# Lafferty1ab.net
KiCad netlist of a schematic drawn in EAGLE
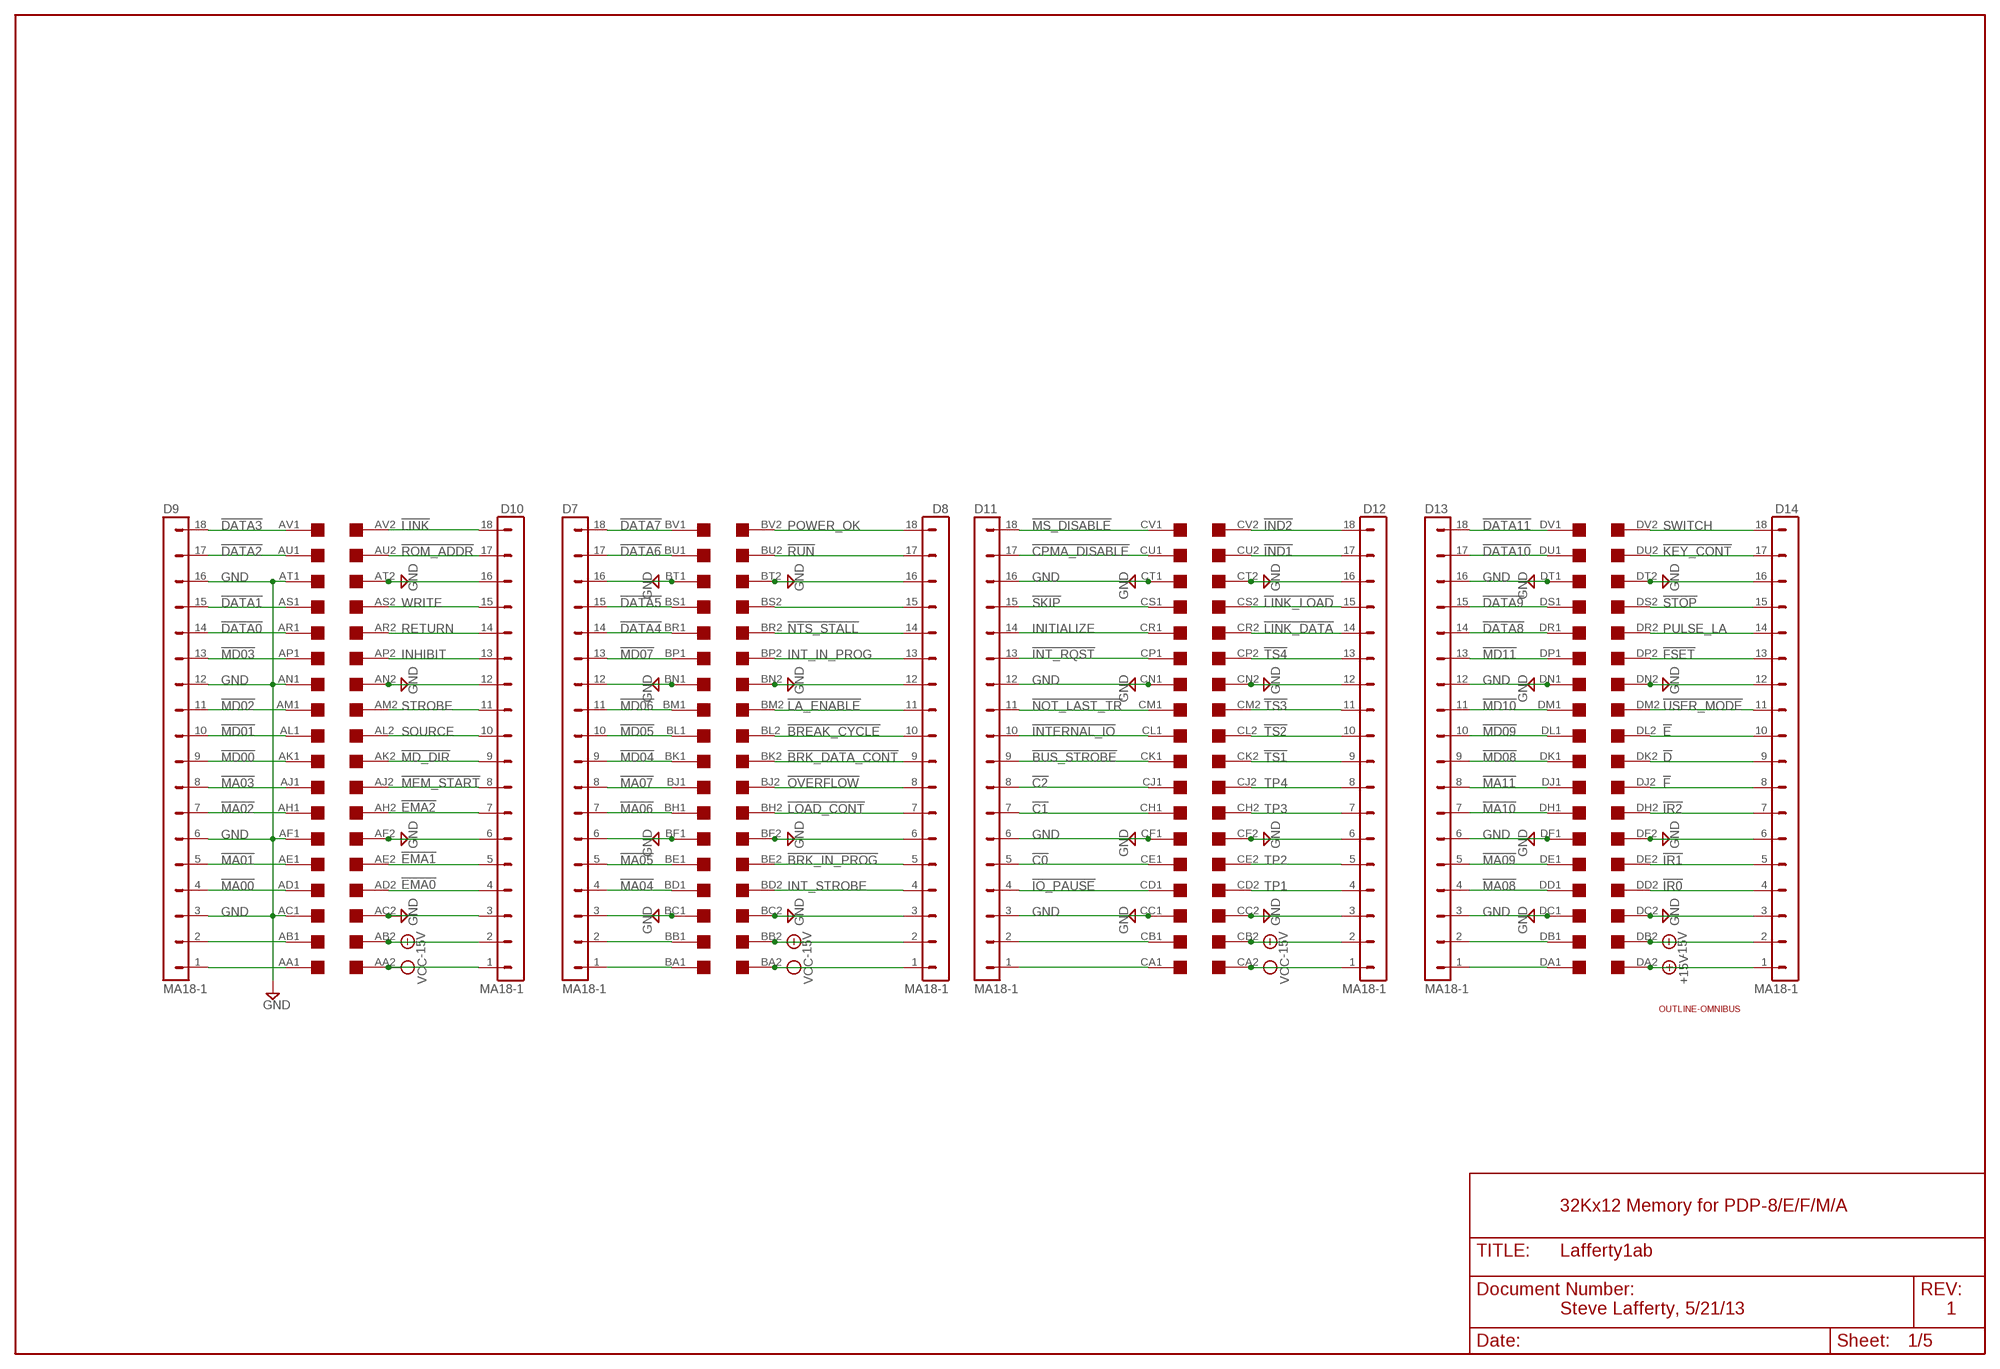
[diagram p0: schematic, sheet 1]
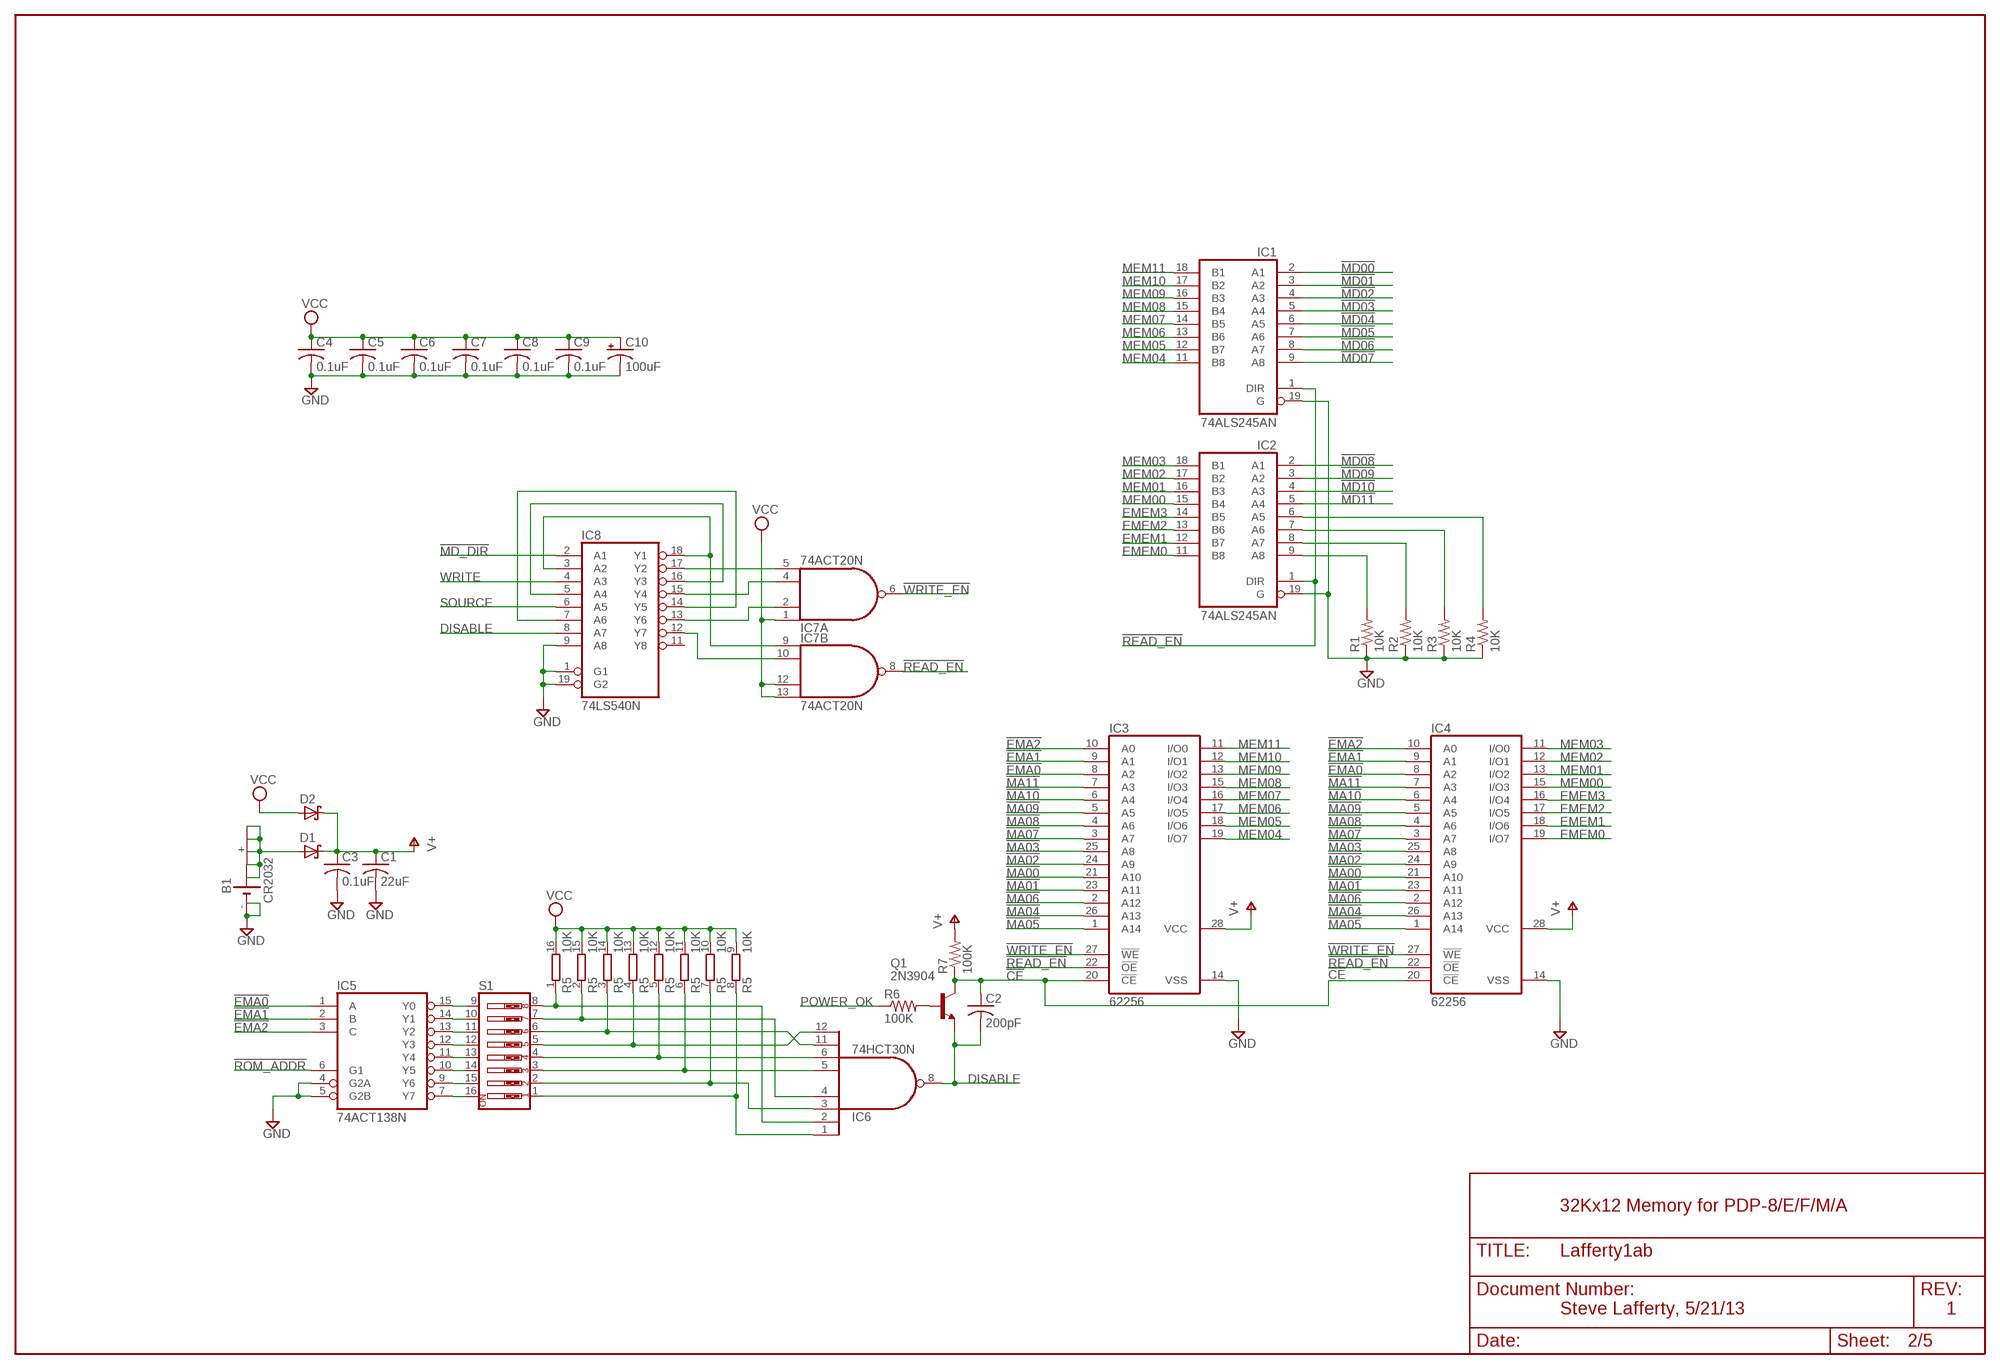
[diagram p1: schematic, sheet 2]
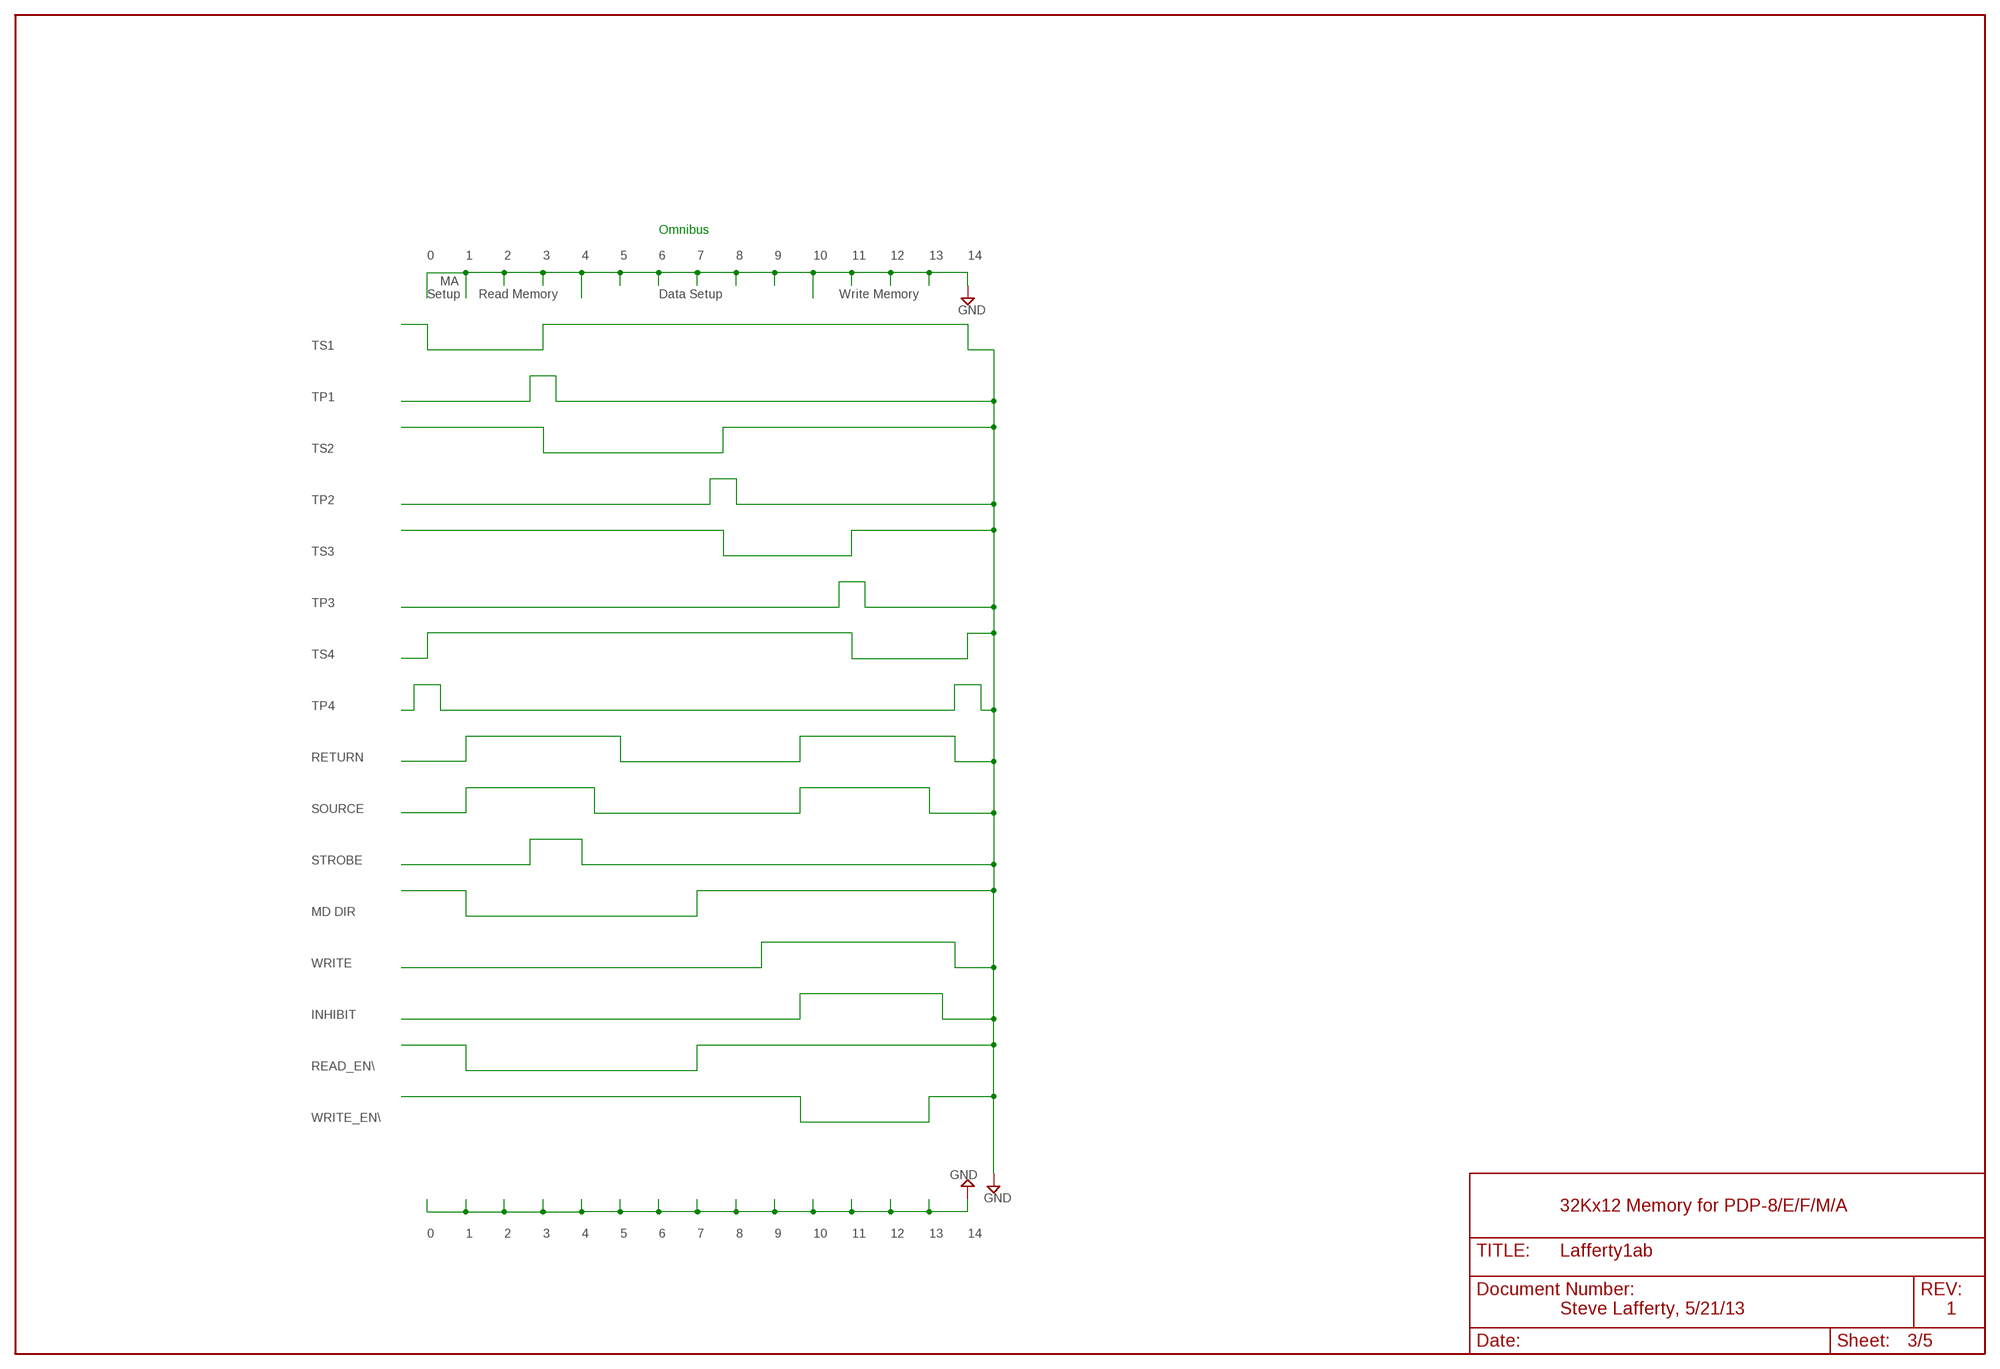
[diagram p2: schematic, sheet 3]
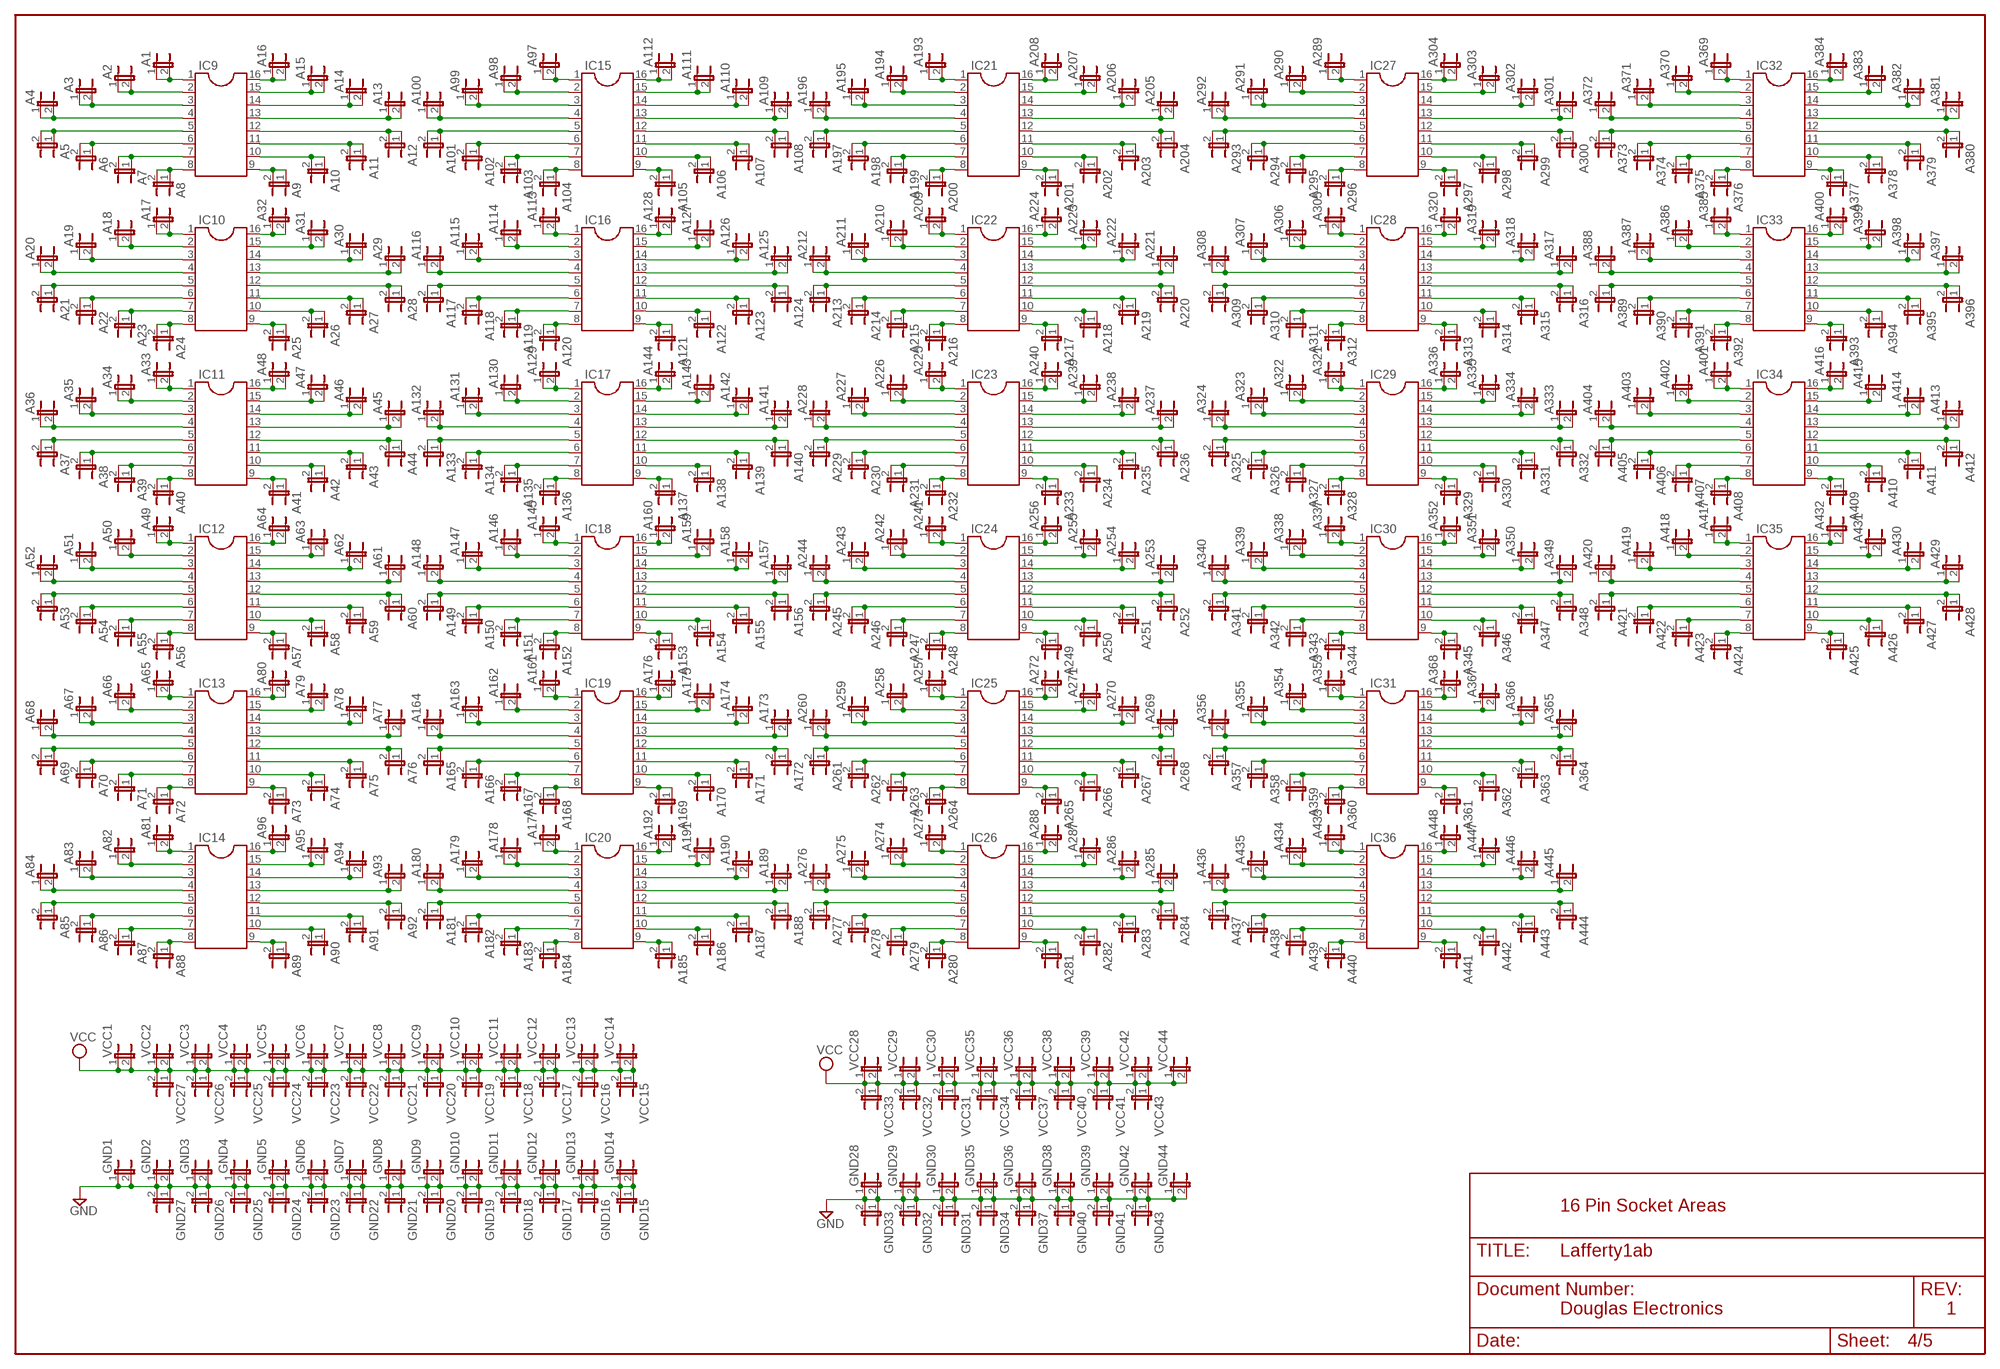
[diagram p3: schematic, sheet 4]
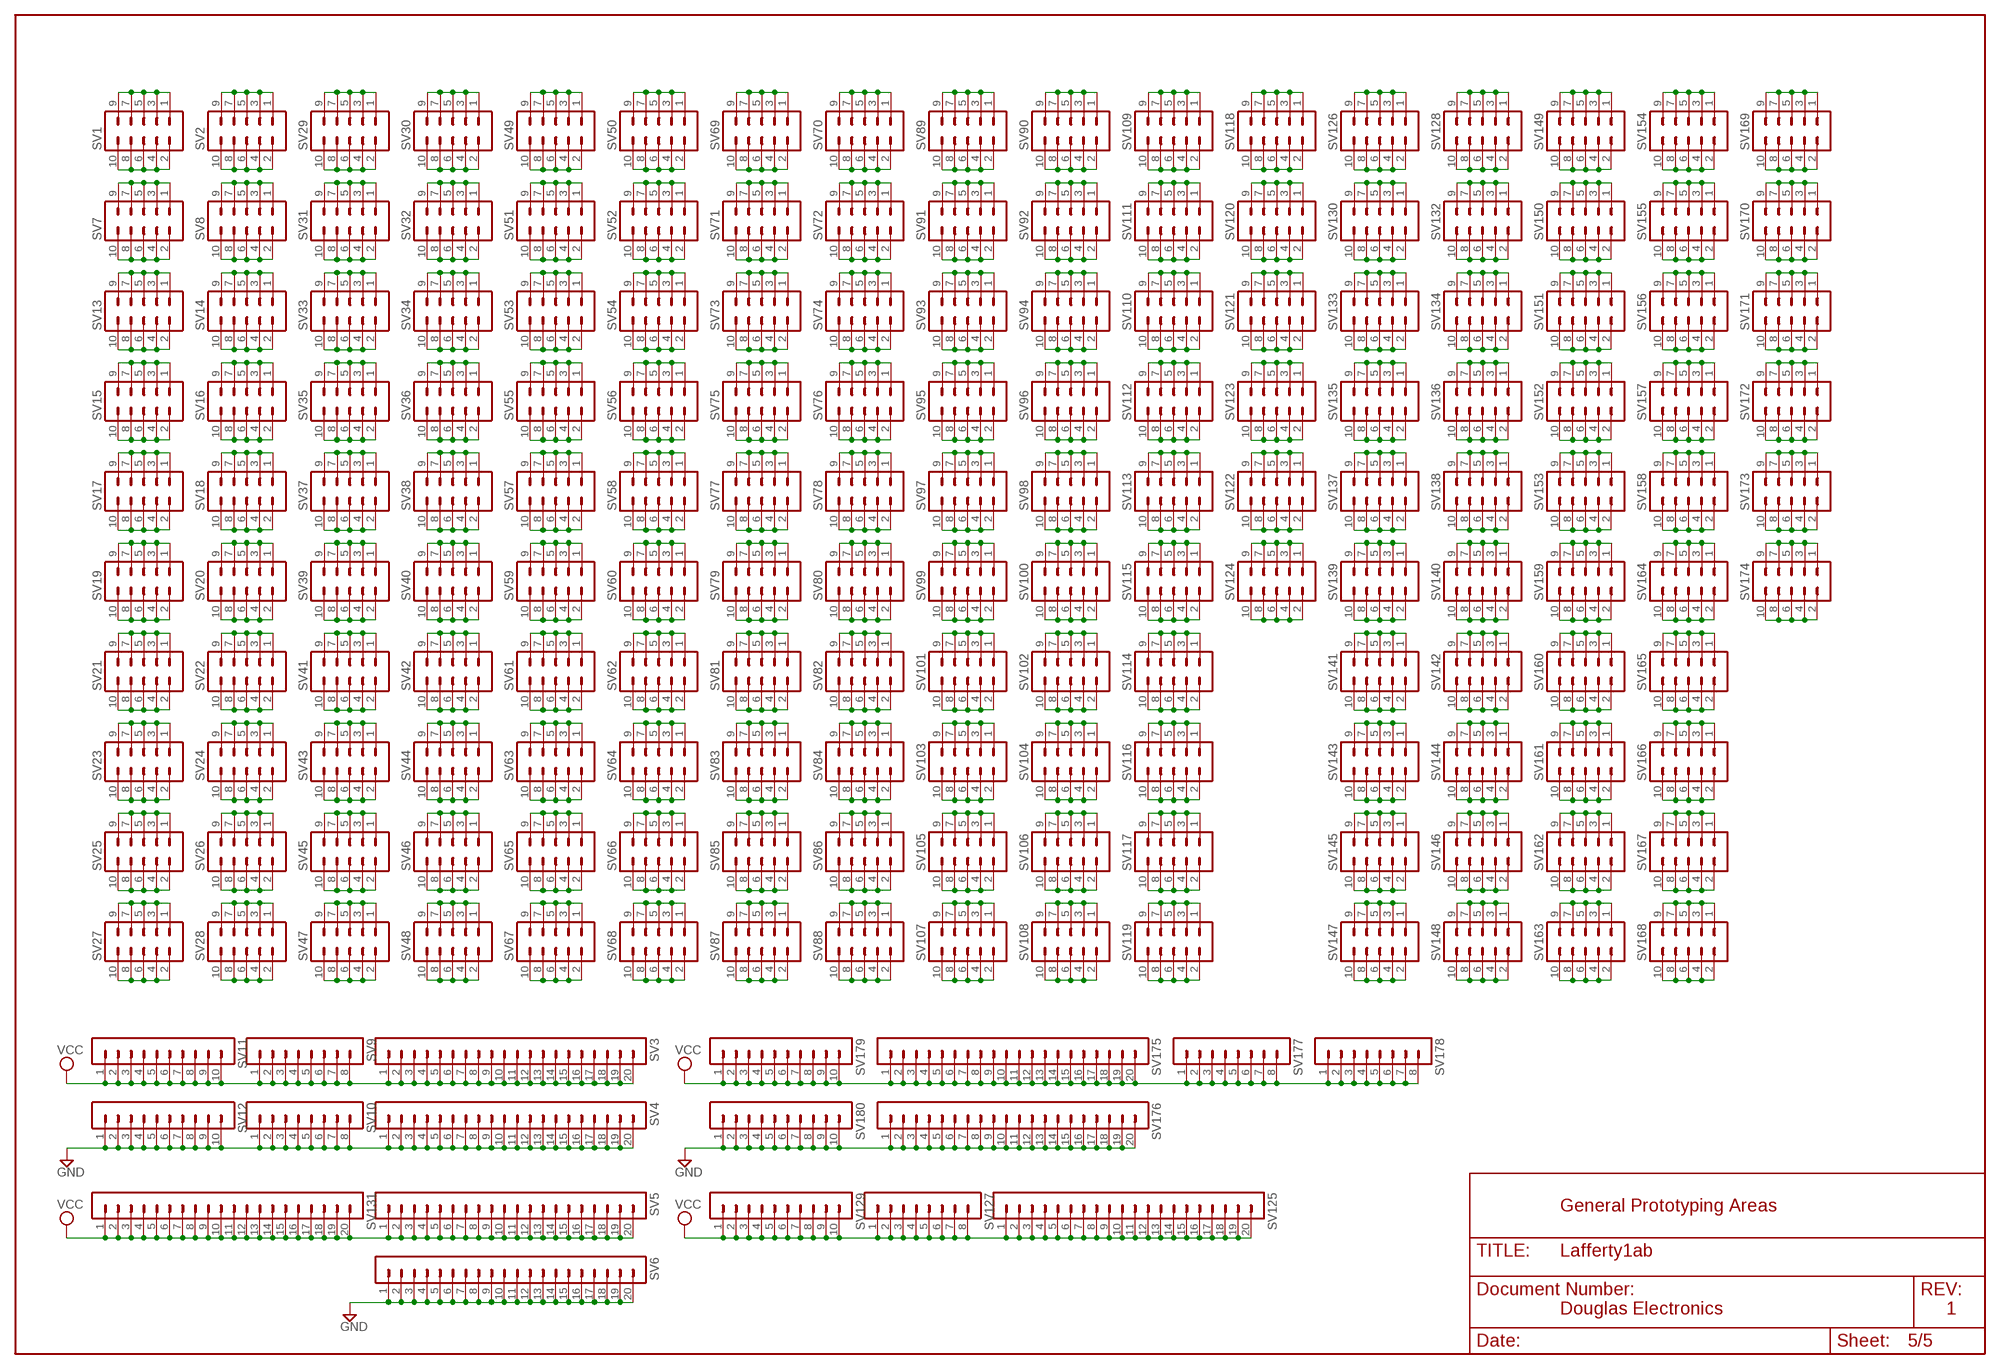
[diagram p4: schematic, sheet 5]

(export (version "E")
  (design (tool "Eeschema 10.0.6"))
  (components
    (comp (ref "D7")
      (value "MA18-1")
      (footprint "eagle-import:MA18-1")
      (libsource (lib "eagle-import") (part "MA18-1"))
    )
    (comp (ref "D8")
      (value "MA18-1")
      (footprint "eagle-import:MA18-1")
      (libsource (lib "eagle-import") (part "MA18-1"))
    )
    (comp (ref "D9")
      (value "MA18-1")
      (footprint "eagle-import:MA18-1")
      (libsource (lib "eagle-import") (part "MA18-1"))
    )
    (comp (ref "D10")
      (value "MA18-1")
      (footprint "eagle-import:MA18-1")
      (libsource (lib "eagle-import") (part "MA18-1"))
    )
    (comp (ref "D11")
      (value "MA18-1")
      (footprint "eagle-import:MA18-1")
      (libsource (lib "eagle-import") (part "MA18-1"))
    )
    (comp (ref "D12")
      (value "MA18-1")
      (footprint "eagle-import:MA18-1")
      (libsource (lib "eagle-import") (part "MA18-1"))
    )
    (comp (ref "D13")
      (value "MA18-1")
      (footprint "eagle-import:MA18-1")
      (libsource (lib "eagle-import") (part "MA18-1"))
    )
    (comp (ref "D14")
      (value "MA18-1")
      (footprint "eagle-import:MA18-1")
      (libsource (lib "eagle-import") (part "MA18-1"))
    )
    (comp (ref "U$1")
      (value "OUTLINE-OMNIBUS")
      (footprint "eagle-import:OMNIBUS")
      (libsource (lib "eagle-import") (part "OUTLINE-OMNIBUS"))
    )
    (comp (ref "U$2")
      (value "QUAD")
      (footprint "eagle-import:EDGE-CON8")
      (libsource (lib "eagle-import") (part "QUAD"))
    )
    (comp (ref "B1")
      (value "CR2032")
      (footprint "eagle-import:B2430UNI")
      (libsource (lib "eagle-import") (part "B2430UNI"))
    )
    (comp (ref "C1")
      (value "22uF")
      (footprint "eagle-import:C050-025X075")
      (libsource (lib "eagle-import") (part "C-US050-025X075"))
    )
    (comp (ref "C2")
      (value "200pF")
      (footprint "eagle-import:C050-025X075")
      (libsource (lib "eagle-import") (part "C-US050-025X075"))
    )
    (comp (ref "C3")
      (value "0.1uF")
      (footprint "eagle-import:C050-025X075")
      (libsource (lib "eagle-import") (part "C-US050-025X075"))
    )
    (comp (ref "C4")
      (value "0.1uF")
      (footprint "eagle-import:C050-025X075")
      (libsource (lib "eagle-import") (part "C-US050-025X075"))
    )
    (comp (ref "C5")
      (value "0.1uF")
      (footprint "eagle-import:C050-025X075")
      (libsource (lib "eagle-import") (part "C-US050-025X075"))
    )
    (comp (ref "C6")
      (value "0.1uF")
      (footprint "eagle-import:C050-025X075")
      (libsource (lib "eagle-import") (part "C-US050-025X075"))
    )
    (comp (ref "C7")
      (value "0.1uF")
      (footprint "eagle-import:C050-025X075")
      (libsource (lib "eagle-import") (part "C-US050-025X075"))
    )
    (comp (ref "C8")
      (value "0.1uF")
      (footprint "eagle-import:C050-025X075")
      (libsource (lib "eagle-import") (part "C-US050-025X075"))
    )
    (comp (ref "C9")
      (value "0.1uF")
      (footprint "eagle-import:C050-025X075")
      (libsource (lib "eagle-import") (part "C-US050-025X075"))
    )
    (comp (ref "C10")
      (value "100uF")
      (footprint "eagle-import:E12-8")
      (libsource (lib "eagle-import") (part "CPOL-USE20-8AXIAL"))
    )
    (comp (ref "D1")
      (value "BAT19")
      (footprint "eagle-import:DO35-10")
      (libsource (lib "eagle-import") (part "BAT19"))
    )
    (comp (ref "D2")
      (value "BAT19")
      (footprint "eagle-import:DO35-10")
      (libsource (lib "eagle-import") (part "BAT19"))
    )
    (comp (ref "IC1")
      (value "74ALS245AN")
      (footprint "eagle-import:DIL20")
      (libsource (lib "eagle-import") (part "74245NLS"))
    )
    (comp (ref "IC2")
      (value "74ALS245AN")
      (footprint "eagle-import:DIL20")
      (libsource (lib "eagle-import") (part "74245NLS"))
    )
    (comp (ref "IC3")
      (value "62256")
      (footprint "eagle-import:DIL28-6")
      (libsource (lib "eagle-import") (part "58C256P"))
    )
    (comp (ref "IC4")
      (value "62256")
      (footprint "eagle-import:DIL28-6")
      (libsource (lib "eagle-import") (part "58C256P"))
    )
    (comp (ref "IC5")
      (value "74ACT138N")
      (footprint "eagle-import:DIL16")
      (libsource (lib "eagle-import") (part "74138NLS"))
    )
    (comp (ref "IC6")
      (value "74HCT30N")
      (footprint "eagle-import:DIL14")
      (libsource (lib "eagle-import") (part "7430NLS"))
    )
    (comp (ref "IC7")
      (value "74ACT20N")
      (footprint "eagle-import:DIL14")
      (libsource (lib "eagle-import") (part "7420NLS"))
    )
    (comp (ref "IC8")
      (value "74LS540N")
      (footprint "eagle-import:DIL20")
      (libsource (lib "eagle-import") (part "74540NLS"))
    )
    (comp (ref "Q1")
      (value "2N3904")
      (footprint "eagle-import:TO92")
      (libsource (lib "eagle-import") (part "2N3904"))
    )
    (comp (ref "R1")
      (value "10K")
      (footprint "eagle-import:0207_10")
      (libsource (lib "eagle-import") (part "R-US_0207/10"))
    )
    (comp (ref "R2")
      (value "10K")
      (footprint "eagle-import:0207_10")
      (libsource (lib "eagle-import") (part "R-US_0207/10"))
    )
    (comp (ref "R3")
      (value "10K")
      (footprint "eagle-import:0207_10")
      (libsource (lib "eagle-import") (part "R-US_0207/10"))
    )
    (comp (ref "R4")
      (value "10K")
      (footprint "eagle-import:0207_10")
      (libsource (lib "eagle-import") (part "R-US_0207/10"))
    )
    (comp (ref "R5")
      (value "10K")
      (footprint "eagle-import:DIL16")
      (libsource (lib "eagle-import") (part "8R-P"))
    )
    (comp (ref "R6")
      (value "100K")
      (footprint "eagle-import:0207_10")
      (libsource (lib "eagle-import") (part "R-US_0207/10"))
    )
    (comp (ref "R7")
      (value "100K")
      (footprint "eagle-import:0207_10")
      (libsource (lib "eagle-import") (part "R-US_0207/10"))
    )
    (comp (ref "S1")
      (value "SW_DIP-8")
      (footprint "eagle-import:EDG-08")
      (libsource (lib "eagle-import") (part "SW_DIP-8"))
    )
    (comp (ref "A1")
      (value "JP1E")
      (footprint "eagle-import:JP1")
      (libsource (lib "eagle-import") (part "JP1E"))
    )
    (comp (ref "A2")
      (value "JP1E")
      (footprint "eagle-import:JP1")
      (libsource (lib "eagle-import") (part "JP1E"))
    )
    (comp (ref "A3")
      (value "JP1E")
      (footprint "eagle-import:JP1")
      (libsource (lib "eagle-import") (part "JP1E"))
    )
    (comp (ref "A4")
      (value "JP1E")
      (footprint "eagle-import:JP1")
      (libsource (lib "eagle-import") (part "JP1E"))
    )
    (comp (ref "A5")
      (value "JP1E")
      (footprint "eagle-import:JP1")
      (libsource (lib "eagle-import") (part "JP1E"))
    )
    (comp (ref "A6")
      (value "JP1E")
      (footprint "eagle-import:JP1")
      (libsource (lib "eagle-import") (part "JP1E"))
    )
    (comp (ref "A7")
      (value "JP1E")
      (footprint "eagle-import:JP1")
      (libsource (lib "eagle-import") (part "JP1E"))
    )
    (comp (ref "A8")
      (value "JP1E")
      (footprint "eagle-import:JP1")
      (libsource (lib "eagle-import") (part "JP1E"))
    )
    (comp (ref "A9")
      (value "JP1E")
      (footprint "eagle-import:JP1")
      (libsource (lib "eagle-import") (part "JP1E"))
    )
    (comp (ref "A10")
      (value "JP1E")
      (footprint "eagle-import:JP1")
      (libsource (lib "eagle-import") (part "JP1E"))
    )
    (comp (ref "A11")
      (value "JP1E")
      (footprint "eagle-import:JP1")
      (libsource (lib "eagle-import") (part "JP1E"))
    )
    (comp (ref "A12")
      (value "JP1E")
      (footprint "eagle-import:JP1")
      (libsource (lib "eagle-import") (part "JP1E"))
    )
    (comp (ref "A13")
      (value "JP1E")
      (footprint "eagle-import:JP1")
      (libsource (lib "eagle-import") (part "JP1E"))
    )
    (comp (ref "A14")
      (value "JP1E")
      (footprint "eagle-import:JP1")
      (libsource (lib "eagle-import") (part "JP1E"))
    )
    (comp (ref "A15")
      (value "JP1E")
      (footprint "eagle-import:JP1")
      (libsource (lib "eagle-import") (part "JP1E"))
    )
    (comp (ref "A16")
      (value "JP1E")
      (footprint "eagle-import:JP1")
      (libsource (lib "eagle-import") (part "JP1E"))
    )
    (comp (ref "A17")
      (value "JP1E")
      (footprint "eagle-import:JP1")
      (libsource (lib "eagle-import") (part "JP1E"))
    )
    (comp (ref "A18")
      (value "JP1E")
      (footprint "eagle-import:JP1")
      (libsource (lib "eagle-import") (part "JP1E"))
    )
    (comp (ref "A19")
      (value "JP1E")
      (footprint "eagle-import:JP1")
      (libsource (lib "eagle-import") (part "JP1E"))
    )
    (comp (ref "A20")
      (value "JP1E")
      (footprint "eagle-import:JP1")
      (libsource (lib "eagle-import") (part "JP1E"))
    )
    (comp (ref "A21")
      (value "JP1E")
      (footprint "eagle-import:JP1")
      (libsource (lib "eagle-import") (part "JP1E"))
    )
    (comp (ref "A22")
      (value "JP1E")
      (footprint "eagle-import:JP1")
      (libsource (lib "eagle-import") (part "JP1E"))
    )
    (comp (ref "A23")
      (value "JP1E")
      (footprint "eagle-import:JP1")
      (libsource (lib "eagle-import") (part "JP1E"))
    )
    (comp (ref "A24")
      (value "JP1E")
      (footprint "eagle-import:JP1")
      (libsource (lib "eagle-import") (part "JP1E"))
    )
    (comp (ref "A25")
      (value "JP1E")
      (footprint "eagle-import:JP1")
      (libsource (lib "eagle-import") (part "JP1E"))
    )
    (comp (ref "A26")
      (value "JP1E")
      (footprint "eagle-import:JP1")
      (libsource (lib "eagle-import") (part "JP1E"))
    )
    (comp (ref "A27")
      (value "JP1E")
      (footprint "eagle-import:JP1")
      (libsource (lib "eagle-import") (part "JP1E"))
    )
    (comp (ref "A28")
      (value "JP1E")
      (footprint "eagle-import:JP1")
      (libsource (lib "eagle-import") (part "JP1E"))
    )
    (comp (ref "A29")
      (value "JP1E")
      (footprint "eagle-import:JP1")
      (libsource (lib "eagle-import") (part "JP1E"))
    )
    (comp (ref "A30")
      (value "JP1E")
      (footprint "eagle-import:JP1")
      (libsource (lib "eagle-import") (part "JP1E"))
    )
    (comp (ref "A31")
      (value "JP1E")
      (footprint "eagle-import:JP1")
      (libsource (lib "eagle-import") (part "JP1E"))
    )
    (comp (ref "A32")
      (value "JP1E")
      (footprint "eagle-import:JP1")
      (libsource (lib "eagle-import") (part "JP1E"))
    )
    (comp (ref "A33")
      (value "JP1E")
      (footprint "eagle-import:JP1")
      (libsource (lib "eagle-import") (part "JP1E"))
    )
    (comp (ref "A34")
      (value "JP1E")
      (footprint "eagle-import:JP1")
      (libsource (lib "eagle-import") (part "JP1E"))
    )
    (comp (ref "A35")
      (value "JP1E")
      (footprint "eagle-import:JP1")
      (libsource (lib "eagle-import") (part "JP1E"))
    )
    (comp (ref "A36")
      (value "JP1E")
      (footprint "eagle-import:JP1")
      (libsource (lib "eagle-import") (part "JP1E"))
    )
    (comp (ref "A37")
      (value "JP1E")
      (footprint "eagle-import:JP1")
      (libsource (lib "eagle-import") (part "JP1E"))
    )
    (comp (ref "A38")
      (value "JP1E")
      (footprint "eagle-import:JP1")
      (libsource (lib "eagle-import") (part "JP1E"))
    )
    (comp (ref "A39")
      (value "JP1E")
      (footprint "eagle-import:JP1")
      (libsource (lib "eagle-import") (part "JP1E"))
    )
    (comp (ref "A40")
      (value "JP1E")
      (footprint "eagle-import:JP1")
      (libsource (lib "eagle-import") (part "JP1E"))
    )
    (comp (ref "A41")
      (value "JP1E")
      (footprint "eagle-import:JP1")
      (libsource (lib "eagle-import") (part "JP1E"))
    )
    (comp (ref "A42")
      (value "JP1E")
      (footprint "eagle-import:JP1")
      (libsource (lib "eagle-import") (part "JP1E"))
    )
    (comp (ref "A43")
      (value "JP1E")
      (footprint "eagle-import:JP1")
      (libsource (lib "eagle-import") (part "JP1E"))
    )
    (comp (ref "A44")
      (value "JP1E")
      (footprint "eagle-import:JP1")
      (libsource (lib "eagle-import") (part "JP1E"))
    )
    (comp (ref "A45")
      (value "JP1E")
      (footprint "eagle-import:JP1")
      (libsource (lib "eagle-import") (part "JP1E"))
    )
    (comp (ref "A46")
      (value "JP1E")
      (footprint "eagle-import:JP1")
      (libsource (lib "eagle-import") (part "JP1E"))
    )
    (comp (ref "A47")
      (value "JP1E")
      (footprint "eagle-import:JP1")
      (libsource (lib "eagle-import") (part "JP1E"))
    )
    (comp (ref "A48")
      (value "JP1E")
      (footprint "eagle-import:JP1")
      (libsource (lib "eagle-import") (part "JP1E"))
    )
    (comp (ref "A49")
      (value "JP1E")
      (footprint "eagle-import:JP1")
      (libsource (lib "eagle-import") (part "JP1E"))
    )
    (comp (ref "A50")
      (value "JP1E")
      (footprint "eagle-import:JP1")
      (libsource (lib "eagle-import") (part "JP1E"))
    )
    (comp (ref "A51")
      (value "JP1E")
      (footprint "eagle-import:JP1")
      (libsource (lib "eagle-import") (part "JP1E"))
    )
    (comp (ref "A52")
      (value "JP1E")
      (footprint "eagle-import:JP1")
      (libsource (lib "eagle-import") (part "JP1E"))
    )
    (comp (ref "A53")
      (value "JP1E")
      (footprint "eagle-import:JP1")
      (libsource (lib "eagle-import") (part "JP1E"))
    )
    (comp (ref "A54")
      (value "JP1E")
      (footprint "eagle-import:JP1")
      (libsource (lib "eagle-import") (part "JP1E"))
    )
    (comp (ref "A55")
      (value "JP1E")
      (footprint "eagle-import:JP1")
      (libsource (lib "eagle-import") (part "JP1E"))
    )
    (comp (ref "A56")
      (value "JP1E")
      (footprint "eagle-import:JP1")
      (libsource (lib "eagle-import") (part "JP1E"))
    )
    (comp (ref "A57")
      (value "JP1E")
      (footprint "eagle-import:JP1")
      (libsource (lib "eagle-import") (part "JP1E"))
    )
    (comp (ref "A58")
      (value "JP1E")
      (footprint "eagle-import:JP1")
      (libsource (lib "eagle-import") (part "JP1E"))
    )
    (comp (ref "A59")
      (value "JP1E")
      (footprint "eagle-import:JP1")
      (libsource (lib "eagle-import") (part "JP1E"))
    )
    (comp (ref "A60")
      (value "JP1E")
      (footprint "eagle-import:JP1")
      (libsource (lib "eagle-import") (part "JP1E"))
    )
    (comp (ref "A61")
      (value "JP1E")
      (footprint "eagle-import:JP1")
      (libsource (lib "eagle-import") (part "JP1E"))
    )
    (comp (ref "A62")
      (value "JP1E")
      (footprint "eagle-import:JP1")
      (libsource (lib "eagle-import") (part "JP1E"))
    )
    (comp (ref "A63")
      (value "JP1E")
      (footprint "eagle-import:JP1")
      (libsource (lib "eagle-import") (part "JP1E"))
    )
    (comp (ref "A64")
      (value "JP1E")
      (footprint "eagle-import:JP1")
      (libsource (lib "eagle-import") (part "JP1E"))
    )
    (comp (ref "A65")
      (value "JP1E")
      (footprint "eagle-import:JP1")
      (libsource (lib "eagle-import") (part "JP1E"))
    )
    (comp (ref "A66")
      (value "JP1E")
      (footprint "eagle-import:JP1")
      (libsource (lib "eagle-import") (part "JP1E"))
    )
    (comp (ref "A67")
      (value "JP1E")
      (footprint "eagle-import:JP1")
      (libsource (lib "eagle-import") (part "JP1E"))
    )
    (comp (ref "A68")
      (value "JP1E")
      (footprint "eagle-import:JP1")
      (libsource (lib "eagle-import") (part "JP1E"))
    )
    (comp (ref "A69")
      (value "JP1E")
      (footprint "eagle-import:JP1")
      (libsource (lib "eagle-import") (part "JP1E"))
    )
    (comp (ref "A70")
      (value "JP1E")
      (footprint "eagle-import:JP1")
      (libsource (lib "eagle-import") (part "JP1E"))
    )
    (comp (ref "A71")
      (value "JP1E")
      (footprint "eagle-import:JP1")
      (libsource (lib "eagle-import") (part "JP1E"))
    )
    (comp (ref "A72")
      (value "JP1E")
      (footprint "eagle-import:JP1")
      (libsource (lib "eagle-import") (part "JP1E"))
    )
    (comp (ref "A73")
      (value "JP1E")
      (footprint "eagle-import:JP1")
      (libsource (lib "eagle-import") (part "JP1E"))
    )
    (comp (ref "A74")
      (value "JP1E")
      (footprint "eagle-import:JP1")
      (libsource (lib "eagle-import") (part "JP1E"))
    )
    (comp (ref "A75")
      (value "JP1E")
      (footprint "eagle-import:JP1")
      (libsource (lib "eagle-import") (part "JP1E"))
    )
    (comp (ref "A76")
      (value "JP1E")
      (footprint "eagle-import:JP1")
      (libsource (lib "eagle-import") (part "JP1E"))
    )
    (comp (ref "A77")
      (value "JP1E")
      (footprint "eagle-import:JP1")
      (libsource (lib "eagle-import") (part "JP1E"))
    )
    (comp (ref "A78")
      (value "JP1E")
      (footprint "eagle-import:JP1")
      (libsource (lib "eagle-import") (part "JP1E"))
    )
    (comp (ref "A79")
      (value "JP1E")
      (footprint "eagle-import:JP1")
      (libsource (lib "eagle-import") (part "JP1E"))
    )
    (comp (ref "A80")
      (value "JP1E")
      (footprint "eagle-import:JP1")
      (libsource (lib "eagle-import") (part "JP1E"))
    )
    (comp (ref "A81")
      (value "JP1E")
      (footprint "eagle-import:JP1")
      (libsource (lib "eagle-import") (part "JP1E"))
    )
    (comp (ref "A82")
      (value "JP1E")
      (footprint "eagle-import:JP1")
      (libsource (lib "eagle-import") (part "JP1E"))
    )
    (comp (ref "A83")
      (value "JP1E")
      (footprint "eagle-import:JP1")
      (libsource (lib "eagle-import") (part "JP1E"))
    )
    (comp (ref "A84")
      (value "JP1E")
      (footprint "eagle-import:JP1")
      (libsource (lib "eagle-import") (part "JP1E"))
    )
    (comp (ref "A85")
      (value "JP1E")
      (footprint "eagle-import:JP1")
      (libsource (lib "eagle-import") (part "JP1E"))
    )
    (comp (ref "A86")
      (value "JP1E")
      (footprint "eagle-import:JP1")
      (libsource (lib "eagle-import") (part "JP1E"))
    )
    (comp (ref "A87")
      (value "JP1E")
      (footprint "eagle-import:JP1")
      (libsource (lib "eagle-import") (part "JP1E"))
    )
    (comp (ref "A88")
      (value "JP1E")
      (footprint "eagle-import:JP1")
      (libsource (lib "eagle-import") (part "JP1E"))
    )
    (comp (ref "A89")
      (value "JP1E")
      (footprint "eagle-import:JP1")
      (libsource (lib "eagle-import") (part "JP1E"))
    )
    (comp (ref "A90")
      (value "JP1E")
      (footprint "eagle-import:JP1")
      (libsource (lib "eagle-import") (part "JP1E"))
    )
    (comp (ref "A91")
      (value "JP1E")
      (footprint "eagle-import:JP1")
      (libsource (lib "eagle-import") (part "JP1E"))
    )
    (comp (ref "A92")
      (value "JP1E")
      (footprint "eagle-import:JP1")
      (libsource (lib "eagle-import") (part "JP1E"))
    )
    (comp (ref "A93")
      (value "JP1E")
      (footprint "eagle-import:JP1")
      (libsource (lib "eagle-import") (part "JP1E"))
    )
    (comp (ref "A94")
      (value "JP1E")
      (footprint "eagle-import:JP1")
      (libsource (lib "eagle-import") (part "JP1E"))
    )
    (comp (ref "A95")
      (value "JP1E")
      (footprint "eagle-import:JP1")
      (libsource (lib "eagle-import") (part "JP1E"))
    )
    (comp (ref "A96")
      (value "JP1E")
      (footprint "eagle-import:JP1")
      (libsource (lib "eagle-import") (part "JP1E"))
    )
    (comp (ref "A97")
      (value "JP1E")
      (footprint "eagle-import:JP1")
      (libsource (lib "eagle-import") (part "JP1E"))
    )
    (comp (ref "A98")
      (value "JP1E")
      (footprint "eagle-import:JP1")
      (libsource (lib "eagle-import") (part "JP1E"))
    )
    (comp (ref "A99")
      (value "JP1E")
      (footprint "eagle-import:JP1")
      (libsource (lib "eagle-import") (part "JP1E"))
    )
    (comp (ref "A100")
      (value "JP1E")
      (footprint "eagle-import:JP1")
      (libsource (lib "eagle-import") (part "JP1E"))
    )
    (comp (ref "A101")
      (value "JP1E")
      (footprint "eagle-import:JP1")
      (libsource (lib "eagle-import") (part "JP1E"))
    )
    (comp (ref "A102")
      (value "JP1E")
      (footprint "eagle-import:JP1")
      (libsource (lib "eagle-import") (part "JP1E"))
    )
    (comp (ref "A103")
      (value "JP1E")
      (footprint "eagle-import:JP1")
      (libsource (lib "eagle-import") (part "JP1E"))
    )
    (comp (ref "A104")
      (value "JP1E")
      (footprint "eagle-import:JP1")
      (libsource (lib "eagle-import") (part "JP1E"))
    )
    (comp (ref "A105")
      (value "JP1E")
      (footprint "eagle-import:JP1")
      (libsource (lib "eagle-import") (part "JP1E"))
    )
    (comp (ref "A106")
      (value "JP1E")
      (footprint "eagle-import:JP1")
      (libsource (lib "eagle-import") (part "JP1E"))
    )
    (comp (ref "A107")
      (value "JP1E")
      (footprint "eagle-import:JP1")
      (libsource (lib "eagle-import") (part "JP1E"))
    )
    (comp (ref "A108")
      (value "JP1E")
      (footprint "eagle-import:JP1")
      (libsource (lib "eagle-import") (part "JP1E"))
    )
    (comp (ref "A109")
      (value "JP1E")
      (footprint "eagle-import:JP1")
      (libsource (lib "eagle-import") (part "JP1E"))
    )
    (comp (ref "A110")
      (value "JP1E")
      (footprint "eagle-import:JP1")
      (libsource (lib "eagle-import") (part "JP1E"))
    )
    (comp (ref "A111")
      (value "JP1E")
      (footprint "eagle-import:JP1")
      (libsource (lib "eagle-import") (part "JP1E"))
    )
    (comp (ref "A112")
      (value "JP1E")
      (footprint "eagle-import:JP1")
      (libsource (lib "eagle-import") (part "JP1E"))
    )
    (comp (ref "A113")
      (value "JP1E")
      (footprint "eagle-import:JP1")
      (libsource (lib "eagle-import") (part "JP1E"))
    )
    (comp (ref "A114")
      (value "JP1E")
      (footprint "eagle-import:JP1")
      (libsource (lib "eagle-import") (part "JP1E"))
    )
    (comp (ref "A115")
      (value "JP1E")
      (footprint "eagle-import:JP1")
      (libsource (lib "eagle-import") (part "JP1E"))
    )
    (comp (ref "A116")
      (value "JP1E")
      (footprint "eagle-import:JP1")
      (libsource (lib "eagle-import") (part "JP1E"))
    )
    (comp (ref "A117")
      (value "JP1E")
      (footprint "eagle-import:JP1")
      (libsource (lib "eagle-import") (part "JP1E"))
    )
    (comp (ref "A118")
      (value "JP1E")
      (footprint "eagle-import:JP1")
      (libsource (lib "eagle-import") (part "JP1E"))
    )
    (comp (ref "A119")
      (value "JP1E")
      (footprint "eagle-import:JP1")
      (libsource (lib "eagle-import") (part "JP1E"))
    )
    (comp (ref "A120")
      (value "JP1E")
      (footprint "eagle-import:JP1")
      (libsource (lib "eagle-import") (part "JP1E"))
    )
    (comp (ref "A121")
      (value "JP1E")
      (footprint "eagle-import:JP1")
      (libsource (lib "eagle-import") (part "JP1E"))
    )
    (comp (ref "A122")
      (value "JP1E")
      (footprint "eagle-import:JP1")
      (libsource (lib "eagle-import") (part "JP1E"))
    )
    (comp (ref "A123")
      (value "JP1E")
      (footprint "eagle-import:JP1")
      (libsource (lib "eagle-import") (part "JP1E"))
    )
    (comp (ref "A124")
      (value "JP1E")
      (footprint "eagle-import:JP1")
      (libsource (lib "eagle-import") (part "JP1E"))
    )
    (comp (ref "A125")
      (value "JP1E")
      (footprint "eagle-import:JP1")
      (libsource (lib "eagle-import") (part "JP1E"))
    )
    (comp (ref "A126")
      (value "JP1E")
      (footprint "eagle-import:JP1")
      (libsource (lib "eagle-import") (part "JP1E"))
    )
    (comp (ref "A127")
      (value "JP1E")
      (footprint "eagle-import:JP1")
      (libsource (lib "eagle-import") (part "JP1E"))
    )
    (comp (ref "A128")
      (value "JP1E")
      (footprint "eagle-import:JP1")
      (libsource (lib "eagle-import") (part "JP1E"))
    )
    (comp (ref "A129")
      (value "JP1E")
      (footprint "eagle-import:JP1")
      (libsource (lib "eagle-import") (part "JP1E"))
    )
    (comp (ref "A130")
      (value "JP1E")
      (footprint "eagle-import:JP1")
      (libsource (lib "eagle-import") (part "JP1E"))
    )
    (comp (ref "A131")
      (value "JP1E")
      (footprint "eagle-import:JP1")
      (libsource (lib "eagle-import") (part "JP1E"))
    )
    (comp (ref "A132")
      (value "JP1E")
      (footprint "eagle-import:JP1")
      (libsource (lib "eagle-import") (part "JP1E"))
    )
    (comp (ref "A133")
      (value "JP1E")
      (footprint "eagle-import:JP1")
      (libsource (lib "eagle-import") (part "JP1E"))
    )
    (comp (ref "A134")
      (value "JP1E")
      (footprint "eagle-import:JP1")
      (libsource (lib "eagle-import") (part "JP1E"))
    )
    (comp (ref "A135")
      (value "JP1E")
      (footprint "eagle-import:JP1")
      (libsource (lib "eagle-import") (part "JP1E"))
    )
    (comp (ref "A136")
      (value "JP1E")
      (footprint "eagle-import:JP1")
      (libsource (lib "eagle-import") (part "JP1E"))
    )
    (comp (ref "A137")
      (value "JP1E")
      (footprint "eagle-import:JP1")
      (libsource (lib "eagle-import") (part "JP1E"))
    )
    (comp (ref "A138")
      (value "JP1E")
      (footprint "eagle-import:JP1")
      (libsource (lib "eagle-import") (part "JP1E"))
    )
    (comp (ref "A139")
      (value "JP1E")
      (footprint "eagle-import:JP1")
      (libsource (lib "eagle-import") (part "JP1E"))
    )
    (comp (ref "A140")
      (value "JP1E")
      (footprint "eagle-import:JP1")
      (libsource (lib "eagle-import") (part "JP1E"))
    )
    (comp (ref "A141")
      (value "JP1E")
      (footprint "eagle-import:JP1")
      (libsource (lib "eagle-import") (part "JP1E"))
    )
    (comp (ref "A142")
      (value "JP1E")
      (footprint "eagle-import:JP1")
      (libsource (lib "eagle-import") (part "JP1E"))
    )
    (comp (ref "A143")
      (value "JP1E")
      (footprint "eagle-import:JP1")
      (libsource (lib "eagle-import") (part "JP1E"))
    )
    (comp (ref "A144")
      (value "JP1E")
      (footprint "eagle-import:JP1")
      (libsource (lib "eagle-import") (part "JP1E"))
    )
    (comp (ref "A145")
      (value "JP1E")
      (footprint "eagle-import:JP1")
      (libsource (lib "eagle-import") (part "JP1E"))
    )
    (comp (ref "A146")
      (value "JP1E")
      (footprint "eagle-import:JP1")
      (libsource (lib "eagle-import") (part "JP1E"))
    )
    (comp (ref "A147")
      (value "JP1E")
      (footprint "eagle-import:JP1")
      (libsource (lib "eagle-import") (part "JP1E"))
    )
    (comp (ref "A148")
      (value "JP1E")
      (footprint "eagle-import:JP1")
      (libsource (lib "eagle-import") (part "JP1E"))
    )
    (comp (ref "A149")
      (value "JP1E")
      (footprint "eagle-import:JP1")
      (libsource (lib "eagle-import") (part "JP1E"))
    )
    (comp (ref "A150")
      (value "JP1E")
      (footprint "eagle-import:JP1")
      (libsource (lib "eagle-import") (part "JP1E"))
    )
    (comp (ref "A151")
      (value "JP1E")
      (footprint "eagle-import:JP1")
      (libsource (lib "eagle-import") (part "JP1E"))
    )
    (comp (ref "A152")
      (value "JP1E")
      (footprint "eagle-import:JP1")
      (libsource (lib "eagle-import") (part "JP1E"))
    )
    (comp (ref "A153")
      (value "JP1E")
      (footprint "eagle-import:JP1")
      (libsource (lib "eagle-import") (part "JP1E"))
    )
    (comp (ref "A154")
      (value "JP1E")
      (footprint "eagle-import:JP1")
      (libsource (lib "eagle-import") (part "JP1E"))
    )
    (comp (ref "A155")
      (value "JP1E")
      (footprint "eagle-import:JP1")
      (libsource (lib "eagle-import") (part "JP1E"))
    )
    (comp (ref "A156")
      (value "JP1E")
      (footprint "eagle-import:JP1")
      (libsource (lib "eagle-import") (part "JP1E"))
    )
    (comp (ref "A157")
      (value "JP1E")
      (footprint "eagle-import:JP1")
      (libsource (lib "eagle-import") (part "JP1E"))
    )
    (comp (ref "A158")
      (value "JP1E")
      (footprint "eagle-import:JP1")
      (libsource (lib "eagle-import") (part "JP1E"))
    )
    (comp (ref "A159")
      (value "JP1E")
      (footprint "eagle-import:JP1")
      (libsource (lib "eagle-import") (part "JP1E"))
    )
    (comp (ref "A160")
      (value "JP1E")
      (footprint "eagle-import:JP1")
      (libsource (lib "eagle-import") (part "JP1E"))
    )
    (comp (ref "A161")
      (value "JP1E")
      (footprint "eagle-import:JP1")
      (libsource (lib "eagle-import") (part "JP1E"))
    )
    (comp (ref "A162")
      (value "JP1E")
      (footprint "eagle-import:JP1")
      (libsource (lib "eagle-import") (part "JP1E"))
    )
    (comp (ref "A163")
      (value "JP1E")
      (footprint "eagle-import:JP1")
      (libsource (lib "eagle-import") (part "JP1E"))
    )
    (comp (ref "A164")
      (value "JP1E")
      (footprint "eagle-import:JP1")
      (libsource (lib "eagle-import") (part "JP1E"))
    )
    (comp (ref "A165")
      (value "JP1E")
      (footprint "eagle-import:JP1")
      (libsource (lib "eagle-import") (part "JP1E"))
    )
    (comp (ref "A166")
      (value "JP1E")
      (footprint "eagle-import:JP1")
      (libsource (lib "eagle-import") (part "JP1E"))
    )
    (comp (ref "A167")
      (value "JP1E")
      (footprint "eagle-import:JP1")
      (libsource (lib "eagle-import") (part "JP1E"))
    )
    (comp (ref "A168")
      (value "JP1E")
      (footprint "eagle-import:JP1")
      (libsource (lib "eagle-import") (part "JP1E"))
    )
    (comp (ref "A169")
      (value "JP1E")
      (footprint "eagle-import:JP1")
      (libsource (lib "eagle-import") (part "JP1E"))
    )
    (comp (ref "A170")
      (value "JP1E")
      (footprint "eagle-import:JP1")
      (libsource (lib "eagle-import") (part "JP1E"))
    )
    (comp (ref "A171")
      (value "JP1E")
      (footprint "eagle-import:JP1")
      (libsource (lib "eagle-import") (part "JP1E"))
    )
    (comp (ref "A172")
      (value "JP1E")
      (footprint "eagle-import:JP1")
      (libsource (lib "eagle-import") (part "JP1E"))
    )
    (comp (ref "A173")
      (value "JP1E")
      (footprint "eagle-import:JP1")
      (libsource (lib "eagle-import") (part "JP1E"))
    )
    (comp (ref "A174")
      (value "JP1E")
      (footprint "eagle-import:JP1")
      (libsource (lib "eagle-import") (part "JP1E"))
    )
    (comp (ref "A175")
      (value "JP1E")
      (footprint "eagle-import:JP1")
      (libsource (lib "eagle-import") (part "JP1E"))
    )
    (comp (ref "A176")
      (value "JP1E")
      (footprint "eagle-import:JP1")
      (libsource (lib "eagle-import") (part "JP1E"))
    )
    (comp (ref "A177")
      (value "JP1E")
      (footprint "eagle-import:JP1")
      (libsource (lib "eagle-import") (part "JP1E"))
    )
    (comp (ref "A178")
      (value "JP1E")
      (footprint "eagle-import:JP1")
      (libsource (lib "eagle-import") (part "JP1E"))
    )
    (comp (ref "A179")
      (value "JP1E")
      (footprint "eagle-import:JP1")
      (libsource (lib "eagle-import") (part "JP1E"))
    )
    (comp (ref "A180")
      (value "JP1E")
      (footprint "eagle-import:JP1")
      (libsource (lib "eagle-import") (part "JP1E"))
    )
    (comp (ref "A181")
      (value "JP1E")
      (footprint "eagle-import:JP1")
      (libsource (lib "eagle-import") (part "JP1E"))
    )
    (comp (ref "A182")
      (value "JP1E")
      (footprint "eagle-import:JP1")
      (libsource (lib "eagle-import") (part "JP1E"))
    )
    (comp (ref "A183")
      (value "JP1E")
      (footprint "eagle-import:JP1")
      (libsource (lib "eagle-import") (part "JP1E"))
    )
    (comp (ref "A184")
      (value "JP1E")
      (footprint "eagle-import:JP1")
      (libsource (lib "eagle-import") (part "JP1E"))
    )
    (comp (ref "A185")
      (value "JP1E")
      (footprint "eagle-import:JP1")
      (libsource (lib "eagle-import") (part "JP1E"))
    )
    (comp (ref "A186")
      (value "JP1E")
      (footprint "eagle-import:JP1")
      (libsource (lib "eagle-import") (part "JP1E"))
    )
    (comp (ref "A187")
      (value "JP1E")
      (footprint "eagle-import:JP1")
      (libsource (lib "eagle-import") (part "JP1E"))
    )
    (comp (ref "A188")
      (value "JP1E")
      (footprint "eagle-import:JP1")
      (libsource (lib "eagle-import") (part "JP1E"))
    )
    (comp (ref "A189")
      (value "JP1E")
      (footprint "eagle-import:JP1")
      (libsource (lib "eagle-import") (part "JP1E"))
    )
    (comp (ref "A190")
      (value "JP1E")
      (footprint "eagle-import:JP1")
      (libsource (lib "eagle-import") (part "JP1E"))
    )
    (comp (ref "A191")
      (value "JP1E")
      (footprint "eagle-import:JP1")
      (libsource (lib "eagle-import") (part "JP1E"))
    )
    (comp (ref "A192")
      (value "JP1E")
      (footprint "eagle-import:JP1")
      (libsource (lib "eagle-import") (part "JP1E"))
    )
    (comp (ref "A193")
      (value "JP1E")
      (footprint "eagle-import:JP1")
      (libsource (lib "eagle-import") (part "JP1E"))
    )
    (comp (ref "A194")
      (value "JP1E")
      (footprint "eagle-import:JP1")
      (libsource (lib "eagle-import") (part "JP1E"))
    )
    (comp (ref "A195")
      (value "JP1E")
      (footprint "eagle-import:JP1")
      (libsource (lib "eagle-import") (part "JP1E"))
    )
    (comp (ref "A196")
      (value "JP1E")
      (footprint "eagle-import:JP1")
      (libsource (lib "eagle-import") (part "JP1E"))
    )
    (comp (ref "A197")
      (value "JP1E")
      (footprint "eagle-import:JP1")
      (libsource (lib "eagle-import") (part "JP1E"))
    )
    (comp (ref "A198")
      (value "JP1E")
      (footprint "eagle-import:JP1")
      (libsource (lib "eagle-import") (part "JP1E"))
    )
    (comp (ref "A199")
      (value "JP1E")
      (footprint "eagle-import:JP1")
      (libsource (lib "eagle-import") (part "JP1E"))
    )
    (comp (ref "A200")
      (value "JP1E")
      (footprint "eagle-import:JP1")
      (libsource (lib "eagle-import") (part "JP1E"))
    )
    (comp (ref "A201")
      (value "JP1E")
      (footprint "eagle-import:JP1")
      (libsource (lib "eagle-import") (part "JP1E"))
    )
    (comp (ref "A202")
      (value "JP1E")
      (footprint "eagle-import:JP1")
      (libsource (lib "eagle-import") (part "JP1E"))
    )
    (comp (ref "A203")
      (value "JP1E")
      (footprint "eagle-import:JP1")
      (libsource (lib "eagle-import") (part "JP1E"))
    )
    (comp (ref "A204")
      (value "JP1E")
      (footprint "eagle-import:JP1")
      (libsource (lib "eagle-import") (part "JP1E"))
    )
    (comp (ref "A205")
      (value "JP1E")
      (footprint "eagle-import:JP1")
      (libsource (lib "eagle-import") (part "JP1E"))
    )
    (comp (ref "A206")
      (value "JP1E")
      (footprint "eagle-import:JP1")
      (libsource (lib "eagle-import") (part "JP1E"))
    )
    (comp (ref "A207")
      (value "JP1E")
      (footprint "eagle-import:JP1")
      (libsource (lib "eagle-import") (part "JP1E"))
    )
    (comp (ref "A208")
      (value "JP1E")
      (footprint "eagle-import:JP1")
      (libsource (lib "eagle-import") (part "JP1E"))
    )
    (comp (ref "A209")
      (value "JP1E")
      (footprint "eagle-import:JP1")
      (libsource (lib "eagle-import") (part "JP1E"))
    )
    (comp (ref "A210")
      (value "JP1E")
      (footprint "eagle-import:JP1")
      (libsource (lib "eagle-import") (part "JP1E"))
    )
    (comp (ref "A211")
      (value "JP1E")
      (footprint "eagle-import:JP1")
      (libsource (lib "eagle-import") (part "JP1E"))
    )
    (comp (ref "A212")
      (value "JP1E")
      (footprint "eagle-import:JP1")
      (libsource (lib "eagle-import") (part "JP1E"))
    )
    (comp (ref "A213")
      (value "JP1E")
      (footprint "eagle-import:JP1")
      (libsource (lib "eagle-import") (part "JP1E"))
    )
    (comp (ref "A214")
      (value "JP1E")
      (footprint "eagle-import:JP1")
      (libsource (lib "eagle-import") (part "JP1E"))
    )
    (comp (ref "A215")
      (value "JP1E")
      (footprint "eagle-import:JP1")
      (libsource (lib "eagle-import") (part "JP1E"))
    )
    (comp (ref "A216")
      (value "JP1E")
      (footprint "eagle-import:JP1")
      (libsource (lib "eagle-import") (part "JP1E"))
    )
    (comp (ref "A217")
      (value "JP1E")
      (footprint "eagle-import:JP1")
      (libsource (lib "eagle-import") (part "JP1E"))
    )
    (comp (ref "A218")
      (value "JP1E")
      (footprint "eagle-import:JP1")
      (libsource (lib "eagle-import") (part "JP1E"))
    )
    (comp (ref "A219")
      (value "JP1E")
      (footprint "eagle-import:JP1")
      (libsource (lib "eagle-import") (part "JP1E"))
    )
    (comp (ref "A220")
      (value "JP1E")
      (footprint "eagle-import:JP1")
      (libsource (lib "eagle-import") (part "JP1E"))
    )
    (comp (ref "A221")
      (value "JP1E")
      (footprint "eagle-import:JP1")
      (libsource (lib "eagle-import") (part "JP1E"))
    )
    (comp (ref "A222")
      (value "JP1E")
      (footprint "eagle-import:JP1")
      (libsource (lib "eagle-import") (part "JP1E"))
    )
    (comp (ref "A223")
      (value "JP1E")
      (footprint "eagle-import:JP1")
      (libsource (lib "eagle-import") (part "JP1E"))
    )
    (comp (ref "A224")
      (value "JP1E")
      (footprint "eagle-import:JP1")
      (libsource (lib "eagle-import") (part "JP1E"))
    )
    (comp (ref "A225")
      (value "JP1E")
      (footprint "eagle-import:JP1")
      (libsource (lib "eagle-import") (part "JP1E"))
    )
    (comp (ref "A226")
      (value "JP1E")
      (footprint "eagle-import:JP1")
      (libsource (lib "eagle-import") (part "JP1E"))
    )
    (comp (ref "A227")
      (value "JP1E")
      (footprint "eagle-import:JP1")
      (libsource (lib "eagle-import") (part "JP1E"))
    )
    (comp (ref "A228")
      (value "JP1E")
      (footprint "eagle-import:JP1")
      (libsource (lib "eagle-import") (part "JP1E"))
    )
    (comp (ref "A229")
      (value "JP1E")
      (footprint "eagle-import:JP1")
      (libsource (lib "eagle-import") (part "JP1E"))
    )
    (comp (ref "A230")
      (value "JP1E")
      (footprint "eagle-import:JP1")
      (libsource (lib "eagle-import") (part "JP1E"))
    )
    (comp (ref "A231")
      (value "JP1E")
      (footprint "eagle-import:JP1")
      (libsource (lib "eagle-import") (part "JP1E"))
    )
    (comp (ref "A232")
      (value "JP1E")
      (footprint "eagle-import:JP1")
      (libsource (lib "eagle-import") (part "JP1E"))
    )
    (comp (ref "A233")
      (value "JP1E")
      (footprint "eagle-import:JP1")
      (libsource (lib "eagle-import") (part "JP1E"))
    )
    (comp (ref "A234")
      (value "JP1E")
      (footprint "eagle-import:JP1")
      (libsource (lib "eagle-import") (part "JP1E"))
    )
    (comp (ref "A235")
      (value "JP1E")
      (footprint "eagle-import:JP1")
      (libsource (lib "eagle-import") (part "JP1E"))
    )
    (comp (ref "A236")
      (value "JP1E")
      (footprint "eagle-import:JP1")
      (libsource (lib "eagle-import") (part "JP1E"))
    )
    (comp (ref "A237")
      (value "JP1E")
      (footprint "eagle-import:JP1")
      (libsource (lib "eagle-import") (part "JP1E"))
    )
    (comp (ref "A238")
      (value "JP1E")
      (footprint "eagle-import:JP1")
      (libsource (lib "eagle-import") (part "JP1E"))
    )
    (comp (ref "A239")
      (value "JP1E")
      (footprint "eagle-import:JP1")
      (libsource (lib "eagle-import") (part "JP1E"))
    )
    (comp (ref "A240")
      (value "JP1E")
      (footprint "eagle-import:JP1")
      (libsource (lib "eagle-import") (part "JP1E"))
    )
    (comp (ref "A241")
      (value "JP1E")
      (footprint "eagle-import:JP1")
      (libsource (lib "eagle-import") (part "JP1E"))
    )
    (comp (ref "A242")
      (value "JP1E")
      (footprint "eagle-import:JP1")
      (libsource (lib "eagle-import") (part "JP1E"))
    )
    (comp (ref "A243")
      (value "JP1E")
      (footprint "eagle-import:JP1")
      (libsource (lib "eagle-import") (part "JP1E"))
    )
    (comp (ref "A244")
      (value "JP1E")
      (footprint "eagle-import:JP1")
      (libsource (lib "eagle-import") (part "JP1E"))
    )
    (comp (ref "A245")
      (value "JP1E")
      (footprint "eagle-import:JP1")
      (libsource (lib "eagle-import") (part "JP1E"))
    )
    (comp (ref "A246")
      (value "JP1E")
      (footprint "eagle-import:JP1")
      (libsource (lib "eagle-import") (part "JP1E"))
    )
    (comp (ref "A247")
      (value "JP1E")
      (footprint "eagle-import:JP1")
      (libsource (lib "eagle-import") (part "JP1E"))
    )
    (comp (ref "A248")
      (value "JP1E")
      (footprint "eagle-import:JP1")
      (libsource (lib "eagle-import") (part "JP1E"))
    )
    (comp (ref "A249")
      (value "JP1E")
      (footprint "eagle-import:JP1")
      (libsource (lib "eagle-import") (part "JP1E"))
    )
    (comp (ref "A250")
      (value "JP1E")
      (footprint "eagle-import:JP1")
      (libsource (lib "eagle-import") (part "JP1E"))
    )
    (comp (ref "A251")
      (value "JP1E")
      (footprint "eagle-import:JP1")
      (libsource (lib "eagle-import") (part "JP1E"))
    )
    (comp (ref "A252")
      (value "JP1E")
      (footprint "eagle-import:JP1")
      (libsource (lib "eagle-import") (part "JP1E"))
    )
    (comp (ref "A253")
      (value "JP1E")
      (footprint "eagle-import:JP1")
      (libsource (lib "eagle-import") (part "JP1E"))
    )
    (comp (ref "A254")
      (value "JP1E")
      (footprint "eagle-import:JP1")
      (libsource (lib "eagle-import") (part "JP1E"))
    )
    (comp (ref "A255")
      (value "JP1E")
      (footprint "eagle-import:JP1")
      (libsource (lib "eagle-import") (part "JP1E"))
    )
    (comp (ref "A256")
      (value "JP1E")
      (footprint "eagle-import:JP1")
      (libsource (lib "eagle-import") (part "JP1E"))
    )
    (comp (ref "A257")
      (value "JP1E")
      (footprint "eagle-import:JP1")
      (libsource (lib "eagle-import") (part "JP1E"))
    )
    (comp (ref "A258")
      (value "JP1E")
      (footprint "eagle-import:JP1")
      (libsource (lib "eagle-import") (part "JP1E"))
    )
    (comp (ref "A259")
      (value "JP1E")
      (footprint "eagle-import:JP1")
      (libsource (lib "eagle-import") (part "JP1E"))
    )
    (comp (ref "A260")
      (value "JP1E")
      (footprint "eagle-import:JP1")
      (libsource (lib "eagle-import") (part "JP1E"))
    )
    (comp (ref "A261")
      (value "JP1E")
      (footprint "eagle-import:JP1")
      (libsource (lib "eagle-import") (part "JP1E"))
    )
    (comp (ref "A262")
      (value "JP1E")
      (footprint "eagle-import:JP1")
      (libsource (lib "eagle-import") (part "JP1E"))
    )
    (comp (ref "A263")
      (value "JP1E")
      (footprint "eagle-import:JP1")
      (libsource (lib "eagle-import") (part "JP1E"))
    )
    (comp (ref "A264")
      (value "JP1E")
      (footprint "eagle-import:JP1")
      (libsource (lib "eagle-import") (part "JP1E"))
    )
    (comp (ref "A265")
      (value "JP1E")
      (footprint "eagle-import:JP1")
      (libsource (lib "eagle-import") (part "JP1E"))
    )
    (comp (ref "A266")
      (value "JP1E")
      (footprint "eagle-import:JP1")
      (libsource (lib "eagle-import") (part "JP1E"))
    )
    (comp (ref "A267")
      (value "JP1E")
      (footprint "eagle-import:JP1")
      (libsource (lib "eagle-import") (part "JP1E"))
    )
    (comp (ref "A268")
      (value "JP1E")
      (footprint "eagle-import:JP1")
      (libsource (lib "eagle-import") (part "JP1E"))
    )
    (comp (ref "A269")
      (value "JP1E")
      (footprint "eagle-import:JP1")
      (libsource (lib "eagle-import") (part "JP1E"))
    )
    (comp (ref "A270")
      (value "JP1E")
      (footprint "eagle-import:JP1")
      (libsource (lib "eagle-import") (part "JP1E"))
    )
    (comp (ref "A271")
      (value "JP1E")
      (footprint "eagle-import:JP1")
      (libsource (lib "eagle-import") (part "JP1E"))
    )
    (comp (ref "A272")
      (value "JP1E")
      (footprint "eagle-import:JP1")
      (libsource (lib "eagle-import") (part "JP1E"))
    )
    (comp (ref "A273")
      (value "JP1E")
      (footprint "eagle-import:JP1")
      (libsource (lib "eagle-import") (part "JP1E"))
    )
    (comp (ref "A274")
      (value "JP1E")
      (footprint "eagle-import:JP1")
      (libsource (lib "eagle-import") (part "JP1E"))
    )
    (comp (ref "A275")
      (value "JP1E")
      (footprint "eagle-import:JP1")
      (libsource (lib "eagle-import") (part "JP1E"))
    )
    (comp (ref "A276")
      (value "JP1E")
      (footprint "eagle-import:JP1")
      (libsource (lib "eagle-import") (part "JP1E"))
    )
    (comp (ref "A277")
      (value "JP1E")
      (footprint "eagle-import:JP1")
      (libsource (lib "eagle-import") (part "JP1E"))
    )
    (comp (ref "A278")
      (value "JP1E")
      (footprint "eagle-import:JP1")
      (libsource (lib "eagle-import") (part "JP1E"))
    )
    (comp (ref "A279")
      (value "JP1E")
      (footprint "eagle-import:JP1")
      (libsource (lib "eagle-import") (part "JP1E"))
    )
    (comp (ref "A280")
      (value "JP1E")
      (footprint "eagle-import:JP1")
      (libsource (lib "eagle-import") (part "JP1E"))
    )
    (comp (ref "A281")
      (value "JP1E")
      (footprint "eagle-import:JP1")
      (libsource (lib "eagle-import") (part "JP1E"))
    )
    (comp (ref "A282")
      (value "JP1E")
      (footprint "eagle-import:JP1")
      (libsource (lib "eagle-import") (part "JP1E"))
    )
    (comp (ref "A283")
      (value "JP1E")
      (footprint "eagle-import:JP1")
      (libsource (lib "eagle-import") (part "JP1E"))
    )
    (comp (ref "A284")
      (value "JP1E")
      (footprint "eagle-import:JP1")
      (libsource (lib "eagle-import") (part "JP1E"))
    )
    (comp (ref "A285")
      (value "JP1E")
      (footprint "eagle-import:JP1")
      (libsource (lib "eagle-import") (part "JP1E"))
    )
    (comp (ref "A286")
      (value "JP1E")
      (footprint "eagle-import:JP1")
      (libsource (lib "eagle-import") (part "JP1E"))
    )
    (comp (ref "A287")
      (value "JP1E")
      (footprint "eagle-import:JP1")
      (libsource (lib "eagle-import") (part "JP1E"))
    )
    (comp (ref "A288")
      (value "JP1E")
      (footprint "eagle-import:JP1")
      (libsource (lib "eagle-import") (part "JP1E"))
    )
    (comp (ref "A289")
      (value "JP1E")
      (footprint "eagle-import:JP1")
      (libsource (lib "eagle-import") (part "JP1E"))
    )
    (comp (ref "A290")
      (value "JP1E")
      (footprint "eagle-import:JP1")
      (libsource (lib "eagle-import") (part "JP1E"))
    )
    (comp (ref "A291")
      (value "JP1E")
      (footprint "eagle-import:JP1")
      (libsource (lib "eagle-import") (part "JP1E"))
    )
    (comp (ref "A292")
      (value "JP1E")
      (footprint "eagle-import:JP1")
      (libsource (lib "eagle-import") (part "JP1E"))
    )
    (comp (ref "A293")
      (value "JP1E")
      (footprint "eagle-import:JP1")
      (libsource (lib "eagle-import") (part "JP1E"))
    )
    (comp (ref "A294")
      (value "JP1E")
      (footprint "eagle-import:JP1")
      (libsource (lib "eagle-import") (part "JP1E"))
    )
    (comp (ref "A295")
      (value "JP1E")
      (footprint "eagle-import:JP1")
      (libsource (lib "eagle-import") (part "JP1E"))
    )
    (comp (ref "A296")
      (value "JP1E")
      (footprint "eagle-import:JP1")
      (libsource (lib "eagle-import") (part "JP1E"))
    )
    (comp (ref "A297")
      (value "JP1E")
      (footprint "eagle-import:JP1")
      (libsource (lib "eagle-import") (part "JP1E"))
    )
    (comp (ref "A298")
      (value "JP1E")
      (footprint "eagle-import:JP1")
      (libsource (lib "eagle-import") (part "JP1E"))
    )
    (comp (ref "A299")
      (value "JP1E")
      (footprint "eagle-import:JP1")
      (libsource (lib "eagle-import") (part "JP1E"))
    )
    (comp (ref "A300")
      (value "JP1E")
      (footprint "eagle-import:JP1")
      (libsource (lib "eagle-import") (part "JP1E"))
    )
    (comp (ref "A301")
      (value "JP1E")
      (footprint "eagle-import:JP1")
      (libsource (lib "eagle-import") (part "JP1E"))
    )
    (comp (ref "A302")
      (value "JP1E")
      (footprint "eagle-import:JP1")
      (libsource (lib "eagle-import") (part "JP1E"))
    )
    (comp (ref "A303")
      (value "JP1E")
      (footprint "eagle-import:JP1")
      (libsource (lib "eagle-import") (part "JP1E"))
    )
    (comp (ref "A304")
      (value "JP1E")
      (footprint "eagle-import:JP1")
      (libsource (lib "eagle-import") (part "JP1E"))
    )
    (comp (ref "A305")
      (value "JP1E")
      (footprint "eagle-import:JP1")
      (libsource (lib "eagle-import") (part "JP1E"))
    )
    (comp (ref "A306")
      (value "JP1E")
      (footprint "eagle-import:JP1")
      (libsource (lib "eagle-import") (part "JP1E"))
    )
    (comp (ref "A307")
      (value "JP1E")
      (footprint "eagle-import:JP1")
      (libsource (lib "eagle-import") (part "JP1E"))
    )
    (comp (ref "A308")
      (value "JP1E")
      (footprint "eagle-import:JP1")
      (libsource (lib "eagle-import") (part "JP1E"))
    )
    (comp (ref "A309")
      (value "JP1E")
      (footprint "eagle-import:JP1")
      (libsource (lib "eagle-import") (part "JP1E"))
    )
    (comp (ref "A310")
      (value "JP1E")
      (footprint "eagle-import:JP1")
      (libsource (lib "eagle-import") (part "JP1E"))
    )
    (comp (ref "A311")
      (value "JP1E")
      (footprint "eagle-import:JP1")
      (libsource (lib "eagle-import") (part "JP1E"))
    )
    (comp (ref "A312")
      (value "JP1E")
      (footprint "eagle-import:JP1")
      (libsource (lib "eagle-import") (part "JP1E"))
    )
    (comp (ref "A313")
      (value "JP1E")
      (footprint "eagle-import:JP1")
      (libsource (lib "eagle-import") (part "JP1E"))
    )
    (comp (ref "A314")
      (value "JP1E")
      (footprint "eagle-import:JP1")
      (libsource (lib "eagle-import") (part "JP1E"))
    )
    (comp (ref "A315")
      (value "JP1E")
      (footprint "eagle-import:JP1")
      (libsource (lib "eagle-import") (part "JP1E"))
    )
    (comp (ref "A316")
      (value "JP1E")
      (footprint "eagle-import:JP1")
      (libsource (lib "eagle-import") (part "JP1E"))
    )
    (comp (ref "A317")
      (value "JP1E")
      (footprint "eagle-import:JP1")
      (libsource (lib "eagle-import") (part "JP1E"))
    )
    (comp (ref "A318")
      (value "JP1E")
      (footprint "eagle-import:JP1")
      (libsource (lib "eagle-import") (part "JP1E"))
    )
    (comp (ref "A319")
      (value "JP1E")
      (footprint "eagle-import:JP1")
      (libsource (lib "eagle-import") (part "JP1E"))
    )
    (comp (ref "A320")
      (value "JP1E")
      (footprint "eagle-import:JP1")
      (libsource (lib "eagle-import") (part "JP1E"))
    )
    (comp (ref "A321")
      (value "JP1E")
      (footprint "eagle-import:JP1")
      (libsource (lib "eagle-import") (part "JP1E"))
    )
    (comp (ref "A322")
      (value "JP1E")
      (footprint "eagle-import:JP1")
      (libsource (lib "eagle-import") (part "JP1E"))
    )
    (comp (ref "A323")
      (value "JP1E")
      (footprint "eagle-import:JP1")
      (libsource (lib "eagle-import") (part "JP1E"))
    )
    (comp (ref "A324")
      (value "JP1E")
      (footprint "eagle-import:JP1")
      (libsource (lib "eagle-import") (part "JP1E"))
    )
    (comp (ref "A325")
      (value "JP1E")
      (footprint "eagle-import:JP1")
      (libsource (lib "eagle-import") (part "JP1E"))
    )
    (comp (ref "A326")
      (value "JP1E")
      (footprint "eagle-import:JP1")
      (libsource (lib "eagle-import") (part "JP1E"))
    )
    (comp (ref "A327")
      (value "JP1E")
      (footprint "eagle-import:JP1")
      (libsource (lib "eagle-import") (part "JP1E"))
    )
    (comp (ref "A328")
      (value "JP1E")
      (footprint "eagle-import:JP1")
      (libsource (lib "eagle-import") (part "JP1E"))
    )
    (comp (ref "A329")
      (value "JP1E")
      (footprint "eagle-import:JP1")
      (libsource (lib "eagle-import") (part "JP1E"))
    )
    (comp (ref "A330")
      (value "JP1E")
      (footprint "eagle-import:JP1")
      (libsource (lib "eagle-import") (part "JP1E"))
    )
    (comp (ref "A331")
      (value "JP1E")
      (footprint "eagle-import:JP1")
      (libsource (lib "eagle-import") (part "JP1E"))
    )
    (comp (ref "A332")
      (value "JP1E")
      (footprint "eagle-import:JP1")
      (libsource (lib "eagle-import") (part "JP1E"))
    )
    (comp (ref "A333")
      (value "JP1E")
      (footprint "eagle-import:JP1")
      (libsource (lib "eagle-import") (part "JP1E"))
    )
    (comp (ref "A334")
      (value "JP1E")
      (footprint "eagle-import:JP1")
      (libsource (lib "eagle-import") (part "JP1E"))
    )
    (comp (ref "A335")
      (value "JP1E")
      (footprint "eagle-import:JP1")
      (libsource (lib "eagle-import") (part "JP1E"))
    )
    (comp (ref "A336")
      (value "JP1E")
      (footprint "eagle-import:JP1")
      (libsource (lib "eagle-import") (part "JP1E"))
    )
    (comp (ref "A337")
      (value "JP1E")
      (footprint "eagle-import:JP1")
      (libsource (lib "eagle-import") (part "JP1E"))
    )
    (comp (ref "A338")
      (value "JP1E")
      (footprint "eagle-import:JP1")
      (libsource (lib "eagle-import") (part "JP1E"))
    )
    (comp (ref "A339")
      (value "JP1E")
      (footprint "eagle-import:JP1")
      (libsource (lib "eagle-import") (part "JP1E"))
    )
    (comp (ref "A340")
      (value "JP1E")
      (footprint "eagle-import:JP1")
      (libsource (lib "eagle-import") (part "JP1E"))
    )
    (comp (ref "A341")
      (value "JP1E")
      (footprint "eagle-import:JP1")
      (libsource (lib "eagle-import") (part "JP1E"))
    )
    (comp (ref "A342")
      (value "JP1E")
      (footprint "eagle-import:JP1")
      (libsource (lib "eagle-import") (part "JP1E"))
    )
    (comp (ref "A343")
      (value "JP1E")
      (footprint "eagle-import:JP1")
      (libsource (lib "eagle-import") (part "JP1E"))
    )
    (comp (ref "A344")
      (value "JP1E")
      (footprint "eagle-import:JP1")
      (libsource (lib "eagle-import") (part "JP1E"))
    )
    (comp (ref "A345")
      (value "JP1E")
      (footprint "eagle-import:JP1")
      (libsource (lib "eagle-import") (part "JP1E"))
    )
    (comp (ref "A346")
      (value "JP1E")
      (footprint "eagle-import:JP1")
      (libsource (lib "eagle-import") (part "JP1E"))
    )
    (comp (ref "A347")
      (value "JP1E")
      (footprint "eagle-import:JP1")
      (libsource (lib "eagle-import") (part "JP1E"))
    )
    (comp (ref "A348")
      (value "JP1E")
      (footprint "eagle-import:JP1")
      (libsource (lib "eagle-import") (part "JP1E"))
    )
    (comp (ref "A349")
      (value "JP1E")
      (footprint "eagle-import:JP1")
      (libsource (lib "eagle-import") (part "JP1E"))
    )
    (comp (ref "A350")
      (value "JP1E")
      (footprint "eagle-import:JP1")
      (libsource (lib "eagle-import") (part "JP1E"))
    )
    (comp (ref "A351")
      (value "JP1E")
      (footprint "eagle-import:JP1")
      (libsource (lib "eagle-import") (part "JP1E"))
    )
    (comp (ref "A352")
      (value "JP1E")
      (footprint "eagle-import:JP1")
      (libsource (lib "eagle-import") (part "JP1E"))
    )
    (comp (ref "A353")
      (value "JP1E")
      (footprint "eagle-import:JP1")
      (libsource (lib "eagle-import") (part "JP1E"))
    )
    (comp (ref "A354")
      (value "JP1E")
      (footprint "eagle-import:JP1")
      (libsource (lib "eagle-import") (part "JP1E"))
    )
    (comp (ref "A355")
      (value "JP1E")
      (footprint "eagle-import:JP1")
      (libsource (lib "eagle-import") (part "JP1E"))
    )
    (comp (ref "A356")
      (value "JP1E")
      (footprint "eagle-import:JP1")
      (libsource (lib "eagle-import") (part "JP1E"))
    )
    (comp (ref "A357")
      (value "JP1E")
      (footprint "eagle-import:JP1")
      (libsource (lib "eagle-import") (part "JP1E"))
    )
    (comp (ref "A358")
      (value "JP1E")
      (footprint "eagle-import:JP1")
      (libsource (lib "eagle-import") (part "JP1E"))
    )
    (comp (ref "A359")
      (value "JP1E")
      (footprint "eagle-import:JP1")
      (libsource (lib "eagle-import") (part "JP1E"))
    )
    (comp (ref "A360")
      (value "JP1E")
      (footprint "eagle-import:JP1")
      (libsource (lib "eagle-import") (part "JP1E"))
    )
    (comp (ref "A361")
      (value "JP1E")
      (footprint "eagle-import:JP1")
      (libsource (lib "eagle-import") (part "JP1E"))
    )
    (comp (ref "A362")
      (value "JP1E")
      (footprint "eagle-import:JP1")
      (libsource (lib "eagle-import") (part "JP1E"))
    )
    (comp (ref "A363")
      (value "JP1E")
      (footprint "eagle-import:JP1")
      (libsource (lib "eagle-import") (part "JP1E"))
    )
    (comp (ref "A364")
      (value "JP1E")
      (footprint "eagle-import:JP1")
      (libsource (lib "eagle-import") (part "JP1E"))
    )
    (comp (ref "A365")
      (value "JP1E")
      (footprint "eagle-import:JP1")
      (libsource (lib "eagle-import") (part "JP1E"))
    )
    (comp (ref "A366")
      (value "JP1E")
      (footprint "eagle-import:JP1")
      (libsource (lib "eagle-import") (part "JP1E"))
    )
    (comp (ref "A367")
      (value "JP1E")
      (footprint "eagle-import:JP1")
      (libsource (lib "eagle-import") (part "JP1E"))
    )
    (comp (ref "A368")
      (value "JP1E")
      (footprint "eagle-import:JP1")
      (libsource (lib "eagle-import") (part "JP1E"))
    )
    (comp (ref "A369")
      (value "JP1E")
      (footprint "eagle-import:JP1")
      (libsource (lib "eagle-import") (part "JP1E"))
    )
    (comp (ref "A370")
      (value "JP1E")
      (footprint "eagle-import:JP1")
      (libsource (lib "eagle-import") (part "JP1E"))
    )
    (comp (ref "A371")
      (value "JP1E")
      (footprint "eagle-import:JP1")
      (libsource (lib "eagle-import") (part "JP1E"))
    )
    (comp (ref "A372")
      (value "JP1E")
      (footprint "eagle-import:JP1")
      (libsource (lib "eagle-import") (part "JP1E"))
    )
    (comp (ref "A373")
      (value "JP1E")
      (footprint "eagle-import:JP1")
      (libsource (lib "eagle-import") (part "JP1E"))
    )
    (comp (ref "A374")
      (value "JP1E")
      (footprint "eagle-import:JP1")
      (libsource (lib "eagle-import") (part "JP1E"))
    )
    (comp (ref "A375")
      (value "JP1E")
      (footprint "eagle-import:JP1")
      (libsource (lib "eagle-import") (part "JP1E"))
    )
    (comp (ref "A376")
      (value "JP1E")
      (footprint "eagle-import:JP1")
      (libsource (lib "eagle-import") (part "JP1E"))
    )
    (comp (ref "A377")
      (value "JP1E")
      (footprint "eagle-import:JP1")
      (libsource (lib "eagle-import") (part "JP1E"))
    )
    (comp (ref "A378")
      (value "JP1E")
      (footprint "eagle-import:JP1")
      (libsource (lib "eagle-import") (part "JP1E"))
    )
    (comp (ref "A379")
      (value "JP1E")
      (footprint "eagle-import:JP1")
      (libsource (lib "eagle-import") (part "JP1E"))
    )
    (comp (ref "A380")
      (value "JP1E")
      (footprint "eagle-import:JP1")
      (libsource (lib "eagle-import") (part "JP1E"))
    )
    (comp (ref "A381")
      (value "JP1E")
      (footprint "eagle-import:JP1")
      (libsource (lib "eagle-import") (part "JP1E"))
    )
    (comp (ref "A382")
      (value "JP1E")
      (footprint "eagle-import:JP1")
      (libsource (lib "eagle-import") (part "JP1E"))
    )
    (comp (ref "A383")
      (value "JP1E")
      (footprint "eagle-import:JP1")
      (libsource (lib "eagle-import") (part "JP1E"))
    )
    (comp (ref "A384")
      (value "JP1E")
      (footprint "eagle-import:JP1")
      (libsource (lib "eagle-import") (part "JP1E"))
    )
    (comp (ref "A385")
      (value "JP1E")
      (footprint "eagle-import:JP1")
      (libsource (lib "eagle-import") (part "JP1E"))
    )
    (comp (ref "A386")
      (value "JP1E")
      (footprint "eagle-import:JP1")
      (libsource (lib "eagle-import") (part "JP1E"))
    )
    (comp (ref "A387")
      (value "JP1E")
      (footprint "eagle-import:JP1")
      (libsource (lib "eagle-import") (part "JP1E"))
    )
    (comp (ref "A388")
      (value "JP1E")
      (footprint "eagle-import:JP1")
      (libsource (lib "eagle-import") (part "JP1E"))
    )
    (comp (ref "A389")
      (value "JP1E")
      (footprint "eagle-import:JP1")
      (libsource (lib "eagle-import") (part "JP1E"))
    )
    (comp (ref "A390")
      (value "JP1E")
      (footprint "eagle-import:JP1")
      (libsource (lib "eagle-import") (part "JP1E"))
    )
    (comp (ref "A391")
      (value "JP1E")
      (footprint "eagle-import:JP1")
      (libsource (lib "eagle-import") (part "JP1E"))
    )
    (comp (ref "A392")
      (value "JP1E")
      (footprint "eagle-import:JP1")
      (libsource (lib "eagle-import") (part "JP1E"))
    )
    (comp (ref "A393")
      (value "JP1E")
      (footprint "eagle-import:JP1")
      (libsource (lib "eagle-import") (part "JP1E"))
    )
    (comp (ref "A394")
      (value "JP1E")
      (footprint "eagle-import:JP1")
      (libsource (lib "eagle-import") (part "JP1E"))
    )
    (comp (ref "A395")
      (value "JP1E")
      (footprint "eagle-import:JP1")
      (libsource (lib "eagle-import") (part "JP1E"))
    )
    (comp (ref "A396")
      (value "JP1E")
      (footprint "eagle-import:JP1")
      (libsource (lib "eagle-import") (part "JP1E"))
    )
    (comp (ref "A397")
      (value "JP1E")
      (footprint "eagle-import:JP1")
      (libsource (lib "eagle-import") (part "JP1E"))
    )
    (comp (ref "A398")
      (value "JP1E")
      (footprint "eagle-import:JP1")
      (libsource (lib "eagle-import") (part "JP1E"))
    )
    (comp (ref "A399")
      (value "JP1E")
      (footprint "eagle-import:JP1")
      (libsource (lib "eagle-import") (part "JP1E"))
    )
    (comp (ref "A400")
      (value "JP1E")
      (footprint "eagle-import:JP1")
      (libsource (lib "eagle-import") (part "JP1E"))
    )
    (comp (ref "A401")
      (value "JP1E")
      (footprint "eagle-import:JP1")
      (libsource (lib "eagle-import") (part "JP1E"))
    )
    (comp (ref "A402")
      (value "JP1E")
      (footprint "eagle-import:JP1")
      (libsource (lib "eagle-import") (part "JP1E"))
    )
    (comp (ref "A403")
      (value "JP1E")
      (footprint "eagle-import:JP1")
      (libsource (lib "eagle-import") (part "JP1E"))
    )
    (comp (ref "A404")
      (value "JP1E")
      (footprint "eagle-import:JP1")
      (libsource (lib "eagle-import") (part "JP1E"))
    )
    (comp (ref "A405")
      (value "JP1E")
      (footprint "eagle-import:JP1")
      (libsource (lib "eagle-import") (part "JP1E"))
    )
    (comp (ref "A406")
      (value "JP1E")
      (footprint "eagle-import:JP1")
      (libsource (lib "eagle-import") (part "JP1E"))
    )
    (comp (ref "A407")
      (value "JP1E")
      (footprint "eagle-import:JP1")
      (libsource (lib "eagle-import") (part "JP1E"))
    )
    (comp (ref "A408")
      (value "JP1E")
      (footprint "eagle-import:JP1")
      (libsource (lib "eagle-import") (part "JP1E"))
    )
    (comp (ref "A409")
      (value "JP1E")
      (footprint "eagle-import:JP1")
      (libsource (lib "eagle-import") (part "JP1E"))
    )
    (comp (ref "A410")
      (value "JP1E")
      (footprint "eagle-import:JP1")
      (libsource (lib "eagle-import") (part "JP1E"))
    )
    (comp (ref "A411")
      (value "JP1E")
      (footprint "eagle-import:JP1")
      (libsource (lib "eagle-import") (part "JP1E"))
    )
    (comp (ref "A412")
      (value "JP1E")
      (footprint "eagle-import:JP1")
      (libsource (lib "eagle-import") (part "JP1E"))
    )
    (comp (ref "A413")
      (value "JP1E")
      (footprint "eagle-import:JP1")
      (libsource (lib "eagle-import") (part "JP1E"))
    )
    (comp (ref "A414")
      (value "JP1E")
      (footprint "eagle-import:JP1")
      (libsource (lib "eagle-import") (part "JP1E"))
    )
    (comp (ref "A415")
      (value "JP1E")
      (footprint "eagle-import:JP1")
      (libsource (lib "eagle-import") (part "JP1E"))
    )
    (comp (ref "A416")
      (value "JP1E")
      (footprint "eagle-import:JP1")
      (libsource (lib "eagle-import") (part "JP1E"))
    )
    (comp (ref "A417")
      (value "JP1E")
      (footprint "eagle-import:JP1")
      (libsource (lib "eagle-import") (part "JP1E"))
    )
    (comp (ref "A418")
      (value "JP1E")
      (footprint "eagle-import:JP1")
      (libsource (lib "eagle-import") (part "JP1E"))
    )
    (comp (ref "A419")
      (value "JP1E")
      (footprint "eagle-import:JP1")
      (libsource (lib "eagle-import") (part "JP1E"))
    )
    (comp (ref "A420")
      (value "JP1E")
      (footprint "eagle-import:JP1")
      (libsource (lib "eagle-import") (part "JP1E"))
    )
    (comp (ref "A421")
      (value "JP1E")
      (footprint "eagle-import:JP1")
      (libsource (lib "eagle-import") (part "JP1E"))
    )
    (comp (ref "A422")
      (value "JP1E")
      (footprint "eagle-import:JP1")
      (libsource (lib "eagle-import") (part "JP1E"))
    )
    (comp (ref "A423")
      (value "JP1E")
      (footprint "eagle-import:JP1")
      (libsource (lib "eagle-import") (part "JP1E"))
    )
    (comp (ref "A424")
      (value "JP1E")
      (footprint "eagle-import:JP1")
      (libsource (lib "eagle-import") (part "JP1E"))
    )
    (comp (ref "A425")
      (value "JP1E")
      (footprint "eagle-import:JP1")
      (libsource (lib "eagle-import") (part "JP1E"))
    )
    (comp (ref "A426")
      (value "JP1E")
      (footprint "eagle-import:JP1")
      (libsource (lib "eagle-import") (part "JP1E"))
    )
    (comp (ref "A427")
      (value "JP1E")
      (footprint "eagle-import:JP1")
      (libsource (lib "eagle-import") (part "JP1E"))
    )
    (comp (ref "A428")
      (value "JP1E")
      (footprint "eagle-import:JP1")
      (libsource (lib "eagle-import") (part "JP1E"))
    )
    (comp (ref "A429")
      (value "JP1E")
      (footprint "eagle-import:JP1")
      (libsource (lib "eagle-import") (part "JP1E"))
    )
    (comp (ref "A430")
      (value "JP1E")
      (footprint "eagle-import:JP1")
      (libsource (lib "eagle-import") (part "JP1E"))
    )
    (comp (ref "A431")
      (value "JP1E")
      (footprint "eagle-import:JP1")
      (libsource (lib "eagle-import") (part "JP1E"))
    )
    (comp (ref "A432")
      (value "JP1E")
      (footprint "eagle-import:JP1")
      (libsource (lib "eagle-import") (part "JP1E"))
    )
    (comp (ref "A433")
      (value "JP1E")
      (footprint "eagle-import:JP1")
      (libsource (lib "eagle-import") (part "JP1E"))
    )
    (comp (ref "A434")
      (value "JP1E")
      (footprint "eagle-import:JP1")
      (libsource (lib "eagle-import") (part "JP1E"))
    )
    (comp (ref "A435")
      (value "JP1E")
      (footprint "eagle-import:JP1")
      (libsource (lib "eagle-import") (part "JP1E"))
    )
    (comp (ref "A436")
      (value "JP1E")
      (footprint "eagle-import:JP1")
      (libsource (lib "eagle-import") (part "JP1E"))
    )
    (comp (ref "A437")
      (value "JP1E")
      (footprint "eagle-import:JP1")
      (libsource (lib "eagle-import") (part "JP1E"))
    )
    (comp (ref "A438")
      (value "JP1E")
      (footprint "eagle-import:JP1")
      (libsource (lib "eagle-import") (part "JP1E"))
    )
    (comp (ref "A439")
      (value "JP1E")
      (footprint "eagle-import:JP1")
      (libsource (lib "eagle-import") (part "JP1E"))
    )
    (comp (ref "A440")
      (value "JP1E")
      (footprint "eagle-import:JP1")
      (libsource (lib "eagle-import") (part "JP1E"))
    )
    (comp (ref "A441")
      (value "JP1E")
      (footprint "eagle-import:JP1")
      (libsource (lib "eagle-import") (part "JP1E"))
    )
    (comp (ref "A442")
      (value "JP1E")
      (footprint "eagle-import:JP1")
      (libsource (lib "eagle-import") (part "JP1E"))
    )
    (comp (ref "A443")
      (value "JP1E")
      (footprint "eagle-import:JP1")
      (libsource (lib "eagle-import") (part "JP1E"))
    )
    (comp (ref "A444")
      (value "JP1E")
      (footprint "eagle-import:JP1")
      (libsource (lib "eagle-import") (part "JP1E"))
    )
    (comp (ref "A445")
      (value "JP1E")
      (footprint "eagle-import:JP1")
      (libsource (lib "eagle-import") (part "JP1E"))
    )
    (comp (ref "A446")
      (value "JP1E")
      (footprint "eagle-import:JP1")
      (libsource (lib "eagle-import") (part "JP1E"))
    )
    (comp (ref "A447")
      (value "JP1E")
      (footprint "eagle-import:JP1")
      (libsource (lib "eagle-import") (part "JP1E"))
    )
    (comp (ref "A448")
      (value "JP1E")
      (footprint "eagle-import:JP1")
      (libsource (lib "eagle-import") (part "JP1E"))
    )
    (comp (ref "GND1")
      (value "JP1E")
      (footprint "eagle-import:JP1")
      (libsource (lib "eagle-import") (part "JP1E"))
    )
    (comp (ref "GND2")
      (value "JP1E")
      (footprint "eagle-import:JP1")
      (libsource (lib "eagle-import") (part "JP1E"))
    )
    (comp (ref "GND3")
      (value "JP1E")
      (footprint "eagle-import:JP1")
      (libsource (lib "eagle-import") (part "JP1E"))
    )
    (comp (ref "GND4")
      (value "JP1E")
      (footprint "eagle-import:JP1")
      (libsource (lib "eagle-import") (part "JP1E"))
    )
    (comp (ref "GND5")
      (value "JP1E")
      (footprint "eagle-import:JP1")
      (libsource (lib "eagle-import") (part "JP1E"))
    )
    (comp (ref "GND6")
      (value "JP1E")
      (footprint "eagle-import:JP1")
      (libsource (lib "eagle-import") (part "JP1E"))
    )
    (comp (ref "GND7")
      (value "JP1E")
      (footprint "eagle-import:JP1")
      (libsource (lib "eagle-import") (part "JP1E"))
    )
    (comp (ref "GND8")
      (value "JP1E")
      (footprint "eagle-import:JP1")
      (libsource (lib "eagle-import") (part "JP1E"))
    )
    (comp (ref "GND9")
      (value "JP1E")
      (footprint "eagle-import:JP1")
      (libsource (lib "eagle-import") (part "JP1E"))
    )
    (comp (ref "GND10")
      (value "JP1E")
      (footprint "eagle-import:JP1")
      (libsource (lib "eagle-import") (part "JP1E"))
    )
    (comp (ref "GND11")
      (value "JP1E")
      (footprint "eagle-import:JP1")
      (libsource (lib "eagle-import") (part "JP1E"))
    )
    (comp (ref "GND12")
      (value "JP1E")
      (footprint "eagle-import:JP1")
      (libsource (lib "eagle-import") (part "JP1E"))
    )
    (comp (ref "GND13")
      (value "JP1E")
      (footprint "eagle-import:JP1")
      (libsource (lib "eagle-import") (part "JP1E"))
    )
    (comp (ref "GND14")
      (value "JP1E")
      (footprint "eagle-import:JP1")
      (libsource (lib "eagle-import") (part "JP1E"))
    )
    (comp (ref "GND15")
      (value "JP1E")
      (footprint "eagle-import:JP1")
      (libsource (lib "eagle-import") (part "JP1E"))
    )
    (comp (ref "GND16")
      (value "JP1E")
      (footprint "eagle-import:JP1")
      (libsource (lib "eagle-import") (part "JP1E"))
    )
    (comp (ref "GND17")
      (value "JP1E")
      (footprint "eagle-import:JP1")
      (libsource (lib "eagle-import") (part "JP1E"))
    )
    (comp (ref "GND18")
      (value "JP1E")
      (footprint "eagle-import:JP1")
      (libsource (lib "eagle-import") (part "JP1E"))
    )
    (comp (ref "GND19")
      (value "JP1E")
      (footprint "eagle-import:JP1")
      (libsource (lib "eagle-import") (part "JP1E"))
    )
    (comp (ref "GND20")
      (value "JP1E")
      (footprint "eagle-import:JP1")
      (libsource (lib "eagle-import") (part "JP1E"))
    )
    (comp (ref "GND21")
      (value "JP1E")
      (footprint "eagle-import:JP1")
      (libsource (lib "eagle-import") (part "JP1E"))
    )
    (comp (ref "GND22")
      (value "JP1E")
      (footprint "eagle-import:JP1")
      (libsource (lib "eagle-import") (part "JP1E"))
    )
    (comp (ref "GND23")
      (value "JP1E")
      (footprint "eagle-import:JP1")
      (libsource (lib "eagle-import") (part "JP1E"))
    )
    (comp (ref "GND24")
      (value "JP1E")
      (footprint "eagle-import:JP1")
      (libsource (lib "eagle-import") (part "JP1E"))
    )
    (comp (ref "GND25")
      (value "JP1E")
      (footprint "eagle-import:JP1")
      (libsource (lib "eagle-import") (part "JP1E"))
    )
    (comp (ref "GND26")
      (value "JP1E")
      (footprint "eagle-import:JP1")
      (libsource (lib "eagle-import") (part "JP1E"))
    )
    (comp (ref "GND27")
      (value "JP1E")
      (footprint "eagle-import:JP1")
      (libsource (lib "eagle-import") (part "JP1E"))
    )
    (comp (ref "GND28")
      (value "JP1E")
      (footprint "eagle-import:JP1")
      (libsource (lib "eagle-import") (part "JP1E"))
    )
    (comp (ref "GND29")
      (value "JP1E")
      (footprint "eagle-import:JP1")
      (libsource (lib "eagle-import") (part "JP1E"))
    )
    (comp (ref "GND30")
      (value "JP1E")
      (footprint "eagle-import:JP1")
      (libsource (lib "eagle-import") (part "JP1E"))
    )
    (comp (ref "GND31")
      (value "JP1E")
      (footprint "eagle-import:JP1")
      (libsource (lib "eagle-import") (part "JP1E"))
    )
    (comp (ref "GND32")
      (value "JP1E")
      (footprint "eagle-import:JP1")
      (libsource (lib "eagle-import") (part "JP1E"))
    )
    (comp (ref "GND33")
      (value "JP1E")
      (footprint "eagle-import:JP1")
      (libsource (lib "eagle-import") (part "JP1E"))
    )
    (comp (ref "GND34")
      (value "JP1E")
      (footprint "eagle-import:JP1")
      (libsource (lib "eagle-import") (part "JP1E"))
    )
    (comp (ref "GND35")
      (value "JP1E")
      (footprint "eagle-import:JP1")
      (libsource (lib "eagle-import") (part "JP1E"))
    )
    (comp (ref "GND36")
      (value "JP1E")
      (footprint "eagle-import:JP1")
      (libsource (lib "eagle-import") (part "JP1E"))
    )
    (comp (ref "GND37")
      (value "JP1E")
      (footprint "eagle-import:JP1")
      (libsource (lib "eagle-import") (part "JP1E"))
    )
    (comp (ref "GND38")
      (value "JP1E")
      (footprint "eagle-import:JP1")
      (libsource (lib "eagle-import") (part "JP1E"))
    )
    (comp (ref "GND39")
      (value "JP1E")
      (footprint "eagle-import:JP1")
      (libsource (lib "eagle-import") (part "JP1E"))
    )
    (comp (ref "GND40")
      (value "JP1E")
      (footprint "eagle-import:JP1")
      (libsource (lib "eagle-import") (part "JP1E"))
    )
    (comp (ref "GND41")
      (value "JP1E")
      (footprint "eagle-import:JP1")
      (libsource (lib "eagle-import") (part "JP1E"))
    )
    (comp (ref "GND42")
      (value "JP1E")
      (footprint "eagle-import:JP1")
      (libsource (lib "eagle-import") (part "JP1E"))
    )
    (comp (ref "GND43")
      (value "JP1E")
      (footprint "eagle-import:JP1")
      (libsource (lib "eagle-import") (part "JP1E"))
    )
    (comp (ref "GND44")
      (value "JP1E")
      (footprint "eagle-import:JP1")
      (libsource (lib "eagle-import") (part "JP1E"))
    )
    (comp (ref "IC9")
      (value "DIL16")
      (footprint "eagle-import:DIL16")
      (libsource (lib "eagle-import") (part "DIL16"))
    )
    (comp (ref "IC10")
      (value "DIL16")
      (footprint "eagle-import:DIL16")
      (libsource (lib "eagle-import") (part "DIL16"))
    )
    (comp (ref "IC11")
      (value "DIL16")
      (footprint "eagle-import:DIL16")
      (libsource (lib "eagle-import") (part "DIL16"))
    )
    (comp (ref "IC12")
      (value "DIL16")
      (footprint "eagle-import:DIL16")
      (libsource (lib "eagle-import") (part "DIL16"))
    )
    (comp (ref "IC13")
      (value "DIL16")
      (footprint "eagle-import:DIL16")
      (libsource (lib "eagle-import") (part "DIL16"))
    )
    (comp (ref "IC14")
      (value "DIL16")
      (footprint "eagle-import:DIL16")
      (libsource (lib "eagle-import") (part "DIL16"))
    )
    (comp (ref "IC15")
      (value "DIL16")
      (footprint "eagle-import:DIL16")
      (libsource (lib "eagle-import") (part "DIL16"))
    )
    (comp (ref "IC16")
      (value "DIL16")
      (footprint "eagle-import:DIL16")
      (libsource (lib "eagle-import") (part "DIL16"))
    )
    (comp (ref "IC17")
      (value "DIL16")
      (footprint "eagle-import:DIL16")
      (libsource (lib "eagle-import") (part "DIL16"))
    )
    (comp (ref "IC18")
      (value "DIL16")
      (footprint "eagle-import:DIL16")
      (libsource (lib "eagle-import") (part "DIL16"))
    )
    (comp (ref "IC19")
      (value "DIL16")
      (footprint "eagle-import:DIL16")
      (libsource (lib "eagle-import") (part "DIL16"))
    )
    (comp (ref "IC20")
      (value "DIL16")
      (footprint "eagle-import:DIL16")
      (libsource (lib "eagle-import") (part "DIL16"))
    )
    (comp (ref "IC21")
      (value "DIL16")
      (footprint "eagle-import:DIL16")
      (libsource (lib "eagle-import") (part "DIL16"))
    )
    (comp (ref "IC22")
      (value "DIL16")
      (footprint "eagle-import:DIL16")
      (libsource (lib "eagle-import") (part "DIL16"))
    )
    (comp (ref "IC23")
      (value "DIL16")
      (footprint "eagle-import:DIL16")
      (libsource (lib "eagle-import") (part "DIL16"))
    )
    (comp (ref "IC24")
      (value "DIL16")
      (footprint "eagle-import:DIL16")
      (libsource (lib "eagle-import") (part "DIL16"))
    )
    (comp (ref "IC25")
      (value "DIL16")
      (footprint "eagle-import:DIL16")
      (libsource (lib "eagle-import") (part "DIL16"))
    )
    (comp (ref "IC26")
      (value "DIL16")
      (footprint "eagle-import:DIL16")
      (libsource (lib "eagle-import") (part "DIL16"))
    )
    (comp (ref "IC27")
      (value "DIL16")
      (footprint "eagle-import:DIL16")
      (libsource (lib "eagle-import") (part "DIL16"))
    )
    (comp (ref "IC28")
      (value "DIL16")
      (footprint "eagle-import:DIL16")
      (libsource (lib "eagle-import") (part "DIL16"))
    )
    (comp (ref "IC29")
      (value "DIL16")
      (footprint "eagle-import:DIL16")
      (libsource (lib "eagle-import") (part "DIL16"))
    )
    (comp (ref "IC30")
      (value "DIL16")
      (footprint "eagle-import:DIL16")
      (libsource (lib "eagle-import") (part "DIL16"))
    )
    (comp (ref "IC31")
      (value "DIL16")
      (footprint "eagle-import:DIL16")
      (libsource (lib "eagle-import") (part "DIL16"))
    )
    (comp (ref "IC32")
      (value "DIL16")
      (footprint "eagle-import:DIL16")
      (libsource (lib "eagle-import") (part "DIL16"))
    )
    (comp (ref "IC33")
      (value "DIL16")
      (footprint "eagle-import:DIL16")
      (libsource (lib "eagle-import") (part "DIL16"))
    )
    (comp (ref "IC34")
      (value "DIL16")
      (footprint "eagle-import:DIL16")
      (libsource (lib "eagle-import") (part "DIL16"))
    )
    (comp (ref "IC35")
      (value "DIL16")
      (footprint "eagle-import:DIL16")
      (libsource (lib "eagle-import") (part "DIL16"))
    )
    (comp (ref "IC36")
      (value "DIL16")
      (footprint "eagle-import:DIL16")
      (libsource (lib "eagle-import") (part "DIL16"))
    )
    (comp (ref "VCC1")
      (value "JP1E")
      (footprint "eagle-import:JP1")
      (libsource (lib "eagle-import") (part "JP1E"))
    )
    (comp (ref "VCC2")
      (value "JP1E")
      (footprint "eagle-import:JP1")
      (libsource (lib "eagle-import") (part "JP1E"))
    )
    (comp (ref "VCC3")
      (value "JP1E")
      (footprint "eagle-import:JP1")
      (libsource (lib "eagle-import") (part "JP1E"))
    )
    (comp (ref "VCC4")
      (value "JP1E")
      (footprint "eagle-import:JP1")
      (libsource (lib "eagle-import") (part "JP1E"))
    )
    (comp (ref "VCC5")
      (value "JP1E")
      (footprint "eagle-import:JP1")
      (libsource (lib "eagle-import") (part "JP1E"))
    )
    (comp (ref "VCC6")
      (value "JP1E")
      (footprint "eagle-import:JP1")
      (libsource (lib "eagle-import") (part "JP1E"))
    )
    (comp (ref "VCC7")
      (value "JP1E")
      (footprint "eagle-import:JP1")
      (libsource (lib "eagle-import") (part "JP1E"))
    )
    (comp (ref "VCC8")
      (value "JP1E")
      (footprint "eagle-import:JP1")
      (libsource (lib "eagle-import") (part "JP1E"))
    )
    (comp (ref "VCC9")
      (value "JP1E")
      (footprint "eagle-import:JP1")
      (libsource (lib "eagle-import") (part "JP1E"))
    )
    (comp (ref "VCC10")
      (value "JP1E")
      (footprint "eagle-import:JP1")
      (libsource (lib "eagle-import") (part "JP1E"))
    )
    (comp (ref "VCC11")
      (value "JP1E")
      (footprint "eagle-import:JP1")
      (libsource (lib "eagle-import") (part "JP1E"))
    )
    (comp (ref "VCC12")
      (value "JP1E")
      (footprint "eagle-import:JP1")
      (libsource (lib "eagle-import") (part "JP1E"))
    )
    (comp (ref "VCC13")
      (value "JP1E")
      (footprint "eagle-import:JP1")
      (libsource (lib "eagle-import") (part "JP1E"))
    )
    (comp (ref "VCC14")
      (value "JP1E")
      (footprint "eagle-import:JP1")
      (libsource (lib "eagle-import") (part "JP1E"))
    )
    (comp (ref "VCC15")
      (value "JP1E")
      (footprint "eagle-import:JP1")
      (libsource (lib "eagle-import") (part "JP1E"))
    )
    (comp (ref "VCC16")
      (value "JP1E")
      (footprint "eagle-import:JP1")
      (libsource (lib "eagle-import") (part "JP1E"))
    )
    (comp (ref "VCC17")
      (value "JP1E")
      (footprint "eagle-import:JP1")
      (libsource (lib "eagle-import") (part "JP1E"))
    )
    (comp (ref "VCC18")
      (value "JP1E")
      (footprint "eagle-import:JP1")
      (libsource (lib "eagle-import") (part "JP1E"))
    )
    (comp (ref "VCC19")
      (value "JP1E")
      (footprint "eagle-import:JP1")
      (libsource (lib "eagle-import") (part "JP1E"))
    )
    (comp (ref "VCC20")
      (value "JP1E")
      (footprint "eagle-import:JP1")
      (libsource (lib "eagle-import") (part "JP1E"))
    )
    (comp (ref "VCC21")
      (value "JP1E")
      (footprint "eagle-import:JP1")
      (libsource (lib "eagle-import") (part "JP1E"))
    )
    (comp (ref "VCC22")
      (value "JP1E")
      (footprint "eagle-import:JP1")
      (libsource (lib "eagle-import") (part "JP1E"))
    )
    (comp (ref "VCC23")
      (value "JP1E")
      (footprint "eagle-import:JP1")
      (libsource (lib "eagle-import") (part "JP1E"))
    )
    (comp (ref "VCC24")
      (value "JP1E")
      (footprint "eagle-import:JP1")
      (libsource (lib "eagle-import") (part "JP1E"))
    )
    (comp (ref "VCC25")
      (value "JP1E")
      (footprint "eagle-import:JP1")
      (libsource (lib "eagle-import") (part "JP1E"))
    )
    (comp (ref "VCC26")
      (value "JP1E")
      (footprint "eagle-import:JP1")
      (libsource (lib "eagle-import") (part "JP1E"))
    )
    (comp (ref "VCC27")
      (value "JP1E")
      (footprint "eagle-import:JP1")
      (libsource (lib "eagle-import") (part "JP1E"))
    )
    (comp (ref "VCC28")
      (value "JP1E")
      (footprint "eagle-import:JP1")
      (libsource (lib "eagle-import") (part "JP1E"))
    )
    (comp (ref "VCC29")
      (value "JP1E")
      (footprint "eagle-import:JP1")
      (libsource (lib "eagle-import") (part "JP1E"))
    )
    (comp (ref "VCC30")
      (value "JP1E")
      (footprint "eagle-import:JP1")
      (libsource (lib "eagle-import") (part "JP1E"))
    )
    (comp (ref "VCC31")
      (value "JP1E")
      (footprint "eagle-import:JP1")
      (libsource (lib "eagle-import") (part "JP1E"))
    )
    (comp (ref "VCC32")
      (value "JP1E")
      (footprint "eagle-import:JP1")
      (libsource (lib "eagle-import") (part "JP1E"))
    )
    (comp (ref "VCC33")
      (value "JP1E")
      (footprint "eagle-import:JP1")
      (libsource (lib "eagle-import") (part "JP1E"))
    )
    (comp (ref "VCC34")
      (value "JP1E")
      (footprint "eagle-import:JP1")
      (libsource (lib "eagle-import") (part "JP1E"))
    )
    (comp (ref "VCC35")
      (value "JP1E")
      (footprint "eagle-import:JP1")
      (libsource (lib "eagle-import") (part "JP1E"))
    )
    (comp (ref "VCC36")
      (value "JP1E")
      (footprint "eagle-import:JP1")
      (libsource (lib "eagle-import") (part "JP1E"))
    )
    (comp (ref "VCC37")
      (value "JP1E")
      (footprint "eagle-import:JP1")
      (libsource (lib "eagle-import") (part "JP1E"))
    )
    (comp (ref "VCC38")
      (value "JP1E")
      (footprint "eagle-import:JP1")
      (libsource (lib "eagle-import") (part "JP1E"))
    )
    (comp (ref "VCC39")
      (value "JP1E")
      (footprint "eagle-import:JP1")
      (libsource (lib "eagle-import") (part "JP1E"))
    )
    (comp (ref "VCC40")
      (value "JP1E")
      (footprint "eagle-import:JP1")
      (libsource (lib "eagle-import") (part "JP1E"))
    )
    (comp (ref "VCC41")
      (value "JP1E")
      (footprint "eagle-import:JP1")
      (libsource (lib "eagle-import") (part "JP1E"))
    )
    (comp (ref "VCC42")
      (value "JP1E")
      (footprint "eagle-import:JP1")
      (libsource (lib "eagle-import") (part "JP1E"))
    )
    (comp (ref "VCC43")
      (value "JP1E")
      (footprint "eagle-import:JP1")
      (libsource (lib "eagle-import") (part "JP1E"))
    )
    (comp (ref "VCC44")
      (value "JP1E")
      (footprint "eagle-import:JP1")
      (libsource (lib "eagle-import") (part "JP1E"))
    )
    (comp (ref "SV1")
      (value "MA05-2")
      (footprint "eagle-import:MA05-2")
      (libsource (lib "eagle-import") (part "MA05-2"))
    )
    (comp (ref "SV2")
      (value "MA05-2")
      (footprint "eagle-import:MA05-2")
      (libsource (lib "eagle-import") (part "MA05-2"))
    )
    (comp (ref "SV3")
      (value "MA20-1")
      (footprint "eagle-import:MA20-1")
      (libsource (lib "eagle-import") (part "MA20-1"))
    )
    (comp (ref "SV4")
      (value "MA20-1")
      (footprint "eagle-import:MA20-1")
      (libsource (lib "eagle-import") (part "MA20-1"))
    )
    (comp (ref "SV5")
      (value "MA20-1")
      (footprint "eagle-import:MA20-1")
      (libsource (lib "eagle-import") (part "MA20-1"))
    )
    (comp (ref "SV6")
      (value "MA20-1")
      (footprint "eagle-import:MA20-1")
      (libsource (lib "eagle-import") (part "MA20-1"))
    )
    (comp (ref "SV7")
      (value "MA05-2")
      (footprint "eagle-import:MA05-2")
      (libsource (lib "eagle-import") (part "MA05-2"))
    )
    (comp (ref "SV8")
      (value "MA05-2")
      (footprint "eagle-import:MA05-2")
      (libsource (lib "eagle-import") (part "MA05-2"))
    )
    (comp (ref "SV9")
      (value "MA08-1")
      (footprint "eagle-import:MA08-1")
      (libsource (lib "eagle-import") (part "MA08-1"))
    )
    (comp (ref "SV10")
      (value "MA08-1")
      (footprint "eagle-import:MA08-1")
      (libsource (lib "eagle-import") (part "MA08-1"))
    )
    (comp (ref "SV11")
      (value "MA10-1")
      (footprint "eagle-import:MA10-1")
      (libsource (lib "eagle-import") (part "MA10-1"))
    )
    (comp (ref "SV12")
      (value "MA10-1")
      (footprint "eagle-import:MA10-1")
      (libsource (lib "eagle-import") (part "MA10-1"))
    )
    (comp (ref "SV13")
      (value "MA05-2")
      (footprint "eagle-import:MA05-2")
      (libsource (lib "eagle-import") (part "MA05-2"))
    )
    (comp (ref "SV14")
      (value "MA05-2")
      (footprint "eagle-import:MA05-2")
      (libsource (lib "eagle-import") (part "MA05-2"))
    )
    (comp (ref "SV15")
      (value "MA05-2")
      (footprint "eagle-import:MA05-2")
      (libsource (lib "eagle-import") (part "MA05-2"))
    )
    (comp (ref "SV16")
      (value "MA05-2")
      (footprint "eagle-import:MA05-2")
      (libsource (lib "eagle-import") (part "MA05-2"))
    )
    (comp (ref "SV17")
      (value "MA05-2")
      (footprint "eagle-import:MA05-2")
      (libsource (lib "eagle-import") (part "MA05-2"))
    )
    (comp (ref "SV18")
      (value "MA05-2")
      (footprint "eagle-import:MA05-2")
      (libsource (lib "eagle-import") (part "MA05-2"))
    )
    (comp (ref "SV19")
      (value "MA05-2")
      (footprint "eagle-import:MA05-2")
      (libsource (lib "eagle-import") (part "MA05-2"))
    )
    (comp (ref "SV20")
      (value "MA05-2")
      (footprint "eagle-import:MA05-2")
      (libsource (lib "eagle-import") (part "MA05-2"))
    )
    (comp (ref "SV21")
      (value "MA05-2")
      (footprint "eagle-import:MA05-2")
      (libsource (lib "eagle-import") (part "MA05-2"))
    )
    (comp (ref "SV22")
      (value "MA05-2")
      (footprint "eagle-import:MA05-2")
      (libsource (lib "eagle-import") (part "MA05-2"))
    )
    (comp (ref "SV23")
      (value "MA05-2")
      (footprint "eagle-import:MA05-2")
      (libsource (lib "eagle-import") (part "MA05-2"))
    )
    (comp (ref "SV24")
      (value "MA05-2")
      (footprint "eagle-import:MA05-2")
      (libsource (lib "eagle-import") (part "MA05-2"))
    )
    (comp (ref "SV25")
      (value "MA05-2")
      (footprint "eagle-import:MA05-2")
      (libsource (lib "eagle-import") (part "MA05-2"))
    )
    (comp (ref "SV26")
      (value "MA05-2")
      (footprint "eagle-import:MA05-2")
      (libsource (lib "eagle-import") (part "MA05-2"))
    )
    (comp (ref "SV27")
      (value "MA05-2")
      (footprint "eagle-import:MA05-2")
      (libsource (lib "eagle-import") (part "MA05-2"))
    )
    (comp (ref "SV28")
      (value "MA05-2")
      (footprint "eagle-import:MA05-2")
      (libsource (lib "eagle-import") (part "MA05-2"))
    )
    (comp (ref "SV29")
      (value "MA05-2")
      (footprint "eagle-import:MA05-2")
      (libsource (lib "eagle-import") (part "MA05-2"))
    )
    (comp (ref "SV30")
      (value "MA05-2")
      (footprint "eagle-import:MA05-2")
      (libsource (lib "eagle-import") (part "MA05-2"))
    )
    (comp (ref "SV31")
      (value "MA05-2")
      (footprint "eagle-import:MA05-2")
      (libsource (lib "eagle-import") (part "MA05-2"))
    )
    (comp (ref "SV32")
      (value "MA05-2")
      (footprint "eagle-import:MA05-2")
      (libsource (lib "eagle-import") (part "MA05-2"))
    )
    (comp (ref "SV33")
      (value "MA05-2")
      (footprint "eagle-import:MA05-2")
      (libsource (lib "eagle-import") (part "MA05-2"))
    )
    (comp (ref "SV34")
      (value "MA05-2")
      (footprint "eagle-import:MA05-2")
      (libsource (lib "eagle-import") (part "MA05-2"))
    )
    (comp (ref "SV35")
      (value "MA05-2")
      (footprint "eagle-import:MA05-2")
      (libsource (lib "eagle-import") (part "MA05-2"))
    )
    (comp (ref "SV36")
      (value "MA05-2")
      (footprint "eagle-import:MA05-2")
      (libsource (lib "eagle-import") (part "MA05-2"))
    )
    (comp (ref "SV37")
      (value "MA05-2")
      (footprint "eagle-import:MA05-2")
      (libsource (lib "eagle-import") (part "MA05-2"))
    )
    (comp (ref "SV38")
      (value "MA05-2")
      (footprint "eagle-import:MA05-2")
      (libsource (lib "eagle-import") (part "MA05-2"))
    )
    (comp (ref "SV39")
      (value "MA05-2")
      (footprint "eagle-import:MA05-2")
      (libsource (lib "eagle-import") (part "MA05-2"))
    )
    (comp (ref "SV40")
      (value "MA05-2")
      (footprint "eagle-import:MA05-2")
      (libsource (lib "eagle-import") (part "MA05-2"))
    )
    (comp (ref "SV41")
      (value "MA05-2")
      (footprint "eagle-import:MA05-2")
      (libsource (lib "eagle-import") (part "MA05-2"))
    )
    (comp (ref "SV42")
      (value "MA05-2")
      (footprint "eagle-import:MA05-2")
      (libsource (lib "eagle-import") (part "MA05-2"))
    )
    (comp (ref "SV43")
      (value "MA05-2")
      (footprint "eagle-import:MA05-2")
      (libsource (lib "eagle-import") (part "MA05-2"))
    )
    (comp (ref "SV44")
      (value "MA05-2")
      (footprint "eagle-import:MA05-2")
      (libsource (lib "eagle-import") (part "MA05-2"))
    )
    (comp (ref "SV45")
      (value "MA05-2")
      (footprint "eagle-import:MA05-2")
      (libsource (lib "eagle-import") (part "MA05-2"))
    )
    (comp (ref "SV46")
      (value "MA05-2")
      (footprint "eagle-import:MA05-2")
      (libsource (lib "eagle-import") (part "MA05-2"))
    )
    (comp (ref "SV47")
      (value "MA05-2")
      (footprint "eagle-import:MA05-2")
      (libsource (lib "eagle-import") (part "MA05-2"))
    )
    (comp (ref "SV48")
      (value "MA05-2")
      (footprint "eagle-import:MA05-2")
      (libsource (lib "eagle-import") (part "MA05-2"))
    )
    (comp (ref "SV49")
      (value "MA05-2")
      (footprint "eagle-import:MA05-2")
      (libsource (lib "eagle-import") (part "MA05-2"))
    )
    (comp (ref "SV50")
      (value "MA05-2")
      (footprint "eagle-import:MA05-2")
      (libsource (lib "eagle-import") (part "MA05-2"))
    )
    (comp (ref "SV51")
      (value "MA05-2")
      (footprint "eagle-import:MA05-2")
      (libsource (lib "eagle-import") (part "MA05-2"))
    )
    (comp (ref "SV52")
      (value "MA05-2")
      (footprint "eagle-import:MA05-2")
      (libsource (lib "eagle-import") (part "MA05-2"))
    )
    (comp (ref "SV53")
      (value "MA05-2")
      (footprint "eagle-import:MA05-2")
      (libsource (lib "eagle-import") (part "MA05-2"))
    )
    (comp (ref "SV54")
      (value "MA05-2")
      (footprint "eagle-import:MA05-2")
      (libsource (lib "eagle-import") (part "MA05-2"))
    )
    (comp (ref "SV55")
      (value "MA05-2")
      (footprint "eagle-import:MA05-2")
      (libsource (lib "eagle-import") (part "MA05-2"))
    )
    (comp (ref "SV56")
      (value "MA05-2")
      (footprint "eagle-import:MA05-2")
      (libsource (lib "eagle-import") (part "MA05-2"))
    )
    (comp (ref "SV57")
      (value "MA05-2")
      (footprint "eagle-import:MA05-2")
      (libsource (lib "eagle-import") (part "MA05-2"))
    )
    (comp (ref "SV58")
      (value "MA05-2")
      (footprint "eagle-import:MA05-2")
      (libsource (lib "eagle-import") (part "MA05-2"))
    )
    (comp (ref "SV59")
      (value "MA05-2")
      (footprint "eagle-import:MA05-2")
      (libsource (lib "eagle-import") (part "MA05-2"))
    )
    (comp (ref "SV60")
      (value "MA05-2")
      (footprint "eagle-import:MA05-2")
      (libsource (lib "eagle-import") (part "MA05-2"))
    )
    (comp (ref "SV61")
      (value "MA05-2")
      (footprint "eagle-import:MA05-2")
      (libsource (lib "eagle-import") (part "MA05-2"))
    )
    (comp (ref "SV62")
      (value "MA05-2")
      (footprint "eagle-import:MA05-2")
      (libsource (lib "eagle-import") (part "MA05-2"))
    )
    (comp (ref "SV63")
      (value "MA05-2")
      (footprint "eagle-import:MA05-2")
      (libsource (lib "eagle-import") (part "MA05-2"))
    )
    (comp (ref "SV64")
      (value "MA05-2")
      (footprint "eagle-import:MA05-2")
      (libsource (lib "eagle-import") (part "MA05-2"))
    )
    (comp (ref "SV65")
      (value "MA05-2")
      (footprint "eagle-import:MA05-2")
      (libsource (lib "eagle-import") (part "MA05-2"))
    )
    (comp (ref "SV66")
      (value "MA05-2")
      (footprint "eagle-import:MA05-2")
      (libsource (lib "eagle-import") (part "MA05-2"))
    )
    (comp (ref "SV67")
      (value "MA05-2")
      (footprint "eagle-import:MA05-2")
      (libsource (lib "eagle-import") (part "MA05-2"))
    )
    (comp (ref "SV68")
      (value "MA05-2")
      (footprint "eagle-import:MA05-2")
      (libsource (lib "eagle-import") (part "MA05-2"))
    )
    (comp (ref "SV69")
      (value "MA05-2")
      (footprint "eagle-import:MA05-2")
      (libsource (lib "eagle-import") (part "MA05-2"))
    )
    (comp (ref "SV70")
      (value "MA05-2")
      (footprint "eagle-import:MA05-2")
      (libsource (lib "eagle-import") (part "MA05-2"))
    )
    (comp (ref "SV71")
      (value "MA05-2")
      (footprint "eagle-import:MA05-2")
      (libsource (lib "eagle-import") (part "MA05-2"))
    )
    (comp (ref "SV72")
      (value "MA05-2")
      (footprint "eagle-import:MA05-2")
      (libsource (lib "eagle-import") (part "MA05-2"))
    )
    (comp (ref "SV73")
      (value "MA05-2")
      (footprint "eagle-import:MA05-2")
      (libsource (lib "eagle-import") (part "MA05-2"))
    )
    (comp (ref "SV74")
      (value "MA05-2")
      (footprint "eagle-import:MA05-2")
      (libsource (lib "eagle-import") (part "MA05-2"))
    )
    (comp (ref "SV75")
      (value "MA05-2")
      (footprint "eagle-import:MA05-2")
      (libsource (lib "eagle-import") (part "MA05-2"))
    )
    (comp (ref "SV76")
      (value "MA05-2")
      (footprint "eagle-import:MA05-2")
      (libsource (lib "eagle-import") (part "MA05-2"))
    )
    (comp (ref "SV77")
      (value "MA05-2")
      (footprint "eagle-import:MA05-2")
      (libsource (lib "eagle-import") (part "MA05-2"))
    )
    (comp (ref "SV78")
      (value "MA05-2")
      (footprint "eagle-import:MA05-2")
      (libsource (lib "eagle-import") (part "MA05-2"))
    )
    (comp (ref "SV79")
      (value "MA05-2")
      (footprint "eagle-import:MA05-2")
      (libsource (lib "eagle-import") (part "MA05-2"))
    )
    (comp (ref "SV80")
      (value "MA05-2")
      (footprint "eagle-import:MA05-2")
      (libsource (lib "eagle-import") (part "MA05-2"))
    )
    (comp (ref "SV81")
      (value "MA05-2")
      (footprint "eagle-import:MA05-2")
      (libsource (lib "eagle-import") (part "MA05-2"))
    )
    (comp (ref "SV82")
      (value "MA05-2")
      (footprint "eagle-import:MA05-2")
      (libsource (lib "eagle-import") (part "MA05-2"))
    )
    (comp (ref "SV83")
      (value "MA05-2")
      (footprint "eagle-import:MA05-2")
      (libsource (lib "eagle-import") (part "MA05-2"))
    )
    (comp (ref "SV84")
      (value "MA05-2")
      (footprint "eagle-import:MA05-2")
      (libsource (lib "eagle-import") (part "MA05-2"))
    )
    (comp (ref "SV85")
      (value "MA05-2")
      (footprint "eagle-import:MA05-2")
      (libsource (lib "eagle-import") (part "MA05-2"))
    )
    (comp (ref "SV86")
      (value "MA05-2")
      (footprint "eagle-import:MA05-2")
      (libsource (lib "eagle-import") (part "MA05-2"))
    )
    (comp (ref "SV87")
      (value "MA05-2")
      (footprint "eagle-import:MA05-2")
      (libsource (lib "eagle-import") (part "MA05-2"))
    )
    (comp (ref "SV88")
      (value "MA05-2")
      (footprint "eagle-import:MA05-2")
      (libsource (lib "eagle-import") (part "MA05-2"))
    )
    (comp (ref "SV89")
      (value "MA05-2")
      (footprint "eagle-import:MA05-2")
      (libsource (lib "eagle-import") (part "MA05-2"))
    )
    (comp (ref "SV90")
      (value "MA05-2")
      (footprint "eagle-import:MA05-2")
      (libsource (lib "eagle-import") (part "MA05-2"))
    )
    (comp (ref "SV91")
      (value "MA05-2")
      (footprint "eagle-import:MA05-2")
      (libsource (lib "eagle-import") (part "MA05-2"))
    )
    (comp (ref "SV92")
      (value "MA05-2")
      (footprint "eagle-import:MA05-2")
      (libsource (lib "eagle-import") (part "MA05-2"))
    )
    (comp (ref "SV93")
      (value "MA05-2")
      (footprint "eagle-import:MA05-2")
      (libsource (lib "eagle-import") (part "MA05-2"))
    )
    (comp (ref "SV94")
      (value "MA05-2")
      (footprint "eagle-import:MA05-2")
      (libsource (lib "eagle-import") (part "MA05-2"))
    )
    (comp (ref "SV95")
      (value "MA05-2")
      (footprint "eagle-import:MA05-2")
      (libsource (lib "eagle-import") (part "MA05-2"))
    )
    (comp (ref "SV96")
      (value "MA05-2")
      (footprint "eagle-import:MA05-2")
      (libsource (lib "eagle-import") (part "MA05-2"))
    )
    (comp (ref "SV97")
      (value "MA05-2")
      (footprint "eagle-import:MA05-2")
      (libsource (lib "eagle-import") (part "MA05-2"))
    )
    (comp (ref "SV98")
      (value "MA05-2")
      (footprint "eagle-import:MA05-2")
      (libsource (lib "eagle-import") (part "MA05-2"))
    )
    (comp (ref "SV99")
      (value "MA05-2")
      (footprint "eagle-import:MA05-2")
      (libsource (lib "eagle-import") (part "MA05-2"))
    )
    (comp (ref "SV100")
      (value "MA05-2")
      (footprint "eagle-import:MA05-2")
      (libsource (lib "eagle-import") (part "MA05-2"))
    )
    (comp (ref "SV101")
      (value "MA05-2")
      (footprint "eagle-import:MA05-2")
      (libsource (lib "eagle-import") (part "MA05-2"))
    )
    (comp (ref "SV102")
      (value "MA05-2")
      (footprint "eagle-import:MA05-2")
      (libsource (lib "eagle-import") (part "MA05-2"))
    )
    (comp (ref "SV103")
      (value "MA05-2")
      (footprint "eagle-import:MA05-2")
      (libsource (lib "eagle-import") (part "MA05-2"))
    )
    (comp (ref "SV104")
      (value "MA05-2")
      (footprint "eagle-import:MA05-2")
      (libsource (lib "eagle-import") (part "MA05-2"))
    )
    (comp (ref "SV105")
      (value "MA05-2")
      (footprint "eagle-import:MA05-2")
      (libsource (lib "eagle-import") (part "MA05-2"))
    )
    (comp (ref "SV106")
      (value "MA05-2")
      (footprint "eagle-import:MA05-2")
      (libsource (lib "eagle-import") (part "MA05-2"))
    )
    (comp (ref "SV107")
      (value "MA05-2")
      (footprint "eagle-import:MA05-2")
      (libsource (lib "eagle-import") (part "MA05-2"))
    )
    (comp (ref "SV108")
      (value "MA05-2")
      (footprint "eagle-import:MA05-2")
      (libsource (lib "eagle-import") (part "MA05-2"))
    )
    (comp (ref "SV109")
      (value "MA05-2")
      (footprint "eagle-import:MA05-2")
      (libsource (lib "eagle-import") (part "MA05-2"))
    )
    (comp (ref "SV110")
      (value "MA05-2")
      (footprint "eagle-import:MA05-2")
      (libsource (lib "eagle-import") (part "MA05-2"))
    )
    (comp (ref "SV111")
      (value "MA05-2")
      (footprint "eagle-import:MA05-2")
      (libsource (lib "eagle-import") (part "MA05-2"))
    )
    (comp (ref "SV112")
      (value "MA05-2")
      (footprint "eagle-import:MA05-2")
      (libsource (lib "eagle-import") (part "MA05-2"))
    )
    (comp (ref "SV113")
      (value "MA05-2")
      (footprint "eagle-import:MA05-2")
      (libsource (lib "eagle-import") (part "MA05-2"))
    )
    (comp (ref "SV114")
      (value "MA05-2")
      (footprint "eagle-import:MA05-2")
      (libsource (lib "eagle-import") (part "MA05-2"))
    )
    (comp (ref "SV115")
      (value "MA05-2")
      (footprint "eagle-import:MA05-2")
      (libsource (lib "eagle-import") (part "MA05-2"))
    )
    (comp (ref "SV116")
      (value "MA05-2")
      (footprint "eagle-import:MA05-2")
      (libsource (lib "eagle-import") (part "MA05-2"))
    )
    (comp (ref "SV117")
      (value "MA05-2")
      (footprint "eagle-import:MA05-2")
      (libsource (lib "eagle-import") (part "MA05-2"))
    )
    (comp (ref "SV118")
      (value "MA05-2")
      (footprint "eagle-import:MA05-2")
      (libsource (lib "eagle-import") (part "MA05-2"))
    )
    (comp (ref "SV119")
      (value "MA05-2")
      (footprint "eagle-import:MA05-2")
      (libsource (lib "eagle-import") (part "MA05-2"))
    )
    (comp (ref "SV120")
      (value "MA05-2")
      (footprint "eagle-import:MA05-2")
      (libsource (lib "eagle-import") (part "MA05-2"))
    )
    (comp (ref "SV121")
      (value "MA05-2")
      (footprint "eagle-import:MA05-2")
      (libsource (lib "eagle-import") (part "MA05-2"))
    )
    (comp (ref "SV122")
      (value "MA05-2")
      (footprint "eagle-import:MA05-2")
      (libsource (lib "eagle-import") (part "MA05-2"))
    )
    (comp (ref "SV123")
      (value "MA05-2")
      (footprint "eagle-import:MA05-2")
      (libsource (lib "eagle-import") (part "MA05-2"))
    )
    (comp (ref "SV124")
      (value "MA05-2")
      (footprint "eagle-import:MA05-2")
      (libsource (lib "eagle-import") (part "MA05-2"))
    )
    (comp (ref "SV125")
      (value "MA20-1")
      (footprint "eagle-import:MA20-1")
      (libsource (lib "eagle-import") (part "MA20-1"))
    )
    (comp (ref "SV126")
      (value "MA05-2")
      (footprint "eagle-import:MA05-2")
      (libsource (lib "eagle-import") (part "MA05-2"))
    )
    (comp (ref "SV127")
      (value "MA08-1")
      (footprint "eagle-import:MA08-1")
      (libsource (lib "eagle-import") (part "MA08-1"))
    )
    (comp (ref "SV128")
      (value "MA05-2")
      (footprint "eagle-import:MA05-2")
      (libsource (lib "eagle-import") (part "MA05-2"))
    )
    (comp (ref "SV129")
      (value "MA10-1")
      (footprint "eagle-import:MA10-1")
      (libsource (lib "eagle-import") (part "MA10-1"))
    )
    (comp (ref "SV130")
      (value "MA05-2")
      (footprint "eagle-import:MA05-2")
      (libsource (lib "eagle-import") (part "MA05-2"))
    )
    (comp (ref "SV131")
      (value "MA20-1")
      (footprint "eagle-import:MA20-1")
      (libsource (lib "eagle-import") (part "MA20-1"))
    )
    (comp (ref "SV132")
      (value "MA05-2")
      (footprint "eagle-import:MA05-2")
      (libsource (lib "eagle-import") (part "MA05-2"))
    )
    (comp (ref "SV133")
      (value "MA05-2")
      (footprint "eagle-import:MA05-2")
      (libsource (lib "eagle-import") (part "MA05-2"))
    )
    (comp (ref "SV134")
      (value "MA05-2")
      (footprint "eagle-import:MA05-2")
      (libsource (lib "eagle-import") (part "MA05-2"))
    )
    (comp (ref "SV135")
      (value "MA05-2")
      (footprint "eagle-import:MA05-2")
      (libsource (lib "eagle-import") (part "MA05-2"))
    )
    (comp (ref "SV136")
      (value "MA05-2")
      (footprint "eagle-import:MA05-2")
      (libsource (lib "eagle-import") (part "MA05-2"))
    )
    (comp (ref "SV137")
      (value "MA05-2")
      (footprint "eagle-import:MA05-2")
      (libsource (lib "eagle-import") (part "MA05-2"))
    )
    (comp (ref "SV138")
      (value "MA05-2")
      (footprint "eagle-import:MA05-2")
      (libsource (lib "eagle-import") (part "MA05-2"))
    )
    (comp (ref "SV139")
      (value "MA05-2")
      (footprint "eagle-import:MA05-2")
      (libsource (lib "eagle-import") (part "MA05-2"))
    )
    (comp (ref "SV140")
      (value "MA05-2")
      (footprint "eagle-import:MA05-2")
      (libsource (lib "eagle-import") (part "MA05-2"))
    )
    (comp (ref "SV141")
      (value "MA05-2")
      (footprint "eagle-import:MA05-2")
      (libsource (lib "eagle-import") (part "MA05-2"))
    )
    (comp (ref "SV142")
      (value "MA05-2")
      (footprint "eagle-import:MA05-2")
      (libsource (lib "eagle-import") (part "MA05-2"))
    )
    (comp (ref "SV143")
      (value "MA05-2")
      (footprint "eagle-import:MA05-2")
      (libsource (lib "eagle-import") (part "MA05-2"))
    )
    (comp (ref "SV144")
      (value "MA05-2")
      (footprint "eagle-import:MA05-2")
      (libsource (lib "eagle-import") (part "MA05-2"))
    )
    (comp (ref "SV145")
      (value "MA05-2")
      (footprint "eagle-import:MA05-2")
      (libsource (lib "eagle-import") (part "MA05-2"))
    )
    (comp (ref "SV146")
      (value "MA05-2")
      (footprint "eagle-import:MA05-2")
      (libsource (lib "eagle-import") (part "MA05-2"))
    )
    (comp (ref "SV147")
      (value "MA05-2")
      (footprint "eagle-import:MA05-2")
      (libsource (lib "eagle-import") (part "MA05-2"))
    )
    (comp (ref "SV148")
      (value "MA05-2")
      (footprint "eagle-import:MA05-2")
      (libsource (lib "eagle-import") (part "MA05-2"))
    )
    (comp (ref "SV149")
      (value "MA05-2")
      (footprint "eagle-import:MA05-2")
      (libsource (lib "eagle-import") (part "MA05-2"))
    )
    (comp (ref "SV150")
      (value "MA05-2")
      (footprint "eagle-import:MA05-2")
      (libsource (lib "eagle-import") (part "MA05-2"))
    )
    (comp (ref "SV151")
      (value "MA05-2")
      (footprint "eagle-import:MA05-2")
      (libsource (lib "eagle-import") (part "MA05-2"))
    )
    (comp (ref "SV152")
      (value "MA05-2")
      (footprint "eagle-import:MA05-2")
      (libsource (lib "eagle-import") (part "MA05-2"))
    )
    (comp (ref "SV153")
      (value "MA05-2")
      (footprint "eagle-import:MA05-2")
      (libsource (lib "eagle-import") (part "MA05-2"))
    )
    (comp (ref "SV154")
      (value "MA05-2")
      (footprint "eagle-import:MA05-2")
      (libsource (lib "eagle-import") (part "MA05-2"))
    )
    (comp (ref "SV155")
      (value "MA05-2")
      (footprint "eagle-import:MA05-2")
      (libsource (lib "eagle-import") (part "MA05-2"))
    )
    (comp (ref "SV156")
      (value "MA05-2")
      (footprint "eagle-import:MA05-2")
      (libsource (lib "eagle-import") (part "MA05-2"))
    )
    (comp (ref "SV157")
      (value "MA05-2")
      (footprint "eagle-import:MA05-2")
      (libsource (lib "eagle-import") (part "MA05-2"))
    )
    (comp (ref "SV158")
      (value "MA05-2")
      (footprint "eagle-import:MA05-2")
      (libsource (lib "eagle-import") (part "MA05-2"))
    )
    (comp (ref "SV159")
      (value "MA05-2")
      (footprint "eagle-import:MA05-2")
      (libsource (lib "eagle-import") (part "MA05-2"))
    )
    (comp (ref "SV160")
      (value "MA05-2")
      (footprint "eagle-import:MA05-2")
      (libsource (lib "eagle-import") (part "MA05-2"))
    )
    (comp (ref "SV161")
      (value "MA05-2")
      (footprint "eagle-import:MA05-2")
      (libsource (lib "eagle-import") (part "MA05-2"))
    )
    (comp (ref "SV162")
      (value "MA05-2")
      (footprint "eagle-import:MA05-2")
      (libsource (lib "eagle-import") (part "MA05-2"))
    )
    (comp (ref "SV163")
      (value "MA05-2")
      (footprint "eagle-import:MA05-2")
      (libsource (lib "eagle-import") (part "MA05-2"))
    )
    (comp (ref "SV164")
      (value "MA05-2")
      (footprint "eagle-import:MA05-2")
      (libsource (lib "eagle-import") (part "MA05-2"))
    )
    (comp (ref "SV165")
      (value "MA05-2")
      (footprint "eagle-import:MA05-2")
      (libsource (lib "eagle-import") (part "MA05-2"))
    )
    (comp (ref "SV166")
      (value "MA05-2")
      (footprint "eagle-import:MA05-2")
      (libsource (lib "eagle-import") (part "MA05-2"))
    )
    (comp (ref "SV167")
      (value "MA05-2")
      (footprint "eagle-import:MA05-2")
      (libsource (lib "eagle-import") (part "MA05-2"))
    )
    (comp (ref "SV168")
      (value "MA05-2")
      (footprint "eagle-import:MA05-2")
      (libsource (lib "eagle-import") (part "MA05-2"))
    )
    (comp (ref "SV169")
      (value "MA05-2")
      (footprint "eagle-import:MA05-2")
      (libsource (lib "eagle-import") (part "MA05-2"))
    )
    (comp (ref "SV170")
      (value "MA05-2")
      (footprint "eagle-import:MA05-2")
      (libsource (lib "eagle-import") (part "MA05-2"))
    )
    (comp (ref "SV171")
      (value "MA05-2")
      (footprint "eagle-import:MA05-2")
      (libsource (lib "eagle-import") (part "MA05-2"))
    )
    (comp (ref "SV172")
      (value "MA05-2")
      (footprint "eagle-import:MA05-2")
      (libsource (lib "eagle-import") (part "MA05-2"))
    )
    (comp (ref "SV173")
      (value "MA05-2")
      (footprint "eagle-import:MA05-2")
      (libsource (lib "eagle-import") (part "MA05-2"))
    )
    (comp (ref "SV174")
      (value "MA05-2")
      (footprint "eagle-import:MA05-2")
      (libsource (lib "eagle-import") (part "MA05-2"))
    )
    (comp (ref "SV175")
      (value "MA20-1")
      (footprint "eagle-import:MA20-1")
      (libsource (lib "eagle-import") (part "MA20-1"))
    )
    (comp (ref "SV176")
      (value "MA20-1")
      (footprint "eagle-import:MA20-1")
      (libsource (lib "eagle-import") (part "MA20-1"))
    )
    (comp (ref "SV177")
      (value "MA08-1")
      (footprint "eagle-import:MA08-1")
      (libsource (lib "eagle-import") (part "MA08-1"))
    )
    (comp (ref "SV178")
      (value "MA08-1")
      (footprint "eagle-import:MA08-1")
      (libsource (lib "eagle-import") (part "MA08-1"))
    )
    (comp (ref "SV179")
      (value "MA10-1")
      (footprint "eagle-import:MA10-1")
      (libsource (lib "eagle-import") (part "MA10-1"))
    )
    (comp (ref "SV180")
      (value "MA10-1")
      (footprint "eagle-import:MA10-1")
      (libsource (lib "eagle-import") (part "MA10-1"))
    )
  )
  (nets
    (net (code "1") (name "+15V") (class "Default")
      (node (ref "D14") (pin "1") (pinfunction "1_1") (pintype "passive"))
      (node (ref "U$2") (pin "DA2") (pinfunction "1_DA2") (pintype "passive"))
    )
    (net (code "2") (name "-15V") (class "Default")
      (node (ref "D10") (pin "2") (pinfunction "2_2") (pintype "passive"))
      (node (ref "D12") (pin "2") (pinfunction "2_2") (pintype "passive"))
      (node (ref "D14") (pin "2") (pinfunction "2_2") (pintype "passive"))
      (node (ref "D8") (pin "2") (pinfunction "2_2") (pintype "passive"))
      (node (ref "U$2") (pin "AB2") (pinfunction "1_AB2") (pintype "passive"))
      (node (ref "U$2") (pin "BB2") (pinfunction "1_BB2") (pintype "passive"))
      (node (ref "U$2") (pin "CB2") (pinfunction "1_CB2") (pintype "passive"))
      (node (ref "U$2") (pin "DB2") (pinfunction "1_DB2") (pintype "passive"))
    )
    (net (code "3") (name "DISABLE") (class "Default")
      (node (ref "C2") (pin "2") (pinfunction "2_2") (pintype "passive"))
      (node (ref "IC6") (pin "8") (pinfunction "O_8") (pintype "output"))
      (node (ref "IC8") (pin "8") (pinfunction "A7_8") (pintype "input"))
      (node (ref "Q1") (pin "3") (pinfunction "E_3") (pintype "passive"))
    )
    (net (code "4") (name "EMEM0") (class "Default")
      (node (ref "IC2") (pin "11") (pinfunction "B8_11") (pintype "bidirectional"))
      (node (ref "IC4") (pin "19") (pinfunction "I/O7_19") (pintype "tri_state"))
    )
    (net (code "5") (name "EMEM1") (class "Default")
      (node (ref "IC2") (pin "12") (pinfunction "B7_12") (pintype "bidirectional"))
      (node (ref "IC4") (pin "18") (pinfunction "I/O6_18") (pintype "tri_state"))
    )
    (net (code "6") (name "EMEM2") (class "Default")
      (node (ref "IC2") (pin "13") (pinfunction "B6_13") (pintype "bidirectional"))
      (node (ref "IC4") (pin "17") (pinfunction "I/O5_17") (pintype "tri_state"))
    )
    (net (code "7") (name "EMEM3") (class "Default")
      (node (ref "IC2") (pin "14") (pinfunction "B5_14") (pintype "bidirectional"))
      (node (ref "IC4") (pin "16") (pinfunction "I/O4_16") (pintype "tri_state"))
    )
    (net (code "8") (name "GND") (class "Default")
      (node (ref "B1") (pin "-") (pinfunction "-_-") (pintype "passive"))
      (node (ref "B1") (pin "-@1") (pinfunction "-_-@1") (pintype "passive"))
      (node (ref "C1") (pin "2") (pinfunction "2_2") (pintype "passive"))
      (node (ref "C10") (pin "-") (pinfunction "-_-") (pintype "passive"))
      (node (ref "C3") (pin "2") (pinfunction "2_2") (pintype "passive"))
      (node (ref "C4") (pin "2") (pinfunction "2_2") (pintype "passive"))
      (node (ref "C5") (pin "2") (pinfunction "2_2") (pintype "passive"))
      (node (ref "C6") (pin "2") (pinfunction "2_2") (pintype "passive"))
      (node (ref "C7") (pin "2") (pinfunction "2_2") (pintype "passive"))
      (node (ref "C8") (pin "2") (pinfunction "2_2") (pintype "passive"))
      (node (ref "C9") (pin "2") (pinfunction "2_2") (pintype "passive"))
      (node (ref "D10") (pin "12") (pinfunction "12_12") (pintype "passive"))
      (node (ref "D10") (pin "16") (pinfunction "16_16") (pintype "passive"))
      (node (ref "D10") (pin "3") (pinfunction "3_3") (pintype "passive"))
      (node (ref "D10") (pin "6") (pinfunction "6_6") (pintype "passive"))
      (node (ref "D11") (pin "12") (pinfunction "12_12") (pintype "passive"))
      (node (ref "D11") (pin "16") (pinfunction "16_16") (pintype "passive"))
      (node (ref "D11") (pin "3") (pinfunction "3_3") (pintype "passive"))
      (node (ref "D11") (pin "6") (pinfunction "6_6") (pintype "passive"))
      (node (ref "D12") (pin "12") (pinfunction "12_12") (pintype "passive"))
      (node (ref "D12") (pin "16") (pinfunction "16_16") (pintype "passive"))
      (node (ref "D12") (pin "3") (pinfunction "3_3") (pintype "passive"))
      (node (ref "D12") (pin "6") (pinfunction "6_6") (pintype "passive"))
      (node (ref "D13") (pin "12") (pinfunction "12_12") (pintype "passive"))
      (node (ref "D13") (pin "16") (pinfunction "16_16") (pintype "passive"))
      (node (ref "D13") (pin "3") (pinfunction "3_3") (pintype "passive"))
      (node (ref "D13") (pin "6") (pinfunction "6_6") (pintype "passive"))
      (node (ref "D14") (pin "12") (pinfunction "12_12") (pintype "passive"))
      (node (ref "D14") (pin "16") (pinfunction "16_16") (pintype "passive"))
      (node (ref "D14") (pin "3") (pinfunction "3_3") (pintype "passive"))
      (node (ref "D14") (pin "6") (pinfunction "6_6") (pintype "passive"))
      (node (ref "D7") (pin "12") (pinfunction "12_12") (pintype "passive"))
      (node (ref "D7") (pin "16") (pinfunction "16_16") (pintype "passive"))
      (node (ref "D7") (pin "3") (pinfunction "3_3") (pintype "passive"))
      (node (ref "D7") (pin "6") (pinfunction "6_6") (pintype "passive"))
      (node (ref "D8") (pin "12") (pinfunction "12_12") (pintype "passive"))
      (node (ref "D8") (pin "16") (pinfunction "16_16") (pintype "passive"))
      (node (ref "D8") (pin "3") (pinfunction "3_3") (pintype "passive"))
      (node (ref "D8") (pin "6") (pinfunction "6_6") (pintype "passive"))
      (node (ref "D9") (pin "12") (pinfunction "12_12") (pintype "passive"))
      (node (ref "D9") (pin "16") (pinfunction "16_16") (pintype "passive"))
      (node (ref "D9") (pin "3") (pinfunction "3_3") (pintype "passive"))
      (node (ref "D9") (pin "6") (pinfunction "6_6") (pintype "passive"))
      (node (ref "GND1") (pin "1") (pinfunction "1_1") (pintype "passive"))
      (node (ref "GND1") (pin "2") (pinfunction "2_2") (pintype "passive"))
      (node (ref "GND10") (pin "1") (pinfunction "1_1") (pintype "passive"))
      (node (ref "GND10") (pin "2") (pinfunction "2_2") (pintype "passive"))
      (node (ref "GND11") (pin "1") (pinfunction "1_1") (pintype "passive"))
      (node (ref "GND11") (pin "2") (pinfunction "2_2") (pintype "passive"))
      (node (ref "GND12") (pin "1") (pinfunction "1_1") (pintype "passive"))
      (node (ref "GND12") (pin "2") (pinfunction "2_2") (pintype "passive"))
      (node (ref "GND13") (pin "1") (pinfunction "1_1") (pintype "passive"))
      (node (ref "GND13") (pin "2") (pinfunction "2_2") (pintype "passive"))
      (node (ref "GND14") (pin "1") (pinfunction "1_1") (pintype "passive"))
      (node (ref "GND14") (pin "2") (pinfunction "2_2") (pintype "passive"))
      (node (ref "GND15") (pin "1") (pinfunction "1_1") (pintype "passive"))
      (node (ref "GND15") (pin "2") (pinfunction "2_2") (pintype "passive"))
      (node (ref "GND16") (pin "1") (pinfunction "1_1") (pintype "passive"))
      (node (ref "GND16") (pin "2") (pinfunction "2_2") (pintype "passive"))
      (node (ref "GND17") (pin "1") (pinfunction "1_1") (pintype "passive"))
      (node (ref "GND17") (pin "2") (pinfunction "2_2") (pintype "passive"))
      (node (ref "GND18") (pin "1") (pinfunction "1_1") (pintype "passive"))
      (node (ref "GND18") (pin "2") (pinfunction "2_2") (pintype "passive"))
      (node (ref "GND19") (pin "1") (pinfunction "1_1") (pintype "passive"))
      (node (ref "GND19") (pin "2") (pinfunction "2_2") (pintype "passive"))
      (node (ref "GND2") (pin "1") (pinfunction "1_1") (pintype "passive"))
      (node (ref "GND2") (pin "2") (pinfunction "2_2") (pintype "passive"))
      (node (ref "GND20") (pin "1") (pinfunction "1_1") (pintype "passive"))
      (node (ref "GND20") (pin "2") (pinfunction "2_2") (pintype "passive"))
      (node (ref "GND21") (pin "1") (pinfunction "1_1") (pintype "passive"))
      (node (ref "GND21") (pin "2") (pinfunction "2_2") (pintype "passive"))
      (node (ref "GND22") (pin "1") (pinfunction "1_1") (pintype "passive"))
      (node (ref "GND22") (pin "2") (pinfunction "2_2") (pintype "passive"))
      (node (ref "GND23") (pin "1") (pinfunction "1_1") (pintype "passive"))
      (node (ref "GND23") (pin "2") (pinfunction "2_2") (pintype "passive"))
      (node (ref "GND24") (pin "1") (pinfunction "1_1") (pintype "passive"))
      (node (ref "GND24") (pin "2") (pinfunction "2_2") (pintype "passive"))
      (node (ref "GND25") (pin "1") (pinfunction "1_1") (pintype "passive"))
      (node (ref "GND25") (pin "2") (pinfunction "2_2") (pintype "passive"))
      (node (ref "GND26") (pin "1") (pinfunction "1_1") (pintype "passive"))
      (node (ref "GND26") (pin "2") (pinfunction "2_2") (pintype "passive"))
      (node (ref "GND27") (pin "1") (pinfunction "1_1") (pintype "passive"))
      (node (ref "GND27") (pin "2") (pinfunction "2_2") (pintype "passive"))
      (node (ref "GND28") (pin "1") (pinfunction "1_1") (pintype "passive"))
      (node (ref "GND28") (pin "2") (pinfunction "2_2") (pintype "passive"))
      (node (ref "GND29") (pin "1") (pinfunction "1_1") (pintype "passive"))
      (node (ref "GND29") (pin "2") (pinfunction "2_2") (pintype "passive"))
      (node (ref "GND3") (pin "1") (pinfunction "1_1") (pintype "passive"))
      (node (ref "GND3") (pin "2") (pinfunction "2_2") (pintype "passive"))
      (node (ref "GND30") (pin "1") (pinfunction "1_1") (pintype "passive"))
      (node (ref "GND30") (pin "2") (pinfunction "2_2") (pintype "passive"))
      (node (ref "GND31") (pin "1") (pinfunction "1_1") (pintype "passive"))
      (node (ref "GND31") (pin "2") (pinfunction "2_2") (pintype "passive"))
      (node (ref "GND32") (pin "1") (pinfunction "1_1") (pintype "passive"))
      (node (ref "GND32") (pin "2") (pinfunction "2_2") (pintype "passive"))
      (node (ref "GND33") (pin "1") (pinfunction "1_1") (pintype "passive"))
      (node (ref "GND33") (pin "2") (pinfunction "2_2") (pintype "passive"))
      (node (ref "GND34") (pin "1") (pinfunction "1_1") (pintype "passive"))
      (node (ref "GND34") (pin "2") (pinfunction "2_2") (pintype "passive"))
      (node (ref "GND35") (pin "1") (pinfunction "1_1") (pintype "passive"))
      (node (ref "GND35") (pin "2") (pinfunction "2_2") (pintype "passive"))
      (node (ref "GND36") (pin "1") (pinfunction "1_1") (pintype "passive"))
      (node (ref "GND36") (pin "2") (pinfunction "2_2") (pintype "passive"))
      (node (ref "GND37") (pin "1") (pinfunction "1_1") (pintype "passive"))
      (node (ref "GND37") (pin "2") (pinfunction "2_2") (pintype "passive"))
      (node (ref "GND38") (pin "1") (pinfunction "1_1") (pintype "passive"))
      (node (ref "GND38") (pin "2") (pinfunction "2_2") (pintype "passive"))
      (node (ref "GND39") (pin "1") (pinfunction "1_1") (pintype "passive"))
      (node (ref "GND39") (pin "2") (pinfunction "2_2") (pintype "passive"))
      (node (ref "GND4") (pin "1") (pinfunction "1_1") (pintype "passive"))
      (node (ref "GND4") (pin "2") (pinfunction "2_2") (pintype "passive"))
      (node (ref "GND40") (pin "1") (pinfunction "1_1") (pintype "passive"))
      (node (ref "GND40") (pin "2") (pinfunction "2_2") (pintype "passive"))
      (node (ref "GND41") (pin "1") (pinfunction "1_1") (pintype "passive"))
      (node (ref "GND41") (pin "2") (pinfunction "2_2") (pintype "passive"))
      (node (ref "GND42") (pin "1") (pinfunction "1_1") (pintype "passive"))
      (node (ref "GND42") (pin "2") (pinfunction "2_2") (pintype "passive"))
      (node (ref "GND43") (pin "1") (pinfunction "1_1") (pintype "passive"))
      (node (ref "GND43") (pin "2") (pinfunction "2_2") (pintype "passive"))
      (node (ref "GND44") (pin "1") (pinfunction "1_1") (pintype "passive"))
      (node (ref "GND44") (pin "2") (pinfunction "2_2") (pintype "passive"))
      (node (ref "GND5") (pin "1") (pinfunction "1_1") (pintype "passive"))
      (node (ref "GND5") (pin "2") (pinfunction "2_2") (pintype "passive"))
      (node (ref "GND6") (pin "1") (pinfunction "1_1") (pintype "passive"))
      (node (ref "GND6") (pin "2") (pinfunction "2_2") (pintype "passive"))
      (node (ref "GND7") (pin "1") (pinfunction "1_1") (pintype "passive"))
      (node (ref "GND7") (pin "2") (pinfunction "2_2") (pintype "passive"))
      (node (ref "GND8") (pin "1") (pinfunction "1_1") (pintype "passive"))
      (node (ref "GND8") (pin "2") (pinfunction "2_2") (pintype "passive"))
      (node (ref "GND9") (pin "1") (pinfunction "1_1") (pintype "passive"))
      (node (ref "GND9") (pin "2") (pinfunction "2_2") (pintype "passive"))
      (node (ref "IC1") (pin "19") (pinfunction "G_19") (pintype "input"))
      (node (ref "IC2") (pin "19") (pinfunction "G_19") (pintype "input"))
      (node (ref "IC3") (pin "14") (pinfunction "VSS_14") (pintype "power_in"))
      (node (ref "IC4") (pin "14") (pinfunction "VSS_14") (pintype "power_in"))
      (node (ref "IC5") (pin "4") (pinfunction "G2A_4") (pintype "input"))
      (node (ref "IC5") (pin "5") (pinfunction "G2B_5") (pintype "input"))
      (node (ref "IC8") (pin "1") (pinfunction "G1_1") (pintype "input"))
      (node (ref "IC8") (pin "19") (pinfunction "G2_19") (pintype "input"))
      (node (ref "IC8") (pin "9") (pinfunction "A8_9") (pintype "input"))
      (node (ref "R1") (pin "1") (pinfunction "1_1") (pintype "passive"))
      (node (ref "R2") (pin "1") (pinfunction "1_1") (pintype "passive"))
      (node (ref "R3") (pin "1") (pinfunction "1_1") (pintype "passive"))
      (node (ref "R4") (pin "1") (pinfunction "1_1") (pintype "passive"))
      (node (ref "SV10") (pin "1") (pinfunction "1_1") (pintype "passive"))
      (node (ref "SV10") (pin "2") (pinfunction "2_2") (pintype "passive"))
      (node (ref "SV10") (pin "3") (pinfunction "3_3") (pintype "passive"))
      (node (ref "SV10") (pin "4") (pinfunction "4_4") (pintype "passive"))
      (node (ref "SV10") (pin "5") (pinfunction "5_5") (pintype "passive"))
      (node (ref "SV10") (pin "6") (pinfunction "6_6") (pintype "passive"))
      (node (ref "SV10") (pin "7") (pinfunction "7_7") (pintype "passive"))
      (node (ref "SV10") (pin "8") (pinfunction "8_8") (pintype "passive"))
      (node (ref "SV12") (pin "1") (pinfunction "1_1") (pintype "passive"))
      (node (ref "SV12") (pin "10") (pinfunction "10_10") (pintype "passive"))
      (node (ref "SV12") (pin "2") (pinfunction "2_2") (pintype "passive"))
      (node (ref "SV12") (pin "3") (pinfunction "3_3") (pintype "passive"))
      (node (ref "SV12") (pin "4") (pinfunction "4_4") (pintype "passive"))
      (node (ref "SV12") (pin "5") (pinfunction "5_5") (pintype "passive"))
      (node (ref "SV12") (pin "6") (pinfunction "6_6") (pintype "passive"))
      (node (ref "SV12") (pin "7") (pinfunction "7_7") (pintype "passive"))
      (node (ref "SV12") (pin "8") (pinfunction "8_8") (pintype "passive"))
      (node (ref "SV12") (pin "9") (pinfunction "9_9") (pintype "passive"))
      (node (ref "SV176") (pin "1") (pinfunction "1_1") (pintype "passive"))
      (node (ref "SV176") (pin "10") (pinfunction "10_10") (pintype "passive"))
      (node (ref "SV176") (pin "11") (pinfunction "11_11") (pintype "passive"))
      (node (ref "SV176") (pin "12") (pinfunction "12_12") (pintype "passive"))
      (node (ref "SV176") (pin "13") (pinfunction "13_13") (pintype "passive"))
      (node (ref "SV176") (pin "14") (pinfunction "14_14") (pintype "passive"))
      (node (ref "SV176") (pin "15") (pinfunction "15_15") (pintype "passive"))
      (node (ref "SV176") (pin "16") (pinfunction "16_16") (pintype "passive"))
      (node (ref "SV176") (pin "17") (pinfunction "17_17") (pintype "passive"))
      (node (ref "SV176") (pin "18") (pinfunction "18_18") (pintype "passive"))
      (node (ref "SV176") (pin "19") (pinfunction "19_19") (pintype "passive"))
      (node (ref "SV176") (pin "2") (pinfunction "2_2") (pintype "passive"))
      (node (ref "SV176") (pin "20") (pinfunction "20_20") (pintype "passive"))
      (node (ref "SV176") (pin "3") (pinfunction "3_3") (pintype "passive"))
      (node (ref "SV176") (pin "4") (pinfunction "4_4") (pintype "passive"))
      (node (ref "SV176") (pin "5") (pinfunction "5_5") (pintype "passive"))
      (node (ref "SV176") (pin "6") (pinfunction "6_6") (pintype "passive"))
      (node (ref "SV176") (pin "7") (pinfunction "7_7") (pintype "passive"))
      (node (ref "SV176") (pin "8") (pinfunction "8_8") (pintype "passive"))
      (node (ref "SV176") (pin "9") (pinfunction "9_9") (pintype "passive"))
      (node (ref "SV180") (pin "1") (pinfunction "1_1") (pintype "passive"))
      (node (ref "SV180") (pin "10") (pinfunction "10_10") (pintype "passive"))
      (node (ref "SV180") (pin "2") (pinfunction "2_2") (pintype "passive"))
      (node (ref "SV180") (pin "3") (pinfunction "3_3") (pintype "passive"))
      (node (ref "SV180") (pin "4") (pinfunction "4_4") (pintype "passive"))
      (node (ref "SV180") (pin "5") (pinfunction "5_5") (pintype "passive"))
      (node (ref "SV180") (pin "6") (pinfunction "6_6") (pintype "passive"))
      (node (ref "SV180") (pin "7") (pinfunction "7_7") (pintype "passive"))
      (node (ref "SV180") (pin "8") (pinfunction "8_8") (pintype "passive"))
      (node (ref "SV180") (pin "9") (pinfunction "9_9") (pintype "passive"))
      (node (ref "SV4") (pin "1") (pinfunction "1_1") (pintype "passive"))
      (node (ref "SV4") (pin "10") (pinfunction "10_10") (pintype "passive"))
      (node (ref "SV4") (pin "11") (pinfunction "11_11") (pintype "passive"))
      (node (ref "SV4") (pin "12") (pinfunction "12_12") (pintype "passive"))
      (node (ref "SV4") (pin "13") (pinfunction "13_13") (pintype "passive"))
      (node (ref "SV4") (pin "14") (pinfunction "14_14") (pintype "passive"))
      (node (ref "SV4") (pin "15") (pinfunction "15_15") (pintype "passive"))
      (node (ref "SV4") (pin "16") (pinfunction "16_16") (pintype "passive"))
      (node (ref "SV4") (pin "17") (pinfunction "17_17") (pintype "passive"))
      (node (ref "SV4") (pin "18") (pinfunction "18_18") (pintype "passive"))
      (node (ref "SV4") (pin "19") (pinfunction "19_19") (pintype "passive"))
      (node (ref "SV4") (pin "2") (pinfunction "2_2") (pintype "passive"))
      (node (ref "SV4") (pin "20") (pinfunction "20_20") (pintype "passive"))
      (node (ref "SV4") (pin "3") (pinfunction "3_3") (pintype "passive"))
      (node (ref "SV4") (pin "4") (pinfunction "4_4") (pintype "passive"))
      (node (ref "SV4") (pin "5") (pinfunction "5_5") (pintype "passive"))
      (node (ref "SV4") (pin "6") (pinfunction "6_6") (pintype "passive"))
      (node (ref "SV4") (pin "7") (pinfunction "7_7") (pintype "passive"))
      (node (ref "SV4") (pin "8") (pinfunction "8_8") (pintype "passive"))
      (node (ref "SV4") (pin "9") (pinfunction "9_9") (pintype "passive"))
      (node (ref "SV6") (pin "1") (pinfunction "1_1") (pintype "passive"))
      (node (ref "SV6") (pin "10") (pinfunction "10_10") (pintype "passive"))
      (node (ref "SV6") (pin "11") (pinfunction "11_11") (pintype "passive"))
      (node (ref "SV6") (pin "12") (pinfunction "12_12") (pintype "passive"))
      (node (ref "SV6") (pin "13") (pinfunction "13_13") (pintype "passive"))
      (node (ref "SV6") (pin "14") (pinfunction "14_14") (pintype "passive"))
      (node (ref "SV6") (pin "15") (pinfunction "15_15") (pintype "passive"))
      (node (ref "SV6") (pin "16") (pinfunction "16_16") (pintype "passive"))
      (node (ref "SV6") (pin "17") (pinfunction "17_17") (pintype "passive"))
      (node (ref "SV6") (pin "18") (pinfunction "18_18") (pintype "passive"))
      (node (ref "SV6") (pin "19") (pinfunction "19_19") (pintype "passive"))
      (node (ref "SV6") (pin "2") (pinfunction "2_2") (pintype "passive"))
      (node (ref "SV6") (pin "20") (pinfunction "20_20") (pintype "passive"))
      (node (ref "SV6") (pin "3") (pinfunction "3_3") (pintype "passive"))
      (node (ref "SV6") (pin "4") (pinfunction "4_4") (pintype "passive"))
      (node (ref "SV6") (pin "5") (pinfunction "5_5") (pintype "passive"))
      (node (ref "SV6") (pin "6") (pinfunction "6_6") (pintype "passive"))
      (node (ref "SV6") (pin "7") (pinfunction "7_7") (pintype "passive"))
      (node (ref "SV6") (pin "8") (pinfunction "8_8") (pintype "passive"))
      (node (ref "SV6") (pin "9") (pinfunction "9_9") (pintype "passive"))
      (node (ref "U$2") (pin "AC1") (pinfunction "1_AC1") (pintype "passive"))
      (node (ref "U$2") (pin "AC2") (pinfunction "1_AC2") (pintype "passive"))
      (node (ref "U$2") (pin "AF1") (pinfunction "1_AF1") (pintype "passive"))
      (node (ref "U$2") (pin "AF2") (pinfunction "1_AF2") (pintype "passive"))
      (node (ref "U$2") (pin "AN1") (pinfunction "1_AN1") (pintype "passive"))
      (node (ref "U$2") (pin "AN2") (pinfunction "1_AN2") (pintype "passive"))
      (node (ref "U$2") (pin "AT1") (pinfunction "1_AT1") (pintype "passive"))
      (node (ref "U$2") (pin "AT2") (pinfunction "1_AT2") (pintype "passive"))
      (node (ref "U$2") (pin "BC1") (pinfunction "1_BC1") (pintype "passive"))
      (node (ref "U$2") (pin "BC2") (pinfunction "1_BC2") (pintype "passive"))
      (node (ref "U$2") (pin "BF1") (pinfunction "1_BF1") (pintype "passive"))
      (node (ref "U$2") (pin "BF2") (pinfunction "1_BF2") (pintype "passive"))
      (node (ref "U$2") (pin "BN1") (pinfunction "1_BN1") (pintype "passive"))
      (node (ref "U$2") (pin "BN2") (pinfunction "1_BN2") (pintype "passive"))
      (node (ref "U$2") (pin "BT1") (pinfunction "1_BT1") (pintype "passive"))
      (node (ref "U$2") (pin "BT2") (pinfunction "1_BT2") (pintype "passive"))
      (node (ref "U$2") (pin "CC1") (pinfunction "1_CC1") (pintype "passive"))
      (node (ref "U$2") (pin "CC2") (pinfunction "1_CC2") (pintype "passive"))
      (node (ref "U$2") (pin "CF1") (pinfunction "1_CF1") (pintype "passive"))
      (node (ref "U$2") (pin "CF2") (pinfunction "1_CF2") (pintype "passive"))
      (node (ref "U$2") (pin "CN1") (pinfunction "1_CN1") (pintype "passive"))
      (node (ref "U$2") (pin "CN2") (pinfunction "1_CN2") (pintype "passive"))
      (node (ref "U$2") (pin "CT1") (pinfunction "1_CT1") (pintype "passive"))
      (node (ref "U$2") (pin "CT2") (pinfunction "1_CT2") (pintype "passive"))
      (node (ref "U$2") (pin "DC1") (pinfunction "1_DC1") (pintype "passive"))
      (node (ref "U$2") (pin "DC2") (pinfunction "1_DC2") (pintype "passive"))
      (node (ref "U$2") (pin "DF1") (pinfunction "1_DF1") (pintype "passive"))
      (node (ref "U$2") (pin "DF2") (pinfunction "1_DF2") (pintype "passive"))
      (node (ref "U$2") (pin "DN1") (pinfunction "1_DN1") (pintype "passive"))
      (node (ref "U$2") (pin "DN2") (pinfunction "1_DN2") (pintype "passive"))
      (node (ref "U$2") (pin "DT1") (pinfunction "1_DT1") (pintype "passive"))
      (node (ref "U$2") (pin "DT2") (pinfunction "1_DT2") (pintype "passive"))
    )
    (net (code "9") (name "INHIBIT") (class "Default")
      (node (ref "D10") (pin "13") (pinfunction "13_13") (pintype "passive"))
      (node (ref "U$2") (pin "AP2") (pinfunction "1_AP2") (pintype "passive"))
    )
    (net (code "10") (name "INITIALIZE") (class "Default")
      (node (ref "D11") (pin "14") (pinfunction "14_14") (pintype "passive"))
      (node (ref "U$2") (pin "CR1") (pinfunction "1_CR1") (pintype "passive"))
    )
    (net (code "11") (name "INT_IN_PROG") (class "Default")
      (node (ref "D8") (pin "13") (pinfunction "13_13") (pintype "passive"))
      (node (ref "U$2") (pin "BP2") (pinfunction "1_BP2") (pintype "passive"))
    )
    (net (code "12") (name "INT_STROBE") (class "Default")
      (node (ref "D8") (pin "4") (pinfunction "4_4") (pintype "passive"))
      (node (ref "U$2") (pin "BD2") (pinfunction "1_BD2") (pintype "passive"))
    )
    (net (code "13") (name "MEM00") (class "Default")
      (node (ref "IC2") (pin "15") (pinfunction "B4_15") (pintype "bidirectional"))
      (node (ref "IC4") (pin "15") (pinfunction "I/O3_15") (pintype "tri_state"))
    )
    (net (code "14") (name "MEM01") (class "Default")
      (node (ref "IC2") (pin "16") (pinfunction "B3_16") (pintype "bidirectional"))
      (node (ref "IC4") (pin "13") (pinfunction "I/O2_13") (pintype "tri_state"))
    )
    (net (code "15") (name "MEM02") (class "Default")
      (node (ref "IC2") (pin "17") (pinfunction "B2_17") (pintype "bidirectional"))
      (node (ref "IC4") (pin "12") (pinfunction "I/O1_12") (pintype "tri_state"))
    )
    (net (code "16") (name "MEM03") (class "Default")
      (node (ref "IC2") (pin "18") (pinfunction "B1_18") (pintype "bidirectional"))
      (node (ref "IC4") (pin "11") (pinfunction "I/O0_11") (pintype "tri_state"))
    )
    (net (code "17") (name "MEM04") (class "Default")
      (node (ref "IC1") (pin "11") (pinfunction "B8_11") (pintype "bidirectional"))
      (node (ref "IC3") (pin "19") (pinfunction "I/O7_19") (pintype "tri_state"))
    )
    (net (code "18") (name "MEM05") (class "Default")
      (node (ref "IC1") (pin "12") (pinfunction "B7_12") (pintype "bidirectional"))
      (node (ref "IC3") (pin "18") (pinfunction "I/O6_18") (pintype "tri_state"))
    )
    (net (code "19") (name "MEM06") (class "Default")
      (node (ref "IC1") (pin "13") (pinfunction "B6_13") (pintype "bidirectional"))
      (node (ref "IC3") (pin "17") (pinfunction "I/O5_17") (pintype "tri_state"))
    )
    (net (code "20") (name "MEM07") (class "Default")
      (node (ref "IC1") (pin "14") (pinfunction "B5_14") (pintype "bidirectional"))
      (node (ref "IC3") (pin "16") (pinfunction "I/O4_16") (pintype "tri_state"))
    )
    (net (code "21") (name "MEM08") (class "Default")
      (node (ref "IC1") (pin "15") (pinfunction "B4_15") (pintype "bidirectional"))
      (node (ref "IC3") (pin "15") (pinfunction "I/O3_15") (pintype "tri_state"))
    )
    (net (code "22") (name "MEM09") (class "Default")
      (node (ref "IC1") (pin "16") (pinfunction "B3_16") (pintype "bidirectional"))
      (node (ref "IC3") (pin "13") (pinfunction "I/O2_13") (pintype "tri_state"))
    )
    (net (code "23") (name "MEM10") (class "Default")
      (node (ref "IC1") (pin "17") (pinfunction "B2_17") (pintype "bidirectional"))
      (node (ref "IC3") (pin "12") (pinfunction "I/O1_12") (pintype "tri_state"))
    )
    (net (code "24") (name "MEM11") (class "Default")
      (node (ref "IC1") (pin "18") (pinfunction "B1_18") (pintype "bidirectional"))
      (node (ref "IC3") (pin "11") (pinfunction "I/O0_11") (pintype "tri_state"))
    )
    (net (code "25") (name "Net-(A1-Pad1)") (class "Default")
      (node (ref "A1") (pin "1") (pinfunction "1_1") (pintype "passive"))
      (node (ref "A1") (pin "2") (pinfunction "2_2") (pintype "passive"))
      (node (ref "IC9") (pin "1") (pinfunction "1_1") (pintype "passive"))
    )
    (net (code "26") (name "Net-(A2-Pad1)") (class "Default")
      (node (ref "A2") (pin "1") (pinfunction "1_1") (pintype "passive"))
      (node (ref "A2") (pin "2") (pinfunction "2_2") (pintype "passive"))
      (node (ref "IC9") (pin "2") (pinfunction "2_2") (pintype "passive"))
    )
    (net (code "27") (name "Net-(A3-Pad1)") (class "Default")
      (node (ref "A3") (pin "1") (pinfunction "1_1") (pintype "passive"))
      (node (ref "A3") (pin "2") (pinfunction "2_2") (pintype "passive"))
      (node (ref "IC9") (pin "3") (pinfunction "3_3") (pintype "passive"))
    )
    (net (code "28") (name "Net-(A4-Pad1)") (class "Default")
      (node (ref "A4") (pin "1") (pinfunction "1_1") (pintype "passive"))
      (node (ref "A4") (pin "2") (pinfunction "2_2") (pintype "passive"))
      (node (ref "IC9") (pin "4") (pinfunction "4_4") (pintype "passive"))
    )
    (net (code "29") (name "Net-(A5-Pad1)") (class "Default")
      (node (ref "A5") (pin "1") (pinfunction "1_1") (pintype "passive"))
      (node (ref "A5") (pin "2") (pinfunction "2_2") (pintype "passive"))
      (node (ref "IC9") (pin "5") (pinfunction "5_5") (pintype "passive"))
    )
    (net (code "30") (name "Net-(A6-Pad1)") (class "Default")
      (node (ref "A6") (pin "1") (pinfunction "1_1") (pintype "passive"))
      (node (ref "A6") (pin "2") (pinfunction "2_2") (pintype "passive"))
      (node (ref "IC9") (pin "6") (pinfunction "6_6") (pintype "passive"))
    )
    (net (code "31") (name "Net-(A7-Pad1)") (class "Default")
      (node (ref "A7") (pin "1") (pinfunction "1_1") (pintype "passive"))
      (node (ref "A7") (pin "2") (pinfunction "2_2") (pintype "passive"))
      (node (ref "IC9") (pin "7") (pinfunction "7_7") (pintype "passive"))
    )
    (net (code "32") (name "Net-(A8-Pad1)") (class "Default")
      (node (ref "A8") (pin "1") (pinfunction "1_1") (pintype "passive"))
      (node (ref "A8") (pin "2") (pinfunction "2_2") (pintype "passive"))
      (node (ref "IC9") (pin "8") (pinfunction "8_8") (pintype "passive"))
    )
    (net (code "33") (name "Net-(A9-Pad1)") (class "Default")
      (node (ref "A9") (pin "1") (pinfunction "1_1") (pintype "passive"))
      (node (ref "A9") (pin "2") (pinfunction "2_2") (pintype "passive"))
      (node (ref "IC9") (pin "9") (pinfunction "9_9") (pintype "passive"))
    )
    (net (code "34") (name "Net-(A10-Pad1)") (class "Default")
      (node (ref "A10") (pin "1") (pinfunction "1_1") (pintype "passive"))
      (node (ref "A10") (pin "2") (pinfunction "2_2") (pintype "passive"))
      (node (ref "IC9") (pin "10") (pinfunction "10_10") (pintype "passive"))
    )
    (net (code "35") (name "Net-(A11-Pad1)") (class "Default")
      (node (ref "A11") (pin "1") (pinfunction "1_1") (pintype "passive"))
      (node (ref "A11") (pin "2") (pinfunction "2_2") (pintype "passive"))
      (node (ref "IC9") (pin "11") (pinfunction "11_11") (pintype "passive"))
    )
    (net (code "36") (name "Net-(A12-Pad1)") (class "Default")
      (node (ref "A12") (pin "1") (pinfunction "1_1") (pintype "passive"))
      (node (ref "A12") (pin "2") (pinfunction "2_2") (pintype "passive"))
      (node (ref "IC9") (pin "12") (pinfunction "12_12") (pintype "passive"))
    )
    (net (code "37") (name "Net-(A13-Pad1)") (class "Default")
      (node (ref "A13") (pin "1") (pinfunction "1_1") (pintype "passive"))
      (node (ref "A13") (pin "2") (pinfunction "2_2") (pintype "passive"))
      (node (ref "IC9") (pin "13") (pinfunction "13_13") (pintype "passive"))
    )
    (net (code "38") (name "Net-(A14-Pad1)") (class "Default")
      (node (ref "A14") (pin "1") (pinfunction "1_1") (pintype "passive"))
      (node (ref "A14") (pin "2") (pinfunction "2_2") (pintype "passive"))
      (node (ref "IC9") (pin "14") (pinfunction "14_14") (pintype "passive"))
    )
    (net (code "39") (name "Net-(A15-Pad1)") (class "Default")
      (node (ref "A15") (pin "1") (pinfunction "1_1") (pintype "passive"))
      (node (ref "A15") (pin "2") (pinfunction "2_2") (pintype "passive"))
      (node (ref "IC9") (pin "15") (pinfunction "15_15") (pintype "passive"))
    )
    (net (code "40") (name "Net-(A16-Pad1)") (class "Default")
      (node (ref "A16") (pin "1") (pinfunction "1_1") (pintype "passive"))
      (node (ref "A16") (pin "2") (pinfunction "2_2") (pintype "passive"))
      (node (ref "IC9") (pin "16") (pinfunction "16_16") (pintype "passive"))
    )
    (net (code "41") (name "Net-(A17-Pad1)") (class "Default")
      (node (ref "A17") (pin "1") (pinfunction "1_1") (pintype "passive"))
      (node (ref "A17") (pin "2") (pinfunction "2_2") (pintype "passive"))
      (node (ref "IC10") (pin "1") (pinfunction "1_1") (pintype "passive"))
    )
    (net (code "42") (name "Net-(A18-Pad1)") (class "Default")
      (node (ref "A18") (pin "1") (pinfunction "1_1") (pintype "passive"))
      (node (ref "A18") (pin "2") (pinfunction "2_2") (pintype "passive"))
      (node (ref "IC10") (pin "2") (pinfunction "2_2") (pintype "passive"))
    )
    (net (code "43") (name "Net-(A19-Pad1)") (class "Default")
      (node (ref "A19") (pin "1") (pinfunction "1_1") (pintype "passive"))
      (node (ref "A19") (pin "2") (pinfunction "2_2") (pintype "passive"))
      (node (ref "IC10") (pin "3") (pinfunction "3_3") (pintype "passive"))
    )
    (net (code "44") (name "Net-(A20-Pad1)") (class "Default")
      (node (ref "A20") (pin "1") (pinfunction "1_1") (pintype "passive"))
      (node (ref "A20") (pin "2") (pinfunction "2_2") (pintype "passive"))
      (node (ref "IC10") (pin "4") (pinfunction "4_4") (pintype "passive"))
    )
    (net (code "45") (name "Net-(A21-Pad1)") (class "Default")
      (node (ref "A21") (pin "1") (pinfunction "1_1") (pintype "passive"))
      (node (ref "A21") (pin "2") (pinfunction "2_2") (pintype "passive"))
      (node (ref "IC10") (pin "5") (pinfunction "5_5") (pintype "passive"))
    )
    (net (code "46") (name "Net-(A22-Pad1)") (class "Default")
      (node (ref "A22") (pin "1") (pinfunction "1_1") (pintype "passive"))
      (node (ref "A22") (pin "2") (pinfunction "2_2") (pintype "passive"))
      (node (ref "IC10") (pin "6") (pinfunction "6_6") (pintype "passive"))
    )
    (net (code "47") (name "Net-(A23-Pad1)") (class "Default")
      (node (ref "A23") (pin "1") (pinfunction "1_1") (pintype "passive"))
      (node (ref "A23") (pin "2") (pinfunction "2_2") (pintype "passive"))
      (node (ref "IC10") (pin "7") (pinfunction "7_7") (pintype "passive"))
    )
    (net (code "48") (name "Net-(A24-Pad1)") (class "Default")
      (node (ref "A24") (pin "1") (pinfunction "1_1") (pintype "passive"))
      (node (ref "A24") (pin "2") (pinfunction "2_2") (pintype "passive"))
      (node (ref "IC10") (pin "8") (pinfunction "8_8") (pintype "passive"))
    )
    (net (code "49") (name "Net-(A25-Pad1)") (class "Default")
      (node (ref "A25") (pin "1") (pinfunction "1_1") (pintype "passive"))
      (node (ref "A25") (pin "2") (pinfunction "2_2") (pintype "passive"))
      (node (ref "IC10") (pin "9") (pinfunction "9_9") (pintype "passive"))
    )
    (net (code "50") (name "Net-(A26-Pad1)") (class "Default")
      (node (ref "A26") (pin "1") (pinfunction "1_1") (pintype "passive"))
      (node (ref "A26") (pin "2") (pinfunction "2_2") (pintype "passive"))
      (node (ref "IC10") (pin "10") (pinfunction "10_10") (pintype "passive"))
    )
    (net (code "51") (name "Net-(A27-Pad1)") (class "Default")
      (node (ref "A27") (pin "1") (pinfunction "1_1") (pintype "passive"))
      (node (ref "A27") (pin "2") (pinfunction "2_2") (pintype "passive"))
      (node (ref "IC10") (pin "11") (pinfunction "11_11") (pintype "passive"))
    )
    (net (code "52") (name "Net-(A28-Pad1)") (class "Default")
      (node (ref "A28") (pin "1") (pinfunction "1_1") (pintype "passive"))
      (node (ref "A28") (pin "2") (pinfunction "2_2") (pintype "passive"))
      (node (ref "IC10") (pin "12") (pinfunction "12_12") (pintype "passive"))
    )
    (net (code "53") (name "Net-(A29-Pad1)") (class "Default")
      (node (ref "A29") (pin "1") (pinfunction "1_1") (pintype "passive"))
      (node (ref "A29") (pin "2") (pinfunction "2_2") (pintype "passive"))
      (node (ref "IC10") (pin "13") (pinfunction "13_13") (pintype "passive"))
    )
    (net (code "54") (name "Net-(A30-Pad1)") (class "Default")
      (node (ref "A30") (pin "1") (pinfunction "1_1") (pintype "passive"))
      (node (ref "A30") (pin "2") (pinfunction "2_2") (pintype "passive"))
      (node (ref "IC10") (pin "14") (pinfunction "14_14") (pintype "passive"))
    )
    (net (code "55") (name "Net-(A31-Pad1)") (class "Default")
      (node (ref "A31") (pin "1") (pinfunction "1_1") (pintype "passive"))
      (node (ref "A31") (pin "2") (pinfunction "2_2") (pintype "passive"))
      (node (ref "IC10") (pin "15") (pinfunction "15_15") (pintype "passive"))
    )
    (net (code "56") (name "Net-(A32-Pad1)") (class "Default")
      (node (ref "A32") (pin "1") (pinfunction "1_1") (pintype "passive"))
      (node (ref "A32") (pin "2") (pinfunction "2_2") (pintype "passive"))
      (node (ref "IC10") (pin "16") (pinfunction "16_16") (pintype "passive"))
    )
    (net (code "57") (name "Net-(A33-Pad1)") (class "Default")
      (node (ref "A33") (pin "1") (pinfunction "1_1") (pintype "passive"))
      (node (ref "A33") (pin "2") (pinfunction "2_2") (pintype "passive"))
      (node (ref "IC11") (pin "1") (pinfunction "1_1") (pintype "passive"))
    )
    (net (code "58") (name "Net-(A34-Pad1)") (class "Default")
      (node (ref "A34") (pin "1") (pinfunction "1_1") (pintype "passive"))
      (node (ref "A34") (pin "2") (pinfunction "2_2") (pintype "passive"))
      (node (ref "IC11") (pin "2") (pinfunction "2_2") (pintype "passive"))
    )
    (net (code "59") (name "Net-(A35-Pad1)") (class "Default")
      (node (ref "A35") (pin "1") (pinfunction "1_1") (pintype "passive"))
      (node (ref "A35") (pin "2") (pinfunction "2_2") (pintype "passive"))
      (node (ref "IC11") (pin "3") (pinfunction "3_3") (pintype "passive"))
    )
    (net (code "60") (name "Net-(A36-Pad1)") (class "Default")
      (node (ref "A36") (pin "1") (pinfunction "1_1") (pintype "passive"))
      (node (ref "A36") (pin "2") (pinfunction "2_2") (pintype "passive"))
      (node (ref "IC11") (pin "4") (pinfunction "4_4") (pintype "passive"))
    )
    (net (code "61") (name "Net-(A37-Pad1)") (class "Default")
      (node (ref "A37") (pin "1") (pinfunction "1_1") (pintype "passive"))
      (node (ref "A37") (pin "2") (pinfunction "2_2") (pintype "passive"))
      (node (ref "IC11") (pin "5") (pinfunction "5_5") (pintype "passive"))
    )
    (net (code "62") (name "Net-(A38-Pad1)") (class "Default")
      (node (ref "A38") (pin "1") (pinfunction "1_1") (pintype "passive"))
      (node (ref "A38") (pin "2") (pinfunction "2_2") (pintype "passive"))
      (node (ref "IC11") (pin "6") (pinfunction "6_6") (pintype "passive"))
    )
    (net (code "63") (name "Net-(A39-Pad1)") (class "Default")
      (node (ref "A39") (pin "1") (pinfunction "1_1") (pintype "passive"))
      (node (ref "A39") (pin "2") (pinfunction "2_2") (pintype "passive"))
      (node (ref "IC11") (pin "7") (pinfunction "7_7") (pintype "passive"))
    )
    (net (code "64") (name "Net-(A40-Pad1)") (class "Default")
      (node (ref "A40") (pin "1") (pinfunction "1_1") (pintype "passive"))
      (node (ref "A40") (pin "2") (pinfunction "2_2") (pintype "passive"))
      (node (ref "IC11") (pin "8") (pinfunction "8_8") (pintype "passive"))
    )
    (net (code "65") (name "Net-(A41-Pad1)") (class "Default")
      (node (ref "A41") (pin "1") (pinfunction "1_1") (pintype "passive"))
      (node (ref "A41") (pin "2") (pinfunction "2_2") (pintype "passive"))
      (node (ref "IC11") (pin "9") (pinfunction "9_9") (pintype "passive"))
    )
    (net (code "66") (name "Net-(A42-Pad1)") (class "Default")
      (node (ref "A42") (pin "1") (pinfunction "1_1") (pintype "passive"))
      (node (ref "A42") (pin "2") (pinfunction "2_2") (pintype "passive"))
      (node (ref "IC11") (pin "10") (pinfunction "10_10") (pintype "passive"))
    )
    (net (code "67") (name "Net-(A43-Pad1)") (class "Default")
      (node (ref "A43") (pin "1") (pinfunction "1_1") (pintype "passive"))
      (node (ref "A43") (pin "2") (pinfunction "2_2") (pintype "passive"))
      (node (ref "IC11") (pin "11") (pinfunction "11_11") (pintype "passive"))
    )
    (net (code "68") (name "Net-(A44-Pad1)") (class "Default")
      (node (ref "A44") (pin "1") (pinfunction "1_1") (pintype "passive"))
      (node (ref "A44") (pin "2") (pinfunction "2_2") (pintype "passive"))
      (node (ref "IC11") (pin "12") (pinfunction "12_12") (pintype "passive"))
    )
    (net (code "69") (name "Net-(A45-Pad1)") (class "Default")
      (node (ref "A45") (pin "1") (pinfunction "1_1") (pintype "passive"))
      (node (ref "A45") (pin "2") (pinfunction "2_2") (pintype "passive"))
      (node (ref "IC11") (pin "13") (pinfunction "13_13") (pintype "passive"))
    )
    (net (code "70") (name "Net-(A46-Pad1)") (class "Default")
      (node (ref "A46") (pin "1") (pinfunction "1_1") (pintype "passive"))
      (node (ref "A46") (pin "2") (pinfunction "2_2") (pintype "passive"))
      (node (ref "IC11") (pin "14") (pinfunction "14_14") (pintype "passive"))
    )
    (net (code "71") (name "Net-(A47-Pad1)") (class "Default")
      (node (ref "A47") (pin "1") (pinfunction "1_1") (pintype "passive"))
      (node (ref "A47") (pin "2") (pinfunction "2_2") (pintype "passive"))
      (node (ref "IC11") (pin "15") (pinfunction "15_15") (pintype "passive"))
    )
    (net (code "72") (name "Net-(A48-Pad1)") (class "Default")
      (node (ref "A48") (pin "1") (pinfunction "1_1") (pintype "passive"))
      (node (ref "A48") (pin "2") (pinfunction "2_2") (pintype "passive"))
      (node (ref "IC11") (pin "16") (pinfunction "16_16") (pintype "passive"))
    )
    (net (code "73") (name "Net-(A49-Pad1)") (class "Default")
      (node (ref "A49") (pin "1") (pinfunction "1_1") (pintype "passive"))
      (node (ref "A49") (pin "2") (pinfunction "2_2") (pintype "passive"))
      (node (ref "IC12") (pin "1") (pinfunction "1_1") (pintype "passive"))
    )
    (net (code "74") (name "Net-(A50-Pad1)") (class "Default")
      (node (ref "A50") (pin "1") (pinfunction "1_1") (pintype "passive"))
      (node (ref "A50") (pin "2") (pinfunction "2_2") (pintype "passive"))
      (node (ref "IC12") (pin "2") (pinfunction "2_2") (pintype "passive"))
    )
    (net (code "75") (name "Net-(A51-Pad1)") (class "Default")
      (node (ref "A51") (pin "1") (pinfunction "1_1") (pintype "passive"))
      (node (ref "A51") (pin "2") (pinfunction "2_2") (pintype "passive"))
      (node (ref "IC12") (pin "3") (pinfunction "3_3") (pintype "passive"))
    )
    (net (code "76") (name "Net-(A52-Pad1)") (class "Default")
      (node (ref "A52") (pin "1") (pinfunction "1_1") (pintype "passive"))
      (node (ref "A52") (pin "2") (pinfunction "2_2") (pintype "passive"))
      (node (ref "IC12") (pin "4") (pinfunction "4_4") (pintype "passive"))
    )
    (net (code "77") (name "Net-(A53-Pad1)") (class "Default")
      (node (ref "A53") (pin "1") (pinfunction "1_1") (pintype "passive"))
      (node (ref "A53") (pin "2") (pinfunction "2_2") (pintype "passive"))
      (node (ref "IC12") (pin "5") (pinfunction "5_5") (pintype "passive"))
    )
    (net (code "78") (name "Net-(A54-Pad1)") (class "Default")
      (node (ref "A54") (pin "1") (pinfunction "1_1") (pintype "passive"))
      (node (ref "A54") (pin "2") (pinfunction "2_2") (pintype "passive"))
      (node (ref "IC12") (pin "6") (pinfunction "6_6") (pintype "passive"))
    )
    (net (code "79") (name "Net-(A55-Pad1)") (class "Default")
      (node (ref "A55") (pin "1") (pinfunction "1_1") (pintype "passive"))
      (node (ref "A55") (pin "2") (pinfunction "2_2") (pintype "passive"))
      (node (ref "IC12") (pin "7") (pinfunction "7_7") (pintype "passive"))
    )
    (net (code "80") (name "Net-(A56-Pad1)") (class "Default")
      (node (ref "A56") (pin "1") (pinfunction "1_1") (pintype "passive"))
      (node (ref "A56") (pin "2") (pinfunction "2_2") (pintype "passive"))
      (node (ref "IC12") (pin "8") (pinfunction "8_8") (pintype "passive"))
    )
    (net (code "81") (name "Net-(A57-Pad1)") (class "Default")
      (node (ref "A57") (pin "1") (pinfunction "1_1") (pintype "passive"))
      (node (ref "A57") (pin "2") (pinfunction "2_2") (pintype "passive"))
      (node (ref "IC12") (pin "9") (pinfunction "9_9") (pintype "passive"))
    )
    (net (code "82") (name "Net-(A58-Pad1)") (class "Default")
      (node (ref "A58") (pin "1") (pinfunction "1_1") (pintype "passive"))
      (node (ref "A58") (pin "2") (pinfunction "2_2") (pintype "passive"))
      (node (ref "IC12") (pin "10") (pinfunction "10_10") (pintype "passive"))
    )
    (net (code "83") (name "Net-(A59-Pad1)") (class "Default")
      (node (ref "A59") (pin "1") (pinfunction "1_1") (pintype "passive"))
      (node (ref "A59") (pin "2") (pinfunction "2_2") (pintype "passive"))
      (node (ref "IC12") (pin "11") (pinfunction "11_11") (pintype "passive"))
    )
    (net (code "84") (name "Net-(A60-Pad1)") (class "Default")
      (node (ref "A60") (pin "1") (pinfunction "1_1") (pintype "passive"))
      (node (ref "A60") (pin "2") (pinfunction "2_2") (pintype "passive"))
      (node (ref "IC12") (pin "12") (pinfunction "12_12") (pintype "passive"))
    )
    (net (code "85") (name "Net-(A61-Pad1)") (class "Default")
      (node (ref "A61") (pin "1") (pinfunction "1_1") (pintype "passive"))
      (node (ref "A61") (pin "2") (pinfunction "2_2") (pintype "passive"))
      (node (ref "IC12") (pin "13") (pinfunction "13_13") (pintype "passive"))
    )
    (net (code "86") (name "Net-(A62-Pad1)") (class "Default")
      (node (ref "A62") (pin "1") (pinfunction "1_1") (pintype "passive"))
      (node (ref "A62") (pin "2") (pinfunction "2_2") (pintype "passive"))
      (node (ref "IC12") (pin "14") (pinfunction "14_14") (pintype "passive"))
    )
    (net (code "87") (name "Net-(A63-Pad1)") (class "Default")
      (node (ref "A63") (pin "1") (pinfunction "1_1") (pintype "passive"))
      (node (ref "A63") (pin "2") (pinfunction "2_2") (pintype "passive"))
      (node (ref "IC12") (pin "15") (pinfunction "15_15") (pintype "passive"))
    )
    (net (code "88") (name "Net-(A64-Pad1)") (class "Default")
      (node (ref "A64") (pin "1") (pinfunction "1_1") (pintype "passive"))
      (node (ref "A64") (pin "2") (pinfunction "2_2") (pintype "passive"))
      (node (ref "IC12") (pin "16") (pinfunction "16_16") (pintype "passive"))
    )
    (net (code "89") (name "Net-(A65-Pad1)") (class "Default")
      (node (ref "A65") (pin "1") (pinfunction "1_1") (pintype "passive"))
      (node (ref "A65") (pin "2") (pinfunction "2_2") (pintype "passive"))
      (node (ref "IC13") (pin "1") (pinfunction "1_1") (pintype "passive"))
    )
    (net (code "90") (name "Net-(A66-Pad1)") (class "Default")
      (node (ref "A66") (pin "1") (pinfunction "1_1") (pintype "passive"))
      (node (ref "A66") (pin "2") (pinfunction "2_2") (pintype "passive"))
      (node (ref "IC13") (pin "2") (pinfunction "2_2") (pintype "passive"))
    )
    (net (code "91") (name "Net-(A67-Pad1)") (class "Default")
      (node (ref "A67") (pin "1") (pinfunction "1_1") (pintype "passive"))
      (node (ref "A67") (pin "2") (pinfunction "2_2") (pintype "passive"))
      (node (ref "IC13") (pin "3") (pinfunction "3_3") (pintype "passive"))
    )
    (net (code "92") (name "Net-(A68-Pad1)") (class "Default")
      (node (ref "A68") (pin "1") (pinfunction "1_1") (pintype "passive"))
      (node (ref "A68") (pin "2") (pinfunction "2_2") (pintype "passive"))
      (node (ref "IC13") (pin "4") (pinfunction "4_4") (pintype "passive"))
    )
    (net (code "93") (name "Net-(A69-Pad1)") (class "Default")
      (node (ref "A69") (pin "1") (pinfunction "1_1") (pintype "passive"))
      (node (ref "A69") (pin "2") (pinfunction "2_2") (pintype "passive"))
      (node (ref "IC13") (pin "5") (pinfunction "5_5") (pintype "passive"))
    )
    (net (code "94") (name "Net-(A70-Pad1)") (class "Default")
      (node (ref "A70") (pin "1") (pinfunction "1_1") (pintype "passive"))
      (node (ref "A70") (pin "2") (pinfunction "2_2") (pintype "passive"))
      (node (ref "IC13") (pin "6") (pinfunction "6_6") (pintype "passive"))
    )
    (net (code "95") (name "Net-(A71-Pad1)") (class "Default")
      (node (ref "A71") (pin "1") (pinfunction "1_1") (pintype "passive"))
      (node (ref "A71") (pin "2") (pinfunction "2_2") (pintype "passive"))
      (node (ref "IC13") (pin "7") (pinfunction "7_7") (pintype "passive"))
    )
    (net (code "96") (name "Net-(A72-Pad1)") (class "Default")
      (node (ref "A72") (pin "1") (pinfunction "1_1") (pintype "passive"))
      (node (ref "A72") (pin "2") (pinfunction "2_2") (pintype "passive"))
      (node (ref "IC13") (pin "8") (pinfunction "8_8") (pintype "passive"))
    )
    (net (code "97") (name "Net-(A73-Pad1)") (class "Default")
      (node (ref "A73") (pin "1") (pinfunction "1_1") (pintype "passive"))
      (node (ref "A73") (pin "2") (pinfunction "2_2") (pintype "passive"))
      (node (ref "IC13") (pin "9") (pinfunction "9_9") (pintype "passive"))
    )
    (net (code "98") (name "Net-(A74-Pad1)") (class "Default")
      (node (ref "A74") (pin "1") (pinfunction "1_1") (pintype "passive"))
      (node (ref "A74") (pin "2") (pinfunction "2_2") (pintype "passive"))
      (node (ref "IC13") (pin "10") (pinfunction "10_10") (pintype "passive"))
    )
    (net (code "99") (name "Net-(A75-Pad1)") (class "Default")
      (node (ref "A75") (pin "1") (pinfunction "1_1") (pintype "passive"))
      (node (ref "A75") (pin "2") (pinfunction "2_2") (pintype "passive"))
      (node (ref "IC13") (pin "11") (pinfunction "11_11") (pintype "passive"))
    )
    (net (code "100") (name "Net-(A76-Pad1)") (class "Default")
      (node (ref "A76") (pin "1") (pinfunction "1_1") (pintype "passive"))
      (node (ref "A76") (pin "2") (pinfunction "2_2") (pintype "passive"))
      (node (ref "IC13") (pin "12") (pinfunction "12_12") (pintype "passive"))
    )
    (net (code "101") (name "Net-(A77-Pad1)") (class "Default")
      (node (ref "A77") (pin "1") (pinfunction "1_1") (pintype "passive"))
      (node (ref "A77") (pin "2") (pinfunction "2_2") (pintype "passive"))
      (node (ref "IC13") (pin "13") (pinfunction "13_13") (pintype "passive"))
    )
    (net (code "102") (name "Net-(A78-Pad1)") (class "Default")
      (node (ref "A78") (pin "1") (pinfunction "1_1") (pintype "passive"))
      (node (ref "A78") (pin "2") (pinfunction "2_2") (pintype "passive"))
      (node (ref "IC13") (pin "14") (pinfunction "14_14") (pintype "passive"))
    )
    (net (code "103") (name "Net-(A79-Pad1)") (class "Default")
      (node (ref "A79") (pin "1") (pinfunction "1_1") (pintype "passive"))
      (node (ref "A79") (pin "2") (pinfunction "2_2") (pintype "passive"))
      (node (ref "IC13") (pin "15") (pinfunction "15_15") (pintype "passive"))
    )
    (net (code "104") (name "Net-(A80-Pad1)") (class "Default")
      (node (ref "A80") (pin "1") (pinfunction "1_1") (pintype "passive"))
      (node (ref "A80") (pin "2") (pinfunction "2_2") (pintype "passive"))
      (node (ref "IC13") (pin "16") (pinfunction "16_16") (pintype "passive"))
    )
    (net (code "105") (name "Net-(A81-Pad1)") (class "Default")
      (node (ref "A81") (pin "1") (pinfunction "1_1") (pintype "passive"))
      (node (ref "A81") (pin "2") (pinfunction "2_2") (pintype "passive"))
      (node (ref "IC14") (pin "1") (pinfunction "1_1") (pintype "passive"))
    )
    (net (code "106") (name "Net-(A82-Pad1)") (class "Default")
      (node (ref "A82") (pin "1") (pinfunction "1_1") (pintype "passive"))
      (node (ref "A82") (pin "2") (pinfunction "2_2") (pintype "passive"))
      (node (ref "IC14") (pin "2") (pinfunction "2_2") (pintype "passive"))
    )
    (net (code "107") (name "Net-(A83-Pad1)") (class "Default")
      (node (ref "A83") (pin "1") (pinfunction "1_1") (pintype "passive"))
      (node (ref "A83") (pin "2") (pinfunction "2_2") (pintype "passive"))
      (node (ref "IC14") (pin "3") (pinfunction "3_3") (pintype "passive"))
    )
    (net (code "108") (name "Net-(A84-Pad1)") (class "Default")
      (node (ref "A84") (pin "1") (pinfunction "1_1") (pintype "passive"))
      (node (ref "A84") (pin "2") (pinfunction "2_2") (pintype "passive"))
      (node (ref "IC14") (pin "4") (pinfunction "4_4") (pintype "passive"))
    )
    (net (code "109") (name "Net-(A85-Pad1)") (class "Default")
      (node (ref "A85") (pin "1") (pinfunction "1_1") (pintype "passive"))
      (node (ref "A85") (pin "2") (pinfunction "2_2") (pintype "passive"))
      (node (ref "IC14") (pin "5") (pinfunction "5_5") (pintype "passive"))
    )
    (net (code "110") (name "Net-(A86-Pad1)") (class "Default")
      (node (ref "A86") (pin "1") (pinfunction "1_1") (pintype "passive"))
      (node (ref "A86") (pin "2") (pinfunction "2_2") (pintype "passive"))
      (node (ref "IC14") (pin "6") (pinfunction "6_6") (pintype "passive"))
    )
    (net (code "111") (name "Net-(A87-Pad1)") (class "Default")
      (node (ref "A87") (pin "1") (pinfunction "1_1") (pintype "passive"))
      (node (ref "A87") (pin "2") (pinfunction "2_2") (pintype "passive"))
      (node (ref "IC14") (pin "7") (pinfunction "7_7") (pintype "passive"))
    )
    (net (code "112") (name "Net-(A88-Pad1)") (class "Default")
      (node (ref "A88") (pin "1") (pinfunction "1_1") (pintype "passive"))
      (node (ref "A88") (pin "2") (pinfunction "2_2") (pintype "passive"))
      (node (ref "IC14") (pin "8") (pinfunction "8_8") (pintype "passive"))
    )
    (net (code "113") (name "Net-(A89-Pad1)") (class "Default")
      (node (ref "A89") (pin "1") (pinfunction "1_1") (pintype "passive"))
      (node (ref "A89") (pin "2") (pinfunction "2_2") (pintype "passive"))
      (node (ref "IC14") (pin "9") (pinfunction "9_9") (pintype "passive"))
    )
    (net (code "114") (name "Net-(A90-Pad1)") (class "Default")
      (node (ref "A90") (pin "1") (pinfunction "1_1") (pintype "passive"))
      (node (ref "A90") (pin "2") (pinfunction "2_2") (pintype "passive"))
      (node (ref "IC14") (pin "10") (pinfunction "10_10") (pintype "passive"))
    )
    (net (code "115") (name "Net-(A91-Pad1)") (class "Default")
      (node (ref "A91") (pin "1") (pinfunction "1_1") (pintype "passive"))
      (node (ref "A91") (pin "2") (pinfunction "2_2") (pintype "passive"))
      (node (ref "IC14") (pin "11") (pinfunction "11_11") (pintype "passive"))
    )
    (net (code "116") (name "Net-(A92-Pad1)") (class "Default")
      (node (ref "A92") (pin "1") (pinfunction "1_1") (pintype "passive"))
      (node (ref "A92") (pin "2") (pinfunction "2_2") (pintype "passive"))
      (node (ref "IC14") (pin "12") (pinfunction "12_12") (pintype "passive"))
    )
    (net (code "117") (name "Net-(A93-Pad1)") (class "Default")
      (node (ref "A93") (pin "1") (pinfunction "1_1") (pintype "passive"))
      (node (ref "A93") (pin "2") (pinfunction "2_2") (pintype "passive"))
      (node (ref "IC14") (pin "13") (pinfunction "13_13") (pintype "passive"))
    )
    (net (code "118") (name "Net-(A94-Pad1)") (class "Default")
      (node (ref "A94") (pin "1") (pinfunction "1_1") (pintype "passive"))
      (node (ref "A94") (pin "2") (pinfunction "2_2") (pintype "passive"))
      (node (ref "IC14") (pin "14") (pinfunction "14_14") (pintype "passive"))
    )
    (net (code "119") (name "Net-(A95-Pad1)") (class "Default")
      (node (ref "A95") (pin "1") (pinfunction "1_1") (pintype "passive"))
      (node (ref "A95") (pin "2") (pinfunction "2_2") (pintype "passive"))
      (node (ref "IC14") (pin "15") (pinfunction "15_15") (pintype "passive"))
    )
    (net (code "120") (name "Net-(A96-Pad1)") (class "Default")
      (node (ref "A96") (pin "1") (pinfunction "1_1") (pintype "passive"))
      (node (ref "A96") (pin "2") (pinfunction "2_2") (pintype "passive"))
      (node (ref "IC14") (pin "16") (pinfunction "16_16") (pintype "passive"))
    )
    (net (code "121") (name "Net-(A97-Pad1)") (class "Default")
      (node (ref "A97") (pin "1") (pinfunction "1_1") (pintype "passive"))
      (node (ref "A97") (pin "2") (pinfunction "2_2") (pintype "passive"))
      (node (ref "IC15") (pin "1") (pinfunction "1_1") (pintype "passive"))
    )
    (net (code "122") (name "Net-(A98-Pad1)") (class "Default")
      (node (ref "A98") (pin "1") (pinfunction "1_1") (pintype "passive"))
      (node (ref "A98") (pin "2") (pinfunction "2_2") (pintype "passive"))
      (node (ref "IC15") (pin "2") (pinfunction "2_2") (pintype "passive"))
    )
    (net (code "123") (name "Net-(A99-Pad1)") (class "Default")
      (node (ref "A99") (pin "1") (pinfunction "1_1") (pintype "passive"))
      (node (ref "A99") (pin "2") (pinfunction "2_2") (pintype "passive"))
      (node (ref "IC15") (pin "3") (pinfunction "3_3") (pintype "passive"))
    )
    (net (code "124") (name "Net-(A100-Pad1)") (class "Default")
      (node (ref "A100") (pin "1") (pinfunction "1_1") (pintype "passive"))
      (node (ref "A100") (pin "2") (pinfunction "2_2") (pintype "passive"))
      (node (ref "IC15") (pin "4") (pinfunction "4_4") (pintype "passive"))
    )
    (net (code "125") (name "Net-(A101-Pad1)") (class "Default")
      (node (ref "A101") (pin "1") (pinfunction "1_1") (pintype "passive"))
      (node (ref "A101") (pin "2") (pinfunction "2_2") (pintype "passive"))
      (node (ref "IC15") (pin "5") (pinfunction "5_5") (pintype "passive"))
    )
    (net (code "126") (name "Net-(A102-Pad1)") (class "Default")
      (node (ref "A102") (pin "1") (pinfunction "1_1") (pintype "passive"))
      (node (ref "A102") (pin "2") (pinfunction "2_2") (pintype "passive"))
      (node (ref "IC15") (pin "6") (pinfunction "6_6") (pintype "passive"))
    )
    (net (code "127") (name "Net-(A103-Pad1)") (class "Default")
      (node (ref "A103") (pin "1") (pinfunction "1_1") (pintype "passive"))
      (node (ref "A103") (pin "2") (pinfunction "2_2") (pintype "passive"))
      (node (ref "IC15") (pin "7") (pinfunction "7_7") (pintype "passive"))
    )
    (net (code "128") (name "Net-(A104-Pad1)") (class "Default")
      (node (ref "A104") (pin "1") (pinfunction "1_1") (pintype "passive"))
      (node (ref "A104") (pin "2") (pinfunction "2_2") (pintype "passive"))
      (node (ref "IC15") (pin "8") (pinfunction "8_8") (pintype "passive"))
    )
    (net (code "129") (name "Net-(A105-Pad1)") (class "Default")
      (node (ref "A105") (pin "1") (pinfunction "1_1") (pintype "passive"))
      (node (ref "A105") (pin "2") (pinfunction "2_2") (pintype "passive"))
      (node (ref "IC15") (pin "9") (pinfunction "9_9") (pintype "passive"))
    )
    (net (code "130") (name "Net-(A106-Pad1)") (class "Default")
      (node (ref "A106") (pin "1") (pinfunction "1_1") (pintype "passive"))
      (node (ref "A106") (pin "2") (pinfunction "2_2") (pintype "passive"))
      (node (ref "IC15") (pin "10") (pinfunction "10_10") (pintype "passive"))
    )
    (net (code "131") (name "Net-(A107-Pad1)") (class "Default")
      (node (ref "A107") (pin "1") (pinfunction "1_1") (pintype "passive"))
      (node (ref "A107") (pin "2") (pinfunction "2_2") (pintype "passive"))
      (node (ref "IC15") (pin "11") (pinfunction "11_11") (pintype "passive"))
    )
    (net (code "132") (name "Net-(A108-Pad1)") (class "Default")
      (node (ref "A108") (pin "1") (pinfunction "1_1") (pintype "passive"))
      (node (ref "A108") (pin "2") (pinfunction "2_2") (pintype "passive"))
      (node (ref "IC15") (pin "12") (pinfunction "12_12") (pintype "passive"))
    )
    (net (code "133") (name "Net-(A109-Pad1)") (class "Default")
      (node (ref "A109") (pin "1") (pinfunction "1_1") (pintype "passive"))
      (node (ref "A109") (pin "2") (pinfunction "2_2") (pintype "passive"))
      (node (ref "IC15") (pin "13") (pinfunction "13_13") (pintype "passive"))
    )
    (net (code "134") (name "Net-(A110-Pad1)") (class "Default")
      (node (ref "A110") (pin "1") (pinfunction "1_1") (pintype "passive"))
      (node (ref "A110") (pin "2") (pinfunction "2_2") (pintype "passive"))
      (node (ref "IC15") (pin "14") (pinfunction "14_14") (pintype "passive"))
    )
    (net (code "135") (name "Net-(A111-Pad1)") (class "Default")
      (node (ref "A111") (pin "1") (pinfunction "1_1") (pintype "passive"))
      (node (ref "A111") (pin "2") (pinfunction "2_2") (pintype "passive"))
      (node (ref "IC15") (pin "15") (pinfunction "15_15") (pintype "passive"))
    )
    (net (code "136") (name "Net-(A112-Pad1)") (class "Default")
      (node (ref "A112") (pin "1") (pinfunction "1_1") (pintype "passive"))
      (node (ref "A112") (pin "2") (pinfunction "2_2") (pintype "passive"))
      (node (ref "IC15") (pin "16") (pinfunction "16_16") (pintype "passive"))
    )
    (net (code "137") (name "Net-(A113-Pad1)") (class "Default")
      (node (ref "A113") (pin "1") (pinfunction "1_1") (pintype "passive"))
      (node (ref "A113") (pin "2") (pinfunction "2_2") (pintype "passive"))
      (node (ref "IC16") (pin "1") (pinfunction "1_1") (pintype "passive"))
    )
    (net (code "138") (name "Net-(A114-Pad1)") (class "Default")
      (node (ref "A114") (pin "1") (pinfunction "1_1") (pintype "passive"))
      (node (ref "A114") (pin "2") (pinfunction "2_2") (pintype "passive"))
      (node (ref "IC16") (pin "2") (pinfunction "2_2") (pintype "passive"))
    )
    (net (code "139") (name "Net-(A115-Pad1)") (class "Default")
      (node (ref "A115") (pin "1") (pinfunction "1_1") (pintype "passive"))
      (node (ref "A115") (pin "2") (pinfunction "2_2") (pintype "passive"))
      (node (ref "IC16") (pin "3") (pinfunction "3_3") (pintype "passive"))
    )
    (net (code "140") (name "Net-(A116-Pad1)") (class "Default")
      (node (ref "A116") (pin "1") (pinfunction "1_1") (pintype "passive"))
      (node (ref "A116") (pin "2") (pinfunction "2_2") (pintype "passive"))
      (node (ref "IC16") (pin "4") (pinfunction "4_4") (pintype "passive"))
    )
    (net (code "141") (name "Net-(A117-Pad1)") (class "Default")
      (node (ref "A117") (pin "1") (pinfunction "1_1") (pintype "passive"))
      (node (ref "A117") (pin "2") (pinfunction "2_2") (pintype "passive"))
      (node (ref "IC16") (pin "5") (pinfunction "5_5") (pintype "passive"))
    )
    (net (code "142") (name "Net-(A118-Pad1)") (class "Default")
      (node (ref "A118") (pin "1") (pinfunction "1_1") (pintype "passive"))
      (node (ref "A118") (pin "2") (pinfunction "2_2") (pintype "passive"))
      (node (ref "IC16") (pin "6") (pinfunction "6_6") (pintype "passive"))
    )
    (net (code "143") (name "Net-(A119-Pad1)") (class "Default")
      (node (ref "A119") (pin "1") (pinfunction "1_1") (pintype "passive"))
      (node (ref "A119") (pin "2") (pinfunction "2_2") (pintype "passive"))
      (node (ref "IC16") (pin "7") (pinfunction "7_7") (pintype "passive"))
    )
    (net (code "144") (name "Net-(A120-Pad1)") (class "Default")
      (node (ref "A120") (pin "1") (pinfunction "1_1") (pintype "passive"))
      (node (ref "A120") (pin "2") (pinfunction "2_2") (pintype "passive"))
      (node (ref "IC16") (pin "8") (pinfunction "8_8") (pintype "passive"))
    )
    (net (code "145") (name "Net-(A121-Pad1)") (class "Default")
      (node (ref "A121") (pin "1") (pinfunction "1_1") (pintype "passive"))
      (node (ref "A121") (pin "2") (pinfunction "2_2") (pintype "passive"))
      (node (ref "IC16") (pin "9") (pinfunction "9_9") (pintype "passive"))
    )
    (net (code "146") (name "Net-(A122-Pad1)") (class "Default")
      (node (ref "A122") (pin "1") (pinfunction "1_1") (pintype "passive"))
      (node (ref "A122") (pin "2") (pinfunction "2_2") (pintype "passive"))
      (node (ref "IC16") (pin "10") (pinfunction "10_10") (pintype "passive"))
    )
    (net (code "147") (name "Net-(A123-Pad1)") (class "Default")
      (node (ref "A123") (pin "1") (pinfunction "1_1") (pintype "passive"))
      (node (ref "A123") (pin "2") (pinfunction "2_2") (pintype "passive"))
      (node (ref "IC16") (pin "11") (pinfunction "11_11") (pintype "passive"))
    )
    (net (code "148") (name "Net-(A124-Pad1)") (class "Default")
      (node (ref "A124") (pin "1") (pinfunction "1_1") (pintype "passive"))
      (node (ref "A124") (pin "2") (pinfunction "2_2") (pintype "passive"))
      (node (ref "IC16") (pin "12") (pinfunction "12_12") (pintype "passive"))
    )
    (net (code "149") (name "Net-(A125-Pad1)") (class "Default")
      (node (ref "A125") (pin "1") (pinfunction "1_1") (pintype "passive"))
      (node (ref "A125") (pin "2") (pinfunction "2_2") (pintype "passive"))
      (node (ref "IC16") (pin "13") (pinfunction "13_13") (pintype "passive"))
    )
    (net (code "150") (name "Net-(A126-Pad1)") (class "Default")
      (node (ref "A126") (pin "1") (pinfunction "1_1") (pintype "passive"))
      (node (ref "A126") (pin "2") (pinfunction "2_2") (pintype "passive"))
      (node (ref "IC16") (pin "14") (pinfunction "14_14") (pintype "passive"))
    )
    (net (code "151") (name "Net-(A127-Pad1)") (class "Default")
      (node (ref "A127") (pin "1") (pinfunction "1_1") (pintype "passive"))
      (node (ref "A127") (pin "2") (pinfunction "2_2") (pintype "passive"))
      (node (ref "IC16") (pin "15") (pinfunction "15_15") (pintype "passive"))
    )
    (net (code "152") (name "Net-(A128-Pad1)") (class "Default")
      (node (ref "A128") (pin "1") (pinfunction "1_1") (pintype "passive"))
      (node (ref "A128") (pin "2") (pinfunction "2_2") (pintype "passive"))
      (node (ref "IC16") (pin "16") (pinfunction "16_16") (pintype "passive"))
    )
    (net (code "153") (name "Net-(A129-Pad1)") (class "Default")
      (node (ref "A129") (pin "1") (pinfunction "1_1") (pintype "passive"))
      (node (ref "A129") (pin "2") (pinfunction "2_2") (pintype "passive"))
      (node (ref "IC17") (pin "1") (pinfunction "1_1") (pintype "passive"))
    )
    (net (code "154") (name "Net-(A130-Pad1)") (class "Default")
      (node (ref "A130") (pin "1") (pinfunction "1_1") (pintype "passive"))
      (node (ref "A130") (pin "2") (pinfunction "2_2") (pintype "passive"))
      (node (ref "IC17") (pin "2") (pinfunction "2_2") (pintype "passive"))
    )
    (net (code "155") (name "Net-(A131-Pad1)") (class "Default")
      (node (ref "A131") (pin "1") (pinfunction "1_1") (pintype "passive"))
      (node (ref "A131") (pin "2") (pinfunction "2_2") (pintype "passive"))
      (node (ref "IC17") (pin "3") (pinfunction "3_3") (pintype "passive"))
    )
    (net (code "156") (name "Net-(A132-Pad1)") (class "Default")
      (node (ref "A132") (pin "1") (pinfunction "1_1") (pintype "passive"))
      (node (ref "A132") (pin "2") (pinfunction "2_2") (pintype "passive"))
      (node (ref "IC17") (pin "4") (pinfunction "4_4") (pintype "passive"))
    )
    (net (code "157") (name "Net-(A133-Pad1)") (class "Default")
      (node (ref "A133") (pin "1") (pinfunction "1_1") (pintype "passive"))
      (node (ref "A133") (pin "2") (pinfunction "2_2") (pintype "passive"))
      (node (ref "IC17") (pin "5") (pinfunction "5_5") (pintype "passive"))
    )
    (net (code "158") (name "Net-(A134-Pad1)") (class "Default")
      (node (ref "A134") (pin "1") (pinfunction "1_1") (pintype "passive"))
      (node (ref "A134") (pin "2") (pinfunction "2_2") (pintype "passive"))
      (node (ref "IC17") (pin "6") (pinfunction "6_6") (pintype "passive"))
    )
    (net (code "159") (name "Net-(A135-Pad1)") (class "Default")
      (node (ref "A135") (pin "1") (pinfunction "1_1") (pintype "passive"))
      (node (ref "A135") (pin "2") (pinfunction "2_2") (pintype "passive"))
      (node (ref "IC17") (pin "7") (pinfunction "7_7") (pintype "passive"))
    )
    (net (code "160") (name "Net-(A136-Pad1)") (class "Default")
      (node (ref "A136") (pin "1") (pinfunction "1_1") (pintype "passive"))
      (node (ref "A136") (pin "2") (pinfunction "2_2") (pintype "passive"))
      (node (ref "IC17") (pin "8") (pinfunction "8_8") (pintype "passive"))
    )
    (net (code "161") (name "Net-(A137-Pad1)") (class "Default")
      (node (ref "A137") (pin "1") (pinfunction "1_1") (pintype "passive"))
      (node (ref "A137") (pin "2") (pinfunction "2_2") (pintype "passive"))
      (node (ref "IC17") (pin "9") (pinfunction "9_9") (pintype "passive"))
    )
    (net (code "162") (name "Net-(A138-Pad1)") (class "Default")
      (node (ref "A138") (pin "1") (pinfunction "1_1") (pintype "passive"))
      (node (ref "A138") (pin "2") (pinfunction "2_2") (pintype "passive"))
      (node (ref "IC17") (pin "10") (pinfunction "10_10") (pintype "passive"))
    )
    (net (code "163") (name "Net-(A139-Pad1)") (class "Default")
      (node (ref "A139") (pin "1") (pinfunction "1_1") (pintype "passive"))
      (node (ref "A139") (pin "2") (pinfunction "2_2") (pintype "passive"))
      (node (ref "IC17") (pin "11") (pinfunction "11_11") (pintype "passive"))
    )
    (net (code "164") (name "Net-(A140-Pad1)") (class "Default")
      (node (ref "A140") (pin "1") (pinfunction "1_1") (pintype "passive"))
      (node (ref "A140") (pin "2") (pinfunction "2_2") (pintype "passive"))
      (node (ref "IC17") (pin "12") (pinfunction "12_12") (pintype "passive"))
    )
    (net (code "165") (name "Net-(A141-Pad1)") (class "Default")
      (node (ref "A141") (pin "1") (pinfunction "1_1") (pintype "passive"))
      (node (ref "A141") (pin "2") (pinfunction "2_2") (pintype "passive"))
      (node (ref "IC17") (pin "13") (pinfunction "13_13") (pintype "passive"))
    )
    (net (code "166") (name "Net-(A142-Pad1)") (class "Default")
      (node (ref "A142") (pin "1") (pinfunction "1_1") (pintype "passive"))
      (node (ref "A142") (pin "2") (pinfunction "2_2") (pintype "passive"))
      (node (ref "IC17") (pin "14") (pinfunction "14_14") (pintype "passive"))
    )
    (net (code "167") (name "Net-(A143-Pad1)") (class "Default")
      (node (ref "A143") (pin "1") (pinfunction "1_1") (pintype "passive"))
      (node (ref "A143") (pin "2") (pinfunction "2_2") (pintype "passive"))
      (node (ref "IC17") (pin "15") (pinfunction "15_15") (pintype "passive"))
    )
    (net (code "168") (name "Net-(A144-Pad1)") (class "Default")
      (node (ref "A144") (pin "1") (pinfunction "1_1") (pintype "passive"))
      (node (ref "A144") (pin "2") (pinfunction "2_2") (pintype "passive"))
      (node (ref "IC17") (pin "16") (pinfunction "16_16") (pintype "passive"))
    )
    (net (code "169") (name "Net-(A145-Pad1)") (class "Default")
      (node (ref "A145") (pin "1") (pinfunction "1_1") (pintype "passive"))
      (node (ref "A145") (pin "2") (pinfunction "2_2") (pintype "passive"))
      (node (ref "IC18") (pin "1") (pinfunction "1_1") (pintype "passive"))
    )
    (net (code "170") (name "Net-(A146-Pad1)") (class "Default")
      (node (ref "A146") (pin "1") (pinfunction "1_1") (pintype "passive"))
      (node (ref "A146") (pin "2") (pinfunction "2_2") (pintype "passive"))
      (node (ref "IC18") (pin "2") (pinfunction "2_2") (pintype "passive"))
    )
    (net (code "171") (name "Net-(A147-Pad1)") (class "Default")
      (node (ref "A147") (pin "1") (pinfunction "1_1") (pintype "passive"))
      (node (ref "A147") (pin "2") (pinfunction "2_2") (pintype "passive"))
      (node (ref "IC18") (pin "3") (pinfunction "3_3") (pintype "passive"))
    )
    (net (code "172") (name "Net-(A148-Pad1)") (class "Default")
      (node (ref "A148") (pin "1") (pinfunction "1_1") (pintype "passive"))
      (node (ref "A148") (pin "2") (pinfunction "2_2") (pintype "passive"))
      (node (ref "IC18") (pin "4") (pinfunction "4_4") (pintype "passive"))
    )
    (net (code "173") (name "Net-(A149-Pad1)") (class "Default")
      (node (ref "A149") (pin "1") (pinfunction "1_1") (pintype "passive"))
      (node (ref "A149") (pin "2") (pinfunction "2_2") (pintype "passive"))
      (node (ref "IC18") (pin "5") (pinfunction "5_5") (pintype "passive"))
    )
    (net (code "174") (name "Net-(A150-Pad1)") (class "Default")
      (node (ref "A150") (pin "1") (pinfunction "1_1") (pintype "passive"))
      (node (ref "A150") (pin "2") (pinfunction "2_2") (pintype "passive"))
      (node (ref "IC18") (pin "6") (pinfunction "6_6") (pintype "passive"))
    )
    (net (code "175") (name "Net-(A151-Pad1)") (class "Default")
      (node (ref "A151") (pin "1") (pinfunction "1_1") (pintype "passive"))
      (node (ref "A151") (pin "2") (pinfunction "2_2") (pintype "passive"))
      (node (ref "IC18") (pin "7") (pinfunction "7_7") (pintype "passive"))
    )
    (net (code "176") (name "Net-(A152-Pad1)") (class "Default")
      (node (ref "A152") (pin "1") (pinfunction "1_1") (pintype "passive"))
      (node (ref "A152") (pin "2") (pinfunction "2_2") (pintype "passive"))
      (node (ref "IC18") (pin "8") (pinfunction "8_8") (pintype "passive"))
    )
    (net (code "177") (name "Net-(A153-Pad1)") (class "Default")
      (node (ref "A153") (pin "1") (pinfunction "1_1") (pintype "passive"))
      (node (ref "A153") (pin "2") (pinfunction "2_2") (pintype "passive"))
      (node (ref "IC18") (pin "9") (pinfunction "9_9") (pintype "passive"))
    )
    (net (code "178") (name "Net-(A154-Pad1)") (class "Default")
      (node (ref "A154") (pin "1") (pinfunction "1_1") (pintype "passive"))
      (node (ref "A154") (pin "2") (pinfunction "2_2") (pintype "passive"))
      (node (ref "IC18") (pin "10") (pinfunction "10_10") (pintype "passive"))
    )
    (net (code "179") (name "Net-(A155-Pad1)") (class "Default")
      (node (ref "A155") (pin "1") (pinfunction "1_1") (pintype "passive"))
      (node (ref "A155") (pin "2") (pinfunction "2_2") (pintype "passive"))
      (node (ref "IC18") (pin "11") (pinfunction "11_11") (pintype "passive"))
    )
    (net (code "180") (name "Net-(A156-Pad1)") (class "Default")
      (node (ref "A156") (pin "1") (pinfunction "1_1") (pintype "passive"))
      (node (ref "A156") (pin "2") (pinfunction "2_2") (pintype "passive"))
      (node (ref "IC18") (pin "12") (pinfunction "12_12") (pintype "passive"))
    )
    (net (code "181") (name "Net-(A157-Pad1)") (class "Default")
      (node (ref "A157") (pin "1") (pinfunction "1_1") (pintype "passive"))
      (node (ref "A157") (pin "2") (pinfunction "2_2") (pintype "passive"))
      (node (ref "IC18") (pin "13") (pinfunction "13_13") (pintype "passive"))
    )
    (net (code "182") (name "Net-(A158-Pad1)") (class "Default")
      (node (ref "A158") (pin "1") (pinfunction "1_1") (pintype "passive"))
      (node (ref "A158") (pin "2") (pinfunction "2_2") (pintype "passive"))
      (node (ref "IC18") (pin "14") (pinfunction "14_14") (pintype "passive"))
    )
    (net (code "183") (name "Net-(A159-Pad1)") (class "Default")
      (node (ref "A159") (pin "1") (pinfunction "1_1") (pintype "passive"))
      (node (ref "A159") (pin "2") (pinfunction "2_2") (pintype "passive"))
      (node (ref "IC18") (pin "15") (pinfunction "15_15") (pintype "passive"))
    )
    (net (code "184") (name "Net-(A160-Pad1)") (class "Default")
      (node (ref "A160") (pin "1") (pinfunction "1_1") (pintype "passive"))
      (node (ref "A160") (pin "2") (pinfunction "2_2") (pintype "passive"))
      (node (ref "IC18") (pin "16") (pinfunction "16_16") (pintype "passive"))
    )
    (net (code "185") (name "Net-(A161-Pad1)") (class "Default")
      (node (ref "A161") (pin "1") (pinfunction "1_1") (pintype "passive"))
      (node (ref "A161") (pin "2") (pinfunction "2_2") (pintype "passive"))
      (node (ref "IC19") (pin "1") (pinfunction "1_1") (pintype "passive"))
    )
    (net (code "186") (name "Net-(A162-Pad1)") (class "Default")
      (node (ref "A162") (pin "1") (pinfunction "1_1") (pintype "passive"))
      (node (ref "A162") (pin "2") (pinfunction "2_2") (pintype "passive"))
      (node (ref "IC19") (pin "2") (pinfunction "2_2") (pintype "passive"))
    )
    (net (code "187") (name "Net-(A163-Pad1)") (class "Default")
      (node (ref "A163") (pin "1") (pinfunction "1_1") (pintype "passive"))
      (node (ref "A163") (pin "2") (pinfunction "2_2") (pintype "passive"))
      (node (ref "IC19") (pin "3") (pinfunction "3_3") (pintype "passive"))
    )
    (net (code "188") (name "Net-(A164-Pad1)") (class "Default")
      (node (ref "A164") (pin "1") (pinfunction "1_1") (pintype "passive"))
      (node (ref "A164") (pin "2") (pinfunction "2_2") (pintype "passive"))
      (node (ref "IC19") (pin "4") (pinfunction "4_4") (pintype "passive"))
    )
    (net (code "189") (name "Net-(A165-Pad1)") (class "Default")
      (node (ref "A165") (pin "1") (pinfunction "1_1") (pintype "passive"))
      (node (ref "A165") (pin "2") (pinfunction "2_2") (pintype "passive"))
      (node (ref "IC19") (pin "5") (pinfunction "5_5") (pintype "passive"))
    )
    (net (code "190") (name "Net-(A166-Pad1)") (class "Default")
      (node (ref "A166") (pin "1") (pinfunction "1_1") (pintype "passive"))
      (node (ref "A166") (pin "2") (pinfunction "2_2") (pintype "passive"))
      (node (ref "IC19") (pin "6") (pinfunction "6_6") (pintype "passive"))
    )
    (net (code "191") (name "Net-(A167-Pad1)") (class "Default")
      (node (ref "A167") (pin "1") (pinfunction "1_1") (pintype "passive"))
      (node (ref "A167") (pin "2") (pinfunction "2_2") (pintype "passive"))
      (node (ref "IC19") (pin "7") (pinfunction "7_7") (pintype "passive"))
    )
    (net (code "192") (name "Net-(A168-Pad1)") (class "Default")
      (node (ref "A168") (pin "1") (pinfunction "1_1") (pintype "passive"))
      (node (ref "A168") (pin "2") (pinfunction "2_2") (pintype "passive"))
      (node (ref "IC19") (pin "8") (pinfunction "8_8") (pintype "passive"))
    )
    (net (code "193") (name "Net-(A169-Pad1)") (class "Default")
      (node (ref "A169") (pin "1") (pinfunction "1_1") (pintype "passive"))
      (node (ref "A169") (pin "2") (pinfunction "2_2") (pintype "passive"))
      (node (ref "IC19") (pin "9") (pinfunction "9_9") (pintype "passive"))
    )
    (net (code "194") (name "Net-(A170-Pad1)") (class "Default")
      (node (ref "A170") (pin "1") (pinfunction "1_1") (pintype "passive"))
      (node (ref "A170") (pin "2") (pinfunction "2_2") (pintype "passive"))
      (node (ref "IC19") (pin "10") (pinfunction "10_10") (pintype "passive"))
    )
    (net (code "195") (name "Net-(A171-Pad1)") (class "Default")
      (node (ref "A171") (pin "1") (pinfunction "1_1") (pintype "passive"))
      (node (ref "A171") (pin "2") (pinfunction "2_2") (pintype "passive"))
      (node (ref "IC19") (pin "11") (pinfunction "11_11") (pintype "passive"))
    )
    (net (code "196") (name "Net-(A172-Pad1)") (class "Default")
      (node (ref "A172") (pin "1") (pinfunction "1_1") (pintype "passive"))
      (node (ref "A172") (pin "2") (pinfunction "2_2") (pintype "passive"))
      (node (ref "IC19") (pin "12") (pinfunction "12_12") (pintype "passive"))
    )
    (net (code "197") (name "Net-(A173-Pad1)") (class "Default")
      (node (ref "A173") (pin "1") (pinfunction "1_1") (pintype "passive"))
      (node (ref "A173") (pin "2") (pinfunction "2_2") (pintype "passive"))
      (node (ref "IC19") (pin "13") (pinfunction "13_13") (pintype "passive"))
    )
    (net (code "198") (name "Net-(A174-Pad1)") (class "Default")
      (node (ref "A174") (pin "1") (pinfunction "1_1") (pintype "passive"))
      (node (ref "A174") (pin "2") (pinfunction "2_2") (pintype "passive"))
      (node (ref "IC19") (pin "14") (pinfunction "14_14") (pintype "passive"))
    )
    (net (code "199") (name "Net-(A175-Pad1)") (class "Default")
      (node (ref "A175") (pin "1") (pinfunction "1_1") (pintype "passive"))
      (node (ref "A175") (pin "2") (pinfunction "2_2") (pintype "passive"))
      (node (ref "IC19") (pin "15") (pinfunction "15_15") (pintype "passive"))
    )
    (net (code "200") (name "Net-(A176-Pad1)") (class "Default")
      (node (ref "A176") (pin "1") (pinfunction "1_1") (pintype "passive"))
      (node (ref "A176") (pin "2") (pinfunction "2_2") (pintype "passive"))
      (node (ref "IC19") (pin "16") (pinfunction "16_16") (pintype "passive"))
    )
    (net (code "201") (name "Net-(A177-Pad1)") (class "Default")
      (node (ref "A177") (pin "1") (pinfunction "1_1") (pintype "passive"))
      (node (ref "A177") (pin "2") (pinfunction "2_2") (pintype "passive"))
      (node (ref "IC20") (pin "1") (pinfunction "1_1") (pintype "passive"))
    )
    (net (code "202") (name "Net-(A178-Pad1)") (class "Default")
      (node (ref "A178") (pin "1") (pinfunction "1_1") (pintype "passive"))
      (node (ref "A178") (pin "2") (pinfunction "2_2") (pintype "passive"))
      (node (ref "IC20") (pin "2") (pinfunction "2_2") (pintype "passive"))
    )
    (net (code "203") (name "Net-(A179-Pad1)") (class "Default")
      (node (ref "A179") (pin "1") (pinfunction "1_1") (pintype "passive"))
      (node (ref "A179") (pin "2") (pinfunction "2_2") (pintype "passive"))
      (node (ref "IC20") (pin "3") (pinfunction "3_3") (pintype "passive"))
    )
    (net (code "204") (name "Net-(A180-Pad1)") (class "Default")
      (node (ref "A180") (pin "1") (pinfunction "1_1") (pintype "passive"))
      (node (ref "A180") (pin "2") (pinfunction "2_2") (pintype "passive"))
      (node (ref "IC20") (pin "4") (pinfunction "4_4") (pintype "passive"))
    )
    (net (code "205") (name "Net-(A181-Pad1)") (class "Default")
      (node (ref "A181") (pin "1") (pinfunction "1_1") (pintype "passive"))
      (node (ref "A181") (pin "2") (pinfunction "2_2") (pintype "passive"))
      (node (ref "IC20") (pin "5") (pinfunction "5_5") (pintype "passive"))
    )
    (net (code "206") (name "Net-(A182-Pad1)") (class "Default")
      (node (ref "A182") (pin "1") (pinfunction "1_1") (pintype "passive"))
      (node (ref "A182") (pin "2") (pinfunction "2_2") (pintype "passive"))
      (node (ref "IC20") (pin "6") (pinfunction "6_6") (pintype "passive"))
    )
    (net (code "207") (name "Net-(A183-Pad1)") (class "Default")
      (node (ref "A183") (pin "1") (pinfunction "1_1") (pintype "passive"))
      (node (ref "A183") (pin "2") (pinfunction "2_2") (pintype "passive"))
      (node (ref "IC20") (pin "7") (pinfunction "7_7") (pintype "passive"))
    )
    (net (code "208") (name "Net-(A184-Pad1)") (class "Default")
      (node (ref "A184") (pin "1") (pinfunction "1_1") (pintype "passive"))
      (node (ref "A184") (pin "2") (pinfunction "2_2") (pintype "passive"))
      (node (ref "IC20") (pin "8") (pinfunction "8_8") (pintype "passive"))
    )
    (net (code "209") (name "Net-(A185-Pad1)") (class "Default")
      (node (ref "A185") (pin "1") (pinfunction "1_1") (pintype "passive"))
      (node (ref "A185") (pin "2") (pinfunction "2_2") (pintype "passive"))
      (node (ref "IC20") (pin "9") (pinfunction "9_9") (pintype "passive"))
    )
    (net (code "210") (name "Net-(A186-Pad1)") (class "Default")
      (node (ref "A186") (pin "1") (pinfunction "1_1") (pintype "passive"))
      (node (ref "A186") (pin "2") (pinfunction "2_2") (pintype "passive"))
      (node (ref "IC20") (pin "10") (pinfunction "10_10") (pintype "passive"))
    )
    (net (code "211") (name "Net-(A187-Pad1)") (class "Default")
      (node (ref "A187") (pin "1") (pinfunction "1_1") (pintype "passive"))
      (node (ref "A187") (pin "2") (pinfunction "2_2") (pintype "passive"))
      (node (ref "IC20") (pin "11") (pinfunction "11_11") (pintype "passive"))
    )
    (net (code "212") (name "Net-(A188-Pad1)") (class "Default")
      (node (ref "A188") (pin "1") (pinfunction "1_1") (pintype "passive"))
      (node (ref "A188") (pin "2") (pinfunction "2_2") (pintype "passive"))
      (node (ref "IC20") (pin "12") (pinfunction "12_12") (pintype "passive"))
    )
    (net (code "213") (name "Net-(A189-Pad1)") (class "Default")
      (node (ref "A189") (pin "1") (pinfunction "1_1") (pintype "passive"))
      (node (ref "A189") (pin "2") (pinfunction "2_2") (pintype "passive"))
      (node (ref "IC20") (pin "13") (pinfunction "13_13") (pintype "passive"))
    )
    (net (code "214") (name "Net-(A190-Pad1)") (class "Default")
      (node (ref "A190") (pin "1") (pinfunction "1_1") (pintype "passive"))
      (node (ref "A190") (pin "2") (pinfunction "2_2") (pintype "passive"))
      (node (ref "IC20") (pin "14") (pinfunction "14_14") (pintype "passive"))
    )
    (net (code "215") (name "Net-(A191-Pad1)") (class "Default")
      (node (ref "A191") (pin "1") (pinfunction "1_1") (pintype "passive"))
      (node (ref "A191") (pin "2") (pinfunction "2_2") (pintype "passive"))
      (node (ref "IC20") (pin "15") (pinfunction "15_15") (pintype "passive"))
    )
    (net (code "216") (name "Net-(A192-Pad1)") (class "Default")
      (node (ref "A192") (pin "1") (pinfunction "1_1") (pintype "passive"))
      (node (ref "A192") (pin "2") (pinfunction "2_2") (pintype "passive"))
      (node (ref "IC20") (pin "16") (pinfunction "16_16") (pintype "passive"))
    )
    (net (code "217") (name "Net-(A193-Pad1)") (class "Default")
      (node (ref "A193") (pin "1") (pinfunction "1_1") (pintype "passive"))
      (node (ref "A193") (pin "2") (pinfunction "2_2") (pintype "passive"))
      (node (ref "IC21") (pin "1") (pinfunction "1_1") (pintype "passive"))
    )
    (net (code "218") (name "Net-(A194-Pad1)") (class "Default")
      (node (ref "A194") (pin "1") (pinfunction "1_1") (pintype "passive"))
      (node (ref "A194") (pin "2") (pinfunction "2_2") (pintype "passive"))
      (node (ref "IC21") (pin "2") (pinfunction "2_2") (pintype "passive"))
    )
    (net (code "219") (name "Net-(A195-Pad1)") (class "Default")
      (node (ref "A195") (pin "1") (pinfunction "1_1") (pintype "passive"))
      (node (ref "A195") (pin "2") (pinfunction "2_2") (pintype "passive"))
      (node (ref "IC21") (pin "3") (pinfunction "3_3") (pintype "passive"))
    )
    (net (code "220") (name "Net-(A196-Pad1)") (class "Default")
      (node (ref "A196") (pin "1") (pinfunction "1_1") (pintype "passive"))
      (node (ref "A196") (pin "2") (pinfunction "2_2") (pintype "passive"))
      (node (ref "IC21") (pin "4") (pinfunction "4_4") (pintype "passive"))
    )
    (net (code "221") (name "Net-(A197-Pad1)") (class "Default")
      (node (ref "A197") (pin "1") (pinfunction "1_1") (pintype "passive"))
      (node (ref "A197") (pin "2") (pinfunction "2_2") (pintype "passive"))
      (node (ref "IC21") (pin "5") (pinfunction "5_5") (pintype "passive"))
    )
    (net (code "222") (name "Net-(A198-Pad1)") (class "Default")
      (node (ref "A198") (pin "1") (pinfunction "1_1") (pintype "passive"))
      (node (ref "A198") (pin "2") (pinfunction "2_2") (pintype "passive"))
      (node (ref "IC21") (pin "6") (pinfunction "6_6") (pintype "passive"))
    )
    (net (code "223") (name "Net-(A199-Pad1)") (class "Default")
      (node (ref "A199") (pin "1") (pinfunction "1_1") (pintype "passive"))
      (node (ref "A199") (pin "2") (pinfunction "2_2") (pintype "passive"))
      (node (ref "IC21") (pin "7") (pinfunction "7_7") (pintype "passive"))
    )
    (net (code "224") (name "Net-(A200-Pad1)") (class "Default")
      (node (ref "A200") (pin "1") (pinfunction "1_1") (pintype "passive"))
      (node (ref "A200") (pin "2") (pinfunction "2_2") (pintype "passive"))
      (node (ref "IC21") (pin "8") (pinfunction "8_8") (pintype "passive"))
    )
    (net (code "225") (name "Net-(A201-Pad1)") (class "Default")
      (node (ref "A201") (pin "1") (pinfunction "1_1") (pintype "passive"))
      (node (ref "A201") (pin "2") (pinfunction "2_2") (pintype "passive"))
      (node (ref "IC21") (pin "9") (pinfunction "9_9") (pintype "passive"))
    )
    (net (code "226") (name "Net-(A202-Pad1)") (class "Default")
      (node (ref "A202") (pin "1") (pinfunction "1_1") (pintype "passive"))
      (node (ref "A202") (pin "2") (pinfunction "2_2") (pintype "passive"))
      (node (ref "IC21") (pin "10") (pinfunction "10_10") (pintype "passive"))
    )
    (net (code "227") (name "Net-(A203-Pad1)") (class "Default")
      (node (ref "A203") (pin "1") (pinfunction "1_1") (pintype "passive"))
      (node (ref "A203") (pin "2") (pinfunction "2_2") (pintype "passive"))
      (node (ref "IC21") (pin "11") (pinfunction "11_11") (pintype "passive"))
    )
    (net (code "228") (name "Net-(A204-Pad1)") (class "Default")
      (node (ref "A204") (pin "1") (pinfunction "1_1") (pintype "passive"))
      (node (ref "A204") (pin "2") (pinfunction "2_2") (pintype "passive"))
      (node (ref "IC21") (pin "12") (pinfunction "12_12") (pintype "passive"))
    )
    (net (code "229") (name "Net-(A205-Pad1)") (class "Default")
      (node (ref "A205") (pin "1") (pinfunction "1_1") (pintype "passive"))
      (node (ref "A205") (pin "2") (pinfunction "2_2") (pintype "passive"))
      (node (ref "IC21") (pin "13") (pinfunction "13_13") (pintype "passive"))
    )
    (net (code "230") (name "Net-(A206-Pad1)") (class "Default")
      (node (ref "A206") (pin "1") (pinfunction "1_1") (pintype "passive"))
      (node (ref "A206") (pin "2") (pinfunction "2_2") (pintype "passive"))
      (node (ref "IC21") (pin "14") (pinfunction "14_14") (pintype "passive"))
    )
    (net (code "231") (name "Net-(A207-Pad1)") (class "Default")
      (node (ref "A207") (pin "1") (pinfunction "1_1") (pintype "passive"))
      (node (ref "A207") (pin "2") (pinfunction "2_2") (pintype "passive"))
      (node (ref "IC21") (pin "15") (pinfunction "15_15") (pintype "passive"))
    )
    (net (code "232") (name "Net-(A208-Pad1)") (class "Default")
      (node (ref "A208") (pin "1") (pinfunction "1_1") (pintype "passive"))
      (node (ref "A208") (pin "2") (pinfunction "2_2") (pintype "passive"))
      (node (ref "IC21") (pin "16") (pinfunction "16_16") (pintype "passive"))
    )
    (net (code "233") (name "Net-(A209-Pad1)") (class "Default")
      (node (ref "A209") (pin "1") (pinfunction "1_1") (pintype "passive"))
      (node (ref "A209") (pin "2") (pinfunction "2_2") (pintype "passive"))
      (node (ref "IC22") (pin "1") (pinfunction "1_1") (pintype "passive"))
    )
    (net (code "234") (name "Net-(A210-Pad1)") (class "Default")
      (node (ref "A210") (pin "1") (pinfunction "1_1") (pintype "passive"))
      (node (ref "A210") (pin "2") (pinfunction "2_2") (pintype "passive"))
      (node (ref "IC22") (pin "2") (pinfunction "2_2") (pintype "passive"))
    )
    (net (code "235") (name "Net-(A211-Pad1)") (class "Default")
      (node (ref "A211") (pin "1") (pinfunction "1_1") (pintype "passive"))
      (node (ref "A211") (pin "2") (pinfunction "2_2") (pintype "passive"))
      (node (ref "IC22") (pin "3") (pinfunction "3_3") (pintype "passive"))
    )
    (net (code "236") (name "Net-(A212-Pad1)") (class "Default")
      (node (ref "A212") (pin "1") (pinfunction "1_1") (pintype "passive"))
      (node (ref "A212") (pin "2") (pinfunction "2_2") (pintype "passive"))
      (node (ref "IC22") (pin "4") (pinfunction "4_4") (pintype "passive"))
    )
    (net (code "237") (name "Net-(A213-Pad1)") (class "Default")
      (node (ref "A213") (pin "1") (pinfunction "1_1") (pintype "passive"))
      (node (ref "A213") (pin "2") (pinfunction "2_2") (pintype "passive"))
      (node (ref "IC22") (pin "5") (pinfunction "5_5") (pintype "passive"))
    )
    (net (code "238") (name "Net-(A214-Pad1)") (class "Default")
      (node (ref "A214") (pin "1") (pinfunction "1_1") (pintype "passive"))
      (node (ref "A214") (pin "2") (pinfunction "2_2") (pintype "passive"))
      (node (ref "IC22") (pin "6") (pinfunction "6_6") (pintype "passive"))
    )
    (net (code "239") (name "Net-(A215-Pad1)") (class "Default")
      (node (ref "A215") (pin "1") (pinfunction "1_1") (pintype "passive"))
      (node (ref "A215") (pin "2") (pinfunction "2_2") (pintype "passive"))
      (node (ref "IC22") (pin "7") (pinfunction "7_7") (pintype "passive"))
    )
    (net (code "240") (name "Net-(A216-Pad1)") (class "Default")
      (node (ref "A216") (pin "1") (pinfunction "1_1") (pintype "passive"))
      (node (ref "A216") (pin "2") (pinfunction "2_2") (pintype "passive"))
      (node (ref "IC22") (pin "8") (pinfunction "8_8") (pintype "passive"))
    )
    (net (code "241") (name "Net-(A217-Pad1)") (class "Default")
      (node (ref "A217") (pin "1") (pinfunction "1_1") (pintype "passive"))
      (node (ref "A217") (pin "2") (pinfunction "2_2") (pintype "passive"))
      (node (ref "IC22") (pin "9") (pinfunction "9_9") (pintype "passive"))
    )
    (net (code "242") (name "Net-(A218-Pad1)") (class "Default")
      (node (ref "A218") (pin "1") (pinfunction "1_1") (pintype "passive"))
      (node (ref "A218") (pin "2") (pinfunction "2_2") (pintype "passive"))
      (node (ref "IC22") (pin "10") (pinfunction "10_10") (pintype "passive"))
    )
    (net (code "243") (name "Net-(A219-Pad1)") (class "Default")
      (node (ref "A219") (pin "1") (pinfunction "1_1") (pintype "passive"))
      (node (ref "A219") (pin "2") (pinfunction "2_2") (pintype "passive"))
      (node (ref "IC22") (pin "11") (pinfunction "11_11") (pintype "passive"))
    )
    (net (code "244") (name "Net-(A220-Pad1)") (class "Default")
      (node (ref "A220") (pin "1") (pinfunction "1_1") (pintype "passive"))
      (node (ref "A220") (pin "2") (pinfunction "2_2") (pintype "passive"))
      (node (ref "IC22") (pin "12") (pinfunction "12_12") (pintype "passive"))
    )
    (net (code "245") (name "Net-(A221-Pad1)") (class "Default")
      (node (ref "A221") (pin "1") (pinfunction "1_1") (pintype "passive"))
      (node (ref "A221") (pin "2") (pinfunction "2_2") (pintype "passive"))
      (node (ref "IC22") (pin "13") (pinfunction "13_13") (pintype "passive"))
    )
    (net (code "246") (name "Net-(A222-Pad1)") (class "Default")
      (node (ref "A222") (pin "1") (pinfunction "1_1") (pintype "passive"))
      (node (ref "A222") (pin "2") (pinfunction "2_2") (pintype "passive"))
      (node (ref "IC22") (pin "14") (pinfunction "14_14") (pintype "passive"))
    )
    (net (code "247") (name "Net-(A223-Pad1)") (class "Default")
      (node (ref "A223") (pin "1") (pinfunction "1_1") (pintype "passive"))
      (node (ref "A223") (pin "2") (pinfunction "2_2") (pintype "passive"))
      (node (ref "IC22") (pin "15") (pinfunction "15_15") (pintype "passive"))
    )
    (net (code "248") (name "Net-(A224-Pad1)") (class "Default")
      (node (ref "A224") (pin "1") (pinfunction "1_1") (pintype "passive"))
      (node (ref "A224") (pin "2") (pinfunction "2_2") (pintype "passive"))
      (node (ref "IC22") (pin "16") (pinfunction "16_16") (pintype "passive"))
    )
    (net (code "249") (name "Net-(A225-Pad1)") (class "Default")
      (node (ref "A225") (pin "1") (pinfunction "1_1") (pintype "passive"))
      (node (ref "A225") (pin "2") (pinfunction "2_2") (pintype "passive"))
      (node (ref "IC23") (pin "1") (pinfunction "1_1") (pintype "passive"))
    )
    (net (code "250") (name "Net-(A226-Pad1)") (class "Default")
      (node (ref "A226") (pin "1") (pinfunction "1_1") (pintype "passive"))
      (node (ref "A226") (pin "2") (pinfunction "2_2") (pintype "passive"))
      (node (ref "IC23") (pin "2") (pinfunction "2_2") (pintype "passive"))
    )
    (net (code "251") (name "Net-(A227-Pad1)") (class "Default")
      (node (ref "A227") (pin "1") (pinfunction "1_1") (pintype "passive"))
      (node (ref "A227") (pin "2") (pinfunction "2_2") (pintype "passive"))
      (node (ref "IC23") (pin "3") (pinfunction "3_3") (pintype "passive"))
    )
    (net (code "252") (name "Net-(A228-Pad1)") (class "Default")
      (node (ref "A228") (pin "1") (pinfunction "1_1") (pintype "passive"))
      (node (ref "A228") (pin "2") (pinfunction "2_2") (pintype "passive"))
      (node (ref "IC23") (pin "4") (pinfunction "4_4") (pintype "passive"))
    )
    (net (code "253") (name "Net-(A229-Pad1)") (class "Default")
      (node (ref "A229") (pin "1") (pinfunction "1_1") (pintype "passive"))
      (node (ref "A229") (pin "2") (pinfunction "2_2") (pintype "passive"))
      (node (ref "IC23") (pin "5") (pinfunction "5_5") (pintype "passive"))
    )
    (net (code "254") (name "Net-(A230-Pad1)") (class "Default")
      (node (ref "A230") (pin "1") (pinfunction "1_1") (pintype "passive"))
      (node (ref "A230") (pin "2") (pinfunction "2_2") (pintype "passive"))
      (node (ref "IC23") (pin "6") (pinfunction "6_6") (pintype "passive"))
    )
    (net (code "255") (name "Net-(A231-Pad1)") (class "Default")
      (node (ref "A231") (pin "1") (pinfunction "1_1") (pintype "passive"))
      (node (ref "A231") (pin "2") (pinfunction "2_2") (pintype "passive"))
      (node (ref "IC23") (pin "7") (pinfunction "7_7") (pintype "passive"))
    )
    (net (code "256") (name "Net-(A232-Pad1)") (class "Default")
      (node (ref "A232") (pin "1") (pinfunction "1_1") (pintype "passive"))
      (node (ref "A232") (pin "2") (pinfunction "2_2") (pintype "passive"))
      (node (ref "IC23") (pin "8") (pinfunction "8_8") (pintype "passive"))
    )
    (net (code "257") (name "Net-(A233-Pad1)") (class "Default")
      (node (ref "A233") (pin "1") (pinfunction "1_1") (pintype "passive"))
      (node (ref "A233") (pin "2") (pinfunction "2_2") (pintype "passive"))
      (node (ref "IC23") (pin "9") (pinfunction "9_9") (pintype "passive"))
    )
    (net (code "258") (name "Net-(A234-Pad1)") (class "Default")
      (node (ref "A234") (pin "1") (pinfunction "1_1") (pintype "passive"))
      (node (ref "A234") (pin "2") (pinfunction "2_2") (pintype "passive"))
      (node (ref "IC23") (pin "10") (pinfunction "10_10") (pintype "passive"))
    )
    (net (code "259") (name "Net-(A235-Pad1)") (class "Default")
      (node (ref "A235") (pin "1") (pinfunction "1_1") (pintype "passive"))
      (node (ref "A235") (pin "2") (pinfunction "2_2") (pintype "passive"))
      (node (ref "IC23") (pin "11") (pinfunction "11_11") (pintype "passive"))
    )
    (net (code "260") (name "Net-(A236-Pad1)") (class "Default")
      (node (ref "A236") (pin "1") (pinfunction "1_1") (pintype "passive"))
      (node (ref "A236") (pin "2") (pinfunction "2_2") (pintype "passive"))
      (node (ref "IC23") (pin "12") (pinfunction "12_12") (pintype "passive"))
    )
    (net (code "261") (name "Net-(A237-Pad1)") (class "Default")
      (node (ref "A237") (pin "1") (pinfunction "1_1") (pintype "passive"))
      (node (ref "A237") (pin "2") (pinfunction "2_2") (pintype "passive"))
      (node (ref "IC23") (pin "13") (pinfunction "13_13") (pintype "passive"))
    )
    (net (code "262") (name "Net-(A238-Pad1)") (class "Default")
      (node (ref "A238") (pin "1") (pinfunction "1_1") (pintype "passive"))
      (node (ref "A238") (pin "2") (pinfunction "2_2") (pintype "passive"))
      (node (ref "IC23") (pin "14") (pinfunction "14_14") (pintype "passive"))
    )
    (net (code "263") (name "Net-(A239-Pad1)") (class "Default")
      (node (ref "A239") (pin "1") (pinfunction "1_1") (pintype "passive"))
      (node (ref "A239") (pin "2") (pinfunction "2_2") (pintype "passive"))
      (node (ref "IC23") (pin "15") (pinfunction "15_15") (pintype "passive"))
    )
    (net (code "264") (name "Net-(A240-Pad1)") (class "Default")
      (node (ref "A240") (pin "1") (pinfunction "1_1") (pintype "passive"))
      (node (ref "A240") (pin "2") (pinfunction "2_2") (pintype "passive"))
      (node (ref "IC23") (pin "16") (pinfunction "16_16") (pintype "passive"))
    )
    (net (code "265") (name "Net-(A241-Pad1)") (class "Default")
      (node (ref "A241") (pin "1") (pinfunction "1_1") (pintype "passive"))
      (node (ref "A241") (pin "2") (pinfunction "2_2") (pintype "passive"))
      (node (ref "IC24") (pin "1") (pinfunction "1_1") (pintype "passive"))
    )
    (net (code "266") (name "Net-(A242-Pad1)") (class "Default")
      (node (ref "A242") (pin "1") (pinfunction "1_1") (pintype "passive"))
      (node (ref "A242") (pin "2") (pinfunction "2_2") (pintype "passive"))
      (node (ref "IC24") (pin "2") (pinfunction "2_2") (pintype "passive"))
    )
    (net (code "267") (name "Net-(A243-Pad1)") (class "Default")
      (node (ref "A243") (pin "1") (pinfunction "1_1") (pintype "passive"))
      (node (ref "A243") (pin "2") (pinfunction "2_2") (pintype "passive"))
      (node (ref "IC24") (pin "3") (pinfunction "3_3") (pintype "passive"))
    )
    (net (code "268") (name "Net-(A244-Pad1)") (class "Default")
      (node (ref "A244") (pin "1") (pinfunction "1_1") (pintype "passive"))
      (node (ref "A244") (pin "2") (pinfunction "2_2") (pintype "passive"))
      (node (ref "IC24") (pin "4") (pinfunction "4_4") (pintype "passive"))
    )
    (net (code "269") (name "Net-(A245-Pad1)") (class "Default")
      (node (ref "A245") (pin "1") (pinfunction "1_1") (pintype "passive"))
      (node (ref "A245") (pin "2") (pinfunction "2_2") (pintype "passive"))
      (node (ref "IC24") (pin "5") (pinfunction "5_5") (pintype "passive"))
    )
    (net (code "270") (name "Net-(A246-Pad1)") (class "Default")
      (node (ref "A246") (pin "1") (pinfunction "1_1") (pintype "passive"))
      (node (ref "A246") (pin "2") (pinfunction "2_2") (pintype "passive"))
      (node (ref "IC24") (pin "6") (pinfunction "6_6") (pintype "passive"))
    )
    (net (code "271") (name "Net-(A247-Pad1)") (class "Default")
      (node (ref "A247") (pin "1") (pinfunction "1_1") (pintype "passive"))
      (node (ref "A247") (pin "2") (pinfunction "2_2") (pintype "passive"))
      (node (ref "IC24") (pin "7") (pinfunction "7_7") (pintype "passive"))
    )
    (net (code "272") (name "Net-(A248-Pad1)") (class "Default")
      (node (ref "A248") (pin "1") (pinfunction "1_1") (pintype "passive"))
      (node (ref "A248") (pin "2") (pinfunction "2_2") (pintype "passive"))
      (node (ref "IC24") (pin "8") (pinfunction "8_8") (pintype "passive"))
    )
    (net (code "273") (name "Net-(A249-Pad1)") (class "Default")
      (node (ref "A249") (pin "1") (pinfunction "1_1") (pintype "passive"))
      (node (ref "A249") (pin "2") (pinfunction "2_2") (pintype "passive"))
      (node (ref "IC24") (pin "9") (pinfunction "9_9") (pintype "passive"))
    )
    (net (code "274") (name "Net-(A250-Pad1)") (class "Default")
      (node (ref "A250") (pin "1") (pinfunction "1_1") (pintype "passive"))
      (node (ref "A250") (pin "2") (pinfunction "2_2") (pintype "passive"))
      (node (ref "IC24") (pin "10") (pinfunction "10_10") (pintype "passive"))
    )
    (net (code "275") (name "Net-(A251-Pad1)") (class "Default")
      (node (ref "A251") (pin "1") (pinfunction "1_1") (pintype "passive"))
      (node (ref "A251") (pin "2") (pinfunction "2_2") (pintype "passive"))
      (node (ref "IC24") (pin "11") (pinfunction "11_11") (pintype "passive"))
    )
    (net (code "276") (name "Net-(A252-Pad1)") (class "Default")
      (node (ref "A252") (pin "1") (pinfunction "1_1") (pintype "passive"))
      (node (ref "A252") (pin "2") (pinfunction "2_2") (pintype "passive"))
      (node (ref "IC24") (pin "12") (pinfunction "12_12") (pintype "passive"))
    )
    (net (code "277") (name "Net-(A253-Pad1)") (class "Default")
      (node (ref "A253") (pin "1") (pinfunction "1_1") (pintype "passive"))
      (node (ref "A253") (pin "2") (pinfunction "2_2") (pintype "passive"))
      (node (ref "IC24") (pin "13") (pinfunction "13_13") (pintype "passive"))
    )
    (net (code "278") (name "Net-(A254-Pad1)") (class "Default")
      (node (ref "A254") (pin "1") (pinfunction "1_1") (pintype "passive"))
      (node (ref "A254") (pin "2") (pinfunction "2_2") (pintype "passive"))
      (node (ref "IC24") (pin "14") (pinfunction "14_14") (pintype "passive"))
    )
    (net (code "279") (name "Net-(A255-Pad1)") (class "Default")
      (node (ref "A255") (pin "1") (pinfunction "1_1") (pintype "passive"))
      (node (ref "A255") (pin "2") (pinfunction "2_2") (pintype "passive"))
      (node (ref "IC24") (pin "15") (pinfunction "15_15") (pintype "passive"))
    )
    (net (code "280") (name "Net-(A256-Pad1)") (class "Default")
      (node (ref "A256") (pin "1") (pinfunction "1_1") (pintype "passive"))
      (node (ref "A256") (pin "2") (pinfunction "2_2") (pintype "passive"))
      (node (ref "IC24") (pin "16") (pinfunction "16_16") (pintype "passive"))
    )
    (net (code "281") (name "Net-(A257-Pad1)") (class "Default")
      (node (ref "A257") (pin "1") (pinfunction "1_1") (pintype "passive"))
      (node (ref "A257") (pin "2") (pinfunction "2_2") (pintype "passive"))
      (node (ref "IC25") (pin "1") (pinfunction "1_1") (pintype "passive"))
    )
    (net (code "282") (name "Net-(A258-Pad1)") (class "Default")
      (node (ref "A258") (pin "1") (pinfunction "1_1") (pintype "passive"))
      (node (ref "A258") (pin "2") (pinfunction "2_2") (pintype "passive"))
      (node (ref "IC25") (pin "2") (pinfunction "2_2") (pintype "passive"))
    )
    (net (code "283") (name "Net-(A259-Pad1)") (class "Default")
      (node (ref "A259") (pin "1") (pinfunction "1_1") (pintype "passive"))
      (node (ref "A259") (pin "2") (pinfunction "2_2") (pintype "passive"))
      (node (ref "IC25") (pin "3") (pinfunction "3_3") (pintype "passive"))
    )
    (net (code "284") (name "Net-(A260-Pad1)") (class "Default")
      (node (ref "A260") (pin "1") (pinfunction "1_1") (pintype "passive"))
      (node (ref "A260") (pin "2") (pinfunction "2_2") (pintype "passive"))
      (node (ref "IC25") (pin "4") (pinfunction "4_4") (pintype "passive"))
    )
    (net (code "285") (name "Net-(A261-Pad1)") (class "Default")
      (node (ref "A261") (pin "1") (pinfunction "1_1") (pintype "passive"))
      (node (ref "A261") (pin "2") (pinfunction "2_2") (pintype "passive"))
      (node (ref "IC25") (pin "5") (pinfunction "5_5") (pintype "passive"))
    )
    (net (code "286") (name "Net-(A262-Pad1)") (class "Default")
      (node (ref "A262") (pin "1") (pinfunction "1_1") (pintype "passive"))
      (node (ref "A262") (pin "2") (pinfunction "2_2") (pintype "passive"))
      (node (ref "IC25") (pin "6") (pinfunction "6_6") (pintype "passive"))
    )
    (net (code "287") (name "Net-(A263-Pad1)") (class "Default")
      (node (ref "A263") (pin "1") (pinfunction "1_1") (pintype "passive"))
      (node (ref "A263") (pin "2") (pinfunction "2_2") (pintype "passive"))
      (node (ref "IC25") (pin "7") (pinfunction "7_7") (pintype "passive"))
    )
    (net (code "288") (name "Net-(A264-Pad1)") (class "Default")
      (node (ref "A264") (pin "1") (pinfunction "1_1") (pintype "passive"))
      (node (ref "A264") (pin "2") (pinfunction "2_2") (pintype "passive"))
      (node (ref "IC25") (pin "8") (pinfunction "8_8") (pintype "passive"))
    )
    (net (code "289") (name "Net-(A265-Pad1)") (class "Default")
      (node (ref "A265") (pin "1") (pinfunction "1_1") (pintype "passive"))
      (node (ref "A265") (pin "2") (pinfunction "2_2") (pintype "passive"))
      (node (ref "IC25") (pin "9") (pinfunction "9_9") (pintype "passive"))
    )
    (net (code "290") (name "Net-(A266-Pad1)") (class "Default")
      (node (ref "A266") (pin "1") (pinfunction "1_1") (pintype "passive"))
      (node (ref "A266") (pin "2") (pinfunction "2_2") (pintype "passive"))
      (node (ref "IC25") (pin "10") (pinfunction "10_10") (pintype "passive"))
    )
    (net (code "291") (name "Net-(A267-Pad1)") (class "Default")
      (node (ref "A267") (pin "1") (pinfunction "1_1") (pintype "passive"))
      (node (ref "A267") (pin "2") (pinfunction "2_2") (pintype "passive"))
      (node (ref "IC25") (pin "11") (pinfunction "11_11") (pintype "passive"))
    )
    (net (code "292") (name "Net-(A268-Pad1)") (class "Default")
      (node (ref "A268") (pin "1") (pinfunction "1_1") (pintype "passive"))
      (node (ref "A268") (pin "2") (pinfunction "2_2") (pintype "passive"))
      (node (ref "IC25") (pin "12") (pinfunction "12_12") (pintype "passive"))
    )
    (net (code "293") (name "Net-(A269-Pad1)") (class "Default")
      (node (ref "A269") (pin "1") (pinfunction "1_1") (pintype "passive"))
      (node (ref "A269") (pin "2") (pinfunction "2_2") (pintype "passive"))
      (node (ref "IC25") (pin "13") (pinfunction "13_13") (pintype "passive"))
    )
    (net (code "294") (name "Net-(A270-Pad1)") (class "Default")
      (node (ref "A270") (pin "1") (pinfunction "1_1") (pintype "passive"))
      (node (ref "A270") (pin "2") (pinfunction "2_2") (pintype "passive"))
      (node (ref "IC25") (pin "14") (pinfunction "14_14") (pintype "passive"))
    )
    (net (code "295") (name "Net-(A271-Pad1)") (class "Default")
      (node (ref "A271") (pin "1") (pinfunction "1_1") (pintype "passive"))
      (node (ref "A271") (pin "2") (pinfunction "2_2") (pintype "passive"))
      (node (ref "IC25") (pin "15") (pinfunction "15_15") (pintype "passive"))
    )
    (net (code "296") (name "Net-(A272-Pad1)") (class "Default")
      (node (ref "A272") (pin "1") (pinfunction "1_1") (pintype "passive"))
      (node (ref "A272") (pin "2") (pinfunction "2_2") (pintype "passive"))
      (node (ref "IC25") (pin "16") (pinfunction "16_16") (pintype "passive"))
    )
    (net (code "297") (name "Net-(A273-Pad1)") (class "Default")
      (node (ref "A273") (pin "1") (pinfunction "1_1") (pintype "passive"))
      (node (ref "A273") (pin "2") (pinfunction "2_2") (pintype "passive"))
      (node (ref "IC26") (pin "1") (pinfunction "1_1") (pintype "passive"))
    )
    (net (code "298") (name "Net-(A274-Pad1)") (class "Default")
      (node (ref "A274") (pin "1") (pinfunction "1_1") (pintype "passive"))
      (node (ref "A274") (pin "2") (pinfunction "2_2") (pintype "passive"))
      (node (ref "IC26") (pin "2") (pinfunction "2_2") (pintype "passive"))
    )
    (net (code "299") (name "Net-(A275-Pad1)") (class "Default")
      (node (ref "A275") (pin "1") (pinfunction "1_1") (pintype "passive"))
      (node (ref "A275") (pin "2") (pinfunction "2_2") (pintype "passive"))
      (node (ref "IC26") (pin "3") (pinfunction "3_3") (pintype "passive"))
    )
    (net (code "300") (name "Net-(A276-Pad1)") (class "Default")
      (node (ref "A276") (pin "1") (pinfunction "1_1") (pintype "passive"))
      (node (ref "A276") (pin "2") (pinfunction "2_2") (pintype "passive"))
      (node (ref "IC26") (pin "4") (pinfunction "4_4") (pintype "passive"))
    )
    (net (code "301") (name "Net-(A277-Pad1)") (class "Default")
      (node (ref "A277") (pin "1") (pinfunction "1_1") (pintype "passive"))
      (node (ref "A277") (pin "2") (pinfunction "2_2") (pintype "passive"))
      (node (ref "IC26") (pin "5") (pinfunction "5_5") (pintype "passive"))
    )
    (net (code "302") (name "Net-(A278-Pad1)") (class "Default")
      (node (ref "A278") (pin "1") (pinfunction "1_1") (pintype "passive"))
      (node (ref "A278") (pin "2") (pinfunction "2_2") (pintype "passive"))
      (node (ref "IC26") (pin "6") (pinfunction "6_6") (pintype "passive"))
    )
    (net (code "303") (name "Net-(A279-Pad1)") (class "Default")
      (node (ref "A279") (pin "1") (pinfunction "1_1") (pintype "passive"))
      (node (ref "A279") (pin "2") (pinfunction "2_2") (pintype "passive"))
      (node (ref "IC26") (pin "7") (pinfunction "7_7") (pintype "passive"))
    )
    (net (code "304") (name "Net-(A280-Pad1)") (class "Default")
      (node (ref "A280") (pin "1") (pinfunction "1_1") (pintype "passive"))
      (node (ref "A280") (pin "2") (pinfunction "2_2") (pintype "passive"))
      (node (ref "IC26") (pin "8") (pinfunction "8_8") (pintype "passive"))
    )
    (net (code "305") (name "Net-(A281-Pad1)") (class "Default")
      (node (ref "A281") (pin "1") (pinfunction "1_1") (pintype "passive"))
      (node (ref "A281") (pin "2") (pinfunction "2_2") (pintype "passive"))
      (node (ref "IC26") (pin "9") (pinfunction "9_9") (pintype "passive"))
    )
    (net (code "306") (name "Net-(A282-Pad1)") (class "Default")
      (node (ref "A282") (pin "1") (pinfunction "1_1") (pintype "passive"))
      (node (ref "A282") (pin "2") (pinfunction "2_2") (pintype "passive"))
      (node (ref "IC26") (pin "10") (pinfunction "10_10") (pintype "passive"))
    )
    (net (code "307") (name "Net-(A283-Pad1)") (class "Default")
      (node (ref "A283") (pin "1") (pinfunction "1_1") (pintype "passive"))
      (node (ref "A283") (pin "2") (pinfunction "2_2") (pintype "passive"))
      (node (ref "IC26") (pin "11") (pinfunction "11_11") (pintype "passive"))
    )
    (net (code "308") (name "Net-(A284-Pad1)") (class "Default")
      (node (ref "A284") (pin "1") (pinfunction "1_1") (pintype "passive"))
      (node (ref "A284") (pin "2") (pinfunction "2_2") (pintype "passive"))
      (node (ref "IC26") (pin "12") (pinfunction "12_12") (pintype "passive"))
    )
    (net (code "309") (name "Net-(A285-Pad1)") (class "Default")
      (node (ref "A285") (pin "1") (pinfunction "1_1") (pintype "passive"))
      (node (ref "A285") (pin "2") (pinfunction "2_2") (pintype "passive"))
      (node (ref "IC26") (pin "13") (pinfunction "13_13") (pintype "passive"))
    )
    (net (code "310") (name "Net-(A286-Pad1)") (class "Default")
      (node (ref "A286") (pin "1") (pinfunction "1_1") (pintype "passive"))
      (node (ref "A286") (pin "2") (pinfunction "2_2") (pintype "passive"))
      (node (ref "IC26") (pin "14") (pinfunction "14_14") (pintype "passive"))
    )
    (net (code "311") (name "Net-(A287-Pad1)") (class "Default")
      (node (ref "A287") (pin "1") (pinfunction "1_1") (pintype "passive"))
      (node (ref "A287") (pin "2") (pinfunction "2_2") (pintype "passive"))
      (node (ref "IC26") (pin "15") (pinfunction "15_15") (pintype "passive"))
    )
    (net (code "312") (name "Net-(A288-Pad1)") (class "Default")
      (node (ref "A288") (pin "1") (pinfunction "1_1") (pintype "passive"))
      (node (ref "A288") (pin "2") (pinfunction "2_2") (pintype "passive"))
      (node (ref "IC26") (pin "16") (pinfunction "16_16") (pintype "passive"))
    )
    (net (code "313") (name "Net-(A289-Pad1)") (class "Default")
      (node (ref "A289") (pin "1") (pinfunction "1_1") (pintype "passive"))
      (node (ref "A289") (pin "2") (pinfunction "2_2") (pintype "passive"))
      (node (ref "IC27") (pin "1") (pinfunction "1_1") (pintype "passive"))
    )
    (net (code "314") (name "Net-(A290-Pad1)") (class "Default")
      (node (ref "A290") (pin "1") (pinfunction "1_1") (pintype "passive"))
      (node (ref "A290") (pin "2") (pinfunction "2_2") (pintype "passive"))
      (node (ref "IC27") (pin "2") (pinfunction "2_2") (pintype "passive"))
    )
    (net (code "315") (name "Net-(A291-Pad1)") (class "Default")
      (node (ref "A291") (pin "1") (pinfunction "1_1") (pintype "passive"))
      (node (ref "A291") (pin "2") (pinfunction "2_2") (pintype "passive"))
      (node (ref "IC27") (pin "3") (pinfunction "3_3") (pintype "passive"))
    )
    (net (code "316") (name "Net-(A292-Pad1)") (class "Default")
      (node (ref "A292") (pin "1") (pinfunction "1_1") (pintype "passive"))
      (node (ref "A292") (pin "2") (pinfunction "2_2") (pintype "passive"))
      (node (ref "IC27") (pin "4") (pinfunction "4_4") (pintype "passive"))
    )
    (net (code "317") (name "Net-(A293-Pad1)") (class "Default")
      (node (ref "A293") (pin "1") (pinfunction "1_1") (pintype "passive"))
      (node (ref "A293") (pin "2") (pinfunction "2_2") (pintype "passive"))
      (node (ref "IC27") (pin "5") (pinfunction "5_5") (pintype "passive"))
    )
    (net (code "318") (name "Net-(A294-Pad1)") (class "Default")
      (node (ref "A294") (pin "1") (pinfunction "1_1") (pintype "passive"))
      (node (ref "A294") (pin "2") (pinfunction "2_2") (pintype "passive"))
      (node (ref "IC27") (pin "6") (pinfunction "6_6") (pintype "passive"))
    )
    (net (code "319") (name "Net-(A295-Pad1)") (class "Default")
      (node (ref "A295") (pin "1") (pinfunction "1_1") (pintype "passive"))
      (node (ref "A295") (pin "2") (pinfunction "2_2") (pintype "passive"))
      (node (ref "IC27") (pin "7") (pinfunction "7_7") (pintype "passive"))
    )
    (net (code "320") (name "Net-(A296-Pad1)") (class "Default")
      (node (ref "A296") (pin "1") (pinfunction "1_1") (pintype "passive"))
      (node (ref "A296") (pin "2") (pinfunction "2_2") (pintype "passive"))
      (node (ref "IC27") (pin "8") (pinfunction "8_8") (pintype "passive"))
    )
    (net (code "321") (name "Net-(A297-Pad1)") (class "Default")
      (node (ref "A297") (pin "1") (pinfunction "1_1") (pintype "passive"))
      (node (ref "A297") (pin "2") (pinfunction "2_2") (pintype "passive"))
      (node (ref "IC27") (pin "9") (pinfunction "9_9") (pintype "passive"))
    )
    (net (code "322") (name "Net-(A298-Pad1)") (class "Default")
      (node (ref "A298") (pin "1") (pinfunction "1_1") (pintype "passive"))
      (node (ref "A298") (pin "2") (pinfunction "2_2") (pintype "passive"))
      (node (ref "IC27") (pin "10") (pinfunction "10_10") (pintype "passive"))
    )
    (net (code "323") (name "Net-(A299-Pad1)") (class "Default")
      (node (ref "A299") (pin "1") (pinfunction "1_1") (pintype "passive"))
      (node (ref "A299") (pin "2") (pinfunction "2_2") (pintype "passive"))
      (node (ref "IC27") (pin "11") (pinfunction "11_11") (pintype "passive"))
    )
    (net (code "324") (name "Net-(A300-Pad1)") (class "Default")
      (node (ref "A300") (pin "1") (pinfunction "1_1") (pintype "passive"))
      (node (ref "A300") (pin "2") (pinfunction "2_2") (pintype "passive"))
      (node (ref "IC27") (pin "12") (pinfunction "12_12") (pintype "passive"))
    )
    (net (code "325") (name "Net-(A301-Pad1)") (class "Default")
      (node (ref "A301") (pin "1") (pinfunction "1_1") (pintype "passive"))
      (node (ref "A301") (pin "2") (pinfunction "2_2") (pintype "passive"))
      (node (ref "IC27") (pin "13") (pinfunction "13_13") (pintype "passive"))
    )
    (net (code "326") (name "Net-(A302-Pad1)") (class "Default")
      (node (ref "A302") (pin "1") (pinfunction "1_1") (pintype "passive"))
      (node (ref "A302") (pin "2") (pinfunction "2_2") (pintype "passive"))
      (node (ref "IC27") (pin "14") (pinfunction "14_14") (pintype "passive"))
    )
    (net (code "327") (name "Net-(A303-Pad1)") (class "Default")
      (node (ref "A303") (pin "1") (pinfunction "1_1") (pintype "passive"))
      (node (ref "A303") (pin "2") (pinfunction "2_2") (pintype "passive"))
      (node (ref "IC27") (pin "15") (pinfunction "15_15") (pintype "passive"))
    )
    (net (code "328") (name "Net-(A304-Pad1)") (class "Default")
      (node (ref "A304") (pin "1") (pinfunction "1_1") (pintype "passive"))
      (node (ref "A304") (pin "2") (pinfunction "2_2") (pintype "passive"))
      (node (ref "IC27") (pin "16") (pinfunction "16_16") (pintype "passive"))
    )
    (net (code "329") (name "Net-(A305-Pad1)") (class "Default")
      (node (ref "A305") (pin "1") (pinfunction "1_1") (pintype "passive"))
      (node (ref "A305") (pin "2") (pinfunction "2_2") (pintype "passive"))
      (node (ref "IC28") (pin "1") (pinfunction "1_1") (pintype "passive"))
    )
    (net (code "330") (name "Net-(A306-Pad1)") (class "Default")
      (node (ref "A306") (pin "1") (pinfunction "1_1") (pintype "passive"))
      (node (ref "A306") (pin "2") (pinfunction "2_2") (pintype "passive"))
      (node (ref "IC28") (pin "2") (pinfunction "2_2") (pintype "passive"))
    )
    (net (code "331") (name "Net-(A307-Pad1)") (class "Default")
      (node (ref "A307") (pin "1") (pinfunction "1_1") (pintype "passive"))
      (node (ref "A307") (pin "2") (pinfunction "2_2") (pintype "passive"))
      (node (ref "IC28") (pin "3") (pinfunction "3_3") (pintype "passive"))
    )
    (net (code "332") (name "Net-(A308-Pad1)") (class "Default")
      (node (ref "A308") (pin "1") (pinfunction "1_1") (pintype "passive"))
      (node (ref "A308") (pin "2") (pinfunction "2_2") (pintype "passive"))
      (node (ref "IC28") (pin "4") (pinfunction "4_4") (pintype "passive"))
    )
    (net (code "333") (name "Net-(A309-Pad1)") (class "Default")
      (node (ref "A309") (pin "1") (pinfunction "1_1") (pintype "passive"))
      (node (ref "A309") (pin "2") (pinfunction "2_2") (pintype "passive"))
      (node (ref "IC28") (pin "5") (pinfunction "5_5") (pintype "passive"))
    )
    (net (code "334") (name "Net-(A310-Pad1)") (class "Default")
      (node (ref "A310") (pin "1") (pinfunction "1_1") (pintype "passive"))
      (node (ref "A310") (pin "2") (pinfunction "2_2") (pintype "passive"))
      (node (ref "IC28") (pin "6") (pinfunction "6_6") (pintype "passive"))
    )
    (net (code "335") (name "Net-(A311-Pad1)") (class "Default")
      (node (ref "A311") (pin "1") (pinfunction "1_1") (pintype "passive"))
      (node (ref "A311") (pin "2") (pinfunction "2_2") (pintype "passive"))
      (node (ref "IC28") (pin "7") (pinfunction "7_7") (pintype "passive"))
    )
    (net (code "336") (name "Net-(A312-Pad1)") (class "Default")
      (node (ref "A312") (pin "1") (pinfunction "1_1") (pintype "passive"))
      (node (ref "A312") (pin "2") (pinfunction "2_2") (pintype "passive"))
      (node (ref "IC28") (pin "8") (pinfunction "8_8") (pintype "passive"))
    )
    (net (code "337") (name "Net-(A313-Pad1)") (class "Default")
      (node (ref "A313") (pin "1") (pinfunction "1_1") (pintype "passive"))
      (node (ref "A313") (pin "2") (pinfunction "2_2") (pintype "passive"))
      (node (ref "IC28") (pin "9") (pinfunction "9_9") (pintype "passive"))
    )
    (net (code "338") (name "Net-(A314-Pad1)") (class "Default")
      (node (ref "A314") (pin "1") (pinfunction "1_1") (pintype "passive"))
      (node (ref "A314") (pin "2") (pinfunction "2_2") (pintype "passive"))
      (node (ref "IC28") (pin "10") (pinfunction "10_10") (pintype "passive"))
    )
    (net (code "339") (name "Net-(A315-Pad1)") (class "Default")
      (node (ref "A315") (pin "1") (pinfunction "1_1") (pintype "passive"))
      (node (ref "A315") (pin "2") (pinfunction "2_2") (pintype "passive"))
      (node (ref "IC28") (pin "11") (pinfunction "11_11") (pintype "passive"))
    )
    (net (code "340") (name "Net-(A316-Pad1)") (class "Default")
      (node (ref "A316") (pin "1") (pinfunction "1_1") (pintype "passive"))
      (node (ref "A316") (pin "2") (pinfunction "2_2") (pintype "passive"))
      (node (ref "IC28") (pin "12") (pinfunction "12_12") (pintype "passive"))
    )
    (net (code "341") (name "Net-(A317-Pad1)") (class "Default")
      (node (ref "A317") (pin "1") (pinfunction "1_1") (pintype "passive"))
      (node (ref "A317") (pin "2") (pinfunction "2_2") (pintype "passive"))
      (node (ref "IC28") (pin "13") (pinfunction "13_13") (pintype "passive"))
    )
    (net (code "342") (name "Net-(A318-Pad1)") (class "Default")
      (node (ref "A318") (pin "1") (pinfunction "1_1") (pintype "passive"))
      (node (ref "A318") (pin "2") (pinfunction "2_2") (pintype "passive"))
      (node (ref "IC28") (pin "14") (pinfunction "14_14") (pintype "passive"))
    )
    (net (code "343") (name "Net-(A319-Pad1)") (class "Default")
      (node (ref "A319") (pin "1") (pinfunction "1_1") (pintype "passive"))
      (node (ref "A319") (pin "2") (pinfunction "2_2") (pintype "passive"))
      (node (ref "IC28") (pin "15") (pinfunction "15_15") (pintype "passive"))
    )
    (net (code "344") (name "Net-(A320-Pad1)") (class "Default")
      (node (ref "A320") (pin "1") (pinfunction "1_1") (pintype "passive"))
      (node (ref "A320") (pin "2") (pinfunction "2_2") (pintype "passive"))
      (node (ref "IC28") (pin "16") (pinfunction "16_16") (pintype "passive"))
    )
    (net (code "345") (name "Net-(A321-Pad1)") (class "Default")
      (node (ref "A321") (pin "1") (pinfunction "1_1") (pintype "passive"))
      (node (ref "A321") (pin "2") (pinfunction "2_2") (pintype "passive"))
      (node (ref "IC29") (pin "1") (pinfunction "1_1") (pintype "passive"))
    )
    (net (code "346") (name "Net-(A322-Pad1)") (class "Default")
      (node (ref "A322") (pin "1") (pinfunction "1_1") (pintype "passive"))
      (node (ref "A322") (pin "2") (pinfunction "2_2") (pintype "passive"))
      (node (ref "IC29") (pin "2") (pinfunction "2_2") (pintype "passive"))
    )
    (net (code "347") (name "Net-(A323-Pad1)") (class "Default")
      (node (ref "A323") (pin "1") (pinfunction "1_1") (pintype "passive"))
      (node (ref "A323") (pin "2") (pinfunction "2_2") (pintype "passive"))
      (node (ref "IC29") (pin "3") (pinfunction "3_3") (pintype "passive"))
    )
    (net (code "348") (name "Net-(A324-Pad1)") (class "Default")
      (node (ref "A324") (pin "1") (pinfunction "1_1") (pintype "passive"))
      (node (ref "A324") (pin "2") (pinfunction "2_2") (pintype "passive"))
      (node (ref "IC29") (pin "4") (pinfunction "4_4") (pintype "passive"))
    )
    (net (code "349") (name "Net-(A325-Pad1)") (class "Default")
      (node (ref "A325") (pin "1") (pinfunction "1_1") (pintype "passive"))
      (node (ref "A325") (pin "2") (pinfunction "2_2") (pintype "passive"))
      (node (ref "IC29") (pin "5") (pinfunction "5_5") (pintype "passive"))
    )
    (net (code "350") (name "Net-(A326-Pad1)") (class "Default")
      (node (ref "A326") (pin "1") (pinfunction "1_1") (pintype "passive"))
      (node (ref "A326") (pin "2") (pinfunction "2_2") (pintype "passive"))
      (node (ref "IC29") (pin "6") (pinfunction "6_6") (pintype "passive"))
    )
    (net (code "351") (name "Net-(A327-Pad1)") (class "Default")
      (node (ref "A327") (pin "1") (pinfunction "1_1") (pintype "passive"))
      (node (ref "A327") (pin "2") (pinfunction "2_2") (pintype "passive"))
      (node (ref "IC29") (pin "7") (pinfunction "7_7") (pintype "passive"))
    )
    (net (code "352") (name "Net-(A328-Pad1)") (class "Default")
      (node (ref "A328") (pin "1") (pinfunction "1_1") (pintype "passive"))
      (node (ref "A328") (pin "2") (pinfunction "2_2") (pintype "passive"))
      (node (ref "IC29") (pin "8") (pinfunction "8_8") (pintype "passive"))
    )
    (net (code "353") (name "Net-(A329-Pad1)") (class "Default")
      (node (ref "A329") (pin "1") (pinfunction "1_1") (pintype "passive"))
      (node (ref "A329") (pin "2") (pinfunction "2_2") (pintype "passive"))
      (node (ref "IC29") (pin "9") (pinfunction "9_9") (pintype "passive"))
    )
    (net (code "354") (name "Net-(A330-Pad1)") (class "Default")
      (node (ref "A330") (pin "1") (pinfunction "1_1") (pintype "passive"))
      (node (ref "A330") (pin "2") (pinfunction "2_2") (pintype "passive"))
      (node (ref "IC29") (pin "10") (pinfunction "10_10") (pintype "passive"))
    )
    (net (code "355") (name "Net-(A331-Pad1)") (class "Default")
      (node (ref "A331") (pin "1") (pinfunction "1_1") (pintype "passive"))
      (node (ref "A331") (pin "2") (pinfunction "2_2") (pintype "passive"))
      (node (ref "IC29") (pin "11") (pinfunction "11_11") (pintype "passive"))
    )
    (net (code "356") (name "Net-(A332-Pad1)") (class "Default")
      (node (ref "A332") (pin "1") (pinfunction "1_1") (pintype "passive"))
      (node (ref "A332") (pin "2") (pinfunction "2_2") (pintype "passive"))
      (node (ref "IC29") (pin "12") (pinfunction "12_12") (pintype "passive"))
    )
    (net (code "357") (name "Net-(A333-Pad1)") (class "Default")
      (node (ref "A333") (pin "1") (pinfunction "1_1") (pintype "passive"))
      (node (ref "A333") (pin "2") (pinfunction "2_2") (pintype "passive"))
      (node (ref "IC29") (pin "13") (pinfunction "13_13") (pintype "passive"))
    )
    (net (code "358") (name "Net-(A334-Pad1)") (class "Default")
      (node (ref "A334") (pin "1") (pinfunction "1_1") (pintype "passive"))
      (node (ref "A334") (pin "2") (pinfunction "2_2") (pintype "passive"))
      (node (ref "IC29") (pin "14") (pinfunction "14_14") (pintype "passive"))
    )
    (net (code "359") (name "Net-(A335-Pad1)") (class "Default")
      (node (ref "A335") (pin "1") (pinfunction "1_1") (pintype "passive"))
      (node (ref "A335") (pin "2") (pinfunction "2_2") (pintype "passive"))
      (node (ref "IC29") (pin "15") (pinfunction "15_15") (pintype "passive"))
    )
    (net (code "360") (name "Net-(A336-Pad1)") (class "Default")
      (node (ref "A336") (pin "1") (pinfunction "1_1") (pintype "passive"))
      (node (ref "A336") (pin "2") (pinfunction "2_2") (pintype "passive"))
      (node (ref "IC29") (pin "16") (pinfunction "16_16") (pintype "passive"))
    )
    (net (code "361") (name "Net-(A337-Pad1)") (class "Default")
      (node (ref "A337") (pin "1") (pinfunction "1_1") (pintype "passive"))
      (node (ref "A337") (pin "2") (pinfunction "2_2") (pintype "passive"))
      (node (ref "IC30") (pin "1") (pinfunction "1_1") (pintype "passive"))
    )
    (net (code "362") (name "Net-(A338-Pad1)") (class "Default")
      (node (ref "A338") (pin "1") (pinfunction "1_1") (pintype "passive"))
      (node (ref "A338") (pin "2") (pinfunction "2_2") (pintype "passive"))
      (node (ref "IC30") (pin "2") (pinfunction "2_2") (pintype "passive"))
    )
    (net (code "363") (name "Net-(A339-Pad1)") (class "Default")
      (node (ref "A339") (pin "1") (pinfunction "1_1") (pintype "passive"))
      (node (ref "A339") (pin "2") (pinfunction "2_2") (pintype "passive"))
      (node (ref "IC30") (pin "3") (pinfunction "3_3") (pintype "passive"))
    )
    (net (code "364") (name "Net-(A340-Pad1)") (class "Default")
      (node (ref "A340") (pin "1") (pinfunction "1_1") (pintype "passive"))
      (node (ref "A340") (pin "2") (pinfunction "2_2") (pintype "passive"))
      (node (ref "IC30") (pin "4") (pinfunction "4_4") (pintype "passive"))
    )
    (net (code "365") (name "Net-(A341-Pad1)") (class "Default")
      (node (ref "A341") (pin "1") (pinfunction "1_1") (pintype "passive"))
      (node (ref "A341") (pin "2") (pinfunction "2_2") (pintype "passive"))
      (node (ref "IC30") (pin "5") (pinfunction "5_5") (pintype "passive"))
    )
    (net (code "366") (name "Net-(A342-Pad1)") (class "Default")
      (node (ref "A342") (pin "1") (pinfunction "1_1") (pintype "passive"))
      (node (ref "A342") (pin "2") (pinfunction "2_2") (pintype "passive"))
      (node (ref "IC30") (pin "6") (pinfunction "6_6") (pintype "passive"))
    )
    (net (code "367") (name "Net-(A343-Pad1)") (class "Default")
      (node (ref "A343") (pin "1") (pinfunction "1_1") (pintype "passive"))
      (node (ref "A343") (pin "2") (pinfunction "2_2") (pintype "passive"))
      (node (ref "IC30") (pin "7") (pinfunction "7_7") (pintype "passive"))
    )
    (net (code "368") (name "Net-(A344-Pad1)") (class "Default")
      (node (ref "A344") (pin "1") (pinfunction "1_1") (pintype "passive"))
      (node (ref "A344") (pin "2") (pinfunction "2_2") (pintype "passive"))
      (node (ref "IC30") (pin "8") (pinfunction "8_8") (pintype "passive"))
    )
    (net (code "369") (name "Net-(A345-Pad1)") (class "Default")
      (node (ref "A345") (pin "1") (pinfunction "1_1") (pintype "passive"))
      (node (ref "A345") (pin "2") (pinfunction "2_2") (pintype "passive"))
      (node (ref "IC30") (pin "9") (pinfunction "9_9") (pintype "passive"))
    )
    (net (code "370") (name "Net-(A346-Pad1)") (class "Default")
      (node (ref "A346") (pin "1") (pinfunction "1_1") (pintype "passive"))
      (node (ref "A346") (pin "2") (pinfunction "2_2") (pintype "passive"))
      (node (ref "IC30") (pin "10") (pinfunction "10_10") (pintype "passive"))
    )
    (net (code "371") (name "Net-(A347-Pad1)") (class "Default")
      (node (ref "A347") (pin "1") (pinfunction "1_1") (pintype "passive"))
      (node (ref "A347") (pin "2") (pinfunction "2_2") (pintype "passive"))
      (node (ref "IC30") (pin "11") (pinfunction "11_11") (pintype "passive"))
    )
    (net (code "372") (name "Net-(A348-Pad1)") (class "Default")
      (node (ref "A348") (pin "1") (pinfunction "1_1") (pintype "passive"))
      (node (ref "A348") (pin "2") (pinfunction "2_2") (pintype "passive"))
      (node (ref "IC30") (pin "12") (pinfunction "12_12") (pintype "passive"))
    )
    (net (code "373") (name "Net-(A349-Pad1)") (class "Default")
      (node (ref "A349") (pin "1") (pinfunction "1_1") (pintype "passive"))
      (node (ref "A349") (pin "2") (pinfunction "2_2") (pintype "passive"))
      (node (ref "IC30") (pin "13") (pinfunction "13_13") (pintype "passive"))
    )
    (net (code "374") (name "Net-(A350-Pad1)") (class "Default")
      (node (ref "A350") (pin "1") (pinfunction "1_1") (pintype "passive"))
      (node (ref "A350") (pin "2") (pinfunction "2_2") (pintype "passive"))
      (node (ref "IC30") (pin "14") (pinfunction "14_14") (pintype "passive"))
    )
    (net (code "375") (name "Net-(A351-Pad1)") (class "Default")
      (node (ref "A351") (pin "1") (pinfunction "1_1") (pintype "passive"))
      (node (ref "A351") (pin "2") (pinfunction "2_2") (pintype "passive"))
      (node (ref "IC30") (pin "15") (pinfunction "15_15") (pintype "passive"))
    )
    (net (code "376") (name "Net-(A352-Pad1)") (class "Default")
      (node (ref "A352") (pin "1") (pinfunction "1_1") (pintype "passive"))
      (node (ref "A352") (pin "2") (pinfunction "2_2") (pintype "passive"))
      (node (ref "IC30") (pin "16") (pinfunction "16_16") (pintype "passive"))
    )
    (net (code "377") (name "Net-(A353-Pad1)") (class "Default")
      (node (ref "A353") (pin "1") (pinfunction "1_1") (pintype "passive"))
      (node (ref "A353") (pin "2") (pinfunction "2_2") (pintype "passive"))
      (node (ref "IC31") (pin "1") (pinfunction "1_1") (pintype "passive"))
    )
    (net (code "378") (name "Net-(A354-Pad1)") (class "Default")
      (node (ref "A354") (pin "1") (pinfunction "1_1") (pintype "passive"))
      (node (ref "A354") (pin "2") (pinfunction "2_2") (pintype "passive"))
      (node (ref "IC31") (pin "2") (pinfunction "2_2") (pintype "passive"))
    )
    (net (code "379") (name "Net-(A355-Pad1)") (class "Default")
      (node (ref "A355") (pin "1") (pinfunction "1_1") (pintype "passive"))
      (node (ref "A355") (pin "2") (pinfunction "2_2") (pintype "passive"))
      (node (ref "IC31") (pin "3") (pinfunction "3_3") (pintype "passive"))
    )
    (net (code "380") (name "Net-(A356-Pad1)") (class "Default")
      (node (ref "A356") (pin "1") (pinfunction "1_1") (pintype "passive"))
      (node (ref "A356") (pin "2") (pinfunction "2_2") (pintype "passive"))
      (node (ref "IC31") (pin "4") (pinfunction "4_4") (pintype "passive"))
    )
    (net (code "381") (name "Net-(A357-Pad1)") (class "Default")
      (node (ref "A357") (pin "1") (pinfunction "1_1") (pintype "passive"))
      (node (ref "A357") (pin "2") (pinfunction "2_2") (pintype "passive"))
      (node (ref "IC31") (pin "5") (pinfunction "5_5") (pintype "passive"))
    )
    (net (code "382") (name "Net-(A358-Pad1)") (class "Default")
      (node (ref "A358") (pin "1") (pinfunction "1_1") (pintype "passive"))
      (node (ref "A358") (pin "2") (pinfunction "2_2") (pintype "passive"))
      (node (ref "IC31") (pin "6") (pinfunction "6_6") (pintype "passive"))
    )
    (net (code "383") (name "Net-(A359-Pad1)") (class "Default")
      (node (ref "A359") (pin "1") (pinfunction "1_1") (pintype "passive"))
      (node (ref "A359") (pin "2") (pinfunction "2_2") (pintype "passive"))
      (node (ref "IC31") (pin "7") (pinfunction "7_7") (pintype "passive"))
    )
    (net (code "384") (name "Net-(A360-Pad1)") (class "Default")
      (node (ref "A360") (pin "1") (pinfunction "1_1") (pintype "passive"))
      (node (ref "A360") (pin "2") (pinfunction "2_2") (pintype "passive"))
      (node (ref "IC31") (pin "8") (pinfunction "8_8") (pintype "passive"))
    )
    (net (code "385") (name "Net-(A361-Pad1)") (class "Default")
      (node (ref "A361") (pin "1") (pinfunction "1_1") (pintype "passive"))
      (node (ref "A361") (pin "2") (pinfunction "2_2") (pintype "passive"))
      (node (ref "IC31") (pin "9") (pinfunction "9_9") (pintype "passive"))
    )
    (net (code "386") (name "Net-(A362-Pad1)") (class "Default")
      (node (ref "A362") (pin "1") (pinfunction "1_1") (pintype "passive"))
      (node (ref "A362") (pin "2") (pinfunction "2_2") (pintype "passive"))
      (node (ref "IC31") (pin "10") (pinfunction "10_10") (pintype "passive"))
    )
    (net (code "387") (name "Net-(A363-Pad1)") (class "Default")
      (node (ref "A363") (pin "1") (pinfunction "1_1") (pintype "passive"))
      (node (ref "A363") (pin "2") (pinfunction "2_2") (pintype "passive"))
      (node (ref "IC31") (pin "11") (pinfunction "11_11") (pintype "passive"))
    )
    (net (code "388") (name "Net-(A364-Pad1)") (class "Default")
      (node (ref "A364") (pin "1") (pinfunction "1_1") (pintype "passive"))
      (node (ref "A364") (pin "2") (pinfunction "2_2") (pintype "passive"))
      (node (ref "IC31") (pin "12") (pinfunction "12_12") (pintype "passive"))
    )
    (net (code "389") (name "Net-(A365-Pad1)") (class "Default")
      (node (ref "A365") (pin "1") (pinfunction "1_1") (pintype "passive"))
      (node (ref "A365") (pin "2") (pinfunction "2_2") (pintype "passive"))
      (node (ref "IC31") (pin "13") (pinfunction "13_13") (pintype "passive"))
    )
    (net (code "390") (name "Net-(A366-Pad1)") (class "Default")
      (node (ref "A366") (pin "1") (pinfunction "1_1") (pintype "passive"))
      (node (ref "A366") (pin "2") (pinfunction "2_2") (pintype "passive"))
      (node (ref "IC31") (pin "14") (pinfunction "14_14") (pintype "passive"))
    )
    (net (code "391") (name "Net-(A367-Pad1)") (class "Default")
      (node (ref "A367") (pin "1") (pinfunction "1_1") (pintype "passive"))
      (node (ref "A367") (pin "2") (pinfunction "2_2") (pintype "passive"))
      (node (ref "IC31") (pin "15") (pinfunction "15_15") (pintype "passive"))
    )
    (net (code "392") (name "Net-(A368-Pad1)") (class "Default")
      (node (ref "A368") (pin "1") (pinfunction "1_1") (pintype "passive"))
      (node (ref "A368") (pin "2") (pinfunction "2_2") (pintype "passive"))
      (node (ref "IC31") (pin "16") (pinfunction "16_16") (pintype "passive"))
    )
    (net (code "393") (name "Net-(A369-Pad1)") (class "Default")
      (node (ref "A369") (pin "1") (pinfunction "1_1") (pintype "passive"))
      (node (ref "A369") (pin "2") (pinfunction "2_2") (pintype "passive"))
      (node (ref "IC32") (pin "1") (pinfunction "1_1") (pintype "passive"))
    )
    (net (code "394") (name "Net-(A370-Pad1)") (class "Default")
      (node (ref "A370") (pin "1") (pinfunction "1_1") (pintype "passive"))
      (node (ref "A370") (pin "2") (pinfunction "2_2") (pintype "passive"))
      (node (ref "IC32") (pin "2") (pinfunction "2_2") (pintype "passive"))
    )
    (net (code "395") (name "Net-(A371-Pad1)") (class "Default")
      (node (ref "A371") (pin "1") (pinfunction "1_1") (pintype "passive"))
      (node (ref "A371") (pin "2") (pinfunction "2_2") (pintype "passive"))
      (node (ref "IC32") (pin "3") (pinfunction "3_3") (pintype "passive"))
    )
    (net (code "396") (name "Net-(A372-Pad1)") (class "Default")
      (node (ref "A372") (pin "1") (pinfunction "1_1") (pintype "passive"))
      (node (ref "A372") (pin "2") (pinfunction "2_2") (pintype "passive"))
      (node (ref "IC32") (pin "4") (pinfunction "4_4") (pintype "passive"))
    )
    (net (code "397") (name "Net-(A373-Pad1)") (class "Default")
      (node (ref "A373") (pin "1") (pinfunction "1_1") (pintype "passive"))
      (node (ref "A373") (pin "2") (pinfunction "2_2") (pintype "passive"))
      (node (ref "IC32") (pin "5") (pinfunction "5_5") (pintype "passive"))
    )
    (net (code "398") (name "Net-(A374-Pad1)") (class "Default")
      (node (ref "A374") (pin "1") (pinfunction "1_1") (pintype "passive"))
      (node (ref "A374") (pin "2") (pinfunction "2_2") (pintype "passive"))
      (node (ref "IC32") (pin "6") (pinfunction "6_6") (pintype "passive"))
    )
    (net (code "399") (name "Net-(A375-Pad1)") (class "Default")
      (node (ref "A375") (pin "1") (pinfunction "1_1") (pintype "passive"))
      (node (ref "A375") (pin "2") (pinfunction "2_2") (pintype "passive"))
      (node (ref "IC32") (pin "7") (pinfunction "7_7") (pintype "passive"))
    )
    (net (code "400") (name "Net-(A376-Pad1)") (class "Default")
      (node (ref "A376") (pin "1") (pinfunction "1_1") (pintype "passive"))
      (node (ref "A376") (pin "2") (pinfunction "2_2") (pintype "passive"))
      (node (ref "IC32") (pin "8") (pinfunction "8_8") (pintype "passive"))
    )
    (net (code "401") (name "Net-(A377-Pad1)") (class "Default")
      (node (ref "A377") (pin "1") (pinfunction "1_1") (pintype "passive"))
      (node (ref "A377") (pin "2") (pinfunction "2_2") (pintype "passive"))
      (node (ref "IC32") (pin "9") (pinfunction "9_9") (pintype "passive"))
    )
    (net (code "402") (name "Net-(A378-Pad1)") (class "Default")
      (node (ref "A378") (pin "1") (pinfunction "1_1") (pintype "passive"))
      (node (ref "A378") (pin "2") (pinfunction "2_2") (pintype "passive"))
      (node (ref "IC32") (pin "10") (pinfunction "10_10") (pintype "passive"))
    )
    (net (code "403") (name "Net-(A379-Pad1)") (class "Default")
      (node (ref "A379") (pin "1") (pinfunction "1_1") (pintype "passive"))
      (node (ref "A379") (pin "2") (pinfunction "2_2") (pintype "passive"))
      (node (ref "IC32") (pin "11") (pinfunction "11_11") (pintype "passive"))
    )
    (net (code "404") (name "Net-(A380-Pad1)") (class "Default")
      (node (ref "A380") (pin "1") (pinfunction "1_1") (pintype "passive"))
      (node (ref "A380") (pin "2") (pinfunction "2_2") (pintype "passive"))
      (node (ref "IC32") (pin "12") (pinfunction "12_12") (pintype "passive"))
    )
    (net (code "405") (name "Net-(A381-Pad1)") (class "Default")
      (node (ref "A381") (pin "1") (pinfunction "1_1") (pintype "passive"))
      (node (ref "A381") (pin "2") (pinfunction "2_2") (pintype "passive"))
      (node (ref "IC32") (pin "13") (pinfunction "13_13") (pintype "passive"))
    )
    (net (code "406") (name "Net-(A382-Pad1)") (class "Default")
      (node (ref "A382") (pin "1") (pinfunction "1_1") (pintype "passive"))
      (node (ref "A382") (pin "2") (pinfunction "2_2") (pintype "passive"))
      (node (ref "IC32") (pin "14") (pinfunction "14_14") (pintype "passive"))
    )
    (net (code "407") (name "Net-(A383-Pad1)") (class "Default")
      (node (ref "A383") (pin "1") (pinfunction "1_1") (pintype "passive"))
      (node (ref "A383") (pin "2") (pinfunction "2_2") (pintype "passive"))
      (node (ref "IC32") (pin "15") (pinfunction "15_15") (pintype "passive"))
    )
    (net (code "408") (name "Net-(A384-Pad1)") (class "Default")
      (node (ref "A384") (pin "1") (pinfunction "1_1") (pintype "passive"))
      (node (ref "A384") (pin "2") (pinfunction "2_2") (pintype "passive"))
      (node (ref "IC32") (pin "16") (pinfunction "16_16") (pintype "passive"))
    )
    (net (code "409") (name "Net-(A385-Pad1)") (class "Default")
      (node (ref "A385") (pin "1") (pinfunction "1_1") (pintype "passive"))
      (node (ref "A385") (pin "2") (pinfunction "2_2") (pintype "passive"))
      (node (ref "IC33") (pin "1") (pinfunction "1_1") (pintype "passive"))
    )
    (net (code "410") (name "Net-(A386-Pad1)") (class "Default")
      (node (ref "A386") (pin "1") (pinfunction "1_1") (pintype "passive"))
      (node (ref "A386") (pin "2") (pinfunction "2_2") (pintype "passive"))
      (node (ref "IC33") (pin "2") (pinfunction "2_2") (pintype "passive"))
    )
    (net (code "411") (name "Net-(A387-Pad1)") (class "Default")
      (node (ref "A387") (pin "1") (pinfunction "1_1") (pintype "passive"))
      (node (ref "A387") (pin "2") (pinfunction "2_2") (pintype "passive"))
      (node (ref "IC33") (pin "3") (pinfunction "3_3") (pintype "passive"))
    )
    (net (code "412") (name "Net-(A388-Pad1)") (class "Default")
      (node (ref "A388") (pin "1") (pinfunction "1_1") (pintype "passive"))
      (node (ref "A388") (pin "2") (pinfunction "2_2") (pintype "passive"))
      (node (ref "IC33") (pin "4") (pinfunction "4_4") (pintype "passive"))
    )
    (net (code "413") (name "Net-(A389-Pad1)") (class "Default")
      (node (ref "A389") (pin "1") (pinfunction "1_1") (pintype "passive"))
      (node (ref "A389") (pin "2") (pinfunction "2_2") (pintype "passive"))
      (node (ref "IC33") (pin "5") (pinfunction "5_5") (pintype "passive"))
    )
    (net (code "414") (name "Net-(A390-Pad1)") (class "Default")
      (node (ref "A390") (pin "1") (pinfunction "1_1") (pintype "passive"))
      (node (ref "A390") (pin "2") (pinfunction "2_2") (pintype "passive"))
      (node (ref "IC33") (pin "6") (pinfunction "6_6") (pintype "passive"))
    )
    (net (code "415") (name "Net-(A391-Pad1)") (class "Default")
      (node (ref "A391") (pin "1") (pinfunction "1_1") (pintype "passive"))
      (node (ref "A391") (pin "2") (pinfunction "2_2") (pintype "passive"))
      (node (ref "IC33") (pin "7") (pinfunction "7_7") (pintype "passive"))
    )
    (net (code "416") (name "Net-(A392-Pad1)") (class "Default")
      (node (ref "A392") (pin "1") (pinfunction "1_1") (pintype "passive"))
      (node (ref "A392") (pin "2") (pinfunction "2_2") (pintype "passive"))
      (node (ref "IC33") (pin "8") (pinfunction "8_8") (pintype "passive"))
    )
    (net (code "417") (name "Net-(A393-Pad1)") (class "Default")
      (node (ref "A393") (pin "1") (pinfunction "1_1") (pintype "passive"))
      (node (ref "A393") (pin "2") (pinfunction "2_2") (pintype "passive"))
      (node (ref "IC33") (pin "9") (pinfunction "9_9") (pintype "passive"))
    )
    (net (code "418") (name "Net-(A394-Pad1)") (class "Default")
      (node (ref "A394") (pin "1") (pinfunction "1_1") (pintype "passive"))
      (node (ref "A394") (pin "2") (pinfunction "2_2") (pintype "passive"))
      (node (ref "IC33") (pin "10") (pinfunction "10_10") (pintype "passive"))
    )
    (net (code "419") (name "Net-(A395-Pad1)") (class "Default")
      (node (ref "A395") (pin "1") (pinfunction "1_1") (pintype "passive"))
      (node (ref "A395") (pin "2") (pinfunction "2_2") (pintype "passive"))
      (node (ref "IC33") (pin "11") (pinfunction "11_11") (pintype "passive"))
    )
    (net (code "420") (name "Net-(A396-Pad1)") (class "Default")
      (node (ref "A396") (pin "1") (pinfunction "1_1") (pintype "passive"))
      (node (ref "A396") (pin "2") (pinfunction "2_2") (pintype "passive"))
      (node (ref "IC33") (pin "12") (pinfunction "12_12") (pintype "passive"))
    )
    (net (code "421") (name "Net-(A397-Pad1)") (class "Default")
      (node (ref "A397") (pin "1") (pinfunction "1_1") (pintype "passive"))
      (node (ref "A397") (pin "2") (pinfunction "2_2") (pintype "passive"))
      (node (ref "IC33") (pin "13") (pinfunction "13_13") (pintype "passive"))
    )
    (net (code "422") (name "Net-(A398-Pad1)") (class "Default")
      (node (ref "A398") (pin "1") (pinfunction "1_1") (pintype "passive"))
      (node (ref "A398") (pin "2") (pinfunction "2_2") (pintype "passive"))
      (node (ref "IC33") (pin "14") (pinfunction "14_14") (pintype "passive"))
    )
    (net (code "423") (name "Net-(A399-Pad1)") (class "Default")
      (node (ref "A399") (pin "1") (pinfunction "1_1") (pintype "passive"))
      (node (ref "A399") (pin "2") (pinfunction "2_2") (pintype "passive"))
      (node (ref "IC33") (pin "15") (pinfunction "15_15") (pintype "passive"))
    )
    (net (code "424") (name "Net-(A400-Pad1)") (class "Default")
      (node (ref "A400") (pin "1") (pinfunction "1_1") (pintype "passive"))
      (node (ref "A400") (pin "2") (pinfunction "2_2") (pintype "passive"))
      (node (ref "IC33") (pin "16") (pinfunction "16_16") (pintype "passive"))
    )
    (net (code "425") (name "Net-(A401-Pad1)") (class "Default")
      (node (ref "A401") (pin "1") (pinfunction "1_1") (pintype "passive"))
      (node (ref "A401") (pin "2") (pinfunction "2_2") (pintype "passive"))
      (node (ref "IC34") (pin "1") (pinfunction "1_1") (pintype "passive"))
    )
    (net (code "426") (name "Net-(A402-Pad1)") (class "Default")
      (node (ref "A402") (pin "1") (pinfunction "1_1") (pintype "passive"))
      (node (ref "A402") (pin "2") (pinfunction "2_2") (pintype "passive"))
      (node (ref "IC34") (pin "2") (pinfunction "2_2") (pintype "passive"))
    )
    (net (code "427") (name "Net-(A403-Pad1)") (class "Default")
      (node (ref "A403") (pin "1") (pinfunction "1_1") (pintype "passive"))
      (node (ref "A403") (pin "2") (pinfunction "2_2") (pintype "passive"))
      (node (ref "IC34") (pin "3") (pinfunction "3_3") (pintype "passive"))
    )
    (net (code "428") (name "Net-(A404-Pad1)") (class "Default")
      (node (ref "A404") (pin "1") (pinfunction "1_1") (pintype "passive"))
      (node (ref "A404") (pin "2") (pinfunction "2_2") (pintype "passive"))
      (node (ref "IC34") (pin "4") (pinfunction "4_4") (pintype "passive"))
    )
    (net (code "429") (name "Net-(A405-Pad1)") (class "Default")
      (node (ref "A405") (pin "1") (pinfunction "1_1") (pintype "passive"))
      (node (ref "A405") (pin "2") (pinfunction "2_2") (pintype "passive"))
      (node (ref "IC34") (pin "5") (pinfunction "5_5") (pintype "passive"))
    )
    (net (code "430") (name "Net-(A406-Pad1)") (class "Default")
      (node (ref "A406") (pin "1") (pinfunction "1_1") (pintype "passive"))
      (node (ref "A406") (pin "2") (pinfunction "2_2") (pintype "passive"))
      (node (ref "IC34") (pin "6") (pinfunction "6_6") (pintype "passive"))
    )
    (net (code "431") (name "Net-(A407-Pad1)") (class "Default")
      (node (ref "A407") (pin "1") (pinfunction "1_1") (pintype "passive"))
      (node (ref "A407") (pin "2") (pinfunction "2_2") (pintype "passive"))
      (node (ref "IC34") (pin "7") (pinfunction "7_7") (pintype "passive"))
    )
    (net (code "432") (name "Net-(A408-Pad1)") (class "Default")
      (node (ref "A408") (pin "1") (pinfunction "1_1") (pintype "passive"))
      (node (ref "A408") (pin "2") (pinfunction "2_2") (pintype "passive"))
      (node (ref "IC34") (pin "8") (pinfunction "8_8") (pintype "passive"))
    )
    (net (code "433") (name "Net-(A409-Pad1)") (class "Default")
      (node (ref "A409") (pin "1") (pinfunction "1_1") (pintype "passive"))
      (node (ref "A409") (pin "2") (pinfunction "2_2") (pintype "passive"))
      (node (ref "IC34") (pin "9") (pinfunction "9_9") (pintype "passive"))
    )
    (net (code "434") (name "Net-(A410-Pad1)") (class "Default")
      (node (ref "A410") (pin "1") (pinfunction "1_1") (pintype "passive"))
      (node (ref "A410") (pin "2") (pinfunction "2_2") (pintype "passive"))
      (node (ref "IC34") (pin "10") (pinfunction "10_10") (pintype "passive"))
    )
    (net (code "435") (name "Net-(A411-Pad1)") (class "Default")
      (node (ref "A411") (pin "1") (pinfunction "1_1") (pintype "passive"))
      (node (ref "A411") (pin "2") (pinfunction "2_2") (pintype "passive"))
      (node (ref "IC34") (pin "11") (pinfunction "11_11") (pintype "passive"))
    )
    (net (code "436") (name "Net-(A412-Pad1)") (class "Default")
      (node (ref "A412") (pin "1") (pinfunction "1_1") (pintype "passive"))
      (node (ref "A412") (pin "2") (pinfunction "2_2") (pintype "passive"))
      (node (ref "IC34") (pin "12") (pinfunction "12_12") (pintype "passive"))
    )
    (net (code "437") (name "Net-(A413-Pad1)") (class "Default")
      (node (ref "A413") (pin "1") (pinfunction "1_1") (pintype "passive"))
      (node (ref "A413") (pin "2") (pinfunction "2_2") (pintype "passive"))
      (node (ref "IC34") (pin "13") (pinfunction "13_13") (pintype "passive"))
    )
    (net (code "438") (name "Net-(A414-Pad1)") (class "Default")
      (node (ref "A414") (pin "1") (pinfunction "1_1") (pintype "passive"))
      (node (ref "A414") (pin "2") (pinfunction "2_2") (pintype "passive"))
      (node (ref "IC34") (pin "14") (pinfunction "14_14") (pintype "passive"))
    )
    (net (code "439") (name "Net-(A415-Pad1)") (class "Default")
      (node (ref "A415") (pin "1") (pinfunction "1_1") (pintype "passive"))
      (node (ref "A415") (pin "2") (pinfunction "2_2") (pintype "passive"))
      (node (ref "IC34") (pin "15") (pinfunction "15_15") (pintype "passive"))
    )
    (net (code "440") (name "Net-(A416-Pad1)") (class "Default")
      (node (ref "A416") (pin "1") (pinfunction "1_1") (pintype "passive"))
      (node (ref "A416") (pin "2") (pinfunction "2_2") (pintype "passive"))
      (node (ref "IC34") (pin "16") (pinfunction "16_16") (pintype "passive"))
    )
    (net (code "441") (name "Net-(A417-Pad1)") (class "Default")
      (node (ref "A417") (pin "1") (pinfunction "1_1") (pintype "passive"))
      (node (ref "A417") (pin "2") (pinfunction "2_2") (pintype "passive"))
      (node (ref "IC35") (pin "1") (pinfunction "1_1") (pintype "passive"))
    )
    (net (code "442") (name "Net-(A418-Pad1)") (class "Default")
      (node (ref "A418") (pin "1") (pinfunction "1_1") (pintype "passive"))
      (node (ref "A418") (pin "2") (pinfunction "2_2") (pintype "passive"))
      (node (ref "IC35") (pin "2") (pinfunction "2_2") (pintype "passive"))
    )
    (net (code "443") (name "Net-(A419-Pad1)") (class "Default")
      (node (ref "A419") (pin "1") (pinfunction "1_1") (pintype "passive"))
      (node (ref "A419") (pin "2") (pinfunction "2_2") (pintype "passive"))
      (node (ref "IC35") (pin "3") (pinfunction "3_3") (pintype "passive"))
    )
    (net (code "444") (name "Net-(A420-Pad1)") (class "Default")
      (node (ref "A420") (pin "1") (pinfunction "1_1") (pintype "passive"))
      (node (ref "A420") (pin "2") (pinfunction "2_2") (pintype "passive"))
      (node (ref "IC35") (pin "4") (pinfunction "4_4") (pintype "passive"))
    )
    (net (code "445") (name "Net-(A421-Pad1)") (class "Default")
      (node (ref "A421") (pin "1") (pinfunction "1_1") (pintype "passive"))
      (node (ref "A421") (pin "2") (pinfunction "2_2") (pintype "passive"))
      (node (ref "IC35") (pin "5") (pinfunction "5_5") (pintype "passive"))
    )
    (net (code "446") (name "Net-(A422-Pad1)") (class "Default")
      (node (ref "A422") (pin "1") (pinfunction "1_1") (pintype "passive"))
      (node (ref "A422") (pin "2") (pinfunction "2_2") (pintype "passive"))
      (node (ref "IC35") (pin "6") (pinfunction "6_6") (pintype "passive"))
    )
    (net (code "447") (name "Net-(A423-Pad1)") (class "Default")
      (node (ref "A423") (pin "1") (pinfunction "1_1") (pintype "passive"))
      (node (ref "A423") (pin "2") (pinfunction "2_2") (pintype "passive"))
      (node (ref "IC35") (pin "7") (pinfunction "7_7") (pintype "passive"))
    )
    (net (code "448") (name "Net-(A424-Pad1)") (class "Default")
      (node (ref "A424") (pin "1") (pinfunction "1_1") (pintype "passive"))
      (node (ref "A424") (pin "2") (pinfunction "2_2") (pintype "passive"))
      (node (ref "IC35") (pin "8") (pinfunction "8_8") (pintype "passive"))
    )
    (net (code "449") (name "Net-(A425-Pad1)") (class "Default")
      (node (ref "A425") (pin "1") (pinfunction "1_1") (pintype "passive"))
      (node (ref "A425") (pin "2") (pinfunction "2_2") (pintype "passive"))
      (node (ref "IC35") (pin "9") (pinfunction "9_9") (pintype "passive"))
    )
    (net (code "450") (name "Net-(A426-Pad1)") (class "Default")
      (node (ref "A426") (pin "1") (pinfunction "1_1") (pintype "passive"))
      (node (ref "A426") (pin "2") (pinfunction "2_2") (pintype "passive"))
      (node (ref "IC35") (pin "10") (pinfunction "10_10") (pintype "passive"))
    )
    (net (code "451") (name "Net-(A427-Pad1)") (class "Default")
      (node (ref "A427") (pin "1") (pinfunction "1_1") (pintype "passive"))
      (node (ref "A427") (pin "2") (pinfunction "2_2") (pintype "passive"))
      (node (ref "IC35") (pin "11") (pinfunction "11_11") (pintype "passive"))
    )
    (net (code "452") (name "Net-(A428-Pad1)") (class "Default")
      (node (ref "A428") (pin "1") (pinfunction "1_1") (pintype "passive"))
      (node (ref "A428") (pin "2") (pinfunction "2_2") (pintype "passive"))
      (node (ref "IC35") (pin "12") (pinfunction "12_12") (pintype "passive"))
    )
    (net (code "453") (name "Net-(A429-Pad1)") (class "Default")
      (node (ref "A429") (pin "1") (pinfunction "1_1") (pintype "passive"))
      (node (ref "A429") (pin "2") (pinfunction "2_2") (pintype "passive"))
      (node (ref "IC35") (pin "13") (pinfunction "13_13") (pintype "passive"))
    )
    (net (code "454") (name "Net-(A430-Pad1)") (class "Default")
      (node (ref "A430") (pin "1") (pinfunction "1_1") (pintype "passive"))
      (node (ref "A430") (pin "2") (pinfunction "2_2") (pintype "passive"))
      (node (ref "IC35") (pin "14") (pinfunction "14_14") (pintype "passive"))
    )
    (net (code "455") (name "Net-(A431-Pad1)") (class "Default")
      (node (ref "A431") (pin "1") (pinfunction "1_1") (pintype "passive"))
      (node (ref "A431") (pin "2") (pinfunction "2_2") (pintype "passive"))
      (node (ref "IC35") (pin "15") (pinfunction "15_15") (pintype "passive"))
    )
    (net (code "456") (name "Net-(A432-Pad1)") (class "Default")
      (node (ref "A432") (pin "1") (pinfunction "1_1") (pintype "passive"))
      (node (ref "A432") (pin "2") (pinfunction "2_2") (pintype "passive"))
      (node (ref "IC35") (pin "16") (pinfunction "16_16") (pintype "passive"))
    )
    (net (code "457") (name "Net-(A433-Pad1)") (class "Default")
      (node (ref "A433") (pin "1") (pinfunction "1_1") (pintype "passive"))
      (node (ref "A433") (pin "2") (pinfunction "2_2") (pintype "passive"))
      (node (ref "IC36") (pin "1") (pinfunction "1_1") (pintype "passive"))
    )
    (net (code "458") (name "Net-(A434-Pad1)") (class "Default")
      (node (ref "A434") (pin "1") (pinfunction "1_1") (pintype "passive"))
      (node (ref "A434") (pin "2") (pinfunction "2_2") (pintype "passive"))
      (node (ref "IC36") (pin "2") (pinfunction "2_2") (pintype "passive"))
    )
    (net (code "459") (name "Net-(A435-Pad1)") (class "Default")
      (node (ref "A435") (pin "1") (pinfunction "1_1") (pintype "passive"))
      (node (ref "A435") (pin "2") (pinfunction "2_2") (pintype "passive"))
      (node (ref "IC36") (pin "3") (pinfunction "3_3") (pintype "passive"))
    )
    (net (code "460") (name "Net-(A436-Pad1)") (class "Default")
      (node (ref "A436") (pin "1") (pinfunction "1_1") (pintype "passive"))
      (node (ref "A436") (pin "2") (pinfunction "2_2") (pintype "passive"))
      (node (ref "IC36") (pin "4") (pinfunction "4_4") (pintype "passive"))
    )
    (net (code "461") (name "Net-(A437-Pad1)") (class "Default")
      (node (ref "A437") (pin "1") (pinfunction "1_1") (pintype "passive"))
      (node (ref "A437") (pin "2") (pinfunction "2_2") (pintype "passive"))
      (node (ref "IC36") (pin "5") (pinfunction "5_5") (pintype "passive"))
    )
    (net (code "462") (name "Net-(A438-Pad1)") (class "Default")
      (node (ref "A438") (pin "1") (pinfunction "1_1") (pintype "passive"))
      (node (ref "A438") (pin "2") (pinfunction "2_2") (pintype "passive"))
      (node (ref "IC36") (pin "6") (pinfunction "6_6") (pintype "passive"))
    )
    (net (code "463") (name "Net-(A439-Pad1)") (class "Default")
      (node (ref "A439") (pin "1") (pinfunction "1_1") (pintype "passive"))
      (node (ref "A439") (pin "2") (pinfunction "2_2") (pintype "passive"))
      (node (ref "IC36") (pin "7") (pinfunction "7_7") (pintype "passive"))
    )
    (net (code "464") (name "Net-(A440-Pad1)") (class "Default")
      (node (ref "A440") (pin "1") (pinfunction "1_1") (pintype "passive"))
      (node (ref "A440") (pin "2") (pinfunction "2_2") (pintype "passive"))
      (node (ref "IC36") (pin "8") (pinfunction "8_8") (pintype "passive"))
    )
    (net (code "465") (name "Net-(A441-Pad1)") (class "Default")
      (node (ref "A441") (pin "1") (pinfunction "1_1") (pintype "passive"))
      (node (ref "A441") (pin "2") (pinfunction "2_2") (pintype "passive"))
      (node (ref "IC36") (pin "9") (pinfunction "9_9") (pintype "passive"))
    )
    (net (code "466") (name "Net-(A442-Pad1)") (class "Default")
      (node (ref "A442") (pin "1") (pinfunction "1_1") (pintype "passive"))
      (node (ref "A442") (pin "2") (pinfunction "2_2") (pintype "passive"))
      (node (ref "IC36") (pin "10") (pinfunction "10_10") (pintype "passive"))
    )
    (net (code "467") (name "Net-(A443-Pad1)") (class "Default")
      (node (ref "A443") (pin "1") (pinfunction "1_1") (pintype "passive"))
      (node (ref "A443") (pin "2") (pinfunction "2_2") (pintype "passive"))
      (node (ref "IC36") (pin "11") (pinfunction "11_11") (pintype "passive"))
    )
    (net (code "468") (name "Net-(A444-Pad1)") (class "Default")
      (node (ref "A444") (pin "1") (pinfunction "1_1") (pintype "passive"))
      (node (ref "A444") (pin "2") (pinfunction "2_2") (pintype "passive"))
      (node (ref "IC36") (pin "12") (pinfunction "12_12") (pintype "passive"))
    )
    (net (code "469") (name "Net-(A445-Pad1)") (class "Default")
      (node (ref "A445") (pin "1") (pinfunction "1_1") (pintype "passive"))
      (node (ref "A445") (pin "2") (pinfunction "2_2") (pintype "passive"))
      (node (ref "IC36") (pin "13") (pinfunction "13_13") (pintype "passive"))
    )
    (net (code "470") (name "Net-(A446-Pad1)") (class "Default")
      (node (ref "A446") (pin "1") (pinfunction "1_1") (pintype "passive"))
      (node (ref "A446") (pin "2") (pinfunction "2_2") (pintype "passive"))
      (node (ref "IC36") (pin "14") (pinfunction "14_14") (pintype "passive"))
    )
    (net (code "471") (name "Net-(A447-Pad1)") (class "Default")
      (node (ref "A447") (pin "1") (pinfunction "1_1") (pintype "passive"))
      (node (ref "A447") (pin "2") (pinfunction "2_2") (pintype "passive"))
      (node (ref "IC36") (pin "15") (pinfunction "15_15") (pintype "passive"))
    )
    (net (code "472") (name "Net-(A448-Pad1)") (class "Default")
      (node (ref "A448") (pin "1") (pinfunction "1_1") (pintype "passive"))
      (node (ref "A448") (pin "2") (pinfunction "2_2") (pintype "passive"))
      (node (ref "IC36") (pin "16") (pinfunction "16_16") (pintype "passive"))
    )
    (net (code "473") (name "Net-(B1-+-Pad+@1)") (class "Default")
      (node (ref "B1") (pin "+") (pinfunction "+_+") (pintype "passive"))
      (node (ref "B1") (pin "+@1") (pinfunction "+_+@1") (pintype "passive"))
      (node (ref "B1") (pin "+@2") (pinfunction "+_+@2") (pintype "passive"))
      (node (ref "B1") (pin "+@3") (pinfunction "+_+@3") (pintype "passive"))
      (node (ref "B1") (pin "+@4") (pinfunction "+_+@4") (pintype "passive"))
      (node (ref "D1") (pin "A") (pinfunction "A_A") (pintype "passive"))
    )
    (net (code "474") (name "Net-(IC2A-A5)") (class "Default")
      (node (ref "IC2") (pin "6") (pinfunction "A5_6") (pintype "bidirectional"))
      (node (ref "R4") (pin "2") (pinfunction "2_2") (pintype "passive"))
    )
    (net (code "475") (name "Net-(IC2A-A6)") (class "Default")
      (node (ref "IC2") (pin "7") (pinfunction "A6_7") (pintype "bidirectional"))
      (node (ref "R3") (pin "2") (pinfunction "2_2") (pintype "passive"))
    )
    (net (code "476") (name "Net-(IC2A-A7)") (class "Default")
      (node (ref "IC2") (pin "8") (pinfunction "A7_8") (pintype "bidirectional"))
      (node (ref "R2") (pin "2") (pinfunction "2_2") (pintype "passive"))
    )
    (net (code "477") (name "Net-(IC2A-A8)") (class "Default")
      (node (ref "IC2") (pin "9") (pinfunction "A8_9") (pintype "bidirectional"))
      (node (ref "R1") (pin "2") (pinfunction "2_2") (pintype "passive"))
    )
    (net (code "478") (name "Net-(IC5A-Y0)") (class "Default")
      (node (ref "IC5") (pin "15") (pinfunction "Y0_15") (pintype "output"))
      (node (ref "S1") (pin "9") (pinfunction "9_9") (pintype "passive"))
    )
    (net (code "479") (name "Net-(IC5A-Y1)") (class "Default")
      (node (ref "IC5") (pin "14") (pinfunction "Y1_14") (pintype "output"))
      (node (ref "S1") (pin "10") (pinfunction "10_10") (pintype "passive"))
    )
    (net (code "480") (name "Net-(IC5A-Y2)") (class "Default")
      (node (ref "IC5") (pin "13") (pinfunction "Y2_13") (pintype "output"))
      (node (ref "S1") (pin "11") (pinfunction "11_11") (pintype "passive"))
    )
    (net (code "481") (name "Net-(IC5A-Y3)") (class "Default")
      (node (ref "IC5") (pin "12") (pinfunction "Y3_12") (pintype "output"))
      (node (ref "S1") (pin "12") (pinfunction "12_12") (pintype "passive"))
    )
    (net (code "482") (name "Net-(IC5A-Y4)") (class "Default")
      (node (ref "IC5") (pin "11") (pinfunction "Y4_11") (pintype "output"))
      (node (ref "S1") (pin "13") (pinfunction "13_13") (pintype "passive"))
    )
    (net (code "483") (name "Net-(IC5A-Y5)") (class "Default")
      (node (ref "IC5") (pin "10") (pinfunction "Y5_10") (pintype "output"))
      (node (ref "S1") (pin "14") (pinfunction "14_14") (pintype "passive"))
    )
    (net (code "484") (name "Net-(IC5A-Y6)") (class "Default")
      (node (ref "IC5") (pin "9") (pinfunction "Y6_9") (pintype "output"))
      (node (ref "S1") (pin "15") (pinfunction "15_15") (pintype "passive"))
    )
    (net (code "485") (name "Net-(IC5A-Y7)") (class "Default")
      (node (ref "IC5") (pin "7") (pinfunction "Y7_7") (pintype "output"))
      (node (ref "S1") (pin "16") (pinfunction "16_16") (pintype "passive"))
    )
    (net (code "486") (name "Net-(IC6A-I0)") (class "Default")
      (node (ref "IC6") (pin "1") (pinfunction "I0_1") (pintype "input"))
      (node (ref "R5") (pin "8") (pinfunction "1_8") (pintype "passive"))
      (node (ref "S1") (pin "1") (pinfunction "1_1") (pintype "passive"))
    )
    (net (code "487") (name "Net-(IC6A-I1)") (class "Default")
      (node (ref "IC6") (pin "2") (pinfunction "I1_2") (pintype "input"))
      (node (ref "R5") (pin "1") (pinfunction "1_1") (pintype "passive"))
      (node (ref "S1") (pin "8") (pinfunction "8_8") (pintype "passive"))
    )
    (net (code "488") (name "Net-(IC6A-I2)") (class "Default")
      (node (ref "IC6") (pin "3") (pinfunction "I2_3") (pintype "input"))
      (node (ref "R5") (pin "7") (pinfunction "1_7") (pintype "passive"))
      (node (ref "S1") (pin "2") (pinfunction "2_2") (pintype "passive"))
    )
    (net (code "489") (name "Net-(IC6A-I3)") (class "Default")
      (node (ref "IC6") (pin "4") (pinfunction "I3_4") (pintype "input"))
      (node (ref "R5") (pin "2") (pinfunction "1_2") (pintype "passive"))
      (node (ref "S1") (pin "7") (pinfunction "7_7") (pintype "passive"))
    )
    (net (code "490") (name "Net-(IC6A-I4)") (class "Default")
      (node (ref "IC6") (pin "5") (pinfunction "I4_5") (pintype "input"))
      (node (ref "R5") (pin "6") (pinfunction "1_6") (pintype "passive"))
      (node (ref "S1") (pin "3") (pinfunction "3_3") (pintype "passive"))
    )
    (net (code "491") (name "Net-(IC6A-I5)") (class "Default")
      (node (ref "IC6") (pin "6") (pinfunction "I5_6") (pintype "input"))
      (node (ref "R5") (pin "5") (pinfunction "1_5") (pintype "passive"))
      (node (ref "S1") (pin "4") (pinfunction "4_4") (pintype "passive"))
    )
    (net (code "492") (name "Net-(IC6A-I6)") (class "Default")
      (node (ref "IC6") (pin "11") (pinfunction "I6_11") (pintype "input"))
      (node (ref "R5") (pin "3") (pinfunction "1_3") (pintype "passive"))
      (node (ref "S1") (pin "6") (pinfunction "6_6") (pintype "passive"))
    )
    (net (code "493") (name "Net-(IC6A-I7)") (class "Default")
      (node (ref "IC6") (pin "12") (pinfunction "I7_12") (pintype "input"))
      (node (ref "R5") (pin "4") (pinfunction "1_4") (pintype "passive"))
      (node (ref "S1") (pin "5") (pinfunction "5_5") (pintype "passive"))
    )
    (net (code "494") (name "Net-(IC7A-I1)") (class "Default")
      (node (ref "IC7") (pin "2") (pinfunction "I1_2") (pintype "input"))
      (node (ref "IC8") (pin "13") (pinfunction "Y6_13") (pintype "tri_state"))
    )
    (net (code "495") (name "Net-(IC7A-I2)") (class "Default")
      (node (ref "IC7") (pin "4") (pinfunction "I2_4") (pintype "input"))
      (node (ref "IC8") (pin "15") (pinfunction "Y4_15") (pintype "tri_state"))
    )
    (net (code "496") (name "Net-(IC7A-I3)") (class "Default")
      (node (ref "IC7") (pin "5") (pinfunction "I3_5") (pintype "input"))
      (node (ref "IC8") (pin "17") (pinfunction "Y2_17") (pintype "tri_state"))
    )
    (net (code "497") (name "Net-(IC7B-I0)") (class "Default")
      (node (ref "IC7") (pin "9") (pinfunction "I0_9") (pintype "input"))
      (node (ref "IC8") (pin "18") (pinfunction "Y1_18") (pintype "tri_state"))
      (node (ref "IC8") (pin "3") (pinfunction "A2_3") (pintype "input"))
    )
    (net (code "498") (name "Net-(IC7B-I1)") (class "Default")
      (node (ref "IC7") (pin "10") (pinfunction "I1_10") (pintype "input"))
      (node (ref "IC8") (pin "12") (pinfunction "Y7_12") (pintype "tri_state"))
    )
    (net (code "499") (name "Net-(IC8A-A4)") (class "Default")
      (node (ref "IC8") (pin "16") (pinfunction "Y3_16") (pintype "tri_state"))
      (node (ref "IC8") (pin "5") (pinfunction "A4_5") (pintype "input"))
    )
    (net (code "500") (name "Net-(IC8A-A6)") (class "Default")
      (node (ref "IC8") (pin "14") (pinfunction "Y5_14") (pintype "tri_state"))
      (node (ref "IC8") (pin "7") (pinfunction "A6_7") (pintype "input"))
    )
    (net (code "501") (name "Net-(Q1-B)") (class "Default")
      (node (ref "Q1") (pin "2") (pinfunction "B_2") (pintype "passive"))
      (node (ref "R6") (pin "2") (pinfunction "2_2") (pintype "passive"))
    )
    (net (code "502") (name "Net-(SV1-Pad1)") (class "Default")
      (node (ref "SV1") (pin "1") (pinfunction "1_1") (pintype "passive"))
      (node (ref "SV1") (pin "3") (pinfunction "3_3") (pintype "passive"))
      (node (ref "SV1") (pin "5") (pinfunction "5_5") (pintype "passive"))
      (node (ref "SV1") (pin "7") (pinfunction "7_7") (pintype "passive"))
      (node (ref "SV1") (pin "9") (pinfunction "9_9") (pintype "passive"))
    )
    (net (code "503") (name "Net-(SV1-Pad10)") (class "Default")
      (node (ref "SV1") (pin "10") (pinfunction "10_10") (pintype "passive"))
      (node (ref "SV1") (pin "2") (pinfunction "2_2") (pintype "passive"))
      (node (ref "SV1") (pin "4") (pinfunction "4_4") (pintype "passive"))
      (node (ref "SV1") (pin "6") (pinfunction "6_6") (pintype "passive"))
      (node (ref "SV1") (pin "8") (pinfunction "8_8") (pintype "passive"))
    )
    (net (code "504") (name "Net-(SV2-Pad1)") (class "Default")
      (node (ref "SV2") (pin "1") (pinfunction "1_1") (pintype "passive"))
      (node (ref "SV2") (pin "3") (pinfunction "3_3") (pintype "passive"))
      (node (ref "SV2") (pin "5") (pinfunction "5_5") (pintype "passive"))
      (node (ref "SV2") (pin "7") (pinfunction "7_7") (pintype "passive"))
      (node (ref "SV2") (pin "9") (pinfunction "9_9") (pintype "passive"))
    )
    (net (code "505") (name "Net-(SV2-Pad10)") (class "Default")
      (node (ref "SV2") (pin "10") (pinfunction "10_10") (pintype "passive"))
      (node (ref "SV2") (pin "2") (pinfunction "2_2") (pintype "passive"))
      (node (ref "SV2") (pin "4") (pinfunction "4_4") (pintype "passive"))
      (node (ref "SV2") (pin "6") (pinfunction "6_6") (pintype "passive"))
      (node (ref "SV2") (pin "8") (pinfunction "8_8") (pintype "passive"))
    )
    (net (code "506") (name "Net-(SV7-Pad1)") (class "Default")
      (node (ref "SV7") (pin "1") (pinfunction "1_1") (pintype "passive"))
      (node (ref "SV7") (pin "3") (pinfunction "3_3") (pintype "passive"))
      (node (ref "SV7") (pin "5") (pinfunction "5_5") (pintype "passive"))
      (node (ref "SV7") (pin "7") (pinfunction "7_7") (pintype "passive"))
      (node (ref "SV7") (pin "9") (pinfunction "9_9") (pintype "passive"))
    )
    (net (code "507") (name "Net-(SV7-Pad10)") (class "Default")
      (node (ref "SV7") (pin "10") (pinfunction "10_10") (pintype "passive"))
      (node (ref "SV7") (pin "2") (pinfunction "2_2") (pintype "passive"))
      (node (ref "SV7") (pin "4") (pinfunction "4_4") (pintype "passive"))
      (node (ref "SV7") (pin "6") (pinfunction "6_6") (pintype "passive"))
      (node (ref "SV7") (pin "8") (pinfunction "8_8") (pintype "passive"))
    )
    (net (code "508") (name "Net-(SV8-Pad1)") (class "Default")
      (node (ref "SV8") (pin "1") (pinfunction "1_1") (pintype "passive"))
      (node (ref "SV8") (pin "3") (pinfunction "3_3") (pintype "passive"))
      (node (ref "SV8") (pin "5") (pinfunction "5_5") (pintype "passive"))
      (node (ref "SV8") (pin "7") (pinfunction "7_7") (pintype "passive"))
      (node (ref "SV8") (pin "9") (pinfunction "9_9") (pintype "passive"))
    )
    (net (code "509") (name "Net-(SV8-Pad10)") (class "Default")
      (node (ref "SV8") (pin "10") (pinfunction "10_10") (pintype "passive"))
      (node (ref "SV8") (pin "2") (pinfunction "2_2") (pintype "passive"))
      (node (ref "SV8") (pin "4") (pinfunction "4_4") (pintype "passive"))
      (node (ref "SV8") (pin "6") (pinfunction "6_6") (pintype "passive"))
      (node (ref "SV8") (pin "8") (pinfunction "8_8") (pintype "passive"))
    )
    (net (code "510") (name "Net-(SV13-Pad1)") (class "Default")
      (node (ref "SV13") (pin "1") (pinfunction "1_1") (pintype "passive"))
      (node (ref "SV13") (pin "3") (pinfunction "3_3") (pintype "passive"))
      (node (ref "SV13") (pin "5") (pinfunction "5_5") (pintype "passive"))
      (node (ref "SV13") (pin "7") (pinfunction "7_7") (pintype "passive"))
      (node (ref "SV13") (pin "9") (pinfunction "9_9") (pintype "passive"))
    )
    (net (code "511") (name "Net-(SV13-Pad10)") (class "Default")
      (node (ref "SV13") (pin "10") (pinfunction "10_10") (pintype "passive"))
      (node (ref "SV13") (pin "2") (pinfunction "2_2") (pintype "passive"))
      (node (ref "SV13") (pin "4") (pinfunction "4_4") (pintype "passive"))
      (node (ref "SV13") (pin "6") (pinfunction "6_6") (pintype "passive"))
      (node (ref "SV13") (pin "8") (pinfunction "8_8") (pintype "passive"))
    )
    (net (code "512") (name "Net-(SV14-Pad1)") (class "Default")
      (node (ref "SV14") (pin "1") (pinfunction "1_1") (pintype "passive"))
      (node (ref "SV14") (pin "3") (pinfunction "3_3") (pintype "passive"))
      (node (ref "SV14") (pin "5") (pinfunction "5_5") (pintype "passive"))
      (node (ref "SV14") (pin "7") (pinfunction "7_7") (pintype "passive"))
      (node (ref "SV14") (pin "9") (pinfunction "9_9") (pintype "passive"))
    )
    (net (code "513") (name "Net-(SV14-Pad10)") (class "Default")
      (node (ref "SV14") (pin "10") (pinfunction "10_10") (pintype "passive"))
      (node (ref "SV14") (pin "2") (pinfunction "2_2") (pintype "passive"))
      (node (ref "SV14") (pin "4") (pinfunction "4_4") (pintype "passive"))
      (node (ref "SV14") (pin "6") (pinfunction "6_6") (pintype "passive"))
      (node (ref "SV14") (pin "8") (pinfunction "8_8") (pintype "passive"))
    )
    (net (code "514") (name "Net-(SV15-Pad1)") (class "Default")
      (node (ref "SV15") (pin "1") (pinfunction "1_1") (pintype "passive"))
      (node (ref "SV15") (pin "3") (pinfunction "3_3") (pintype "passive"))
      (node (ref "SV15") (pin "5") (pinfunction "5_5") (pintype "passive"))
      (node (ref "SV15") (pin "7") (pinfunction "7_7") (pintype "passive"))
      (node (ref "SV15") (pin "9") (pinfunction "9_9") (pintype "passive"))
    )
    (net (code "515") (name "Net-(SV15-Pad10)") (class "Default")
      (node (ref "SV15") (pin "10") (pinfunction "10_10") (pintype "passive"))
      (node (ref "SV15") (pin "2") (pinfunction "2_2") (pintype "passive"))
      (node (ref "SV15") (pin "4") (pinfunction "4_4") (pintype "passive"))
      (node (ref "SV15") (pin "6") (pinfunction "6_6") (pintype "passive"))
      (node (ref "SV15") (pin "8") (pinfunction "8_8") (pintype "passive"))
    )
    (net (code "516") (name "Net-(SV16-Pad1)") (class "Default")
      (node (ref "SV16") (pin "1") (pinfunction "1_1") (pintype "passive"))
      (node (ref "SV16") (pin "3") (pinfunction "3_3") (pintype "passive"))
      (node (ref "SV16") (pin "5") (pinfunction "5_5") (pintype "passive"))
      (node (ref "SV16") (pin "7") (pinfunction "7_7") (pintype "passive"))
      (node (ref "SV16") (pin "9") (pinfunction "9_9") (pintype "passive"))
    )
    (net (code "517") (name "Net-(SV16-Pad10)") (class "Default")
      (node (ref "SV16") (pin "10") (pinfunction "10_10") (pintype "passive"))
      (node (ref "SV16") (pin "2") (pinfunction "2_2") (pintype "passive"))
      (node (ref "SV16") (pin "4") (pinfunction "4_4") (pintype "passive"))
      (node (ref "SV16") (pin "6") (pinfunction "6_6") (pintype "passive"))
      (node (ref "SV16") (pin "8") (pinfunction "8_8") (pintype "passive"))
    )
    (net (code "518") (name "Net-(SV17-Pad1)") (class "Default")
      (node (ref "SV17") (pin "1") (pinfunction "1_1") (pintype "passive"))
      (node (ref "SV17") (pin "3") (pinfunction "3_3") (pintype "passive"))
      (node (ref "SV17") (pin "5") (pinfunction "5_5") (pintype "passive"))
      (node (ref "SV17") (pin "7") (pinfunction "7_7") (pintype "passive"))
      (node (ref "SV17") (pin "9") (pinfunction "9_9") (pintype "passive"))
    )
    (net (code "519") (name "Net-(SV17-Pad10)") (class "Default")
      (node (ref "SV17") (pin "10") (pinfunction "10_10") (pintype "passive"))
      (node (ref "SV17") (pin "2") (pinfunction "2_2") (pintype "passive"))
      (node (ref "SV17") (pin "4") (pinfunction "4_4") (pintype "passive"))
      (node (ref "SV17") (pin "6") (pinfunction "6_6") (pintype "passive"))
      (node (ref "SV17") (pin "8") (pinfunction "8_8") (pintype "passive"))
    )
    (net (code "520") (name "Net-(SV18-Pad1)") (class "Default")
      (node (ref "SV18") (pin "1") (pinfunction "1_1") (pintype "passive"))
      (node (ref "SV18") (pin "3") (pinfunction "3_3") (pintype "passive"))
      (node (ref "SV18") (pin "5") (pinfunction "5_5") (pintype "passive"))
      (node (ref "SV18") (pin "7") (pinfunction "7_7") (pintype "passive"))
      (node (ref "SV18") (pin "9") (pinfunction "9_9") (pintype "passive"))
    )
    (net (code "521") (name "Net-(SV18-Pad10)") (class "Default")
      (node (ref "SV18") (pin "10") (pinfunction "10_10") (pintype "passive"))
      (node (ref "SV18") (pin "2") (pinfunction "2_2") (pintype "passive"))
      (node (ref "SV18") (pin "4") (pinfunction "4_4") (pintype "passive"))
      (node (ref "SV18") (pin "6") (pinfunction "6_6") (pintype "passive"))
      (node (ref "SV18") (pin "8") (pinfunction "8_8") (pintype "passive"))
    )
    (net (code "522") (name "Net-(SV19-Pad1)") (class "Default")
      (node (ref "SV19") (pin "1") (pinfunction "1_1") (pintype "passive"))
      (node (ref "SV19") (pin "3") (pinfunction "3_3") (pintype "passive"))
      (node (ref "SV19") (pin "5") (pinfunction "5_5") (pintype "passive"))
      (node (ref "SV19") (pin "7") (pinfunction "7_7") (pintype "passive"))
      (node (ref "SV19") (pin "9") (pinfunction "9_9") (pintype "passive"))
    )
    (net (code "523") (name "Net-(SV19-Pad10)") (class "Default")
      (node (ref "SV19") (pin "10") (pinfunction "10_10") (pintype "passive"))
      (node (ref "SV19") (pin "2") (pinfunction "2_2") (pintype "passive"))
      (node (ref "SV19") (pin "4") (pinfunction "4_4") (pintype "passive"))
      (node (ref "SV19") (pin "6") (pinfunction "6_6") (pintype "passive"))
      (node (ref "SV19") (pin "8") (pinfunction "8_8") (pintype "passive"))
    )
    (net (code "524") (name "Net-(SV20-Pad1)") (class "Default")
      (node (ref "SV20") (pin "1") (pinfunction "1_1") (pintype "passive"))
      (node (ref "SV20") (pin "3") (pinfunction "3_3") (pintype "passive"))
      (node (ref "SV20") (pin "5") (pinfunction "5_5") (pintype "passive"))
      (node (ref "SV20") (pin "7") (pinfunction "7_7") (pintype "passive"))
      (node (ref "SV20") (pin "9") (pinfunction "9_9") (pintype "passive"))
    )
    (net (code "525") (name "Net-(SV20-Pad10)") (class "Default")
      (node (ref "SV20") (pin "10") (pinfunction "10_10") (pintype "passive"))
      (node (ref "SV20") (pin "2") (pinfunction "2_2") (pintype "passive"))
      (node (ref "SV20") (pin "4") (pinfunction "4_4") (pintype "passive"))
      (node (ref "SV20") (pin "6") (pinfunction "6_6") (pintype "passive"))
      (node (ref "SV20") (pin "8") (pinfunction "8_8") (pintype "passive"))
    )
    (net (code "526") (name "Net-(SV21-Pad1)") (class "Default")
      (node (ref "SV21") (pin "1") (pinfunction "1_1") (pintype "passive"))
      (node (ref "SV21") (pin "3") (pinfunction "3_3") (pintype "passive"))
      (node (ref "SV21") (pin "5") (pinfunction "5_5") (pintype "passive"))
      (node (ref "SV21") (pin "7") (pinfunction "7_7") (pintype "passive"))
      (node (ref "SV21") (pin "9") (pinfunction "9_9") (pintype "passive"))
    )
    (net (code "527") (name "Net-(SV21-Pad10)") (class "Default")
      (node (ref "SV21") (pin "10") (pinfunction "10_10") (pintype "passive"))
      (node (ref "SV21") (pin "2") (pinfunction "2_2") (pintype "passive"))
      (node (ref "SV21") (pin "4") (pinfunction "4_4") (pintype "passive"))
      (node (ref "SV21") (pin "6") (pinfunction "6_6") (pintype "passive"))
      (node (ref "SV21") (pin "8") (pinfunction "8_8") (pintype "passive"))
    )
    (net (code "528") (name "Net-(SV22-Pad1)") (class "Default")
      (node (ref "SV22") (pin "1") (pinfunction "1_1") (pintype "passive"))
      (node (ref "SV22") (pin "3") (pinfunction "3_3") (pintype "passive"))
      (node (ref "SV22") (pin "5") (pinfunction "5_5") (pintype "passive"))
      (node (ref "SV22") (pin "7") (pinfunction "7_7") (pintype "passive"))
      (node (ref "SV22") (pin "9") (pinfunction "9_9") (pintype "passive"))
    )
    (net (code "529") (name "Net-(SV22-Pad10)") (class "Default")
      (node (ref "SV22") (pin "10") (pinfunction "10_10") (pintype "passive"))
      (node (ref "SV22") (pin "2") (pinfunction "2_2") (pintype "passive"))
      (node (ref "SV22") (pin "4") (pinfunction "4_4") (pintype "passive"))
      (node (ref "SV22") (pin "6") (pinfunction "6_6") (pintype "passive"))
      (node (ref "SV22") (pin "8") (pinfunction "8_8") (pintype "passive"))
    )
    (net (code "530") (name "Net-(SV23-Pad1)") (class "Default")
      (node (ref "SV23") (pin "1") (pinfunction "1_1") (pintype "passive"))
      (node (ref "SV23") (pin "3") (pinfunction "3_3") (pintype "passive"))
      (node (ref "SV23") (pin "5") (pinfunction "5_5") (pintype "passive"))
      (node (ref "SV23") (pin "7") (pinfunction "7_7") (pintype "passive"))
      (node (ref "SV23") (pin "9") (pinfunction "9_9") (pintype "passive"))
    )
    (net (code "531") (name "Net-(SV23-Pad10)") (class "Default")
      (node (ref "SV23") (pin "10") (pinfunction "10_10") (pintype "passive"))
      (node (ref "SV23") (pin "2") (pinfunction "2_2") (pintype "passive"))
      (node (ref "SV23") (pin "4") (pinfunction "4_4") (pintype "passive"))
      (node (ref "SV23") (pin "6") (pinfunction "6_6") (pintype "passive"))
      (node (ref "SV23") (pin "8") (pinfunction "8_8") (pintype "passive"))
    )
    (net (code "532") (name "Net-(SV24-Pad1)") (class "Default")
      (node (ref "SV24") (pin "1") (pinfunction "1_1") (pintype "passive"))
      (node (ref "SV24") (pin "3") (pinfunction "3_3") (pintype "passive"))
      (node (ref "SV24") (pin "5") (pinfunction "5_5") (pintype "passive"))
      (node (ref "SV24") (pin "7") (pinfunction "7_7") (pintype "passive"))
      (node (ref "SV24") (pin "9") (pinfunction "9_9") (pintype "passive"))
    )
    (net (code "533") (name "Net-(SV24-Pad10)") (class "Default")
      (node (ref "SV24") (pin "10") (pinfunction "10_10") (pintype "passive"))
      (node (ref "SV24") (pin "2") (pinfunction "2_2") (pintype "passive"))
      (node (ref "SV24") (pin "4") (pinfunction "4_4") (pintype "passive"))
      (node (ref "SV24") (pin "6") (pinfunction "6_6") (pintype "passive"))
      (node (ref "SV24") (pin "8") (pinfunction "8_8") (pintype "passive"))
    )
    (net (code "534") (name "Net-(SV25-Pad1)") (class "Default")
      (node (ref "SV25") (pin "1") (pinfunction "1_1") (pintype "passive"))
      (node (ref "SV25") (pin "3") (pinfunction "3_3") (pintype "passive"))
      (node (ref "SV25") (pin "5") (pinfunction "5_5") (pintype "passive"))
      (node (ref "SV25") (pin "7") (pinfunction "7_7") (pintype "passive"))
      (node (ref "SV25") (pin "9") (pinfunction "9_9") (pintype "passive"))
    )
    (net (code "535") (name "Net-(SV25-Pad10)") (class "Default")
      (node (ref "SV25") (pin "10") (pinfunction "10_10") (pintype "passive"))
      (node (ref "SV25") (pin "2") (pinfunction "2_2") (pintype "passive"))
      (node (ref "SV25") (pin "4") (pinfunction "4_4") (pintype "passive"))
      (node (ref "SV25") (pin "6") (pinfunction "6_6") (pintype "passive"))
      (node (ref "SV25") (pin "8") (pinfunction "8_8") (pintype "passive"))
    )
    (net (code "536") (name "Net-(SV26-Pad1)") (class "Default")
      (node (ref "SV26") (pin "1") (pinfunction "1_1") (pintype "passive"))
      (node (ref "SV26") (pin "3") (pinfunction "3_3") (pintype "passive"))
      (node (ref "SV26") (pin "5") (pinfunction "5_5") (pintype "passive"))
      (node (ref "SV26") (pin "7") (pinfunction "7_7") (pintype "passive"))
      (node (ref "SV26") (pin "9") (pinfunction "9_9") (pintype "passive"))
    )
    (net (code "537") (name "Net-(SV26-Pad10)") (class "Default")
      (node (ref "SV26") (pin "10") (pinfunction "10_10") (pintype "passive"))
      (node (ref "SV26") (pin "2") (pinfunction "2_2") (pintype "passive"))
      (node (ref "SV26") (pin "4") (pinfunction "4_4") (pintype "passive"))
      (node (ref "SV26") (pin "6") (pinfunction "6_6") (pintype "passive"))
      (node (ref "SV26") (pin "8") (pinfunction "8_8") (pintype "passive"))
    )
    (net (code "538") (name "Net-(SV27-Pad1)") (class "Default")
      (node (ref "SV27") (pin "1") (pinfunction "1_1") (pintype "passive"))
      (node (ref "SV27") (pin "3") (pinfunction "3_3") (pintype "passive"))
      (node (ref "SV27") (pin "5") (pinfunction "5_5") (pintype "passive"))
      (node (ref "SV27") (pin "7") (pinfunction "7_7") (pintype "passive"))
      (node (ref "SV27") (pin "9") (pinfunction "9_9") (pintype "passive"))
    )
    (net (code "539") (name "Net-(SV27-Pad10)") (class "Default")
      (node (ref "SV27") (pin "10") (pinfunction "10_10") (pintype "passive"))
      (node (ref "SV27") (pin "2") (pinfunction "2_2") (pintype "passive"))
      (node (ref "SV27") (pin "4") (pinfunction "4_4") (pintype "passive"))
      (node (ref "SV27") (pin "6") (pinfunction "6_6") (pintype "passive"))
      (node (ref "SV27") (pin "8") (pinfunction "8_8") (pintype "passive"))
    )
    (net (code "540") (name "Net-(SV28-Pad1)") (class "Default")
      (node (ref "SV28") (pin "1") (pinfunction "1_1") (pintype "passive"))
      (node (ref "SV28") (pin "3") (pinfunction "3_3") (pintype "passive"))
      (node (ref "SV28") (pin "5") (pinfunction "5_5") (pintype "passive"))
      (node (ref "SV28") (pin "7") (pinfunction "7_7") (pintype "passive"))
      (node (ref "SV28") (pin "9") (pinfunction "9_9") (pintype "passive"))
    )
    (net (code "541") (name "Net-(SV28-Pad10)") (class "Default")
      (node (ref "SV28") (pin "10") (pinfunction "10_10") (pintype "passive"))
      (node (ref "SV28") (pin "2") (pinfunction "2_2") (pintype "passive"))
      (node (ref "SV28") (pin "4") (pinfunction "4_4") (pintype "passive"))
      (node (ref "SV28") (pin "6") (pinfunction "6_6") (pintype "passive"))
      (node (ref "SV28") (pin "8") (pinfunction "8_8") (pintype "passive"))
    )
    (net (code "542") (name "Net-(SV29-Pad1)") (class "Default")
      (node (ref "SV29") (pin "1") (pinfunction "1_1") (pintype "passive"))
      (node (ref "SV29") (pin "3") (pinfunction "3_3") (pintype "passive"))
      (node (ref "SV29") (pin "5") (pinfunction "5_5") (pintype "passive"))
      (node (ref "SV29") (pin "7") (pinfunction "7_7") (pintype "passive"))
      (node (ref "SV29") (pin "9") (pinfunction "9_9") (pintype "passive"))
    )
    (net (code "543") (name "Net-(SV29-Pad10)") (class "Default")
      (node (ref "SV29") (pin "10") (pinfunction "10_10") (pintype "passive"))
      (node (ref "SV29") (pin "2") (pinfunction "2_2") (pintype "passive"))
      (node (ref "SV29") (pin "4") (pinfunction "4_4") (pintype "passive"))
      (node (ref "SV29") (pin "6") (pinfunction "6_6") (pintype "passive"))
      (node (ref "SV29") (pin "8") (pinfunction "8_8") (pintype "passive"))
    )
    (net (code "544") (name "Net-(SV30-Pad1)") (class "Default")
      (node (ref "SV30") (pin "1") (pinfunction "1_1") (pintype "passive"))
      (node (ref "SV30") (pin "3") (pinfunction "3_3") (pintype "passive"))
      (node (ref "SV30") (pin "5") (pinfunction "5_5") (pintype "passive"))
      (node (ref "SV30") (pin "7") (pinfunction "7_7") (pintype "passive"))
      (node (ref "SV30") (pin "9") (pinfunction "9_9") (pintype "passive"))
    )
    (net (code "545") (name "Net-(SV30-Pad10)") (class "Default")
      (node (ref "SV30") (pin "10") (pinfunction "10_10") (pintype "passive"))
      (node (ref "SV30") (pin "2") (pinfunction "2_2") (pintype "passive"))
      (node (ref "SV30") (pin "4") (pinfunction "4_4") (pintype "passive"))
      (node (ref "SV30") (pin "6") (pinfunction "6_6") (pintype "passive"))
      (node (ref "SV30") (pin "8") (pinfunction "8_8") (pintype "passive"))
    )
    (net (code "546") (name "Net-(SV31-Pad1)") (class "Default")
      (node (ref "SV31") (pin "1") (pinfunction "1_1") (pintype "passive"))
      (node (ref "SV31") (pin "3") (pinfunction "3_3") (pintype "passive"))
      (node (ref "SV31") (pin "5") (pinfunction "5_5") (pintype "passive"))
      (node (ref "SV31") (pin "7") (pinfunction "7_7") (pintype "passive"))
      (node (ref "SV31") (pin "9") (pinfunction "9_9") (pintype "passive"))
    )
    (net (code "547") (name "Net-(SV31-Pad10)") (class "Default")
      (node (ref "SV31") (pin "10") (pinfunction "10_10") (pintype "passive"))
      (node (ref "SV31") (pin "2") (pinfunction "2_2") (pintype "passive"))
      (node (ref "SV31") (pin "4") (pinfunction "4_4") (pintype "passive"))
      (node (ref "SV31") (pin "6") (pinfunction "6_6") (pintype "passive"))
      (node (ref "SV31") (pin "8") (pinfunction "8_8") (pintype "passive"))
    )
    (net (code "548") (name "Net-(SV32-Pad1)") (class "Default")
      (node (ref "SV32") (pin "1") (pinfunction "1_1") (pintype "passive"))
      (node (ref "SV32") (pin "3") (pinfunction "3_3") (pintype "passive"))
      (node (ref "SV32") (pin "5") (pinfunction "5_5") (pintype "passive"))
      (node (ref "SV32") (pin "7") (pinfunction "7_7") (pintype "passive"))
      (node (ref "SV32") (pin "9") (pinfunction "9_9") (pintype "passive"))
    )
    (net (code "549") (name "Net-(SV32-Pad10)") (class "Default")
      (node (ref "SV32") (pin "10") (pinfunction "10_10") (pintype "passive"))
      (node (ref "SV32") (pin "2") (pinfunction "2_2") (pintype "passive"))
      (node (ref "SV32") (pin "4") (pinfunction "4_4") (pintype "passive"))
      (node (ref "SV32") (pin "6") (pinfunction "6_6") (pintype "passive"))
      (node (ref "SV32") (pin "8") (pinfunction "8_8") (pintype "passive"))
    )
    (net (code "550") (name "Net-(SV33-Pad1)") (class "Default")
      (node (ref "SV33") (pin "1") (pinfunction "1_1") (pintype "passive"))
      (node (ref "SV33") (pin "3") (pinfunction "3_3") (pintype "passive"))
      (node (ref "SV33") (pin "5") (pinfunction "5_5") (pintype "passive"))
      (node (ref "SV33") (pin "7") (pinfunction "7_7") (pintype "passive"))
      (node (ref "SV33") (pin "9") (pinfunction "9_9") (pintype "passive"))
    )
    (net (code "551") (name "Net-(SV33-Pad10)") (class "Default")
      (node (ref "SV33") (pin "10") (pinfunction "10_10") (pintype "passive"))
      (node (ref "SV33") (pin "2") (pinfunction "2_2") (pintype "passive"))
      (node (ref "SV33") (pin "4") (pinfunction "4_4") (pintype "passive"))
      (node (ref "SV33") (pin "6") (pinfunction "6_6") (pintype "passive"))
      (node (ref "SV33") (pin "8") (pinfunction "8_8") (pintype "passive"))
    )
    (net (code "552") (name "Net-(SV34-Pad1)") (class "Default")
      (node (ref "SV34") (pin "1") (pinfunction "1_1") (pintype "passive"))
      (node (ref "SV34") (pin "3") (pinfunction "3_3") (pintype "passive"))
      (node (ref "SV34") (pin "5") (pinfunction "5_5") (pintype "passive"))
      (node (ref "SV34") (pin "7") (pinfunction "7_7") (pintype "passive"))
      (node (ref "SV34") (pin "9") (pinfunction "9_9") (pintype "passive"))
    )
    (net (code "553") (name "Net-(SV34-Pad10)") (class "Default")
      (node (ref "SV34") (pin "10") (pinfunction "10_10") (pintype "passive"))
      (node (ref "SV34") (pin "2") (pinfunction "2_2") (pintype "passive"))
      (node (ref "SV34") (pin "4") (pinfunction "4_4") (pintype "passive"))
      (node (ref "SV34") (pin "6") (pinfunction "6_6") (pintype "passive"))
      (node (ref "SV34") (pin "8") (pinfunction "8_8") (pintype "passive"))
    )
    (net (code "554") (name "Net-(SV35-Pad1)") (class "Default")
      (node (ref "SV35") (pin "1") (pinfunction "1_1") (pintype "passive"))
      (node (ref "SV35") (pin "3") (pinfunction "3_3") (pintype "passive"))
      (node (ref "SV35") (pin "5") (pinfunction "5_5") (pintype "passive"))
      (node (ref "SV35") (pin "7") (pinfunction "7_7") (pintype "passive"))
      (node (ref "SV35") (pin "9") (pinfunction "9_9") (pintype "passive"))
    )
    (net (code "555") (name "Net-(SV35-Pad10)") (class "Default")
      (node (ref "SV35") (pin "10") (pinfunction "10_10") (pintype "passive"))
      (node (ref "SV35") (pin "2") (pinfunction "2_2") (pintype "passive"))
      (node (ref "SV35") (pin "4") (pinfunction "4_4") (pintype "passive"))
      (node (ref "SV35") (pin "6") (pinfunction "6_6") (pintype "passive"))
      (node (ref "SV35") (pin "8") (pinfunction "8_8") (pintype "passive"))
    )
    (net (code "556") (name "Net-(SV36-Pad1)") (class "Default")
      (node (ref "SV36") (pin "1") (pinfunction "1_1") (pintype "passive"))
      (node (ref "SV36") (pin "3") (pinfunction "3_3") (pintype "passive"))
      (node (ref "SV36") (pin "5") (pinfunction "5_5") (pintype "passive"))
      (node (ref "SV36") (pin "7") (pinfunction "7_7") (pintype "passive"))
      (node (ref "SV36") (pin "9") (pinfunction "9_9") (pintype "passive"))
    )
    (net (code "557") (name "Net-(SV36-Pad10)") (class "Default")
      (node (ref "SV36") (pin "10") (pinfunction "10_10") (pintype "passive"))
      (node (ref "SV36") (pin "2") (pinfunction "2_2") (pintype "passive"))
      (node (ref "SV36") (pin "4") (pinfunction "4_4") (pintype "passive"))
      (node (ref "SV36") (pin "6") (pinfunction "6_6") (pintype "passive"))
      (node (ref "SV36") (pin "8") (pinfunction "8_8") (pintype "passive"))
    )
    (net (code "558") (name "Net-(SV37-Pad1)") (class "Default")
      (node (ref "SV37") (pin "1") (pinfunction "1_1") (pintype "passive"))
      (node (ref "SV37") (pin "3") (pinfunction "3_3") (pintype "passive"))
      (node (ref "SV37") (pin "5") (pinfunction "5_5") (pintype "passive"))
      (node (ref "SV37") (pin "7") (pinfunction "7_7") (pintype "passive"))
      (node (ref "SV37") (pin "9") (pinfunction "9_9") (pintype "passive"))
    )
    (net (code "559") (name "Net-(SV37-Pad10)") (class "Default")
      (node (ref "SV37") (pin "10") (pinfunction "10_10") (pintype "passive"))
      (node (ref "SV37") (pin "2") (pinfunction "2_2") (pintype "passive"))
      (node (ref "SV37") (pin "4") (pinfunction "4_4") (pintype "passive"))
      (node (ref "SV37") (pin "6") (pinfunction "6_6") (pintype "passive"))
      (node (ref "SV37") (pin "8") (pinfunction "8_8") (pintype "passive"))
    )
    (net (code "560") (name "Net-(SV38-Pad1)") (class "Default")
      (node (ref "SV38") (pin "1") (pinfunction "1_1") (pintype "passive"))
      (node (ref "SV38") (pin "3") (pinfunction "3_3") (pintype "passive"))
      (node (ref "SV38") (pin "5") (pinfunction "5_5") (pintype "passive"))
      (node (ref "SV38") (pin "7") (pinfunction "7_7") (pintype "passive"))
      (node (ref "SV38") (pin "9") (pinfunction "9_9") (pintype "passive"))
    )
    (net (code "561") (name "Net-(SV38-Pad10)") (class "Default")
      (node (ref "SV38") (pin "10") (pinfunction "10_10") (pintype "passive"))
      (node (ref "SV38") (pin "2") (pinfunction "2_2") (pintype "passive"))
      (node (ref "SV38") (pin "4") (pinfunction "4_4") (pintype "passive"))
      (node (ref "SV38") (pin "6") (pinfunction "6_6") (pintype "passive"))
      (node (ref "SV38") (pin "8") (pinfunction "8_8") (pintype "passive"))
    )
    (net (code "562") (name "Net-(SV39-Pad1)") (class "Default")
      (node (ref "SV39") (pin "1") (pinfunction "1_1") (pintype "passive"))
      (node (ref "SV39") (pin "3") (pinfunction "3_3") (pintype "passive"))
      (node (ref "SV39") (pin "5") (pinfunction "5_5") (pintype "passive"))
      (node (ref "SV39") (pin "7") (pinfunction "7_7") (pintype "passive"))
      (node (ref "SV39") (pin "9") (pinfunction "9_9") (pintype "passive"))
    )
    (net (code "563") (name "Net-(SV39-Pad10)") (class "Default")
      (node (ref "SV39") (pin "10") (pinfunction "10_10") (pintype "passive"))
      (node (ref "SV39") (pin "2") (pinfunction "2_2") (pintype "passive"))
      (node (ref "SV39") (pin "4") (pinfunction "4_4") (pintype "passive"))
      (node (ref "SV39") (pin "6") (pinfunction "6_6") (pintype "passive"))
      (node (ref "SV39") (pin "8") (pinfunction "8_8") (pintype "passive"))
    )
    (net (code "564") (name "Net-(SV40-Pad1)") (class "Default")
      (node (ref "SV40") (pin "1") (pinfunction "1_1") (pintype "passive"))
      (node (ref "SV40") (pin "3") (pinfunction "3_3") (pintype "passive"))
      (node (ref "SV40") (pin "5") (pinfunction "5_5") (pintype "passive"))
      (node (ref "SV40") (pin "7") (pinfunction "7_7") (pintype "passive"))
      (node (ref "SV40") (pin "9") (pinfunction "9_9") (pintype "passive"))
    )
    (net (code "565") (name "Net-(SV40-Pad10)") (class "Default")
      (node (ref "SV40") (pin "10") (pinfunction "10_10") (pintype "passive"))
      (node (ref "SV40") (pin "2") (pinfunction "2_2") (pintype "passive"))
      (node (ref "SV40") (pin "4") (pinfunction "4_4") (pintype "passive"))
      (node (ref "SV40") (pin "6") (pinfunction "6_6") (pintype "passive"))
      (node (ref "SV40") (pin "8") (pinfunction "8_8") (pintype "passive"))
    )
    (net (code "566") (name "Net-(SV41-Pad1)") (class "Default")
      (node (ref "SV41") (pin "1") (pinfunction "1_1") (pintype "passive"))
      (node (ref "SV41") (pin "3") (pinfunction "3_3") (pintype "passive"))
      (node (ref "SV41") (pin "5") (pinfunction "5_5") (pintype "passive"))
      (node (ref "SV41") (pin "7") (pinfunction "7_7") (pintype "passive"))
      (node (ref "SV41") (pin "9") (pinfunction "9_9") (pintype "passive"))
    )
    (net (code "567") (name "Net-(SV41-Pad10)") (class "Default")
      (node (ref "SV41") (pin "10") (pinfunction "10_10") (pintype "passive"))
      (node (ref "SV41") (pin "2") (pinfunction "2_2") (pintype "passive"))
      (node (ref "SV41") (pin "4") (pinfunction "4_4") (pintype "passive"))
      (node (ref "SV41") (pin "6") (pinfunction "6_6") (pintype "passive"))
      (node (ref "SV41") (pin "8") (pinfunction "8_8") (pintype "passive"))
    )
    (net (code "568") (name "Net-(SV42-Pad1)") (class "Default")
      (node (ref "SV42") (pin "1") (pinfunction "1_1") (pintype "passive"))
      (node (ref "SV42") (pin "3") (pinfunction "3_3") (pintype "passive"))
      (node (ref "SV42") (pin "5") (pinfunction "5_5") (pintype "passive"))
      (node (ref "SV42") (pin "7") (pinfunction "7_7") (pintype "passive"))
      (node (ref "SV42") (pin "9") (pinfunction "9_9") (pintype "passive"))
    )
    (net (code "569") (name "Net-(SV42-Pad10)") (class "Default")
      (node (ref "SV42") (pin "10") (pinfunction "10_10") (pintype "passive"))
      (node (ref "SV42") (pin "2") (pinfunction "2_2") (pintype "passive"))
      (node (ref "SV42") (pin "4") (pinfunction "4_4") (pintype "passive"))
      (node (ref "SV42") (pin "6") (pinfunction "6_6") (pintype "passive"))
      (node (ref "SV42") (pin "8") (pinfunction "8_8") (pintype "passive"))
    )
    (net (code "570") (name "Net-(SV43-Pad1)") (class "Default")
      (node (ref "SV43") (pin "1") (pinfunction "1_1") (pintype "passive"))
      (node (ref "SV43") (pin "3") (pinfunction "3_3") (pintype "passive"))
      (node (ref "SV43") (pin "5") (pinfunction "5_5") (pintype "passive"))
      (node (ref "SV43") (pin "7") (pinfunction "7_7") (pintype "passive"))
      (node (ref "SV43") (pin "9") (pinfunction "9_9") (pintype "passive"))
    )
    (net (code "571") (name "Net-(SV43-Pad10)") (class "Default")
      (node (ref "SV43") (pin "10") (pinfunction "10_10") (pintype "passive"))
      (node (ref "SV43") (pin "2") (pinfunction "2_2") (pintype "passive"))
      (node (ref "SV43") (pin "4") (pinfunction "4_4") (pintype "passive"))
      (node (ref "SV43") (pin "6") (pinfunction "6_6") (pintype "passive"))
      (node (ref "SV43") (pin "8") (pinfunction "8_8") (pintype "passive"))
    )
    (net (code "572") (name "Net-(SV44-Pad1)") (class "Default")
      (node (ref "SV44") (pin "1") (pinfunction "1_1") (pintype "passive"))
      (node (ref "SV44") (pin "3") (pinfunction "3_3") (pintype "passive"))
      (node (ref "SV44") (pin "5") (pinfunction "5_5") (pintype "passive"))
      (node (ref "SV44") (pin "7") (pinfunction "7_7") (pintype "passive"))
      (node (ref "SV44") (pin "9") (pinfunction "9_9") (pintype "passive"))
    )
    (net (code "573") (name "Net-(SV44-Pad10)") (class "Default")
      (node (ref "SV44") (pin "10") (pinfunction "10_10") (pintype "passive"))
      (node (ref "SV44") (pin "2") (pinfunction "2_2") (pintype "passive"))
      (node (ref "SV44") (pin "4") (pinfunction "4_4") (pintype "passive"))
      (node (ref "SV44") (pin "6") (pinfunction "6_6") (pintype "passive"))
      (node (ref "SV44") (pin "8") (pinfunction "8_8") (pintype "passive"))
    )
    (net (code "574") (name "Net-(SV45-Pad1)") (class "Default")
      (node (ref "SV45") (pin "1") (pinfunction "1_1") (pintype "passive"))
      (node (ref "SV45") (pin "3") (pinfunction "3_3") (pintype "passive"))
      (node (ref "SV45") (pin "5") (pinfunction "5_5") (pintype "passive"))
      (node (ref "SV45") (pin "7") (pinfunction "7_7") (pintype "passive"))
      (node (ref "SV45") (pin "9") (pinfunction "9_9") (pintype "passive"))
    )
    (net (code "575") (name "Net-(SV45-Pad10)") (class "Default")
      (node (ref "SV45") (pin "10") (pinfunction "10_10") (pintype "passive"))
      (node (ref "SV45") (pin "2") (pinfunction "2_2") (pintype "passive"))
      (node (ref "SV45") (pin "4") (pinfunction "4_4") (pintype "passive"))
      (node (ref "SV45") (pin "6") (pinfunction "6_6") (pintype "passive"))
      (node (ref "SV45") (pin "8") (pinfunction "8_8") (pintype "passive"))
    )
    (net (code "576") (name "Net-(SV46-Pad1)") (class "Default")
      (node (ref "SV46") (pin "1") (pinfunction "1_1") (pintype "passive"))
      (node (ref "SV46") (pin "3") (pinfunction "3_3") (pintype "passive"))
      (node (ref "SV46") (pin "5") (pinfunction "5_5") (pintype "passive"))
      (node (ref "SV46") (pin "7") (pinfunction "7_7") (pintype "passive"))
      (node (ref "SV46") (pin "9") (pinfunction "9_9") (pintype "passive"))
    )
    (net (code "577") (name "Net-(SV46-Pad10)") (class "Default")
      (node (ref "SV46") (pin "10") (pinfunction "10_10") (pintype "passive"))
      (node (ref "SV46") (pin "2") (pinfunction "2_2") (pintype "passive"))
      (node (ref "SV46") (pin "4") (pinfunction "4_4") (pintype "passive"))
      (node (ref "SV46") (pin "6") (pinfunction "6_6") (pintype "passive"))
      (node (ref "SV46") (pin "8") (pinfunction "8_8") (pintype "passive"))
    )
    (net (code "578") (name "Net-(SV47-Pad1)") (class "Default")
      (node (ref "SV47") (pin "1") (pinfunction "1_1") (pintype "passive"))
      (node (ref "SV47") (pin "3") (pinfunction "3_3") (pintype "passive"))
      (node (ref "SV47") (pin "5") (pinfunction "5_5") (pintype "passive"))
      (node (ref "SV47") (pin "7") (pinfunction "7_7") (pintype "passive"))
      (node (ref "SV47") (pin "9") (pinfunction "9_9") (pintype "passive"))
    )
    (net (code "579") (name "Net-(SV47-Pad10)") (class "Default")
      (node (ref "SV47") (pin "10") (pinfunction "10_10") (pintype "passive"))
      (node (ref "SV47") (pin "2") (pinfunction "2_2") (pintype "passive"))
      (node (ref "SV47") (pin "4") (pinfunction "4_4") (pintype "passive"))
      (node (ref "SV47") (pin "6") (pinfunction "6_6") (pintype "passive"))
      (node (ref "SV47") (pin "8") (pinfunction "8_8") (pintype "passive"))
    )
    (net (code "580") (name "Net-(SV48-Pad1)") (class "Default")
      (node (ref "SV48") (pin "1") (pinfunction "1_1") (pintype "passive"))
      (node (ref "SV48") (pin "3") (pinfunction "3_3") (pintype "passive"))
      (node (ref "SV48") (pin "5") (pinfunction "5_5") (pintype "passive"))
      (node (ref "SV48") (pin "7") (pinfunction "7_7") (pintype "passive"))
      (node (ref "SV48") (pin "9") (pinfunction "9_9") (pintype "passive"))
    )
    (net (code "581") (name "Net-(SV48-Pad10)") (class "Default")
      (node (ref "SV48") (pin "10") (pinfunction "10_10") (pintype "passive"))
      (node (ref "SV48") (pin "2") (pinfunction "2_2") (pintype "passive"))
      (node (ref "SV48") (pin "4") (pinfunction "4_4") (pintype "passive"))
      (node (ref "SV48") (pin "6") (pinfunction "6_6") (pintype "passive"))
      (node (ref "SV48") (pin "8") (pinfunction "8_8") (pintype "passive"))
    )
    (net (code "582") (name "Net-(SV49-Pad1)") (class "Default")
      (node (ref "SV49") (pin "1") (pinfunction "1_1") (pintype "passive"))
      (node (ref "SV49") (pin "3") (pinfunction "3_3") (pintype "passive"))
      (node (ref "SV49") (pin "5") (pinfunction "5_5") (pintype "passive"))
      (node (ref "SV49") (pin "7") (pinfunction "7_7") (pintype "passive"))
      (node (ref "SV49") (pin "9") (pinfunction "9_9") (pintype "passive"))
    )
    (net (code "583") (name "Net-(SV49-Pad10)") (class "Default")
      (node (ref "SV49") (pin "10") (pinfunction "10_10") (pintype "passive"))
      (node (ref "SV49") (pin "2") (pinfunction "2_2") (pintype "passive"))
      (node (ref "SV49") (pin "4") (pinfunction "4_4") (pintype "passive"))
      (node (ref "SV49") (pin "6") (pinfunction "6_6") (pintype "passive"))
      (node (ref "SV49") (pin "8") (pinfunction "8_8") (pintype "passive"))
    )
    (net (code "584") (name "Net-(SV50-Pad1)") (class "Default")
      (node (ref "SV50") (pin "1") (pinfunction "1_1") (pintype "passive"))
      (node (ref "SV50") (pin "3") (pinfunction "3_3") (pintype "passive"))
      (node (ref "SV50") (pin "5") (pinfunction "5_5") (pintype "passive"))
      (node (ref "SV50") (pin "7") (pinfunction "7_7") (pintype "passive"))
      (node (ref "SV50") (pin "9") (pinfunction "9_9") (pintype "passive"))
    )
    (net (code "585") (name "Net-(SV50-Pad10)") (class "Default")
      (node (ref "SV50") (pin "10") (pinfunction "10_10") (pintype "passive"))
      (node (ref "SV50") (pin "2") (pinfunction "2_2") (pintype "passive"))
      (node (ref "SV50") (pin "4") (pinfunction "4_4") (pintype "passive"))
      (node (ref "SV50") (pin "6") (pinfunction "6_6") (pintype "passive"))
      (node (ref "SV50") (pin "8") (pinfunction "8_8") (pintype "passive"))
    )
    (net (code "586") (name "Net-(SV51-Pad1)") (class "Default")
      (node (ref "SV51") (pin "1") (pinfunction "1_1") (pintype "passive"))
      (node (ref "SV51") (pin "3") (pinfunction "3_3") (pintype "passive"))
      (node (ref "SV51") (pin "5") (pinfunction "5_5") (pintype "passive"))
      (node (ref "SV51") (pin "7") (pinfunction "7_7") (pintype "passive"))
      (node (ref "SV51") (pin "9") (pinfunction "9_9") (pintype "passive"))
    )
    (net (code "587") (name "Net-(SV51-Pad10)") (class "Default")
      (node (ref "SV51") (pin "10") (pinfunction "10_10") (pintype "passive"))
      (node (ref "SV51") (pin "2") (pinfunction "2_2") (pintype "passive"))
      (node (ref "SV51") (pin "4") (pinfunction "4_4") (pintype "passive"))
      (node (ref "SV51") (pin "6") (pinfunction "6_6") (pintype "passive"))
      (node (ref "SV51") (pin "8") (pinfunction "8_8") (pintype "passive"))
    )
    (net (code "588") (name "Net-(SV52-Pad1)") (class "Default")
      (node (ref "SV52") (pin "1") (pinfunction "1_1") (pintype "passive"))
      (node (ref "SV52") (pin "3") (pinfunction "3_3") (pintype "passive"))
      (node (ref "SV52") (pin "5") (pinfunction "5_5") (pintype "passive"))
      (node (ref "SV52") (pin "7") (pinfunction "7_7") (pintype "passive"))
      (node (ref "SV52") (pin "9") (pinfunction "9_9") (pintype "passive"))
    )
    (net (code "589") (name "Net-(SV52-Pad10)") (class "Default")
      (node (ref "SV52") (pin "10") (pinfunction "10_10") (pintype "passive"))
      (node (ref "SV52") (pin "2") (pinfunction "2_2") (pintype "passive"))
      (node (ref "SV52") (pin "4") (pinfunction "4_4") (pintype "passive"))
      (node (ref "SV52") (pin "6") (pinfunction "6_6") (pintype "passive"))
      (node (ref "SV52") (pin "8") (pinfunction "8_8") (pintype "passive"))
    )
    (net (code "590") (name "Net-(SV53-Pad1)") (class "Default")
      (node (ref "SV53") (pin "1") (pinfunction "1_1") (pintype "passive"))
      (node (ref "SV53") (pin "3") (pinfunction "3_3") (pintype "passive"))
      (node (ref "SV53") (pin "5") (pinfunction "5_5") (pintype "passive"))
      (node (ref "SV53") (pin "7") (pinfunction "7_7") (pintype "passive"))
      (node (ref "SV53") (pin "9") (pinfunction "9_9") (pintype "passive"))
    )
    (net (code "591") (name "Net-(SV53-Pad10)") (class "Default")
      (node (ref "SV53") (pin "10") (pinfunction "10_10") (pintype "passive"))
      (node (ref "SV53") (pin "2") (pinfunction "2_2") (pintype "passive"))
      (node (ref "SV53") (pin "4") (pinfunction "4_4") (pintype "passive"))
      (node (ref "SV53") (pin "6") (pinfunction "6_6") (pintype "passive"))
      (node (ref "SV53") (pin "8") (pinfunction "8_8") (pintype "passive"))
    )
    (net (code "592") (name "Net-(SV54-Pad1)") (class "Default")
      (node (ref "SV54") (pin "1") (pinfunction "1_1") (pintype "passive"))
      (node (ref "SV54") (pin "3") (pinfunction "3_3") (pintype "passive"))
      (node (ref "SV54") (pin "5") (pinfunction "5_5") (pintype "passive"))
      (node (ref "SV54") (pin "7") (pinfunction "7_7") (pintype "passive"))
      (node (ref "SV54") (pin "9") (pinfunction "9_9") (pintype "passive"))
    )
    (net (code "593") (name "Net-(SV54-Pad10)") (class "Default")
      (node (ref "SV54") (pin "10") (pinfunction "10_10") (pintype "passive"))
      (node (ref "SV54") (pin "2") (pinfunction "2_2") (pintype "passive"))
      (node (ref "SV54") (pin "4") (pinfunction "4_4") (pintype "passive"))
      (node (ref "SV54") (pin "6") (pinfunction "6_6") (pintype "passive"))
      (node (ref "SV54") (pin "8") (pinfunction "8_8") (pintype "passive"))
    )
    (net (code "594") (name "Net-(SV55-Pad1)") (class "Default")
      (node (ref "SV55") (pin "1") (pinfunction "1_1") (pintype "passive"))
      (node (ref "SV55") (pin "3") (pinfunction "3_3") (pintype "passive"))
      (node (ref "SV55") (pin "5") (pinfunction "5_5") (pintype "passive"))
      (node (ref "SV55") (pin "7") (pinfunction "7_7") (pintype "passive"))
      (node (ref "SV55") (pin "9") (pinfunction "9_9") (pintype "passive"))
    )
    (net (code "595") (name "Net-(SV55-Pad10)") (class "Default")
      (node (ref "SV55") (pin "10") (pinfunction "10_10") (pintype "passive"))
      (node (ref "SV55") (pin "2") (pinfunction "2_2") (pintype "passive"))
      (node (ref "SV55") (pin "4") (pinfunction "4_4") (pintype "passive"))
      (node (ref "SV55") (pin "6") (pinfunction "6_6") (pintype "passive"))
      (node (ref "SV55") (pin "8") (pinfunction "8_8") (pintype "passive"))
    )
    (net (code "596") (name "Net-(SV56-Pad1)") (class "Default")
      (node (ref "SV56") (pin "1") (pinfunction "1_1") (pintype "passive"))
      (node (ref "SV56") (pin "3") (pinfunction "3_3") (pintype "passive"))
      (node (ref "SV56") (pin "5") (pinfunction "5_5") (pintype "passive"))
      (node (ref "SV56") (pin "7") (pinfunction "7_7") (pintype "passive"))
      (node (ref "SV56") (pin "9") (pinfunction "9_9") (pintype "passive"))
    )
    (net (code "597") (name "Net-(SV56-Pad10)") (class "Default")
      (node (ref "SV56") (pin "10") (pinfunction "10_10") (pintype "passive"))
      (node (ref "SV56") (pin "2") (pinfunction "2_2") (pintype "passive"))
      (node (ref "SV56") (pin "4") (pinfunction "4_4") (pintype "passive"))
      (node (ref "SV56") (pin "6") (pinfunction "6_6") (pintype "passive"))
      (node (ref "SV56") (pin "8") (pinfunction "8_8") (pintype "passive"))
    )
    (net (code "598") (name "Net-(SV57-Pad1)") (class "Default")
      (node (ref "SV57") (pin "1") (pinfunction "1_1") (pintype "passive"))
      (node (ref "SV57") (pin "3") (pinfunction "3_3") (pintype "passive"))
      (node (ref "SV57") (pin "5") (pinfunction "5_5") (pintype "passive"))
      (node (ref "SV57") (pin "7") (pinfunction "7_7") (pintype "passive"))
      (node (ref "SV57") (pin "9") (pinfunction "9_9") (pintype "passive"))
    )
    (net (code "599") (name "Net-(SV57-Pad10)") (class "Default")
      (node (ref "SV57") (pin "10") (pinfunction "10_10") (pintype "passive"))
      (node (ref "SV57") (pin "2") (pinfunction "2_2") (pintype "passive"))
      (node (ref "SV57") (pin "4") (pinfunction "4_4") (pintype "passive"))
      (node (ref "SV57") (pin "6") (pinfunction "6_6") (pintype "passive"))
      (node (ref "SV57") (pin "8") (pinfunction "8_8") (pintype "passive"))
    )
    (net (code "600") (name "Net-(SV58-Pad1)") (class "Default")
      (node (ref "SV58") (pin "1") (pinfunction "1_1") (pintype "passive"))
      (node (ref "SV58") (pin "3") (pinfunction "3_3") (pintype "passive"))
      (node (ref "SV58") (pin "5") (pinfunction "5_5") (pintype "passive"))
      (node (ref "SV58") (pin "7") (pinfunction "7_7") (pintype "passive"))
      (node (ref "SV58") (pin "9") (pinfunction "9_9") (pintype "passive"))
    )
    (net (code "601") (name "Net-(SV58-Pad10)") (class "Default")
      (node (ref "SV58") (pin "10") (pinfunction "10_10") (pintype "passive"))
      (node (ref "SV58") (pin "2") (pinfunction "2_2") (pintype "passive"))
      (node (ref "SV58") (pin "4") (pinfunction "4_4") (pintype "passive"))
      (node (ref "SV58") (pin "6") (pinfunction "6_6") (pintype "passive"))
      (node (ref "SV58") (pin "8") (pinfunction "8_8") (pintype "passive"))
    )
    (net (code "602") (name "Net-(SV59-Pad1)") (class "Default")
      (node (ref "SV59") (pin "1") (pinfunction "1_1") (pintype "passive"))
      (node (ref "SV59") (pin "3") (pinfunction "3_3") (pintype "passive"))
      (node (ref "SV59") (pin "5") (pinfunction "5_5") (pintype "passive"))
      (node (ref "SV59") (pin "7") (pinfunction "7_7") (pintype "passive"))
      (node (ref "SV59") (pin "9") (pinfunction "9_9") (pintype "passive"))
    )
    (net (code "603") (name "Net-(SV59-Pad10)") (class "Default")
      (node (ref "SV59") (pin "10") (pinfunction "10_10") (pintype "passive"))
      (node (ref "SV59") (pin "2") (pinfunction "2_2") (pintype "passive"))
      (node (ref "SV59") (pin "4") (pinfunction "4_4") (pintype "passive"))
      (node (ref "SV59") (pin "6") (pinfunction "6_6") (pintype "passive"))
      (node (ref "SV59") (pin "8") (pinfunction "8_8") (pintype "passive"))
    )
    (net (code "604") (name "Net-(SV60-Pad1)") (class "Default")
      (node (ref "SV60") (pin "1") (pinfunction "1_1") (pintype "passive"))
      (node (ref "SV60") (pin "3") (pinfunction "3_3") (pintype "passive"))
      (node (ref "SV60") (pin "5") (pinfunction "5_5") (pintype "passive"))
      (node (ref "SV60") (pin "7") (pinfunction "7_7") (pintype "passive"))
      (node (ref "SV60") (pin "9") (pinfunction "9_9") (pintype "passive"))
    )
    (net (code "605") (name "Net-(SV60-Pad10)") (class "Default")
      (node (ref "SV60") (pin "10") (pinfunction "10_10") (pintype "passive"))
      (node (ref "SV60") (pin "2") (pinfunction "2_2") (pintype "passive"))
      (node (ref "SV60") (pin "4") (pinfunction "4_4") (pintype "passive"))
      (node (ref "SV60") (pin "6") (pinfunction "6_6") (pintype "passive"))
      (node (ref "SV60") (pin "8") (pinfunction "8_8") (pintype "passive"))
    )
    (net (code "606") (name "Net-(SV61-Pad1)") (class "Default")
      (node (ref "SV61") (pin "1") (pinfunction "1_1") (pintype "passive"))
      (node (ref "SV61") (pin "3") (pinfunction "3_3") (pintype "passive"))
      (node (ref "SV61") (pin "5") (pinfunction "5_5") (pintype "passive"))
      (node (ref "SV61") (pin "7") (pinfunction "7_7") (pintype "passive"))
      (node (ref "SV61") (pin "9") (pinfunction "9_9") (pintype "passive"))
    )
    (net (code "607") (name "Net-(SV61-Pad10)") (class "Default")
      (node (ref "SV61") (pin "10") (pinfunction "10_10") (pintype "passive"))
      (node (ref "SV61") (pin "2") (pinfunction "2_2") (pintype "passive"))
      (node (ref "SV61") (pin "4") (pinfunction "4_4") (pintype "passive"))
      (node (ref "SV61") (pin "6") (pinfunction "6_6") (pintype "passive"))
      (node (ref "SV61") (pin "8") (pinfunction "8_8") (pintype "passive"))
    )
    (net (code "608") (name "Net-(SV62-Pad1)") (class "Default")
      (node (ref "SV62") (pin "1") (pinfunction "1_1") (pintype "passive"))
      (node (ref "SV62") (pin "3") (pinfunction "3_3") (pintype "passive"))
      (node (ref "SV62") (pin "5") (pinfunction "5_5") (pintype "passive"))
      (node (ref "SV62") (pin "7") (pinfunction "7_7") (pintype "passive"))
      (node (ref "SV62") (pin "9") (pinfunction "9_9") (pintype "passive"))
    )
    (net (code "609") (name "Net-(SV62-Pad10)") (class "Default")
      (node (ref "SV62") (pin "10") (pinfunction "10_10") (pintype "passive"))
      (node (ref "SV62") (pin "2") (pinfunction "2_2") (pintype "passive"))
      (node (ref "SV62") (pin "4") (pinfunction "4_4") (pintype "passive"))
      (node (ref "SV62") (pin "6") (pinfunction "6_6") (pintype "passive"))
      (node (ref "SV62") (pin "8") (pinfunction "8_8") (pintype "passive"))
    )
    (net (code "610") (name "Net-(SV63-Pad1)") (class "Default")
      (node (ref "SV63") (pin "1") (pinfunction "1_1") (pintype "passive"))
      (node (ref "SV63") (pin "3") (pinfunction "3_3") (pintype "passive"))
      (node (ref "SV63") (pin "5") (pinfunction "5_5") (pintype "passive"))
      (node (ref "SV63") (pin "7") (pinfunction "7_7") (pintype "passive"))
      (node (ref "SV63") (pin "9") (pinfunction "9_9") (pintype "passive"))
    )
    (net (code "611") (name "Net-(SV63-Pad10)") (class "Default")
      (node (ref "SV63") (pin "10") (pinfunction "10_10") (pintype "passive"))
      (node (ref "SV63") (pin "2") (pinfunction "2_2") (pintype "passive"))
      (node (ref "SV63") (pin "4") (pinfunction "4_4") (pintype "passive"))
      (node (ref "SV63") (pin "6") (pinfunction "6_6") (pintype "passive"))
      (node (ref "SV63") (pin "8") (pinfunction "8_8") (pintype "passive"))
    )
    (net (code "612") (name "Net-(SV64-Pad1)") (class "Default")
      (node (ref "SV64") (pin "1") (pinfunction "1_1") (pintype "passive"))
      (node (ref "SV64") (pin "3") (pinfunction "3_3") (pintype "passive"))
      (node (ref "SV64") (pin "5") (pinfunction "5_5") (pintype "passive"))
      (node (ref "SV64") (pin "7") (pinfunction "7_7") (pintype "passive"))
      (node (ref "SV64") (pin "9") (pinfunction "9_9") (pintype "passive"))
    )
    (net (code "613") (name "Net-(SV64-Pad10)") (class "Default")
      (node (ref "SV64") (pin "10") (pinfunction "10_10") (pintype "passive"))
      (node (ref "SV64") (pin "2") (pinfunction "2_2") (pintype "passive"))
      (node (ref "SV64") (pin "4") (pinfunction "4_4") (pintype "passive"))
      (node (ref "SV64") (pin "6") (pinfunction "6_6") (pintype "passive"))
      (node (ref "SV64") (pin "8") (pinfunction "8_8") (pintype "passive"))
    )
    (net (code "614") (name "Net-(SV65-Pad1)") (class "Default")
      (node (ref "SV65") (pin "1") (pinfunction "1_1") (pintype "passive"))
      (node (ref "SV65") (pin "3") (pinfunction "3_3") (pintype "passive"))
      (node (ref "SV65") (pin "5") (pinfunction "5_5") (pintype "passive"))
      (node (ref "SV65") (pin "7") (pinfunction "7_7") (pintype "passive"))
      (node (ref "SV65") (pin "9") (pinfunction "9_9") (pintype "passive"))
    )
    (net (code "615") (name "Net-(SV65-Pad10)") (class "Default")
      (node (ref "SV65") (pin "10") (pinfunction "10_10") (pintype "passive"))
      (node (ref "SV65") (pin "2") (pinfunction "2_2") (pintype "passive"))
      (node (ref "SV65") (pin "4") (pinfunction "4_4") (pintype "passive"))
      (node (ref "SV65") (pin "6") (pinfunction "6_6") (pintype "passive"))
      (node (ref "SV65") (pin "8") (pinfunction "8_8") (pintype "passive"))
    )
    (net (code "616") (name "Net-(SV66-Pad1)") (class "Default")
      (node (ref "SV66") (pin "1") (pinfunction "1_1") (pintype "passive"))
      (node (ref "SV66") (pin "3") (pinfunction "3_3") (pintype "passive"))
      (node (ref "SV66") (pin "5") (pinfunction "5_5") (pintype "passive"))
      (node (ref "SV66") (pin "7") (pinfunction "7_7") (pintype "passive"))
      (node (ref "SV66") (pin "9") (pinfunction "9_9") (pintype "passive"))
    )
    (net (code "617") (name "Net-(SV66-Pad10)") (class "Default")
      (node (ref "SV66") (pin "10") (pinfunction "10_10") (pintype "passive"))
      (node (ref "SV66") (pin "2") (pinfunction "2_2") (pintype "passive"))
      (node (ref "SV66") (pin "4") (pinfunction "4_4") (pintype "passive"))
      (node (ref "SV66") (pin "6") (pinfunction "6_6") (pintype "passive"))
      (node (ref "SV66") (pin "8") (pinfunction "8_8") (pintype "passive"))
    )
    (net (code "618") (name "Net-(SV67-Pad1)") (class "Default")
      (node (ref "SV67") (pin "1") (pinfunction "1_1") (pintype "passive"))
      (node (ref "SV67") (pin "3") (pinfunction "3_3") (pintype "passive"))
      (node (ref "SV67") (pin "5") (pinfunction "5_5") (pintype "passive"))
      (node (ref "SV67") (pin "7") (pinfunction "7_7") (pintype "passive"))
      (node (ref "SV67") (pin "9") (pinfunction "9_9") (pintype "passive"))
    )
    (net (code "619") (name "Net-(SV67-Pad10)") (class "Default")
      (node (ref "SV67") (pin "10") (pinfunction "10_10") (pintype "passive"))
      (node (ref "SV67") (pin "2") (pinfunction "2_2") (pintype "passive"))
      (node (ref "SV67") (pin "4") (pinfunction "4_4") (pintype "passive"))
      (node (ref "SV67") (pin "6") (pinfunction "6_6") (pintype "passive"))
      (node (ref "SV67") (pin "8") (pinfunction "8_8") (pintype "passive"))
    )
    (net (code "620") (name "Net-(SV68-Pad1)") (class "Default")
      (node (ref "SV68") (pin "1") (pinfunction "1_1") (pintype "passive"))
      (node (ref "SV68") (pin "3") (pinfunction "3_3") (pintype "passive"))
      (node (ref "SV68") (pin "5") (pinfunction "5_5") (pintype "passive"))
      (node (ref "SV68") (pin "7") (pinfunction "7_7") (pintype "passive"))
      (node (ref "SV68") (pin "9") (pinfunction "9_9") (pintype "passive"))
    )
    (net (code "621") (name "Net-(SV68-Pad10)") (class "Default")
      (node (ref "SV68") (pin "10") (pinfunction "10_10") (pintype "passive"))
      (node (ref "SV68") (pin "2") (pinfunction "2_2") (pintype "passive"))
      (node (ref "SV68") (pin "4") (pinfunction "4_4") (pintype "passive"))
      (node (ref "SV68") (pin "6") (pinfunction "6_6") (pintype "passive"))
      (node (ref "SV68") (pin "8") (pinfunction "8_8") (pintype "passive"))
    )
    (net (code "622") (name "Net-(SV69-Pad1)") (class "Default")
      (node (ref "SV69") (pin "1") (pinfunction "1_1") (pintype "passive"))
      (node (ref "SV69") (pin "3") (pinfunction "3_3") (pintype "passive"))
      (node (ref "SV69") (pin "5") (pinfunction "5_5") (pintype "passive"))
      (node (ref "SV69") (pin "7") (pinfunction "7_7") (pintype "passive"))
      (node (ref "SV69") (pin "9") (pinfunction "9_9") (pintype "passive"))
    )
    (net (code "623") (name "Net-(SV69-Pad10)") (class "Default")
      (node (ref "SV69") (pin "10") (pinfunction "10_10") (pintype "passive"))
      (node (ref "SV69") (pin "2") (pinfunction "2_2") (pintype "passive"))
      (node (ref "SV69") (pin "4") (pinfunction "4_4") (pintype "passive"))
      (node (ref "SV69") (pin "6") (pinfunction "6_6") (pintype "passive"))
      (node (ref "SV69") (pin "8") (pinfunction "8_8") (pintype "passive"))
    )
    (net (code "624") (name "Net-(SV70-Pad1)") (class "Default")
      (node (ref "SV70") (pin "1") (pinfunction "1_1") (pintype "passive"))
      (node (ref "SV70") (pin "3") (pinfunction "3_3") (pintype "passive"))
      (node (ref "SV70") (pin "5") (pinfunction "5_5") (pintype "passive"))
      (node (ref "SV70") (pin "7") (pinfunction "7_7") (pintype "passive"))
      (node (ref "SV70") (pin "9") (pinfunction "9_9") (pintype "passive"))
    )
    (net (code "625") (name "Net-(SV70-Pad10)") (class "Default")
      (node (ref "SV70") (pin "10") (pinfunction "10_10") (pintype "passive"))
      (node (ref "SV70") (pin "2") (pinfunction "2_2") (pintype "passive"))
      (node (ref "SV70") (pin "4") (pinfunction "4_4") (pintype "passive"))
      (node (ref "SV70") (pin "6") (pinfunction "6_6") (pintype "passive"))
      (node (ref "SV70") (pin "8") (pinfunction "8_8") (pintype "passive"))
    )
    (net (code "626") (name "Net-(SV71-Pad1)") (class "Default")
      (node (ref "SV71") (pin "1") (pinfunction "1_1") (pintype "passive"))
      (node (ref "SV71") (pin "3") (pinfunction "3_3") (pintype "passive"))
      (node (ref "SV71") (pin "5") (pinfunction "5_5") (pintype "passive"))
      (node (ref "SV71") (pin "7") (pinfunction "7_7") (pintype "passive"))
      (node (ref "SV71") (pin "9") (pinfunction "9_9") (pintype "passive"))
    )
    (net (code "627") (name "Net-(SV71-Pad10)") (class "Default")
      (node (ref "SV71") (pin "10") (pinfunction "10_10") (pintype "passive"))
      (node (ref "SV71") (pin "2") (pinfunction "2_2") (pintype "passive"))
      (node (ref "SV71") (pin "4") (pinfunction "4_4") (pintype "passive"))
      (node (ref "SV71") (pin "6") (pinfunction "6_6") (pintype "passive"))
      (node (ref "SV71") (pin "8") (pinfunction "8_8") (pintype "passive"))
    )
    (net (code "628") (name "Net-(SV72-Pad1)") (class "Default")
      (node (ref "SV72") (pin "1") (pinfunction "1_1") (pintype "passive"))
      (node (ref "SV72") (pin "3") (pinfunction "3_3") (pintype "passive"))
      (node (ref "SV72") (pin "5") (pinfunction "5_5") (pintype "passive"))
      (node (ref "SV72") (pin "7") (pinfunction "7_7") (pintype "passive"))
      (node (ref "SV72") (pin "9") (pinfunction "9_9") (pintype "passive"))
    )
    (net (code "629") (name "Net-(SV72-Pad10)") (class "Default")
      (node (ref "SV72") (pin "10") (pinfunction "10_10") (pintype "passive"))
      (node (ref "SV72") (pin "2") (pinfunction "2_2") (pintype "passive"))
      (node (ref "SV72") (pin "4") (pinfunction "4_4") (pintype "passive"))
      (node (ref "SV72") (pin "6") (pinfunction "6_6") (pintype "passive"))
      (node (ref "SV72") (pin "8") (pinfunction "8_8") (pintype "passive"))
    )
    (net (code "630") (name "Net-(SV73-Pad1)") (class "Default")
      (node (ref "SV73") (pin "1") (pinfunction "1_1") (pintype "passive"))
      (node (ref "SV73") (pin "3") (pinfunction "3_3") (pintype "passive"))
      (node (ref "SV73") (pin "5") (pinfunction "5_5") (pintype "passive"))
      (node (ref "SV73") (pin "7") (pinfunction "7_7") (pintype "passive"))
      (node (ref "SV73") (pin "9") (pinfunction "9_9") (pintype "passive"))
    )
    (net (code "631") (name "Net-(SV73-Pad10)") (class "Default")
      (node (ref "SV73") (pin "10") (pinfunction "10_10") (pintype "passive"))
      (node (ref "SV73") (pin "2") (pinfunction "2_2") (pintype "passive"))
      (node (ref "SV73") (pin "4") (pinfunction "4_4") (pintype "passive"))
      (node (ref "SV73") (pin "6") (pinfunction "6_6") (pintype "passive"))
      (node (ref "SV73") (pin "8") (pinfunction "8_8") (pintype "passive"))
    )
    (net (code "632") (name "Net-(SV74-Pad1)") (class "Default")
      (node (ref "SV74") (pin "1") (pinfunction "1_1") (pintype "passive"))
      (node (ref "SV74") (pin "3") (pinfunction "3_3") (pintype "passive"))
      (node (ref "SV74") (pin "5") (pinfunction "5_5") (pintype "passive"))
      (node (ref "SV74") (pin "7") (pinfunction "7_7") (pintype "passive"))
      (node (ref "SV74") (pin "9") (pinfunction "9_9") (pintype "passive"))
    )
    (net (code "633") (name "Net-(SV74-Pad10)") (class "Default")
      (node (ref "SV74") (pin "10") (pinfunction "10_10") (pintype "passive"))
      (node (ref "SV74") (pin "2") (pinfunction "2_2") (pintype "passive"))
      (node (ref "SV74") (pin "4") (pinfunction "4_4") (pintype "passive"))
      (node (ref "SV74") (pin "6") (pinfunction "6_6") (pintype "passive"))
      (node (ref "SV74") (pin "8") (pinfunction "8_8") (pintype "passive"))
    )
    (net (code "634") (name "Net-(SV75-Pad1)") (class "Default")
      (node (ref "SV75") (pin "1") (pinfunction "1_1") (pintype "passive"))
      (node (ref "SV75") (pin "3") (pinfunction "3_3") (pintype "passive"))
      (node (ref "SV75") (pin "5") (pinfunction "5_5") (pintype "passive"))
      (node (ref "SV75") (pin "7") (pinfunction "7_7") (pintype "passive"))
      (node (ref "SV75") (pin "9") (pinfunction "9_9") (pintype "passive"))
    )
    (net (code "635") (name "Net-(SV75-Pad10)") (class "Default")
      (node (ref "SV75") (pin "10") (pinfunction "10_10") (pintype "passive"))
      (node (ref "SV75") (pin "2") (pinfunction "2_2") (pintype "passive"))
      (node (ref "SV75") (pin "4") (pinfunction "4_4") (pintype "passive"))
      (node (ref "SV75") (pin "6") (pinfunction "6_6") (pintype "passive"))
      (node (ref "SV75") (pin "8") (pinfunction "8_8") (pintype "passive"))
    )
    (net (code "636") (name "Net-(SV76-Pad1)") (class "Default")
      (node (ref "SV76") (pin "1") (pinfunction "1_1") (pintype "passive"))
      (node (ref "SV76") (pin "3") (pinfunction "3_3") (pintype "passive"))
      (node (ref "SV76") (pin "5") (pinfunction "5_5") (pintype "passive"))
      (node (ref "SV76") (pin "7") (pinfunction "7_7") (pintype "passive"))
      (node (ref "SV76") (pin "9") (pinfunction "9_9") (pintype "passive"))
    )
    (net (code "637") (name "Net-(SV76-Pad10)") (class "Default")
      (node (ref "SV76") (pin "10") (pinfunction "10_10") (pintype "passive"))
      (node (ref "SV76") (pin "2") (pinfunction "2_2") (pintype "passive"))
      (node (ref "SV76") (pin "4") (pinfunction "4_4") (pintype "passive"))
      (node (ref "SV76") (pin "6") (pinfunction "6_6") (pintype "passive"))
      (node (ref "SV76") (pin "8") (pinfunction "8_8") (pintype "passive"))
    )
    (net (code "638") (name "Net-(SV77-Pad1)") (class "Default")
      (node (ref "SV77") (pin "1") (pinfunction "1_1") (pintype "passive"))
      (node (ref "SV77") (pin "3") (pinfunction "3_3") (pintype "passive"))
      (node (ref "SV77") (pin "5") (pinfunction "5_5") (pintype "passive"))
      (node (ref "SV77") (pin "7") (pinfunction "7_7") (pintype "passive"))
      (node (ref "SV77") (pin "9") (pinfunction "9_9") (pintype "passive"))
    )
    (net (code "639") (name "Net-(SV77-Pad10)") (class "Default")
      (node (ref "SV77") (pin "10") (pinfunction "10_10") (pintype "passive"))
      (node (ref "SV77") (pin "2") (pinfunction "2_2") (pintype "passive"))
      (node (ref "SV77") (pin "4") (pinfunction "4_4") (pintype "passive"))
      (node (ref "SV77") (pin "6") (pinfunction "6_6") (pintype "passive"))
      (node (ref "SV77") (pin "8") (pinfunction "8_8") (pintype "passive"))
    )
    (net (code "640") (name "Net-(SV78-Pad1)") (class "Default")
      (node (ref "SV78") (pin "1") (pinfunction "1_1") (pintype "passive"))
      (node (ref "SV78") (pin "3") (pinfunction "3_3") (pintype "passive"))
      (node (ref "SV78") (pin "5") (pinfunction "5_5") (pintype "passive"))
      (node (ref "SV78") (pin "7") (pinfunction "7_7") (pintype "passive"))
      (node (ref "SV78") (pin "9") (pinfunction "9_9") (pintype "passive"))
    )
    (net (code "641") (name "Net-(SV78-Pad10)") (class "Default")
      (node (ref "SV78") (pin "10") (pinfunction "10_10") (pintype "passive"))
      (node (ref "SV78") (pin "2") (pinfunction "2_2") (pintype "passive"))
      (node (ref "SV78") (pin "4") (pinfunction "4_4") (pintype "passive"))
      (node (ref "SV78") (pin "6") (pinfunction "6_6") (pintype "passive"))
      (node (ref "SV78") (pin "8") (pinfunction "8_8") (pintype "passive"))
    )
    (net (code "642") (name "Net-(SV79-Pad1)") (class "Default")
      (node (ref "SV79") (pin "1") (pinfunction "1_1") (pintype "passive"))
      (node (ref "SV79") (pin "3") (pinfunction "3_3") (pintype "passive"))
      (node (ref "SV79") (pin "5") (pinfunction "5_5") (pintype "passive"))
      (node (ref "SV79") (pin "7") (pinfunction "7_7") (pintype "passive"))
      (node (ref "SV79") (pin "9") (pinfunction "9_9") (pintype "passive"))
    )
    (net (code "643") (name "Net-(SV79-Pad10)") (class "Default")
      (node (ref "SV79") (pin "10") (pinfunction "10_10") (pintype "passive"))
      (node (ref "SV79") (pin "2") (pinfunction "2_2") (pintype "passive"))
      (node (ref "SV79") (pin "4") (pinfunction "4_4") (pintype "passive"))
      (node (ref "SV79") (pin "6") (pinfunction "6_6") (pintype "passive"))
      (node (ref "SV79") (pin "8") (pinfunction "8_8") (pintype "passive"))
    )
    (net (code "644") (name "Net-(SV80-Pad1)") (class "Default")
      (node (ref "SV80") (pin "1") (pinfunction "1_1") (pintype "passive"))
      (node (ref "SV80") (pin "3") (pinfunction "3_3") (pintype "passive"))
      (node (ref "SV80") (pin "5") (pinfunction "5_5") (pintype "passive"))
      (node (ref "SV80") (pin "7") (pinfunction "7_7") (pintype "passive"))
      (node (ref "SV80") (pin "9") (pinfunction "9_9") (pintype "passive"))
    )
    (net (code "645") (name "Net-(SV80-Pad10)") (class "Default")
      (node (ref "SV80") (pin "10") (pinfunction "10_10") (pintype "passive"))
      (node (ref "SV80") (pin "2") (pinfunction "2_2") (pintype "passive"))
      (node (ref "SV80") (pin "4") (pinfunction "4_4") (pintype "passive"))
      (node (ref "SV80") (pin "6") (pinfunction "6_6") (pintype "passive"))
      (node (ref "SV80") (pin "8") (pinfunction "8_8") (pintype "passive"))
    )
    (net (code "646") (name "Net-(SV81-Pad1)") (class "Default")
      (node (ref "SV81") (pin "1") (pinfunction "1_1") (pintype "passive"))
      (node (ref "SV81") (pin "3") (pinfunction "3_3") (pintype "passive"))
      (node (ref "SV81") (pin "5") (pinfunction "5_5") (pintype "passive"))
      (node (ref "SV81") (pin "7") (pinfunction "7_7") (pintype "passive"))
      (node (ref "SV81") (pin "9") (pinfunction "9_9") (pintype "passive"))
    )
    (net (code "647") (name "Net-(SV81-Pad10)") (class "Default")
      (node (ref "SV81") (pin "10") (pinfunction "10_10") (pintype "passive"))
      (node (ref "SV81") (pin "2") (pinfunction "2_2") (pintype "passive"))
      (node (ref "SV81") (pin "4") (pinfunction "4_4") (pintype "passive"))
      (node (ref "SV81") (pin "6") (pinfunction "6_6") (pintype "passive"))
      (node (ref "SV81") (pin "8") (pinfunction "8_8") (pintype "passive"))
    )
    (net (code "648") (name "Net-(SV82-Pad1)") (class "Default")
      (node (ref "SV82") (pin "1") (pinfunction "1_1") (pintype "passive"))
      (node (ref "SV82") (pin "3") (pinfunction "3_3") (pintype "passive"))
      (node (ref "SV82") (pin "5") (pinfunction "5_5") (pintype "passive"))
      (node (ref "SV82") (pin "7") (pinfunction "7_7") (pintype "passive"))
      (node (ref "SV82") (pin "9") (pinfunction "9_9") (pintype "passive"))
    )
    (net (code "649") (name "Net-(SV82-Pad10)") (class "Default")
      (node (ref "SV82") (pin "10") (pinfunction "10_10") (pintype "passive"))
      (node (ref "SV82") (pin "2") (pinfunction "2_2") (pintype "passive"))
      (node (ref "SV82") (pin "4") (pinfunction "4_4") (pintype "passive"))
      (node (ref "SV82") (pin "6") (pinfunction "6_6") (pintype "passive"))
      (node (ref "SV82") (pin "8") (pinfunction "8_8") (pintype "passive"))
    )
    (net (code "650") (name "Net-(SV83-Pad1)") (class "Default")
      (node (ref "SV83") (pin "1") (pinfunction "1_1") (pintype "passive"))
      (node (ref "SV83") (pin "3") (pinfunction "3_3") (pintype "passive"))
      (node (ref "SV83") (pin "5") (pinfunction "5_5") (pintype "passive"))
      (node (ref "SV83") (pin "7") (pinfunction "7_7") (pintype "passive"))
      (node (ref "SV83") (pin "9") (pinfunction "9_9") (pintype "passive"))
    )
    (net (code "651") (name "Net-(SV83-Pad10)") (class "Default")
      (node (ref "SV83") (pin "10") (pinfunction "10_10") (pintype "passive"))
      (node (ref "SV83") (pin "2") (pinfunction "2_2") (pintype "passive"))
      (node (ref "SV83") (pin "4") (pinfunction "4_4") (pintype "passive"))
      (node (ref "SV83") (pin "6") (pinfunction "6_6") (pintype "passive"))
      (node (ref "SV83") (pin "8") (pinfunction "8_8") (pintype "passive"))
    )
    (net (code "652") (name "Net-(SV84-Pad1)") (class "Default")
      (node (ref "SV84") (pin "1") (pinfunction "1_1") (pintype "passive"))
      (node (ref "SV84") (pin "3") (pinfunction "3_3") (pintype "passive"))
      (node (ref "SV84") (pin "5") (pinfunction "5_5") (pintype "passive"))
      (node (ref "SV84") (pin "7") (pinfunction "7_7") (pintype "passive"))
      (node (ref "SV84") (pin "9") (pinfunction "9_9") (pintype "passive"))
    )
    (net (code "653") (name "Net-(SV84-Pad10)") (class "Default")
      (node (ref "SV84") (pin "10") (pinfunction "10_10") (pintype "passive"))
      (node (ref "SV84") (pin "2") (pinfunction "2_2") (pintype "passive"))
      (node (ref "SV84") (pin "4") (pinfunction "4_4") (pintype "passive"))
      (node (ref "SV84") (pin "6") (pinfunction "6_6") (pintype "passive"))
      (node (ref "SV84") (pin "8") (pinfunction "8_8") (pintype "passive"))
    )
    (net (code "654") (name "Net-(SV85-Pad1)") (class "Default")
      (node (ref "SV85") (pin "1") (pinfunction "1_1") (pintype "passive"))
      (node (ref "SV85") (pin "3") (pinfunction "3_3") (pintype "passive"))
      (node (ref "SV85") (pin "5") (pinfunction "5_5") (pintype "passive"))
      (node (ref "SV85") (pin "7") (pinfunction "7_7") (pintype "passive"))
      (node (ref "SV85") (pin "9") (pinfunction "9_9") (pintype "passive"))
    )
    (net (code "655") (name "Net-(SV85-Pad10)") (class "Default")
      (node (ref "SV85") (pin "10") (pinfunction "10_10") (pintype "passive"))
      (node (ref "SV85") (pin "2") (pinfunction "2_2") (pintype "passive"))
      (node (ref "SV85") (pin "4") (pinfunction "4_4") (pintype "passive"))
      (node (ref "SV85") (pin "6") (pinfunction "6_6") (pintype "passive"))
      (node (ref "SV85") (pin "8") (pinfunction "8_8") (pintype "passive"))
    )
    (net (code "656") (name "Net-(SV86-Pad1)") (class "Default")
      (node (ref "SV86") (pin "1") (pinfunction "1_1") (pintype "passive"))
      (node (ref "SV86") (pin "3") (pinfunction "3_3") (pintype "passive"))
      (node (ref "SV86") (pin "5") (pinfunction "5_5") (pintype "passive"))
      (node (ref "SV86") (pin "7") (pinfunction "7_7") (pintype "passive"))
      (node (ref "SV86") (pin "9") (pinfunction "9_9") (pintype "passive"))
    )
    (net (code "657") (name "Net-(SV86-Pad10)") (class "Default")
      (node (ref "SV86") (pin "10") (pinfunction "10_10") (pintype "passive"))
      (node (ref "SV86") (pin "2") (pinfunction "2_2") (pintype "passive"))
      (node (ref "SV86") (pin "4") (pinfunction "4_4") (pintype "passive"))
      (node (ref "SV86") (pin "6") (pinfunction "6_6") (pintype "passive"))
      (node (ref "SV86") (pin "8") (pinfunction "8_8") (pintype "passive"))
    )
    (net (code "658") (name "Net-(SV87-Pad1)") (class "Default")
      (node (ref "SV87") (pin "1") (pinfunction "1_1") (pintype "passive"))
      (node (ref "SV87") (pin "3") (pinfunction "3_3") (pintype "passive"))
      (node (ref "SV87") (pin "5") (pinfunction "5_5") (pintype "passive"))
      (node (ref "SV87") (pin "7") (pinfunction "7_7") (pintype "passive"))
      (node (ref "SV87") (pin "9") (pinfunction "9_9") (pintype "passive"))
    )
    (net (code "659") (name "Net-(SV87-Pad10)") (class "Default")
      (node (ref "SV87") (pin "10") (pinfunction "10_10") (pintype "passive"))
      (node (ref "SV87") (pin "2") (pinfunction "2_2") (pintype "passive"))
      (node (ref "SV87") (pin "4") (pinfunction "4_4") (pintype "passive"))
      (node (ref "SV87") (pin "6") (pinfunction "6_6") (pintype "passive"))
      (node (ref "SV87") (pin "8") (pinfunction "8_8") (pintype "passive"))
    )
    (net (code "660") (name "Net-(SV88-Pad1)") (class "Default")
      (node (ref "SV88") (pin "1") (pinfunction "1_1") (pintype "passive"))
      (node (ref "SV88") (pin "3") (pinfunction "3_3") (pintype "passive"))
      (node (ref "SV88") (pin "5") (pinfunction "5_5") (pintype "passive"))
      (node (ref "SV88") (pin "7") (pinfunction "7_7") (pintype "passive"))
      (node (ref "SV88") (pin "9") (pinfunction "9_9") (pintype "passive"))
    )
    (net (code "661") (name "Net-(SV88-Pad10)") (class "Default")
      (node (ref "SV88") (pin "10") (pinfunction "10_10") (pintype "passive"))
      (node (ref "SV88") (pin "2") (pinfunction "2_2") (pintype "passive"))
      (node (ref "SV88") (pin "4") (pinfunction "4_4") (pintype "passive"))
      (node (ref "SV88") (pin "6") (pinfunction "6_6") (pintype "passive"))
      (node (ref "SV88") (pin "8") (pinfunction "8_8") (pintype "passive"))
    )
    (net (code "662") (name "Net-(SV89-Pad1)") (class "Default")
      (node (ref "SV89") (pin "1") (pinfunction "1_1") (pintype "passive"))
      (node (ref "SV89") (pin "3") (pinfunction "3_3") (pintype "passive"))
      (node (ref "SV89") (pin "5") (pinfunction "5_5") (pintype "passive"))
      (node (ref "SV89") (pin "7") (pinfunction "7_7") (pintype "passive"))
      (node (ref "SV89") (pin "9") (pinfunction "9_9") (pintype "passive"))
    )
    (net (code "663") (name "Net-(SV89-Pad10)") (class "Default")
      (node (ref "SV89") (pin "10") (pinfunction "10_10") (pintype "passive"))
      (node (ref "SV89") (pin "2") (pinfunction "2_2") (pintype "passive"))
      (node (ref "SV89") (pin "4") (pinfunction "4_4") (pintype "passive"))
      (node (ref "SV89") (pin "6") (pinfunction "6_6") (pintype "passive"))
      (node (ref "SV89") (pin "8") (pinfunction "8_8") (pintype "passive"))
    )
    (net (code "664") (name "Net-(SV90-Pad1)") (class "Default")
      (node (ref "SV90") (pin "1") (pinfunction "1_1") (pintype "passive"))
      (node (ref "SV90") (pin "3") (pinfunction "3_3") (pintype "passive"))
      (node (ref "SV90") (pin "5") (pinfunction "5_5") (pintype "passive"))
      (node (ref "SV90") (pin "7") (pinfunction "7_7") (pintype "passive"))
      (node (ref "SV90") (pin "9") (pinfunction "9_9") (pintype "passive"))
    )
    (net (code "665") (name "Net-(SV90-Pad10)") (class "Default")
      (node (ref "SV90") (pin "10") (pinfunction "10_10") (pintype "passive"))
      (node (ref "SV90") (pin "2") (pinfunction "2_2") (pintype "passive"))
      (node (ref "SV90") (pin "4") (pinfunction "4_4") (pintype "passive"))
      (node (ref "SV90") (pin "6") (pinfunction "6_6") (pintype "passive"))
      (node (ref "SV90") (pin "8") (pinfunction "8_8") (pintype "passive"))
    )
    (net (code "666") (name "Net-(SV91-Pad1)") (class "Default")
      (node (ref "SV91") (pin "1") (pinfunction "1_1") (pintype "passive"))
      (node (ref "SV91") (pin "3") (pinfunction "3_3") (pintype "passive"))
      (node (ref "SV91") (pin "5") (pinfunction "5_5") (pintype "passive"))
      (node (ref "SV91") (pin "7") (pinfunction "7_7") (pintype "passive"))
      (node (ref "SV91") (pin "9") (pinfunction "9_9") (pintype "passive"))
    )
    (net (code "667") (name "Net-(SV91-Pad10)") (class "Default")
      (node (ref "SV91") (pin "10") (pinfunction "10_10") (pintype "passive"))
      (node (ref "SV91") (pin "2") (pinfunction "2_2") (pintype "passive"))
      (node (ref "SV91") (pin "4") (pinfunction "4_4") (pintype "passive"))
      (node (ref "SV91") (pin "6") (pinfunction "6_6") (pintype "passive"))
      (node (ref "SV91") (pin "8") (pinfunction "8_8") (pintype "passive"))
    )
    (net (code "668") (name "Net-(SV92-Pad1)") (class "Default")
      (node (ref "SV92") (pin "1") (pinfunction "1_1") (pintype "passive"))
      (node (ref "SV92") (pin "3") (pinfunction "3_3") (pintype "passive"))
      (node (ref "SV92") (pin "5") (pinfunction "5_5") (pintype "passive"))
      (node (ref "SV92") (pin "7") (pinfunction "7_7") (pintype "passive"))
      (node (ref "SV92") (pin "9") (pinfunction "9_9") (pintype "passive"))
    )
    (net (code "669") (name "Net-(SV92-Pad10)") (class "Default")
      (node (ref "SV92") (pin "10") (pinfunction "10_10") (pintype "passive"))
      (node (ref "SV92") (pin "2") (pinfunction "2_2") (pintype "passive"))
      (node (ref "SV92") (pin "4") (pinfunction "4_4") (pintype "passive"))
      (node (ref "SV92") (pin "6") (pinfunction "6_6") (pintype "passive"))
      (node (ref "SV92") (pin "8") (pinfunction "8_8") (pintype "passive"))
    )
    (net (code "670") (name "Net-(SV93-Pad1)") (class "Default")
      (node (ref "SV93") (pin "1") (pinfunction "1_1") (pintype "passive"))
      (node (ref "SV93") (pin "3") (pinfunction "3_3") (pintype "passive"))
      (node (ref "SV93") (pin "5") (pinfunction "5_5") (pintype "passive"))
      (node (ref "SV93") (pin "7") (pinfunction "7_7") (pintype "passive"))
      (node (ref "SV93") (pin "9") (pinfunction "9_9") (pintype "passive"))
    )
    (net (code "671") (name "Net-(SV93-Pad10)") (class "Default")
      (node (ref "SV93") (pin "10") (pinfunction "10_10") (pintype "passive"))
      (node (ref "SV93") (pin "2") (pinfunction "2_2") (pintype "passive"))
      (node (ref "SV93") (pin "4") (pinfunction "4_4") (pintype "passive"))
      (node (ref "SV93") (pin "6") (pinfunction "6_6") (pintype "passive"))
      (node (ref "SV93") (pin "8") (pinfunction "8_8") (pintype "passive"))
    )
    (net (code "672") (name "Net-(SV94-Pad1)") (class "Default")
      (node (ref "SV94") (pin "1") (pinfunction "1_1") (pintype "passive"))
      (node (ref "SV94") (pin "3") (pinfunction "3_3") (pintype "passive"))
      (node (ref "SV94") (pin "5") (pinfunction "5_5") (pintype "passive"))
      (node (ref "SV94") (pin "7") (pinfunction "7_7") (pintype "passive"))
      (node (ref "SV94") (pin "9") (pinfunction "9_9") (pintype "passive"))
    )
    (net (code "673") (name "Net-(SV94-Pad10)") (class "Default")
      (node (ref "SV94") (pin "10") (pinfunction "10_10") (pintype "passive"))
      (node (ref "SV94") (pin "2") (pinfunction "2_2") (pintype "passive"))
      (node (ref "SV94") (pin "4") (pinfunction "4_4") (pintype "passive"))
      (node (ref "SV94") (pin "6") (pinfunction "6_6") (pintype "passive"))
      (node (ref "SV94") (pin "8") (pinfunction "8_8") (pintype "passive"))
    )
    (net (code "674") (name "Net-(SV95-Pad1)") (class "Default")
      (node (ref "SV95") (pin "1") (pinfunction "1_1") (pintype "passive"))
      (node (ref "SV95") (pin "3") (pinfunction "3_3") (pintype "passive"))
      (node (ref "SV95") (pin "5") (pinfunction "5_5") (pintype "passive"))
      (node (ref "SV95") (pin "7") (pinfunction "7_7") (pintype "passive"))
      (node (ref "SV95") (pin "9") (pinfunction "9_9") (pintype "passive"))
    )
    (net (code "675") (name "Net-(SV95-Pad10)") (class "Default")
      (node (ref "SV95") (pin "10") (pinfunction "10_10") (pintype "passive"))
      (node (ref "SV95") (pin "2") (pinfunction "2_2") (pintype "passive"))
      (node (ref "SV95") (pin "4") (pinfunction "4_4") (pintype "passive"))
      (node (ref "SV95") (pin "6") (pinfunction "6_6") (pintype "passive"))
      (node (ref "SV95") (pin "8") (pinfunction "8_8") (pintype "passive"))
    )
    (net (code "676") (name "Net-(SV96-Pad1)") (class "Default")
      (node (ref "SV96") (pin "1") (pinfunction "1_1") (pintype "passive"))
      (node (ref "SV96") (pin "3") (pinfunction "3_3") (pintype "passive"))
      (node (ref "SV96") (pin "5") (pinfunction "5_5") (pintype "passive"))
      (node (ref "SV96") (pin "7") (pinfunction "7_7") (pintype "passive"))
      (node (ref "SV96") (pin "9") (pinfunction "9_9") (pintype "passive"))
    )
    (net (code "677") (name "Net-(SV96-Pad10)") (class "Default")
      (node (ref "SV96") (pin "10") (pinfunction "10_10") (pintype "passive"))
      (node (ref "SV96") (pin "2") (pinfunction "2_2") (pintype "passive"))
      (node (ref "SV96") (pin "4") (pinfunction "4_4") (pintype "passive"))
      (node (ref "SV96") (pin "6") (pinfunction "6_6") (pintype "passive"))
      (node (ref "SV96") (pin "8") (pinfunction "8_8") (pintype "passive"))
    )
    (net (code "678") (name "Net-(SV97-Pad1)") (class "Default")
      (node (ref "SV97") (pin "1") (pinfunction "1_1") (pintype "passive"))
      (node (ref "SV97") (pin "3") (pinfunction "3_3") (pintype "passive"))
      (node (ref "SV97") (pin "5") (pinfunction "5_5") (pintype "passive"))
      (node (ref "SV97") (pin "7") (pinfunction "7_7") (pintype "passive"))
      (node (ref "SV97") (pin "9") (pinfunction "9_9") (pintype "passive"))
    )
    (net (code "679") (name "Net-(SV97-Pad10)") (class "Default")
      (node (ref "SV97") (pin "10") (pinfunction "10_10") (pintype "passive"))
      (node (ref "SV97") (pin "2") (pinfunction "2_2") (pintype "passive"))
      (node (ref "SV97") (pin "4") (pinfunction "4_4") (pintype "passive"))
      (node (ref "SV97") (pin "6") (pinfunction "6_6") (pintype "passive"))
      (node (ref "SV97") (pin "8") (pinfunction "8_8") (pintype "passive"))
    )
    (net (code "680") (name "Net-(SV98-Pad1)") (class "Default")
      (node (ref "SV98") (pin "1") (pinfunction "1_1") (pintype "passive"))
      (node (ref "SV98") (pin "3") (pinfunction "3_3") (pintype "passive"))
      (node (ref "SV98") (pin "5") (pinfunction "5_5") (pintype "passive"))
      (node (ref "SV98") (pin "7") (pinfunction "7_7") (pintype "passive"))
      (node (ref "SV98") (pin "9") (pinfunction "9_9") (pintype "passive"))
    )
    (net (code "681") (name "Net-(SV98-Pad10)") (class "Default")
      (node (ref "SV98") (pin "10") (pinfunction "10_10") (pintype "passive"))
      (node (ref "SV98") (pin "2") (pinfunction "2_2") (pintype "passive"))
      (node (ref "SV98") (pin "4") (pinfunction "4_4") (pintype "passive"))
      (node (ref "SV98") (pin "6") (pinfunction "6_6") (pintype "passive"))
      (node (ref "SV98") (pin "8") (pinfunction "8_8") (pintype "passive"))
    )
    (net (code "682") (name "Net-(SV99-Pad1)") (class "Default")
      (node (ref "SV99") (pin "1") (pinfunction "1_1") (pintype "passive"))
      (node (ref "SV99") (pin "3") (pinfunction "3_3") (pintype "passive"))
      (node (ref "SV99") (pin "5") (pinfunction "5_5") (pintype "passive"))
      (node (ref "SV99") (pin "7") (pinfunction "7_7") (pintype "passive"))
      (node (ref "SV99") (pin "9") (pinfunction "9_9") (pintype "passive"))
    )
    (net (code "683") (name "Net-(SV99-Pad10)") (class "Default")
      (node (ref "SV99") (pin "10") (pinfunction "10_10") (pintype "passive"))
      (node (ref "SV99") (pin "2") (pinfunction "2_2") (pintype "passive"))
      (node (ref "SV99") (pin "4") (pinfunction "4_4") (pintype "passive"))
      (node (ref "SV99") (pin "6") (pinfunction "6_6") (pintype "passive"))
      (node (ref "SV99") (pin "8") (pinfunction "8_8") (pintype "passive"))
    )
    (net (code "684") (name "Net-(SV100-Pad1)") (class "Default")
      (node (ref "SV100") (pin "1") (pinfunction "1_1") (pintype "passive"))
      (node (ref "SV100") (pin "3") (pinfunction "3_3") (pintype "passive"))
      (node (ref "SV100") (pin "5") (pinfunction "5_5") (pintype "passive"))
      (node (ref "SV100") (pin "7") (pinfunction "7_7") (pintype "passive"))
      (node (ref "SV100") (pin "9") (pinfunction "9_9") (pintype "passive"))
    )
    (net (code "685") (name "Net-(SV100-Pad10)") (class "Default")
      (node (ref "SV100") (pin "10") (pinfunction "10_10") (pintype "passive"))
      (node (ref "SV100") (pin "2") (pinfunction "2_2") (pintype "passive"))
      (node (ref "SV100") (pin "4") (pinfunction "4_4") (pintype "passive"))
      (node (ref "SV100") (pin "6") (pinfunction "6_6") (pintype "passive"))
      (node (ref "SV100") (pin "8") (pinfunction "8_8") (pintype "passive"))
    )
    (net (code "686") (name "Net-(SV101-Pad1)") (class "Default")
      (node (ref "SV101") (pin "1") (pinfunction "1_1") (pintype "passive"))
      (node (ref "SV101") (pin "3") (pinfunction "3_3") (pintype "passive"))
      (node (ref "SV101") (pin "5") (pinfunction "5_5") (pintype "passive"))
      (node (ref "SV101") (pin "7") (pinfunction "7_7") (pintype "passive"))
      (node (ref "SV101") (pin "9") (pinfunction "9_9") (pintype "passive"))
    )
    (net (code "687") (name "Net-(SV101-Pad10)") (class "Default")
      (node (ref "SV101") (pin "10") (pinfunction "10_10") (pintype "passive"))
      (node (ref "SV101") (pin "2") (pinfunction "2_2") (pintype "passive"))
      (node (ref "SV101") (pin "4") (pinfunction "4_4") (pintype "passive"))
      (node (ref "SV101") (pin "6") (pinfunction "6_6") (pintype "passive"))
      (node (ref "SV101") (pin "8") (pinfunction "8_8") (pintype "passive"))
    )
    (net (code "688") (name "Net-(SV102-Pad1)") (class "Default")
      (node (ref "SV102") (pin "1") (pinfunction "1_1") (pintype "passive"))
      (node (ref "SV102") (pin "3") (pinfunction "3_3") (pintype "passive"))
      (node (ref "SV102") (pin "5") (pinfunction "5_5") (pintype "passive"))
      (node (ref "SV102") (pin "7") (pinfunction "7_7") (pintype "passive"))
      (node (ref "SV102") (pin "9") (pinfunction "9_9") (pintype "passive"))
    )
    (net (code "689") (name "Net-(SV102-Pad10)") (class "Default")
      (node (ref "SV102") (pin "10") (pinfunction "10_10") (pintype "passive"))
      (node (ref "SV102") (pin "2") (pinfunction "2_2") (pintype "passive"))
      (node (ref "SV102") (pin "4") (pinfunction "4_4") (pintype "passive"))
      (node (ref "SV102") (pin "6") (pinfunction "6_6") (pintype "passive"))
      (node (ref "SV102") (pin "8") (pinfunction "8_8") (pintype "passive"))
    )
    (net (code "690") (name "Net-(SV103-Pad1)") (class "Default")
      (node (ref "SV103") (pin "1") (pinfunction "1_1") (pintype "passive"))
      (node (ref "SV103") (pin "3") (pinfunction "3_3") (pintype "passive"))
      (node (ref "SV103") (pin "5") (pinfunction "5_5") (pintype "passive"))
      (node (ref "SV103") (pin "7") (pinfunction "7_7") (pintype "passive"))
      (node (ref "SV103") (pin "9") (pinfunction "9_9") (pintype "passive"))
    )
    (net (code "691") (name "Net-(SV103-Pad10)") (class "Default")
      (node (ref "SV103") (pin "10") (pinfunction "10_10") (pintype "passive"))
      (node (ref "SV103") (pin "2") (pinfunction "2_2") (pintype "passive"))
      (node (ref "SV103") (pin "4") (pinfunction "4_4") (pintype "passive"))
      (node (ref "SV103") (pin "6") (pinfunction "6_6") (pintype "passive"))
      (node (ref "SV103") (pin "8") (pinfunction "8_8") (pintype "passive"))
    )
    (net (code "692") (name "Net-(SV104-Pad1)") (class "Default")
      (node (ref "SV104") (pin "1") (pinfunction "1_1") (pintype "passive"))
      (node (ref "SV104") (pin "3") (pinfunction "3_3") (pintype "passive"))
      (node (ref "SV104") (pin "5") (pinfunction "5_5") (pintype "passive"))
      (node (ref "SV104") (pin "7") (pinfunction "7_7") (pintype "passive"))
      (node (ref "SV104") (pin "9") (pinfunction "9_9") (pintype "passive"))
    )
    (net (code "693") (name "Net-(SV104-Pad10)") (class "Default")
      (node (ref "SV104") (pin "10") (pinfunction "10_10") (pintype "passive"))
      (node (ref "SV104") (pin "2") (pinfunction "2_2") (pintype "passive"))
      (node (ref "SV104") (pin "4") (pinfunction "4_4") (pintype "passive"))
      (node (ref "SV104") (pin "6") (pinfunction "6_6") (pintype "passive"))
      (node (ref "SV104") (pin "8") (pinfunction "8_8") (pintype "passive"))
    )
    (net (code "694") (name "Net-(SV105-Pad1)") (class "Default")
      (node (ref "SV105") (pin "1") (pinfunction "1_1") (pintype "passive"))
      (node (ref "SV105") (pin "3") (pinfunction "3_3") (pintype "passive"))
      (node (ref "SV105") (pin "5") (pinfunction "5_5") (pintype "passive"))
      (node (ref "SV105") (pin "7") (pinfunction "7_7") (pintype "passive"))
      (node (ref "SV105") (pin "9") (pinfunction "9_9") (pintype "passive"))
    )
    (net (code "695") (name "Net-(SV105-Pad10)") (class "Default")
      (node (ref "SV105") (pin "10") (pinfunction "10_10") (pintype "passive"))
      (node (ref "SV105") (pin "2") (pinfunction "2_2") (pintype "passive"))
      (node (ref "SV105") (pin "4") (pinfunction "4_4") (pintype "passive"))
      (node (ref "SV105") (pin "6") (pinfunction "6_6") (pintype "passive"))
      (node (ref "SV105") (pin "8") (pinfunction "8_8") (pintype "passive"))
    )
    (net (code "696") (name "Net-(SV106-Pad1)") (class "Default")
      (node (ref "SV106") (pin "1") (pinfunction "1_1") (pintype "passive"))
      (node (ref "SV106") (pin "3") (pinfunction "3_3") (pintype "passive"))
      (node (ref "SV106") (pin "5") (pinfunction "5_5") (pintype "passive"))
      (node (ref "SV106") (pin "7") (pinfunction "7_7") (pintype "passive"))
      (node (ref "SV106") (pin "9") (pinfunction "9_9") (pintype "passive"))
    )
    (net (code "697") (name "Net-(SV106-Pad10)") (class "Default")
      (node (ref "SV106") (pin "10") (pinfunction "10_10") (pintype "passive"))
      (node (ref "SV106") (pin "2") (pinfunction "2_2") (pintype "passive"))
      (node (ref "SV106") (pin "4") (pinfunction "4_4") (pintype "passive"))
      (node (ref "SV106") (pin "6") (pinfunction "6_6") (pintype "passive"))
      (node (ref "SV106") (pin "8") (pinfunction "8_8") (pintype "passive"))
    )
    (net (code "698") (name "Net-(SV107-Pad1)") (class "Default")
      (node (ref "SV107") (pin "1") (pinfunction "1_1") (pintype "passive"))
      (node (ref "SV107") (pin "3") (pinfunction "3_3") (pintype "passive"))
      (node (ref "SV107") (pin "5") (pinfunction "5_5") (pintype "passive"))
      (node (ref "SV107") (pin "7") (pinfunction "7_7") (pintype "passive"))
      (node (ref "SV107") (pin "9") (pinfunction "9_9") (pintype "passive"))
    )
    (net (code "699") (name "Net-(SV107-Pad10)") (class "Default")
      (node (ref "SV107") (pin "10") (pinfunction "10_10") (pintype "passive"))
      (node (ref "SV107") (pin "2") (pinfunction "2_2") (pintype "passive"))
      (node (ref "SV107") (pin "4") (pinfunction "4_4") (pintype "passive"))
      (node (ref "SV107") (pin "6") (pinfunction "6_6") (pintype "passive"))
      (node (ref "SV107") (pin "8") (pinfunction "8_8") (pintype "passive"))
    )
    (net (code "700") (name "Net-(SV108-Pad1)") (class "Default")
      (node (ref "SV108") (pin "1") (pinfunction "1_1") (pintype "passive"))
      (node (ref "SV108") (pin "3") (pinfunction "3_3") (pintype "passive"))
      (node (ref "SV108") (pin "5") (pinfunction "5_5") (pintype "passive"))
      (node (ref "SV108") (pin "7") (pinfunction "7_7") (pintype "passive"))
      (node (ref "SV108") (pin "9") (pinfunction "9_9") (pintype "passive"))
    )
    (net (code "701") (name "Net-(SV108-Pad10)") (class "Default")
      (node (ref "SV108") (pin "10") (pinfunction "10_10") (pintype "passive"))
      (node (ref "SV108") (pin "2") (pinfunction "2_2") (pintype "passive"))
      (node (ref "SV108") (pin "4") (pinfunction "4_4") (pintype "passive"))
      (node (ref "SV108") (pin "6") (pinfunction "6_6") (pintype "passive"))
      (node (ref "SV108") (pin "8") (pinfunction "8_8") (pintype "passive"))
    )
    (net (code "702") (name "Net-(SV109-Pad1)") (class "Default")
      (node (ref "SV109") (pin "1") (pinfunction "1_1") (pintype "passive"))
      (node (ref "SV109") (pin "3") (pinfunction "3_3") (pintype "passive"))
      (node (ref "SV109") (pin "5") (pinfunction "5_5") (pintype "passive"))
      (node (ref "SV109") (pin "7") (pinfunction "7_7") (pintype "passive"))
      (node (ref "SV109") (pin "9") (pinfunction "9_9") (pintype "passive"))
    )
    (net (code "703") (name "Net-(SV109-Pad10)") (class "Default")
      (node (ref "SV109") (pin "10") (pinfunction "10_10") (pintype "passive"))
      (node (ref "SV109") (pin "2") (pinfunction "2_2") (pintype "passive"))
      (node (ref "SV109") (pin "4") (pinfunction "4_4") (pintype "passive"))
      (node (ref "SV109") (pin "6") (pinfunction "6_6") (pintype "passive"))
      (node (ref "SV109") (pin "8") (pinfunction "8_8") (pintype "passive"))
    )
    (net (code "704") (name "Net-(SV110-Pad1)") (class "Default")
      (node (ref "SV110") (pin "1") (pinfunction "1_1") (pintype "passive"))
      (node (ref "SV110") (pin "3") (pinfunction "3_3") (pintype "passive"))
      (node (ref "SV110") (pin "5") (pinfunction "5_5") (pintype "passive"))
      (node (ref "SV110") (pin "7") (pinfunction "7_7") (pintype "passive"))
      (node (ref "SV110") (pin "9") (pinfunction "9_9") (pintype "passive"))
    )
    (net (code "705") (name "Net-(SV110-Pad10)") (class "Default")
      (node (ref "SV110") (pin "10") (pinfunction "10_10") (pintype "passive"))
      (node (ref "SV110") (pin "2") (pinfunction "2_2") (pintype "passive"))
      (node (ref "SV110") (pin "4") (pinfunction "4_4") (pintype "passive"))
      (node (ref "SV110") (pin "6") (pinfunction "6_6") (pintype "passive"))
      (node (ref "SV110") (pin "8") (pinfunction "8_8") (pintype "passive"))
    )
    (net (code "706") (name "Net-(SV111-Pad1)") (class "Default")
      (node (ref "SV111") (pin "1") (pinfunction "1_1") (pintype "passive"))
      (node (ref "SV111") (pin "3") (pinfunction "3_3") (pintype "passive"))
      (node (ref "SV111") (pin "5") (pinfunction "5_5") (pintype "passive"))
      (node (ref "SV111") (pin "7") (pinfunction "7_7") (pintype "passive"))
      (node (ref "SV111") (pin "9") (pinfunction "9_9") (pintype "passive"))
    )
    (net (code "707") (name "Net-(SV111-Pad10)") (class "Default")
      (node (ref "SV111") (pin "10") (pinfunction "10_10") (pintype "passive"))
      (node (ref "SV111") (pin "2") (pinfunction "2_2") (pintype "passive"))
      (node (ref "SV111") (pin "4") (pinfunction "4_4") (pintype "passive"))
      (node (ref "SV111") (pin "6") (pinfunction "6_6") (pintype "passive"))
      (node (ref "SV111") (pin "8") (pinfunction "8_8") (pintype "passive"))
    )
    (net (code "708") (name "Net-(SV112-Pad1)") (class "Default")
      (node (ref "SV112") (pin "1") (pinfunction "1_1") (pintype "passive"))
      (node (ref "SV112") (pin "3") (pinfunction "3_3") (pintype "passive"))
      (node (ref "SV112") (pin "5") (pinfunction "5_5") (pintype "passive"))
      (node (ref "SV112") (pin "7") (pinfunction "7_7") (pintype "passive"))
      (node (ref "SV112") (pin "9") (pinfunction "9_9") (pintype "passive"))
    )
    (net (code "709") (name "Net-(SV112-Pad10)") (class "Default")
      (node (ref "SV112") (pin "10") (pinfunction "10_10") (pintype "passive"))
      (node (ref "SV112") (pin "2") (pinfunction "2_2") (pintype "passive"))
      (node (ref "SV112") (pin "4") (pinfunction "4_4") (pintype "passive"))
      (node (ref "SV112") (pin "6") (pinfunction "6_6") (pintype "passive"))
      (node (ref "SV112") (pin "8") (pinfunction "8_8") (pintype "passive"))
    )
    (net (code "710") (name "Net-(SV113-Pad1)") (class "Default")
      (node (ref "SV113") (pin "1") (pinfunction "1_1") (pintype "passive"))
      (node (ref "SV113") (pin "3") (pinfunction "3_3") (pintype "passive"))
      (node (ref "SV113") (pin "5") (pinfunction "5_5") (pintype "passive"))
      (node (ref "SV113") (pin "7") (pinfunction "7_7") (pintype "passive"))
      (node (ref "SV113") (pin "9") (pinfunction "9_9") (pintype "passive"))
    )
    (net (code "711") (name "Net-(SV113-Pad10)") (class "Default")
      (node (ref "SV113") (pin "10") (pinfunction "10_10") (pintype "passive"))
      (node (ref "SV113") (pin "2") (pinfunction "2_2") (pintype "passive"))
      (node (ref "SV113") (pin "4") (pinfunction "4_4") (pintype "passive"))
      (node (ref "SV113") (pin "6") (pinfunction "6_6") (pintype "passive"))
      (node (ref "SV113") (pin "8") (pinfunction "8_8") (pintype "passive"))
    )
    (net (code "712") (name "Net-(SV114-Pad1)") (class "Default")
      (node (ref "SV114") (pin "1") (pinfunction "1_1") (pintype "passive"))
      (node (ref "SV114") (pin "3") (pinfunction "3_3") (pintype "passive"))
      (node (ref "SV114") (pin "5") (pinfunction "5_5") (pintype "passive"))
      (node (ref "SV114") (pin "7") (pinfunction "7_7") (pintype "passive"))
      (node (ref "SV114") (pin "9") (pinfunction "9_9") (pintype "passive"))
    )
    (net (code "713") (name "Net-(SV114-Pad10)") (class "Default")
      (node (ref "SV114") (pin "10") (pinfunction "10_10") (pintype "passive"))
      (node (ref "SV114") (pin "2") (pinfunction "2_2") (pintype "passive"))
      (node (ref "SV114") (pin "4") (pinfunction "4_4") (pintype "passive"))
      (node (ref "SV114") (pin "6") (pinfunction "6_6") (pintype "passive"))
      (node (ref "SV114") (pin "8") (pinfunction "8_8") (pintype "passive"))
    )
    (net (code "714") (name "Net-(SV115-Pad1)") (class "Default")
      (node (ref "SV115") (pin "1") (pinfunction "1_1") (pintype "passive"))
      (node (ref "SV115") (pin "3") (pinfunction "3_3") (pintype "passive"))
      (node (ref "SV115") (pin "5") (pinfunction "5_5") (pintype "passive"))
      (node (ref "SV115") (pin "7") (pinfunction "7_7") (pintype "passive"))
      (node (ref "SV115") (pin "9") (pinfunction "9_9") (pintype "passive"))
    )
    (net (code "715") (name "Net-(SV115-Pad10)") (class "Default")
      (node (ref "SV115") (pin "10") (pinfunction "10_10") (pintype "passive"))
      (node (ref "SV115") (pin "2") (pinfunction "2_2") (pintype "passive"))
      (node (ref "SV115") (pin "4") (pinfunction "4_4") (pintype "passive"))
      (node (ref "SV115") (pin "6") (pinfunction "6_6") (pintype "passive"))
      (node (ref "SV115") (pin "8") (pinfunction "8_8") (pintype "passive"))
    )
    (net (code "716") (name "Net-(SV116-Pad1)") (class "Default")
      (node (ref "SV116") (pin "1") (pinfunction "1_1") (pintype "passive"))
      (node (ref "SV116") (pin "3") (pinfunction "3_3") (pintype "passive"))
      (node (ref "SV116") (pin "5") (pinfunction "5_5") (pintype "passive"))
      (node (ref "SV116") (pin "7") (pinfunction "7_7") (pintype "passive"))
      (node (ref "SV116") (pin "9") (pinfunction "9_9") (pintype "passive"))
    )
    (net (code "717") (name "Net-(SV116-Pad10)") (class "Default")
      (node (ref "SV116") (pin "10") (pinfunction "10_10") (pintype "passive"))
      (node (ref "SV116") (pin "2") (pinfunction "2_2") (pintype "passive"))
      (node (ref "SV116") (pin "4") (pinfunction "4_4") (pintype "passive"))
      (node (ref "SV116") (pin "6") (pinfunction "6_6") (pintype "passive"))
      (node (ref "SV116") (pin "8") (pinfunction "8_8") (pintype "passive"))
    )
    (net (code "718") (name "Net-(SV117-Pad1)") (class "Default")
      (node (ref "SV117") (pin "1") (pinfunction "1_1") (pintype "passive"))
      (node (ref "SV117") (pin "3") (pinfunction "3_3") (pintype "passive"))
      (node (ref "SV117") (pin "5") (pinfunction "5_5") (pintype "passive"))
      (node (ref "SV117") (pin "7") (pinfunction "7_7") (pintype "passive"))
      (node (ref "SV117") (pin "9") (pinfunction "9_9") (pintype "passive"))
    )
    (net (code "719") (name "Net-(SV117-Pad10)") (class "Default")
      (node (ref "SV117") (pin "10") (pinfunction "10_10") (pintype "passive"))
      (node (ref "SV117") (pin "2") (pinfunction "2_2") (pintype "passive"))
      (node (ref "SV117") (pin "4") (pinfunction "4_4") (pintype "passive"))
      (node (ref "SV117") (pin "6") (pinfunction "6_6") (pintype "passive"))
      (node (ref "SV117") (pin "8") (pinfunction "8_8") (pintype "passive"))
    )
    (net (code "720") (name "Net-(SV118-Pad1)") (class "Default")
      (node (ref "SV118") (pin "1") (pinfunction "1_1") (pintype "passive"))
      (node (ref "SV118") (pin "3") (pinfunction "3_3") (pintype "passive"))
      (node (ref "SV118") (pin "5") (pinfunction "5_5") (pintype "passive"))
      (node (ref "SV118") (pin "7") (pinfunction "7_7") (pintype "passive"))
      (node (ref "SV118") (pin "9") (pinfunction "9_9") (pintype "passive"))
    )
    (net (code "721") (name "Net-(SV118-Pad10)") (class "Default")
      (node (ref "SV118") (pin "10") (pinfunction "10_10") (pintype "passive"))
      (node (ref "SV118") (pin "2") (pinfunction "2_2") (pintype "passive"))
      (node (ref "SV118") (pin "4") (pinfunction "4_4") (pintype "passive"))
      (node (ref "SV118") (pin "6") (pinfunction "6_6") (pintype "passive"))
      (node (ref "SV118") (pin "8") (pinfunction "8_8") (pintype "passive"))
    )
    (net (code "722") (name "Net-(SV119-Pad1)") (class "Default")
      (node (ref "SV119") (pin "1") (pinfunction "1_1") (pintype "passive"))
      (node (ref "SV119") (pin "3") (pinfunction "3_3") (pintype "passive"))
      (node (ref "SV119") (pin "5") (pinfunction "5_5") (pintype "passive"))
      (node (ref "SV119") (pin "7") (pinfunction "7_7") (pintype "passive"))
      (node (ref "SV119") (pin "9") (pinfunction "9_9") (pintype "passive"))
    )
    (net (code "723") (name "Net-(SV119-Pad10)") (class "Default")
      (node (ref "SV119") (pin "10") (pinfunction "10_10") (pintype "passive"))
      (node (ref "SV119") (pin "2") (pinfunction "2_2") (pintype "passive"))
      (node (ref "SV119") (pin "4") (pinfunction "4_4") (pintype "passive"))
      (node (ref "SV119") (pin "6") (pinfunction "6_6") (pintype "passive"))
      (node (ref "SV119") (pin "8") (pinfunction "8_8") (pintype "passive"))
    )
    (net (code "724") (name "Net-(SV120-Pad1)") (class "Default")
      (node (ref "SV120") (pin "1") (pinfunction "1_1") (pintype "passive"))
      (node (ref "SV120") (pin "3") (pinfunction "3_3") (pintype "passive"))
      (node (ref "SV120") (pin "5") (pinfunction "5_5") (pintype "passive"))
      (node (ref "SV120") (pin "7") (pinfunction "7_7") (pintype "passive"))
      (node (ref "SV120") (pin "9") (pinfunction "9_9") (pintype "passive"))
    )
    (net (code "725") (name "Net-(SV120-Pad10)") (class "Default")
      (node (ref "SV120") (pin "10") (pinfunction "10_10") (pintype "passive"))
      (node (ref "SV120") (pin "2") (pinfunction "2_2") (pintype "passive"))
      (node (ref "SV120") (pin "4") (pinfunction "4_4") (pintype "passive"))
      (node (ref "SV120") (pin "6") (pinfunction "6_6") (pintype "passive"))
      (node (ref "SV120") (pin "8") (pinfunction "8_8") (pintype "passive"))
    )
    (net (code "726") (name "Net-(SV121-Pad1)") (class "Default")
      (node (ref "SV121") (pin "1") (pinfunction "1_1") (pintype "passive"))
      (node (ref "SV121") (pin "3") (pinfunction "3_3") (pintype "passive"))
      (node (ref "SV121") (pin "5") (pinfunction "5_5") (pintype "passive"))
      (node (ref "SV121") (pin "7") (pinfunction "7_7") (pintype "passive"))
      (node (ref "SV121") (pin "9") (pinfunction "9_9") (pintype "passive"))
    )
    (net (code "727") (name "Net-(SV121-Pad10)") (class "Default")
      (node (ref "SV121") (pin "10") (pinfunction "10_10") (pintype "passive"))
      (node (ref "SV121") (pin "2") (pinfunction "2_2") (pintype "passive"))
      (node (ref "SV121") (pin "4") (pinfunction "4_4") (pintype "passive"))
      (node (ref "SV121") (pin "6") (pinfunction "6_6") (pintype "passive"))
      (node (ref "SV121") (pin "8") (pinfunction "8_8") (pintype "passive"))
    )
    (net (code "728") (name "Net-(SV122-Pad1)") (class "Default")
      (node (ref "SV122") (pin "1") (pinfunction "1_1") (pintype "passive"))
      (node (ref "SV122") (pin "3") (pinfunction "3_3") (pintype "passive"))
      (node (ref "SV122") (pin "5") (pinfunction "5_5") (pintype "passive"))
      (node (ref "SV122") (pin "7") (pinfunction "7_7") (pintype "passive"))
      (node (ref "SV122") (pin "9") (pinfunction "9_9") (pintype "passive"))
    )
    (net (code "729") (name "Net-(SV122-Pad10)") (class "Default")
      (node (ref "SV122") (pin "10") (pinfunction "10_10") (pintype "passive"))
      (node (ref "SV122") (pin "2") (pinfunction "2_2") (pintype "passive"))
      (node (ref "SV122") (pin "4") (pinfunction "4_4") (pintype "passive"))
      (node (ref "SV122") (pin "6") (pinfunction "6_6") (pintype "passive"))
      (node (ref "SV122") (pin "8") (pinfunction "8_8") (pintype "passive"))
    )
    (net (code "730") (name "Net-(SV123-Pad1)") (class "Default")
      (node (ref "SV123") (pin "1") (pinfunction "1_1") (pintype "passive"))
      (node (ref "SV123") (pin "3") (pinfunction "3_3") (pintype "passive"))
      (node (ref "SV123") (pin "5") (pinfunction "5_5") (pintype "passive"))
      (node (ref "SV123") (pin "7") (pinfunction "7_7") (pintype "passive"))
      (node (ref "SV123") (pin "9") (pinfunction "9_9") (pintype "passive"))
    )
    (net (code "731") (name "Net-(SV123-Pad10)") (class "Default")
      (node (ref "SV123") (pin "10") (pinfunction "10_10") (pintype "passive"))
      (node (ref "SV123") (pin "2") (pinfunction "2_2") (pintype "passive"))
      (node (ref "SV123") (pin "4") (pinfunction "4_4") (pintype "passive"))
      (node (ref "SV123") (pin "6") (pinfunction "6_6") (pintype "passive"))
      (node (ref "SV123") (pin "8") (pinfunction "8_8") (pintype "passive"))
    )
    (net (code "732") (name "Net-(SV124-Pad1)") (class "Default")
      (node (ref "SV124") (pin "1") (pinfunction "1_1") (pintype "passive"))
      (node (ref "SV124") (pin "3") (pinfunction "3_3") (pintype "passive"))
      (node (ref "SV124") (pin "5") (pinfunction "5_5") (pintype "passive"))
      (node (ref "SV124") (pin "7") (pinfunction "7_7") (pintype "passive"))
      (node (ref "SV124") (pin "9") (pinfunction "9_9") (pintype "passive"))
    )
    (net (code "733") (name "Net-(SV124-Pad10)") (class "Default")
      (node (ref "SV124") (pin "10") (pinfunction "10_10") (pintype "passive"))
      (node (ref "SV124") (pin "2") (pinfunction "2_2") (pintype "passive"))
      (node (ref "SV124") (pin "4") (pinfunction "4_4") (pintype "passive"))
      (node (ref "SV124") (pin "6") (pinfunction "6_6") (pintype "passive"))
      (node (ref "SV124") (pin "8") (pinfunction "8_8") (pintype "passive"))
    )
    (net (code "734") (name "Net-(SV126-Pad1)") (class "Default")
      (node (ref "SV126") (pin "1") (pinfunction "1_1") (pintype "passive"))
      (node (ref "SV126") (pin "3") (pinfunction "3_3") (pintype "passive"))
      (node (ref "SV126") (pin "5") (pinfunction "5_5") (pintype "passive"))
      (node (ref "SV126") (pin "7") (pinfunction "7_7") (pintype "passive"))
      (node (ref "SV126") (pin "9") (pinfunction "9_9") (pintype "passive"))
    )
    (net (code "735") (name "Net-(SV126-Pad10)") (class "Default")
      (node (ref "SV126") (pin "10") (pinfunction "10_10") (pintype "passive"))
      (node (ref "SV126") (pin "2") (pinfunction "2_2") (pintype "passive"))
      (node (ref "SV126") (pin "4") (pinfunction "4_4") (pintype "passive"))
      (node (ref "SV126") (pin "6") (pinfunction "6_6") (pintype "passive"))
      (node (ref "SV126") (pin "8") (pinfunction "8_8") (pintype "passive"))
    )
    (net (code "736") (name "Net-(SV128-Pad1)") (class "Default")
      (node (ref "SV128") (pin "1") (pinfunction "1_1") (pintype "passive"))
      (node (ref "SV128") (pin "3") (pinfunction "3_3") (pintype "passive"))
      (node (ref "SV128") (pin "5") (pinfunction "5_5") (pintype "passive"))
      (node (ref "SV128") (pin "7") (pinfunction "7_7") (pintype "passive"))
      (node (ref "SV128") (pin "9") (pinfunction "9_9") (pintype "passive"))
    )
    (net (code "737") (name "Net-(SV128-Pad10)") (class "Default")
      (node (ref "SV128") (pin "10") (pinfunction "10_10") (pintype "passive"))
      (node (ref "SV128") (pin "2") (pinfunction "2_2") (pintype "passive"))
      (node (ref "SV128") (pin "4") (pinfunction "4_4") (pintype "passive"))
      (node (ref "SV128") (pin "6") (pinfunction "6_6") (pintype "passive"))
      (node (ref "SV128") (pin "8") (pinfunction "8_8") (pintype "passive"))
    )
    (net (code "738") (name "Net-(SV130-Pad1)") (class "Default")
      (node (ref "SV130") (pin "1") (pinfunction "1_1") (pintype "passive"))
      (node (ref "SV130") (pin "3") (pinfunction "3_3") (pintype "passive"))
      (node (ref "SV130") (pin "5") (pinfunction "5_5") (pintype "passive"))
      (node (ref "SV130") (pin "7") (pinfunction "7_7") (pintype "passive"))
      (node (ref "SV130") (pin "9") (pinfunction "9_9") (pintype "passive"))
    )
    (net (code "739") (name "Net-(SV130-Pad10)") (class "Default")
      (node (ref "SV130") (pin "10") (pinfunction "10_10") (pintype "passive"))
      (node (ref "SV130") (pin "2") (pinfunction "2_2") (pintype "passive"))
      (node (ref "SV130") (pin "4") (pinfunction "4_4") (pintype "passive"))
      (node (ref "SV130") (pin "6") (pinfunction "6_6") (pintype "passive"))
      (node (ref "SV130") (pin "8") (pinfunction "8_8") (pintype "passive"))
    )
    (net (code "740") (name "Net-(SV132-Pad1)") (class "Default")
      (node (ref "SV132") (pin "1") (pinfunction "1_1") (pintype "passive"))
      (node (ref "SV132") (pin "3") (pinfunction "3_3") (pintype "passive"))
      (node (ref "SV132") (pin "5") (pinfunction "5_5") (pintype "passive"))
      (node (ref "SV132") (pin "7") (pinfunction "7_7") (pintype "passive"))
      (node (ref "SV132") (pin "9") (pinfunction "9_9") (pintype "passive"))
    )
    (net (code "741") (name "Net-(SV132-Pad10)") (class "Default")
      (node (ref "SV132") (pin "10") (pinfunction "10_10") (pintype "passive"))
      (node (ref "SV132") (pin "2") (pinfunction "2_2") (pintype "passive"))
      (node (ref "SV132") (pin "4") (pinfunction "4_4") (pintype "passive"))
      (node (ref "SV132") (pin "6") (pinfunction "6_6") (pintype "passive"))
      (node (ref "SV132") (pin "8") (pinfunction "8_8") (pintype "passive"))
    )
    (net (code "742") (name "Net-(SV133-Pad1)") (class "Default")
      (node (ref "SV133") (pin "1") (pinfunction "1_1") (pintype "passive"))
      (node (ref "SV133") (pin "3") (pinfunction "3_3") (pintype "passive"))
      (node (ref "SV133") (pin "5") (pinfunction "5_5") (pintype "passive"))
      (node (ref "SV133") (pin "7") (pinfunction "7_7") (pintype "passive"))
      (node (ref "SV133") (pin "9") (pinfunction "9_9") (pintype "passive"))
    )
    (net (code "743") (name "Net-(SV133-Pad10)") (class "Default")
      (node (ref "SV133") (pin "10") (pinfunction "10_10") (pintype "passive"))
      (node (ref "SV133") (pin "2") (pinfunction "2_2") (pintype "passive"))
      (node (ref "SV133") (pin "4") (pinfunction "4_4") (pintype "passive"))
      (node (ref "SV133") (pin "6") (pinfunction "6_6") (pintype "passive"))
      (node (ref "SV133") (pin "8") (pinfunction "8_8") (pintype "passive"))
    )
    (net (code "744") (name "Net-(SV134-Pad1)") (class "Default")
      (node (ref "SV134") (pin "1") (pinfunction "1_1") (pintype "passive"))
      (node (ref "SV134") (pin "3") (pinfunction "3_3") (pintype "passive"))
      (node (ref "SV134") (pin "5") (pinfunction "5_5") (pintype "passive"))
      (node (ref "SV134") (pin "7") (pinfunction "7_7") (pintype "passive"))
      (node (ref "SV134") (pin "9") (pinfunction "9_9") (pintype "passive"))
    )
    (net (code "745") (name "Net-(SV134-Pad10)") (class "Default")
      (node (ref "SV134") (pin "10") (pinfunction "10_10") (pintype "passive"))
      (node (ref "SV134") (pin "2") (pinfunction "2_2") (pintype "passive"))
      (node (ref "SV134") (pin "4") (pinfunction "4_4") (pintype "passive"))
      (node (ref "SV134") (pin "6") (pinfunction "6_6") (pintype "passive"))
      (node (ref "SV134") (pin "8") (pinfunction "8_8") (pintype "passive"))
    )
    (net (code "746") (name "Net-(SV135-Pad1)") (class "Default")
      (node (ref "SV135") (pin "1") (pinfunction "1_1") (pintype "passive"))
      (node (ref "SV135") (pin "3") (pinfunction "3_3") (pintype "passive"))
      (node (ref "SV135") (pin "5") (pinfunction "5_5") (pintype "passive"))
      (node (ref "SV135") (pin "7") (pinfunction "7_7") (pintype "passive"))
      (node (ref "SV135") (pin "9") (pinfunction "9_9") (pintype "passive"))
    )
    (net (code "747") (name "Net-(SV135-Pad10)") (class "Default")
      (node (ref "SV135") (pin "10") (pinfunction "10_10") (pintype "passive"))
      (node (ref "SV135") (pin "2") (pinfunction "2_2") (pintype "passive"))
      (node (ref "SV135") (pin "4") (pinfunction "4_4") (pintype "passive"))
      (node (ref "SV135") (pin "6") (pinfunction "6_6") (pintype "passive"))
      (node (ref "SV135") (pin "8") (pinfunction "8_8") (pintype "passive"))
    )
    (net (code "748") (name "Net-(SV136-Pad1)") (class "Default")
      (node (ref "SV136") (pin "1") (pinfunction "1_1") (pintype "passive"))
      (node (ref "SV136") (pin "3") (pinfunction "3_3") (pintype "passive"))
      (node (ref "SV136") (pin "5") (pinfunction "5_5") (pintype "passive"))
      (node (ref "SV136") (pin "7") (pinfunction "7_7") (pintype "passive"))
      (node (ref "SV136") (pin "9") (pinfunction "9_9") (pintype "passive"))
    )
    (net (code "749") (name "Net-(SV136-Pad10)") (class "Default")
      (node (ref "SV136") (pin "10") (pinfunction "10_10") (pintype "passive"))
      (node (ref "SV136") (pin "2") (pinfunction "2_2") (pintype "passive"))
      (node (ref "SV136") (pin "4") (pinfunction "4_4") (pintype "passive"))
      (node (ref "SV136") (pin "6") (pinfunction "6_6") (pintype "passive"))
      (node (ref "SV136") (pin "8") (pinfunction "8_8") (pintype "passive"))
    )
    (net (code "750") (name "Net-(SV137-Pad1)") (class "Default")
      (node (ref "SV137") (pin "1") (pinfunction "1_1") (pintype "passive"))
      (node (ref "SV137") (pin "3") (pinfunction "3_3") (pintype "passive"))
      (node (ref "SV137") (pin "5") (pinfunction "5_5") (pintype "passive"))
      (node (ref "SV137") (pin "7") (pinfunction "7_7") (pintype "passive"))
      (node (ref "SV137") (pin "9") (pinfunction "9_9") (pintype "passive"))
    )
    (net (code "751") (name "Net-(SV137-Pad10)") (class "Default")
      (node (ref "SV137") (pin "10") (pinfunction "10_10") (pintype "passive"))
      (node (ref "SV137") (pin "2") (pinfunction "2_2") (pintype "passive"))
      (node (ref "SV137") (pin "4") (pinfunction "4_4") (pintype "passive"))
      (node (ref "SV137") (pin "6") (pinfunction "6_6") (pintype "passive"))
      (node (ref "SV137") (pin "8") (pinfunction "8_8") (pintype "passive"))
    )
    (net (code "752") (name "Net-(SV138-Pad1)") (class "Default")
      (node (ref "SV138") (pin "1") (pinfunction "1_1") (pintype "passive"))
      (node (ref "SV138") (pin "3") (pinfunction "3_3") (pintype "passive"))
      (node (ref "SV138") (pin "5") (pinfunction "5_5") (pintype "passive"))
      (node (ref "SV138") (pin "7") (pinfunction "7_7") (pintype "passive"))
      (node (ref "SV138") (pin "9") (pinfunction "9_9") (pintype "passive"))
    )
    (net (code "753") (name "Net-(SV138-Pad10)") (class "Default")
      (node (ref "SV138") (pin "10") (pinfunction "10_10") (pintype "passive"))
      (node (ref "SV138") (pin "2") (pinfunction "2_2") (pintype "passive"))
      (node (ref "SV138") (pin "4") (pinfunction "4_4") (pintype "passive"))
      (node (ref "SV138") (pin "6") (pinfunction "6_6") (pintype "passive"))
      (node (ref "SV138") (pin "8") (pinfunction "8_8") (pintype "passive"))
    )
    (net (code "754") (name "Net-(SV139-Pad1)") (class "Default")
      (node (ref "SV139") (pin "1") (pinfunction "1_1") (pintype "passive"))
      (node (ref "SV139") (pin "3") (pinfunction "3_3") (pintype "passive"))
      (node (ref "SV139") (pin "5") (pinfunction "5_5") (pintype "passive"))
      (node (ref "SV139") (pin "7") (pinfunction "7_7") (pintype "passive"))
      (node (ref "SV139") (pin "9") (pinfunction "9_9") (pintype "passive"))
    )
    (net (code "755") (name "Net-(SV139-Pad10)") (class "Default")
      (node (ref "SV139") (pin "10") (pinfunction "10_10") (pintype "passive"))
      (node (ref "SV139") (pin "2") (pinfunction "2_2") (pintype "passive"))
      (node (ref "SV139") (pin "4") (pinfunction "4_4") (pintype "passive"))
      (node (ref "SV139") (pin "6") (pinfunction "6_6") (pintype "passive"))
      (node (ref "SV139") (pin "8") (pinfunction "8_8") (pintype "passive"))
    )
    (net (code "756") (name "Net-(SV140-Pad1)") (class "Default")
      (node (ref "SV140") (pin "1") (pinfunction "1_1") (pintype "passive"))
      (node (ref "SV140") (pin "3") (pinfunction "3_3") (pintype "passive"))
      (node (ref "SV140") (pin "5") (pinfunction "5_5") (pintype "passive"))
      (node (ref "SV140") (pin "7") (pinfunction "7_7") (pintype "passive"))
      (node (ref "SV140") (pin "9") (pinfunction "9_9") (pintype "passive"))
    )
    (net (code "757") (name "Net-(SV140-Pad10)") (class "Default")
      (node (ref "SV140") (pin "10") (pinfunction "10_10") (pintype "passive"))
      (node (ref "SV140") (pin "2") (pinfunction "2_2") (pintype "passive"))
      (node (ref "SV140") (pin "4") (pinfunction "4_4") (pintype "passive"))
      (node (ref "SV140") (pin "6") (pinfunction "6_6") (pintype "passive"))
      (node (ref "SV140") (pin "8") (pinfunction "8_8") (pintype "passive"))
    )
    (net (code "758") (name "Net-(SV141-Pad1)") (class "Default")
      (node (ref "SV141") (pin "1") (pinfunction "1_1") (pintype "passive"))
      (node (ref "SV141") (pin "3") (pinfunction "3_3") (pintype "passive"))
      (node (ref "SV141") (pin "5") (pinfunction "5_5") (pintype "passive"))
      (node (ref "SV141") (pin "7") (pinfunction "7_7") (pintype "passive"))
      (node (ref "SV141") (pin "9") (pinfunction "9_9") (pintype "passive"))
    )
    (net (code "759") (name "Net-(SV141-Pad10)") (class "Default")
      (node (ref "SV141") (pin "10") (pinfunction "10_10") (pintype "passive"))
      (node (ref "SV141") (pin "2") (pinfunction "2_2") (pintype "passive"))
      (node (ref "SV141") (pin "4") (pinfunction "4_4") (pintype "passive"))
      (node (ref "SV141") (pin "6") (pinfunction "6_6") (pintype "passive"))
      (node (ref "SV141") (pin "8") (pinfunction "8_8") (pintype "passive"))
    )
    (net (code "760") (name "Net-(SV142-Pad1)") (class "Default")
      (node (ref "SV142") (pin "1") (pinfunction "1_1") (pintype "passive"))
      (node (ref "SV142") (pin "3") (pinfunction "3_3") (pintype "passive"))
      (node (ref "SV142") (pin "5") (pinfunction "5_5") (pintype "passive"))
      (node (ref "SV142") (pin "7") (pinfunction "7_7") (pintype "passive"))
      (node (ref "SV142") (pin "9") (pinfunction "9_9") (pintype "passive"))
    )
    (net (code "761") (name "Net-(SV142-Pad10)") (class "Default")
      (node (ref "SV142") (pin "10") (pinfunction "10_10") (pintype "passive"))
      (node (ref "SV142") (pin "2") (pinfunction "2_2") (pintype "passive"))
      (node (ref "SV142") (pin "4") (pinfunction "4_4") (pintype "passive"))
      (node (ref "SV142") (pin "6") (pinfunction "6_6") (pintype "passive"))
      (node (ref "SV142") (pin "8") (pinfunction "8_8") (pintype "passive"))
    )
    (net (code "762") (name "Net-(SV143-Pad1)") (class "Default")
      (node (ref "SV143") (pin "1") (pinfunction "1_1") (pintype "passive"))
      (node (ref "SV143") (pin "3") (pinfunction "3_3") (pintype "passive"))
      (node (ref "SV143") (pin "5") (pinfunction "5_5") (pintype "passive"))
      (node (ref "SV143") (pin "7") (pinfunction "7_7") (pintype "passive"))
      (node (ref "SV143") (pin "9") (pinfunction "9_9") (pintype "passive"))
    )
    (net (code "763") (name "Net-(SV143-Pad10)") (class "Default")
      (node (ref "SV143") (pin "10") (pinfunction "10_10") (pintype "passive"))
      (node (ref "SV143") (pin "2") (pinfunction "2_2") (pintype "passive"))
      (node (ref "SV143") (pin "4") (pinfunction "4_4") (pintype "passive"))
      (node (ref "SV143") (pin "6") (pinfunction "6_6") (pintype "passive"))
      (node (ref "SV143") (pin "8") (pinfunction "8_8") (pintype "passive"))
    )
    (net (code "764") (name "Net-(SV144-Pad1)") (class "Default")
      (node (ref "SV144") (pin "1") (pinfunction "1_1") (pintype "passive"))
      (node (ref "SV144") (pin "3") (pinfunction "3_3") (pintype "passive"))
      (node (ref "SV144") (pin "5") (pinfunction "5_5") (pintype "passive"))
      (node (ref "SV144") (pin "7") (pinfunction "7_7") (pintype "passive"))
      (node (ref "SV144") (pin "9") (pinfunction "9_9") (pintype "passive"))
    )
    (net (code "765") (name "Net-(SV144-Pad10)") (class "Default")
      (node (ref "SV144") (pin "10") (pinfunction "10_10") (pintype "passive"))
      (node (ref "SV144") (pin "2") (pinfunction "2_2") (pintype "passive"))
      (node (ref "SV144") (pin "4") (pinfunction "4_4") (pintype "passive"))
      (node (ref "SV144") (pin "6") (pinfunction "6_6") (pintype "passive"))
      (node (ref "SV144") (pin "8") (pinfunction "8_8") (pintype "passive"))
    )
    (net (code "766") (name "Net-(SV145-Pad1)") (class "Default")
      (node (ref "SV145") (pin "1") (pinfunction "1_1") (pintype "passive"))
      (node (ref "SV145") (pin "3") (pinfunction "3_3") (pintype "passive"))
      (node (ref "SV145") (pin "5") (pinfunction "5_5") (pintype "passive"))
      (node (ref "SV145") (pin "7") (pinfunction "7_7") (pintype "passive"))
      (node (ref "SV145") (pin "9") (pinfunction "9_9") (pintype "passive"))
    )
    (net (code "767") (name "Net-(SV145-Pad10)") (class "Default")
      (node (ref "SV145") (pin "10") (pinfunction "10_10") (pintype "passive"))
      (node (ref "SV145") (pin "2") (pinfunction "2_2") (pintype "passive"))
      (node (ref "SV145") (pin "4") (pinfunction "4_4") (pintype "passive"))
      (node (ref "SV145") (pin "6") (pinfunction "6_6") (pintype "passive"))
      (node (ref "SV145") (pin "8") (pinfunction "8_8") (pintype "passive"))
    )
    (net (code "768") (name "Net-(SV146-Pad1)") (class "Default")
      (node (ref "SV146") (pin "1") (pinfunction "1_1") (pintype "passive"))
      (node (ref "SV146") (pin "3") (pinfunction "3_3") (pintype "passive"))
      (node (ref "SV146") (pin "5") (pinfunction "5_5") (pintype "passive"))
      (node (ref "SV146") (pin "7") (pinfunction "7_7") (pintype "passive"))
      (node (ref "SV146") (pin "9") (pinfunction "9_9") (pintype "passive"))
    )
    (net (code "769") (name "Net-(SV146-Pad10)") (class "Default")
      (node (ref "SV146") (pin "10") (pinfunction "10_10") (pintype "passive"))
      (node (ref "SV146") (pin "2") (pinfunction "2_2") (pintype "passive"))
      (node (ref "SV146") (pin "4") (pinfunction "4_4") (pintype "passive"))
      (node (ref "SV146") (pin "6") (pinfunction "6_6") (pintype "passive"))
      (node (ref "SV146") (pin "8") (pinfunction "8_8") (pintype "passive"))
    )
    (net (code "770") (name "Net-(SV147-Pad1)") (class "Default")
      (node (ref "SV147") (pin "1") (pinfunction "1_1") (pintype "passive"))
      (node (ref "SV147") (pin "3") (pinfunction "3_3") (pintype "passive"))
      (node (ref "SV147") (pin "5") (pinfunction "5_5") (pintype "passive"))
      (node (ref "SV147") (pin "7") (pinfunction "7_7") (pintype "passive"))
      (node (ref "SV147") (pin "9") (pinfunction "9_9") (pintype "passive"))
    )
    (net (code "771") (name "Net-(SV147-Pad10)") (class "Default")
      (node (ref "SV147") (pin "10") (pinfunction "10_10") (pintype "passive"))
      (node (ref "SV147") (pin "2") (pinfunction "2_2") (pintype "passive"))
      (node (ref "SV147") (pin "4") (pinfunction "4_4") (pintype "passive"))
      (node (ref "SV147") (pin "6") (pinfunction "6_6") (pintype "passive"))
      (node (ref "SV147") (pin "8") (pinfunction "8_8") (pintype "passive"))
    )
    (net (code "772") (name "Net-(SV148-Pad1)") (class "Default")
      (node (ref "SV148") (pin "1") (pinfunction "1_1") (pintype "passive"))
      (node (ref "SV148") (pin "3") (pinfunction "3_3") (pintype "passive"))
      (node (ref "SV148") (pin "5") (pinfunction "5_5") (pintype "passive"))
      (node (ref "SV148") (pin "7") (pinfunction "7_7") (pintype "passive"))
      (node (ref "SV148") (pin "9") (pinfunction "9_9") (pintype "passive"))
    )
    (net (code "773") (name "Net-(SV148-Pad10)") (class "Default")
      (node (ref "SV148") (pin "10") (pinfunction "10_10") (pintype "passive"))
      (node (ref "SV148") (pin "2") (pinfunction "2_2") (pintype "passive"))
      (node (ref "SV148") (pin "4") (pinfunction "4_4") (pintype "passive"))
      (node (ref "SV148") (pin "6") (pinfunction "6_6") (pintype "passive"))
      (node (ref "SV148") (pin "8") (pinfunction "8_8") (pintype "passive"))
    )
    (net (code "774") (name "Net-(SV149-Pad1)") (class "Default")
      (node (ref "SV149") (pin "1") (pinfunction "1_1") (pintype "passive"))
      (node (ref "SV149") (pin "3") (pinfunction "3_3") (pintype "passive"))
      (node (ref "SV149") (pin "5") (pinfunction "5_5") (pintype "passive"))
      (node (ref "SV149") (pin "7") (pinfunction "7_7") (pintype "passive"))
      (node (ref "SV149") (pin "9") (pinfunction "9_9") (pintype "passive"))
    )
    (net (code "775") (name "Net-(SV149-Pad10)") (class "Default")
      (node (ref "SV149") (pin "10") (pinfunction "10_10") (pintype "passive"))
      (node (ref "SV149") (pin "2") (pinfunction "2_2") (pintype "passive"))
      (node (ref "SV149") (pin "4") (pinfunction "4_4") (pintype "passive"))
      (node (ref "SV149") (pin "6") (pinfunction "6_6") (pintype "passive"))
      (node (ref "SV149") (pin "8") (pinfunction "8_8") (pintype "passive"))
    )
    (net (code "776") (name "Net-(SV150-Pad1)") (class "Default")
      (node (ref "SV150") (pin "1") (pinfunction "1_1") (pintype "passive"))
      (node (ref "SV150") (pin "3") (pinfunction "3_3") (pintype "passive"))
      (node (ref "SV150") (pin "5") (pinfunction "5_5") (pintype "passive"))
      (node (ref "SV150") (pin "7") (pinfunction "7_7") (pintype "passive"))
      (node (ref "SV150") (pin "9") (pinfunction "9_9") (pintype "passive"))
    )
    (net (code "777") (name "Net-(SV150-Pad10)") (class "Default")
      (node (ref "SV150") (pin "10") (pinfunction "10_10") (pintype "passive"))
      (node (ref "SV150") (pin "2") (pinfunction "2_2") (pintype "passive"))
      (node (ref "SV150") (pin "4") (pinfunction "4_4") (pintype "passive"))
      (node (ref "SV150") (pin "6") (pinfunction "6_6") (pintype "passive"))
      (node (ref "SV150") (pin "8") (pinfunction "8_8") (pintype "passive"))
    )
    (net (code "778") (name "Net-(SV151-Pad1)") (class "Default")
      (node (ref "SV151") (pin "1") (pinfunction "1_1") (pintype "passive"))
      (node (ref "SV151") (pin "3") (pinfunction "3_3") (pintype "passive"))
      (node (ref "SV151") (pin "5") (pinfunction "5_5") (pintype "passive"))
      (node (ref "SV151") (pin "7") (pinfunction "7_7") (pintype "passive"))
      (node (ref "SV151") (pin "9") (pinfunction "9_9") (pintype "passive"))
    )
    (net (code "779") (name "Net-(SV151-Pad10)") (class "Default")
      (node (ref "SV151") (pin "10") (pinfunction "10_10") (pintype "passive"))
      (node (ref "SV151") (pin "2") (pinfunction "2_2") (pintype "passive"))
      (node (ref "SV151") (pin "4") (pinfunction "4_4") (pintype "passive"))
      (node (ref "SV151") (pin "6") (pinfunction "6_6") (pintype "passive"))
      (node (ref "SV151") (pin "8") (pinfunction "8_8") (pintype "passive"))
    )
    (net (code "780") (name "Net-(SV152-Pad1)") (class "Default")
      (node (ref "SV152") (pin "1") (pinfunction "1_1") (pintype "passive"))
      (node (ref "SV152") (pin "3") (pinfunction "3_3") (pintype "passive"))
      (node (ref "SV152") (pin "5") (pinfunction "5_5") (pintype "passive"))
      (node (ref "SV152") (pin "7") (pinfunction "7_7") (pintype "passive"))
      (node (ref "SV152") (pin "9") (pinfunction "9_9") (pintype "passive"))
    )
    (net (code "781") (name "Net-(SV152-Pad10)") (class "Default")
      (node (ref "SV152") (pin "10") (pinfunction "10_10") (pintype "passive"))
      (node (ref "SV152") (pin "2") (pinfunction "2_2") (pintype "passive"))
      (node (ref "SV152") (pin "4") (pinfunction "4_4") (pintype "passive"))
      (node (ref "SV152") (pin "6") (pinfunction "6_6") (pintype "passive"))
      (node (ref "SV152") (pin "8") (pinfunction "8_8") (pintype "passive"))
    )
    (net (code "782") (name "Net-(SV153-Pad1)") (class "Default")
      (node (ref "SV153") (pin "1") (pinfunction "1_1") (pintype "passive"))
      (node (ref "SV153") (pin "3") (pinfunction "3_3") (pintype "passive"))
      (node (ref "SV153") (pin "5") (pinfunction "5_5") (pintype "passive"))
      (node (ref "SV153") (pin "7") (pinfunction "7_7") (pintype "passive"))
      (node (ref "SV153") (pin "9") (pinfunction "9_9") (pintype "passive"))
    )
    (net (code "783") (name "Net-(SV153-Pad10)") (class "Default")
      (node (ref "SV153") (pin "10") (pinfunction "10_10") (pintype "passive"))
      (node (ref "SV153") (pin "2") (pinfunction "2_2") (pintype "passive"))
      (node (ref "SV153") (pin "4") (pinfunction "4_4") (pintype "passive"))
      (node (ref "SV153") (pin "6") (pinfunction "6_6") (pintype "passive"))
      (node (ref "SV153") (pin "8") (pinfunction "8_8") (pintype "passive"))
    )
    (net (code "784") (name "Net-(SV154-Pad1)") (class "Default")
      (node (ref "SV154") (pin "1") (pinfunction "1_1") (pintype "passive"))
      (node (ref "SV154") (pin "3") (pinfunction "3_3") (pintype "passive"))
      (node (ref "SV154") (pin "5") (pinfunction "5_5") (pintype "passive"))
      (node (ref "SV154") (pin "7") (pinfunction "7_7") (pintype "passive"))
      (node (ref "SV154") (pin "9") (pinfunction "9_9") (pintype "passive"))
    )
    (net (code "785") (name "Net-(SV154-Pad10)") (class "Default")
      (node (ref "SV154") (pin "10") (pinfunction "10_10") (pintype "passive"))
      (node (ref "SV154") (pin "2") (pinfunction "2_2") (pintype "passive"))
      (node (ref "SV154") (pin "4") (pinfunction "4_4") (pintype "passive"))
      (node (ref "SV154") (pin "6") (pinfunction "6_6") (pintype "passive"))
      (node (ref "SV154") (pin "8") (pinfunction "8_8") (pintype "passive"))
    )
    (net (code "786") (name "Net-(SV155-Pad1)") (class "Default")
      (node (ref "SV155") (pin "1") (pinfunction "1_1") (pintype "passive"))
      (node (ref "SV155") (pin "3") (pinfunction "3_3") (pintype "passive"))
      (node (ref "SV155") (pin "5") (pinfunction "5_5") (pintype "passive"))
      (node (ref "SV155") (pin "7") (pinfunction "7_7") (pintype "passive"))
      (node (ref "SV155") (pin "9") (pinfunction "9_9") (pintype "passive"))
    )
    (net (code "787") (name "Net-(SV155-Pad10)") (class "Default")
      (node (ref "SV155") (pin "10") (pinfunction "10_10") (pintype "passive"))
      (node (ref "SV155") (pin "2") (pinfunction "2_2") (pintype "passive"))
      (node (ref "SV155") (pin "4") (pinfunction "4_4") (pintype "passive"))
      (node (ref "SV155") (pin "6") (pinfunction "6_6") (pintype "passive"))
      (node (ref "SV155") (pin "8") (pinfunction "8_8") (pintype "passive"))
    )
    (net (code "788") (name "Net-(SV156-Pad1)") (class "Default")
      (node (ref "SV156") (pin "1") (pinfunction "1_1") (pintype "passive"))
      (node (ref "SV156") (pin "3") (pinfunction "3_3") (pintype "passive"))
      (node (ref "SV156") (pin "5") (pinfunction "5_5") (pintype "passive"))
      (node (ref "SV156") (pin "7") (pinfunction "7_7") (pintype "passive"))
      (node (ref "SV156") (pin "9") (pinfunction "9_9") (pintype "passive"))
    )
    (net (code "789") (name "Net-(SV156-Pad10)") (class "Default")
      (node (ref "SV156") (pin "10") (pinfunction "10_10") (pintype "passive"))
      (node (ref "SV156") (pin "2") (pinfunction "2_2") (pintype "passive"))
      (node (ref "SV156") (pin "4") (pinfunction "4_4") (pintype "passive"))
      (node (ref "SV156") (pin "6") (pinfunction "6_6") (pintype "passive"))
      (node (ref "SV156") (pin "8") (pinfunction "8_8") (pintype "passive"))
    )
    (net (code "790") (name "Net-(SV157-Pad1)") (class "Default")
      (node (ref "SV157") (pin "1") (pinfunction "1_1") (pintype "passive"))
      (node (ref "SV157") (pin "3") (pinfunction "3_3") (pintype "passive"))
      (node (ref "SV157") (pin "5") (pinfunction "5_5") (pintype "passive"))
      (node (ref "SV157") (pin "7") (pinfunction "7_7") (pintype "passive"))
      (node (ref "SV157") (pin "9") (pinfunction "9_9") (pintype "passive"))
    )
    (net (code "791") (name "Net-(SV157-Pad10)") (class "Default")
      (node (ref "SV157") (pin "10") (pinfunction "10_10") (pintype "passive"))
      (node (ref "SV157") (pin "2") (pinfunction "2_2") (pintype "passive"))
      (node (ref "SV157") (pin "4") (pinfunction "4_4") (pintype "passive"))
      (node (ref "SV157") (pin "6") (pinfunction "6_6") (pintype "passive"))
      (node (ref "SV157") (pin "8") (pinfunction "8_8") (pintype "passive"))
    )
    (net (code "792") (name "Net-(SV158-Pad1)") (class "Default")
      (node (ref "SV158") (pin "1") (pinfunction "1_1") (pintype "passive"))
      (node (ref "SV158") (pin "3") (pinfunction "3_3") (pintype "passive"))
      (node (ref "SV158") (pin "5") (pinfunction "5_5") (pintype "passive"))
      (node (ref "SV158") (pin "7") (pinfunction "7_7") (pintype "passive"))
      (node (ref "SV158") (pin "9") (pinfunction "9_9") (pintype "passive"))
    )
    (net (code "793") (name "Net-(SV158-Pad10)") (class "Default")
      (node (ref "SV158") (pin "10") (pinfunction "10_10") (pintype "passive"))
      (node (ref "SV158") (pin "2") (pinfunction "2_2") (pintype "passive"))
      (node (ref "SV158") (pin "4") (pinfunction "4_4") (pintype "passive"))
      (node (ref "SV158") (pin "6") (pinfunction "6_6") (pintype "passive"))
      (node (ref "SV158") (pin "8") (pinfunction "8_8") (pintype "passive"))
    )
    (net (code "794") (name "Net-(SV159-Pad1)") (class "Default")
      (node (ref "SV159") (pin "1") (pinfunction "1_1") (pintype "passive"))
      (node (ref "SV159") (pin "3") (pinfunction "3_3") (pintype "passive"))
      (node (ref "SV159") (pin "5") (pinfunction "5_5") (pintype "passive"))
      (node (ref "SV159") (pin "7") (pinfunction "7_7") (pintype "passive"))
      (node (ref "SV159") (pin "9") (pinfunction "9_9") (pintype "passive"))
    )
    (net (code "795") (name "Net-(SV159-Pad10)") (class "Default")
      (node (ref "SV159") (pin "10") (pinfunction "10_10") (pintype "passive"))
      (node (ref "SV159") (pin "2") (pinfunction "2_2") (pintype "passive"))
      (node (ref "SV159") (pin "4") (pinfunction "4_4") (pintype "passive"))
      (node (ref "SV159") (pin "6") (pinfunction "6_6") (pintype "passive"))
      (node (ref "SV159") (pin "8") (pinfunction "8_8") (pintype "passive"))
    )
    (net (code "796") (name "Net-(SV160-Pad1)") (class "Default")
      (node (ref "SV160") (pin "1") (pinfunction "1_1") (pintype "passive"))
      (node (ref "SV160") (pin "3") (pinfunction "3_3") (pintype "passive"))
      (node (ref "SV160") (pin "5") (pinfunction "5_5") (pintype "passive"))
      (node (ref "SV160") (pin "7") (pinfunction "7_7") (pintype "passive"))
      (node (ref "SV160") (pin "9") (pinfunction "9_9") (pintype "passive"))
    )
    (net (code "797") (name "Net-(SV160-Pad10)") (class "Default")
      (node (ref "SV160") (pin "10") (pinfunction "10_10") (pintype "passive"))
      (node (ref "SV160") (pin "2") (pinfunction "2_2") (pintype "passive"))
      (node (ref "SV160") (pin "4") (pinfunction "4_4") (pintype "passive"))
      (node (ref "SV160") (pin "6") (pinfunction "6_6") (pintype "passive"))
      (node (ref "SV160") (pin "8") (pinfunction "8_8") (pintype "passive"))
    )
    (net (code "798") (name "Net-(SV161-Pad1)") (class "Default")
      (node (ref "SV161") (pin "1") (pinfunction "1_1") (pintype "passive"))
      (node (ref "SV161") (pin "3") (pinfunction "3_3") (pintype "passive"))
      (node (ref "SV161") (pin "5") (pinfunction "5_5") (pintype "passive"))
      (node (ref "SV161") (pin "7") (pinfunction "7_7") (pintype "passive"))
      (node (ref "SV161") (pin "9") (pinfunction "9_9") (pintype "passive"))
    )
    (net (code "799") (name "Net-(SV161-Pad10)") (class "Default")
      (node (ref "SV161") (pin "10") (pinfunction "10_10") (pintype "passive"))
      (node (ref "SV161") (pin "2") (pinfunction "2_2") (pintype "passive"))
      (node (ref "SV161") (pin "4") (pinfunction "4_4") (pintype "passive"))
      (node (ref "SV161") (pin "6") (pinfunction "6_6") (pintype "passive"))
      (node (ref "SV161") (pin "8") (pinfunction "8_8") (pintype "passive"))
    )
    (net (code "800") (name "Net-(SV162-Pad1)") (class "Default")
      (node (ref "SV162") (pin "1") (pinfunction "1_1") (pintype "passive"))
      (node (ref "SV162") (pin "3") (pinfunction "3_3") (pintype "passive"))
      (node (ref "SV162") (pin "5") (pinfunction "5_5") (pintype "passive"))
      (node (ref "SV162") (pin "7") (pinfunction "7_7") (pintype "passive"))
      (node (ref "SV162") (pin "9") (pinfunction "9_9") (pintype "passive"))
    )
    (net (code "801") (name "Net-(SV162-Pad10)") (class "Default")
      (node (ref "SV162") (pin "10") (pinfunction "10_10") (pintype "passive"))
      (node (ref "SV162") (pin "2") (pinfunction "2_2") (pintype "passive"))
      (node (ref "SV162") (pin "4") (pinfunction "4_4") (pintype "passive"))
      (node (ref "SV162") (pin "6") (pinfunction "6_6") (pintype "passive"))
      (node (ref "SV162") (pin "8") (pinfunction "8_8") (pintype "passive"))
    )
    (net (code "802") (name "Net-(SV163-Pad1)") (class "Default")
      (node (ref "SV163") (pin "1") (pinfunction "1_1") (pintype "passive"))
      (node (ref "SV163") (pin "3") (pinfunction "3_3") (pintype "passive"))
      (node (ref "SV163") (pin "5") (pinfunction "5_5") (pintype "passive"))
      (node (ref "SV163") (pin "7") (pinfunction "7_7") (pintype "passive"))
      (node (ref "SV163") (pin "9") (pinfunction "9_9") (pintype "passive"))
    )
    (net (code "803") (name "Net-(SV163-Pad10)") (class "Default")
      (node (ref "SV163") (pin "10") (pinfunction "10_10") (pintype "passive"))
      (node (ref "SV163") (pin "2") (pinfunction "2_2") (pintype "passive"))
      (node (ref "SV163") (pin "4") (pinfunction "4_4") (pintype "passive"))
      (node (ref "SV163") (pin "6") (pinfunction "6_6") (pintype "passive"))
      (node (ref "SV163") (pin "8") (pinfunction "8_8") (pintype "passive"))
    )
    (net (code "804") (name "Net-(SV164-Pad1)") (class "Default")
      (node (ref "SV164") (pin "1") (pinfunction "1_1") (pintype "passive"))
      (node (ref "SV164") (pin "3") (pinfunction "3_3") (pintype "passive"))
      (node (ref "SV164") (pin "5") (pinfunction "5_5") (pintype "passive"))
      (node (ref "SV164") (pin "7") (pinfunction "7_7") (pintype "passive"))
      (node (ref "SV164") (pin "9") (pinfunction "9_9") (pintype "passive"))
    )
    (net (code "805") (name "Net-(SV164-Pad10)") (class "Default")
      (node (ref "SV164") (pin "10") (pinfunction "10_10") (pintype "passive"))
      (node (ref "SV164") (pin "2") (pinfunction "2_2") (pintype "passive"))
      (node (ref "SV164") (pin "4") (pinfunction "4_4") (pintype "passive"))
      (node (ref "SV164") (pin "6") (pinfunction "6_6") (pintype "passive"))
      (node (ref "SV164") (pin "8") (pinfunction "8_8") (pintype "passive"))
    )
    (net (code "806") (name "Net-(SV165-Pad1)") (class "Default")
      (node (ref "SV165") (pin "1") (pinfunction "1_1") (pintype "passive"))
      (node (ref "SV165") (pin "3") (pinfunction "3_3") (pintype "passive"))
      (node (ref "SV165") (pin "5") (pinfunction "5_5") (pintype "passive"))
      (node (ref "SV165") (pin "7") (pinfunction "7_7") (pintype "passive"))
      (node (ref "SV165") (pin "9") (pinfunction "9_9") (pintype "passive"))
    )
    (net (code "807") (name "Net-(SV165-Pad10)") (class "Default")
      (node (ref "SV165") (pin "10") (pinfunction "10_10") (pintype "passive"))
      (node (ref "SV165") (pin "2") (pinfunction "2_2") (pintype "passive"))
      (node (ref "SV165") (pin "4") (pinfunction "4_4") (pintype "passive"))
      (node (ref "SV165") (pin "6") (pinfunction "6_6") (pintype "passive"))
      (node (ref "SV165") (pin "8") (pinfunction "8_8") (pintype "passive"))
    )
    (net (code "808") (name "Net-(SV166-Pad1)") (class "Default")
      (node (ref "SV166") (pin "1") (pinfunction "1_1") (pintype "passive"))
      (node (ref "SV166") (pin "3") (pinfunction "3_3") (pintype "passive"))
      (node (ref "SV166") (pin "5") (pinfunction "5_5") (pintype "passive"))
      (node (ref "SV166") (pin "7") (pinfunction "7_7") (pintype "passive"))
      (node (ref "SV166") (pin "9") (pinfunction "9_9") (pintype "passive"))
    )
    (net (code "809") (name "Net-(SV166-Pad10)") (class "Default")
      (node (ref "SV166") (pin "10") (pinfunction "10_10") (pintype "passive"))
      (node (ref "SV166") (pin "2") (pinfunction "2_2") (pintype "passive"))
      (node (ref "SV166") (pin "4") (pinfunction "4_4") (pintype "passive"))
      (node (ref "SV166") (pin "6") (pinfunction "6_6") (pintype "passive"))
      (node (ref "SV166") (pin "8") (pinfunction "8_8") (pintype "passive"))
    )
    (net (code "810") (name "Net-(SV167-Pad1)") (class "Default")
      (node (ref "SV167") (pin "1") (pinfunction "1_1") (pintype "passive"))
      (node (ref "SV167") (pin "3") (pinfunction "3_3") (pintype "passive"))
      (node (ref "SV167") (pin "5") (pinfunction "5_5") (pintype "passive"))
      (node (ref "SV167") (pin "7") (pinfunction "7_7") (pintype "passive"))
      (node (ref "SV167") (pin "9") (pinfunction "9_9") (pintype "passive"))
    )
    (net (code "811") (name "Net-(SV167-Pad10)") (class "Default")
      (node (ref "SV167") (pin "10") (pinfunction "10_10") (pintype "passive"))
      (node (ref "SV167") (pin "2") (pinfunction "2_2") (pintype "passive"))
      (node (ref "SV167") (pin "4") (pinfunction "4_4") (pintype "passive"))
      (node (ref "SV167") (pin "6") (pinfunction "6_6") (pintype "passive"))
      (node (ref "SV167") (pin "8") (pinfunction "8_8") (pintype "passive"))
    )
    (net (code "812") (name "Net-(SV168-Pad1)") (class "Default")
      (node (ref "SV168") (pin "1") (pinfunction "1_1") (pintype "passive"))
      (node (ref "SV168") (pin "3") (pinfunction "3_3") (pintype "passive"))
      (node (ref "SV168") (pin "5") (pinfunction "5_5") (pintype "passive"))
      (node (ref "SV168") (pin "7") (pinfunction "7_7") (pintype "passive"))
      (node (ref "SV168") (pin "9") (pinfunction "9_9") (pintype "passive"))
    )
    (net (code "813") (name "Net-(SV168-Pad10)") (class "Default")
      (node (ref "SV168") (pin "10") (pinfunction "10_10") (pintype "passive"))
      (node (ref "SV168") (pin "2") (pinfunction "2_2") (pintype "passive"))
      (node (ref "SV168") (pin "4") (pinfunction "4_4") (pintype "passive"))
      (node (ref "SV168") (pin "6") (pinfunction "6_6") (pintype "passive"))
      (node (ref "SV168") (pin "8") (pinfunction "8_8") (pintype "passive"))
    )
    (net (code "814") (name "Net-(SV169-Pad1)") (class "Default")
      (node (ref "SV169") (pin "1") (pinfunction "1_1") (pintype "passive"))
      (node (ref "SV169") (pin "3") (pinfunction "3_3") (pintype "passive"))
      (node (ref "SV169") (pin "5") (pinfunction "5_5") (pintype "passive"))
      (node (ref "SV169") (pin "7") (pinfunction "7_7") (pintype "passive"))
      (node (ref "SV169") (pin "9") (pinfunction "9_9") (pintype "passive"))
    )
    (net (code "815") (name "Net-(SV169-Pad10)") (class "Default")
      (node (ref "SV169") (pin "10") (pinfunction "10_10") (pintype "passive"))
      (node (ref "SV169") (pin "2") (pinfunction "2_2") (pintype "passive"))
      (node (ref "SV169") (pin "4") (pinfunction "4_4") (pintype "passive"))
      (node (ref "SV169") (pin "6") (pinfunction "6_6") (pintype "passive"))
      (node (ref "SV169") (pin "8") (pinfunction "8_8") (pintype "passive"))
    )
    (net (code "816") (name "Net-(SV170-Pad1)") (class "Default")
      (node (ref "SV170") (pin "1") (pinfunction "1_1") (pintype "passive"))
      (node (ref "SV170") (pin "3") (pinfunction "3_3") (pintype "passive"))
      (node (ref "SV170") (pin "5") (pinfunction "5_5") (pintype "passive"))
      (node (ref "SV170") (pin "7") (pinfunction "7_7") (pintype "passive"))
      (node (ref "SV170") (pin "9") (pinfunction "9_9") (pintype "passive"))
    )
    (net (code "817") (name "Net-(SV170-Pad10)") (class "Default")
      (node (ref "SV170") (pin "10") (pinfunction "10_10") (pintype "passive"))
      (node (ref "SV170") (pin "2") (pinfunction "2_2") (pintype "passive"))
      (node (ref "SV170") (pin "4") (pinfunction "4_4") (pintype "passive"))
      (node (ref "SV170") (pin "6") (pinfunction "6_6") (pintype "passive"))
      (node (ref "SV170") (pin "8") (pinfunction "8_8") (pintype "passive"))
    )
    (net (code "818") (name "Net-(SV171-Pad1)") (class "Default")
      (node (ref "SV171") (pin "1") (pinfunction "1_1") (pintype "passive"))
      (node (ref "SV171") (pin "3") (pinfunction "3_3") (pintype "passive"))
      (node (ref "SV171") (pin "5") (pinfunction "5_5") (pintype "passive"))
      (node (ref "SV171") (pin "7") (pinfunction "7_7") (pintype "passive"))
      (node (ref "SV171") (pin "9") (pinfunction "9_9") (pintype "passive"))
    )
    (net (code "819") (name "Net-(SV171-Pad10)") (class "Default")
      (node (ref "SV171") (pin "10") (pinfunction "10_10") (pintype "passive"))
      (node (ref "SV171") (pin "2") (pinfunction "2_2") (pintype "passive"))
      (node (ref "SV171") (pin "4") (pinfunction "4_4") (pintype "passive"))
      (node (ref "SV171") (pin "6") (pinfunction "6_6") (pintype "passive"))
      (node (ref "SV171") (pin "8") (pinfunction "8_8") (pintype "passive"))
    )
    (net (code "820") (name "Net-(SV172-Pad1)") (class "Default")
      (node (ref "SV172") (pin "1") (pinfunction "1_1") (pintype "passive"))
      (node (ref "SV172") (pin "3") (pinfunction "3_3") (pintype "passive"))
      (node (ref "SV172") (pin "5") (pinfunction "5_5") (pintype "passive"))
      (node (ref "SV172") (pin "7") (pinfunction "7_7") (pintype "passive"))
      (node (ref "SV172") (pin "9") (pinfunction "9_9") (pintype "passive"))
    )
    (net (code "821") (name "Net-(SV172-Pad10)") (class "Default")
      (node (ref "SV172") (pin "10") (pinfunction "10_10") (pintype "passive"))
      (node (ref "SV172") (pin "2") (pinfunction "2_2") (pintype "passive"))
      (node (ref "SV172") (pin "4") (pinfunction "4_4") (pintype "passive"))
      (node (ref "SV172") (pin "6") (pinfunction "6_6") (pintype "passive"))
      (node (ref "SV172") (pin "8") (pinfunction "8_8") (pintype "passive"))
    )
    (net (code "822") (name "Net-(SV173-Pad1)") (class "Default")
      (node (ref "SV173") (pin "1") (pinfunction "1_1") (pintype "passive"))
      (node (ref "SV173") (pin "3") (pinfunction "3_3") (pintype "passive"))
      (node (ref "SV173") (pin "5") (pinfunction "5_5") (pintype "passive"))
      (node (ref "SV173") (pin "7") (pinfunction "7_7") (pintype "passive"))
      (node (ref "SV173") (pin "9") (pinfunction "9_9") (pintype "passive"))
    )
    (net (code "823") (name "Net-(SV173-Pad10)") (class "Default")
      (node (ref "SV173") (pin "10") (pinfunction "10_10") (pintype "passive"))
      (node (ref "SV173") (pin "2") (pinfunction "2_2") (pintype "passive"))
      (node (ref "SV173") (pin "4") (pinfunction "4_4") (pintype "passive"))
      (node (ref "SV173") (pin "6") (pinfunction "6_6") (pintype "passive"))
      (node (ref "SV173") (pin "8") (pinfunction "8_8") (pintype "passive"))
    )
    (net (code "824") (name "Net-(SV174-Pad1)") (class "Default")
      (node (ref "SV174") (pin "1") (pinfunction "1_1") (pintype "passive"))
      (node (ref "SV174") (pin "3") (pinfunction "3_3") (pintype "passive"))
      (node (ref "SV174") (pin "5") (pinfunction "5_5") (pintype "passive"))
      (node (ref "SV174") (pin "7") (pinfunction "7_7") (pintype "passive"))
      (node (ref "SV174") (pin "9") (pinfunction "9_9") (pintype "passive"))
    )
    (net (code "825") (name "Net-(SV174-Pad10)") (class "Default")
      (node (ref "SV174") (pin "10") (pinfunction "10_10") (pintype "passive"))
      (node (ref "SV174") (pin "2") (pinfunction "2_2") (pintype "passive"))
      (node (ref "SV174") (pin "4") (pinfunction "4_4") (pintype "passive"))
      (node (ref "SV174") (pin "6") (pinfunction "6_6") (pintype "passive"))
      (node (ref "SV174") (pin "8") (pinfunction "8_8") (pintype "passive"))
    )
    (net (code "826") (name "Net-(U$2A-1)") (class "Default")
      (node (ref "D9") (pin "1") (pinfunction "1_1") (pintype "passive"))
      (node (ref "U$2") (pin "AA1") (pinfunction "1_AA1") (pintype "passive"))
    )
    (net (code "827") (name "Net-(U$2AK-1)") (class "Default")
      (node (ref "D7") (pin "1") (pinfunction "1_1") (pintype "passive"))
      (node (ref "U$2") (pin "BA1") (pinfunction "1_BA1") (pintype "passive"))
    )
    (net (code "828") (name "Net-(U$2AM-1)") (class "Default")
      (node (ref "D7") (pin "2") (pinfunction "2_2") (pintype "passive"))
      (node (ref "U$2") (pin "BB1") (pinfunction "1_BB1") (pintype "passive"))
    )
    (net (code "829") (name "Net-(U$2BN-1)") (class "Default")
      (node (ref "D8") (pin "15") (pinfunction "15_15") (pintype "passive"))
      (node (ref "U$2") (pin "BS2") (pinfunction "1_BS2") (pintype "passive"))
    )
    (net (code "830") (name "Net-(U$2BU-1)") (class "Default")
      (node (ref "D11") (pin "1") (pinfunction "1_1") (pintype "passive"))
      (node (ref "U$2") (pin "CA1") (pinfunction "1_CA1") (pintype "passive"))
    )
    (net (code "831") (name "Net-(U$2BW-1)") (class "Default")
      (node (ref "D11") (pin "2") (pinfunction "2_2") (pintype "passive"))
      (node (ref "U$2") (pin "CB1") (pinfunction "1_CB1") (pintype "passive"))
    )
    (net (code "832") (name "Net-(U$2C-1)") (class "Default")
      (node (ref "D9") (pin "2") (pinfunction "2_2") (pintype "passive"))
      (node (ref "U$2") (pin "AB1") (pinfunction "1_AB1") (pintype "passive"))
    )
    (net (code "833") (name "Net-(U$2DE-1)") (class "Default")
      (node (ref "D13") (pin "1") (pinfunction "1_1") (pintype "passive"))
      (node (ref "U$2") (pin "DA1") (pinfunction "1_DA1") (pintype "passive"))
    )
    (net (code "834") (name "Net-(U$2DG-1)") (class "Default")
      (node (ref "D13") (pin "2") (pinfunction "2_2") (pintype "passive"))
      (node (ref "U$2") (pin "DB1") (pinfunction "1_DB1") (pintype "passive"))
    )
    (net (code "835") (name "POWER_OK") (class "Default")
      (node (ref "D8") (pin "18") (pinfunction "18_18") (pintype "passive"))
      (node (ref "R6") (pin "1") (pinfunction "1_1") (pintype "passive"))
      (node (ref "U$2") (pin "BV2") (pinfunction "1_BV2") (pintype "passive"))
    )
    (net (code "836") (name "PULSE_LA") (class "Default")
      (node (ref "D14") (pin "14") (pinfunction "14_14") (pintype "passive"))
      (node (ref "U$2") (pin "DR2") (pinfunction "1_DR2") (pintype "passive"))
    )
    (net (code "837") (name "RETURN") (class "Default")
      (node (ref "D10") (pin "14") (pinfunction "14_14") (pintype "passive"))
      (node (ref "U$2") (pin "AR2") (pinfunction "1_AR2") (pintype "passive"))
    )
    (net (code "838") (name "SOURCE") (class "Default")
      (node (ref "D10") (pin "10") (pinfunction "10_10") (pintype "passive"))
      (node (ref "IC8") (pin "6") (pinfunction "A5_6") (pintype "input"))
      (node (ref "U$2") (pin "AL2") (pinfunction "1_AL2") (pintype "passive"))
    )
    (net (code "839") (name "STROBE") (class "Default")
      (node (ref "D10") (pin "11") (pinfunction "11_11") (pintype "passive"))
      (node (ref "U$2") (pin "AM2") (pinfunction "1_AM2") (pintype "passive"))
    )
    (net (code "840") (name "SWITCH") (class "Default")
      (node (ref "D14") (pin "18") (pinfunction "18_18") (pintype "passive"))
      (node (ref "U$2") (pin "DV2") (pinfunction "1_DV2") (pintype "passive"))
    )
    (net (code "841") (name "TP1") (class "Default")
      (node (ref "D12") (pin "4") (pinfunction "4_4") (pintype "passive"))
      (node (ref "U$2") (pin "CD2") (pinfunction "1_CD2") (pintype "passive"))
    )
    (net (code "842") (name "TP2") (class "Default")
      (node (ref "D12") (pin "5") (pinfunction "5_5") (pintype "passive"))
      (node (ref "U$2") (pin "CE2") (pinfunction "1_CE2") (pintype "passive"))
    )
    (net (code "843") (name "TP3") (class "Default")
      (node (ref "D12") (pin "7") (pinfunction "7_7") (pintype "passive"))
      (node (ref "U$2") (pin "CH2") (pinfunction "1_CH2") (pintype "passive"))
    )
    (net (code "844") (name "TP4") (class "Default")
      (node (ref "D12") (pin "8") (pinfunction "8_8") (pintype "passive"))
      (node (ref "U$2") (pin "CJ2") (pinfunction "1_CJ2") (pintype "passive"))
    )
    (net (code "845") (name "V+") (class "Default")
      (node (ref "C1") (pin "1") (pinfunction "1_1") (pintype "passive"))
      (node (ref "C3") (pin "1") (pinfunction "1_1") (pintype "passive"))
      (node (ref "D1") (pin "C") (pinfunction "C_C") (pintype "passive"))
      (node (ref "D2") (pin "C") (pinfunction "C_C") (pintype "passive"))
      (node (ref "IC3") (pin "28") (pinfunction "VCC_28") (pintype "power_in"))
      (node (ref "IC4") (pin "28") (pinfunction "VCC_28") (pintype "power_in"))
      (node (ref "R7") (pin "2") (pinfunction "2_2") (pintype "passive"))
    )
    (net (code "846") (name "VCC") (class "Default")
      (node (ref "C10") (pin "+") (pinfunction "+_+") (pintype "passive"))
      (node (ref "C4") (pin "1") (pinfunction "1_1") (pintype "passive"))
      (node (ref "C5") (pin "1") (pinfunction "1_1") (pintype "passive"))
      (node (ref "C6") (pin "1") (pinfunction "1_1") (pintype "passive"))
      (node (ref "C7") (pin "1") (pinfunction "1_1") (pintype "passive"))
      (node (ref "C8") (pin "1") (pinfunction "1_1") (pintype "passive"))
      (node (ref "C9") (pin "1") (pinfunction "1_1") (pintype "passive"))
      (node (ref "D10") (pin "1") (pinfunction "1_1") (pintype "passive"))
      (node (ref "D12") (pin "1") (pinfunction "1_1") (pintype "passive"))
      (node (ref "D2") (pin "A") (pinfunction "A_A") (pintype "passive"))
      (node (ref "D8") (pin "1") (pinfunction "1_1") (pintype "passive"))
      (node (ref "IC7") (pin "1") (pinfunction "I0_1") (pintype "input"))
      (node (ref "IC7") (pin "12") (pinfunction "I2_12") (pintype "input"))
      (node (ref "IC7") (pin "13") (pinfunction "I3_13") (pintype "input"))
      (node (ref "R5") (pin "10") (pinfunction "2_10") (pintype "passive"))
      (node (ref "R5") (pin "11") (pinfunction "2_11") (pintype "passive"))
      (node (ref "R5") (pin "12") (pinfunction "2_12") (pintype "passive"))
      (node (ref "R5") (pin "13") (pinfunction "2_13") (pintype "passive"))
      (node (ref "R5") (pin "14") (pinfunction "2_14") (pintype "passive"))
      (node (ref "R5") (pin "15") (pinfunction "2_15") (pintype "passive"))
      (node (ref "R5") (pin "16") (pinfunction "2_16") (pintype "passive"))
      (node (ref "R5") (pin "9") (pinfunction "2_9") (pintype "passive"))
      (node (ref "SV11") (pin "1") (pinfunction "1_1") (pintype "passive"))
      (node (ref "SV11") (pin "10") (pinfunction "10_10") (pintype "passive"))
      (node (ref "SV11") (pin "2") (pinfunction "2_2") (pintype "passive"))
      (node (ref "SV11") (pin "3") (pinfunction "3_3") (pintype "passive"))
      (node (ref "SV11") (pin "4") (pinfunction "4_4") (pintype "passive"))
      (node (ref "SV11") (pin "5") (pinfunction "5_5") (pintype "passive"))
      (node (ref "SV11") (pin "6") (pinfunction "6_6") (pintype "passive"))
      (node (ref "SV11") (pin "7") (pinfunction "7_7") (pintype "passive"))
      (node (ref "SV11") (pin "8") (pinfunction "8_8") (pintype "passive"))
      (node (ref "SV11") (pin "9") (pinfunction "9_9") (pintype "passive"))
      (node (ref "SV125") (pin "1") (pinfunction "1_1") (pintype "passive"))
      (node (ref "SV125") (pin "10") (pinfunction "10_10") (pintype "passive"))
      (node (ref "SV125") (pin "11") (pinfunction "11_11") (pintype "passive"))
      (node (ref "SV125") (pin "12") (pinfunction "12_12") (pintype "passive"))
      (node (ref "SV125") (pin "13") (pinfunction "13_13") (pintype "passive"))
      (node (ref "SV125") (pin "14") (pinfunction "14_14") (pintype "passive"))
      (node (ref "SV125") (pin "15") (pinfunction "15_15") (pintype "passive"))
      (node (ref "SV125") (pin "16") (pinfunction "16_16") (pintype "passive"))
      (node (ref "SV125") (pin "17") (pinfunction "17_17") (pintype "passive"))
      (node (ref "SV125") (pin "18") (pinfunction "18_18") (pintype "passive"))
      (node (ref "SV125") (pin "19") (pinfunction "19_19") (pintype "passive"))
      (node (ref "SV125") (pin "2") (pinfunction "2_2") (pintype "passive"))
      (node (ref "SV125") (pin "20") (pinfunction "20_20") (pintype "passive"))
      (node (ref "SV125") (pin "3") (pinfunction "3_3") (pintype "passive"))
      (node (ref "SV125") (pin "4") (pinfunction "4_4") (pintype "passive"))
      (node (ref "SV125") (pin "5") (pinfunction "5_5") (pintype "passive"))
      (node (ref "SV125") (pin "6") (pinfunction "6_6") (pintype "passive"))
      (node (ref "SV125") (pin "7") (pinfunction "7_7") (pintype "passive"))
      (node (ref "SV125") (pin "8") (pinfunction "8_8") (pintype "passive"))
      (node (ref "SV125") (pin "9") (pinfunction "9_9") (pintype "passive"))
      (node (ref "SV127") (pin "1") (pinfunction "1_1") (pintype "passive"))
      (node (ref "SV127") (pin "2") (pinfunction "2_2") (pintype "passive"))
      (node (ref "SV127") (pin "3") (pinfunction "3_3") (pintype "passive"))
      (node (ref "SV127") (pin "4") (pinfunction "4_4") (pintype "passive"))
      (node (ref "SV127") (pin "5") (pinfunction "5_5") (pintype "passive"))
      (node (ref "SV127") (pin "6") (pinfunction "6_6") (pintype "passive"))
      (node (ref "SV127") (pin "7") (pinfunction "7_7") (pintype "passive"))
      (node (ref "SV127") (pin "8") (pinfunction "8_8") (pintype "passive"))
      (node (ref "SV129") (pin "1") (pinfunction "1_1") (pintype "passive"))
      (node (ref "SV129") (pin "10") (pinfunction "10_10") (pintype "passive"))
      (node (ref "SV129") (pin "2") (pinfunction "2_2") (pintype "passive"))
      (node (ref "SV129") (pin "3") (pinfunction "3_3") (pintype "passive"))
      (node (ref "SV129") (pin "4") (pinfunction "4_4") (pintype "passive"))
      (node (ref "SV129") (pin "5") (pinfunction "5_5") (pintype "passive"))
      (node (ref "SV129") (pin "6") (pinfunction "6_6") (pintype "passive"))
      (node (ref "SV129") (pin "7") (pinfunction "7_7") (pintype "passive"))
      (node (ref "SV129") (pin "8") (pinfunction "8_8") (pintype "passive"))
      (node (ref "SV129") (pin "9") (pinfunction "9_9") (pintype "passive"))
      (node (ref "SV131") (pin "1") (pinfunction "1_1") (pintype "passive"))
      (node (ref "SV131") (pin "10") (pinfunction "10_10") (pintype "passive"))
      (node (ref "SV131") (pin "11") (pinfunction "11_11") (pintype "passive"))
      (node (ref "SV131") (pin "12") (pinfunction "12_12") (pintype "passive"))
      (node (ref "SV131") (pin "13") (pinfunction "13_13") (pintype "passive"))
      (node (ref "SV131") (pin "14") (pinfunction "14_14") (pintype "passive"))
      (node (ref "SV131") (pin "15") (pinfunction "15_15") (pintype "passive"))
      (node (ref "SV131") (pin "16") (pinfunction "16_16") (pintype "passive"))
      (node (ref "SV131") (pin "17") (pinfunction "17_17") (pintype "passive"))
      (node (ref "SV131") (pin "18") (pinfunction "18_18") (pintype "passive"))
      (node (ref "SV131") (pin "19") (pinfunction "19_19") (pintype "passive"))
      (node (ref "SV131") (pin "2") (pinfunction "2_2") (pintype "passive"))
      (node (ref "SV131") (pin "20") (pinfunction "20_20") (pintype "passive"))
      (node (ref "SV131") (pin "3") (pinfunction "3_3") (pintype "passive"))
      (node (ref "SV131") (pin "4") (pinfunction "4_4") (pintype "passive"))
      (node (ref "SV131") (pin "5") (pinfunction "5_5") (pintype "passive"))
      (node (ref "SV131") (pin "6") (pinfunction "6_6") (pintype "passive"))
      (node (ref "SV131") (pin "7") (pinfunction "7_7") (pintype "passive"))
      (node (ref "SV131") (pin "8") (pinfunction "8_8") (pintype "passive"))
      (node (ref "SV131") (pin "9") (pinfunction "9_9") (pintype "passive"))
      (node (ref "SV175") (pin "1") (pinfunction "1_1") (pintype "passive"))
      (node (ref "SV175") (pin "10") (pinfunction "10_10") (pintype "passive"))
      (node (ref "SV175") (pin "11") (pinfunction "11_11") (pintype "passive"))
      (node (ref "SV175") (pin "12") (pinfunction "12_12") (pintype "passive"))
      (node (ref "SV175") (pin "13") (pinfunction "13_13") (pintype "passive"))
      (node (ref "SV175") (pin "14") (pinfunction "14_14") (pintype "passive"))
      (node (ref "SV175") (pin "15") (pinfunction "15_15") (pintype "passive"))
      (node (ref "SV175") (pin "16") (pinfunction "16_16") (pintype "passive"))
      (node (ref "SV175") (pin "17") (pinfunction "17_17") (pintype "passive"))
      (node (ref "SV175") (pin "18") (pinfunction "18_18") (pintype "passive"))
      (node (ref "SV175") (pin "19") (pinfunction "19_19") (pintype "passive"))
      (node (ref "SV175") (pin "2") (pinfunction "2_2") (pintype "passive"))
      (node (ref "SV175") (pin "20") (pinfunction "20_20") (pintype "passive"))
      (node (ref "SV175") (pin "3") (pinfunction "3_3") (pintype "passive"))
      (node (ref "SV175") (pin "4") (pinfunction "4_4") (pintype "passive"))
      (node (ref "SV175") (pin "5") (pinfunction "5_5") (pintype "passive"))
      (node (ref "SV175") (pin "6") (pinfunction "6_6") (pintype "passive"))
      (node (ref "SV175") (pin "7") (pinfunction "7_7") (pintype "passive"))
      (node (ref "SV175") (pin "8") (pinfunction "8_8") (pintype "passive"))
      (node (ref "SV175") (pin "9") (pinfunction "9_9") (pintype "passive"))
      (node (ref "SV177") (pin "1") (pinfunction "1_1") (pintype "passive"))
      (node (ref "SV177") (pin "2") (pinfunction "2_2") (pintype "passive"))
      (node (ref "SV177") (pin "3") (pinfunction "3_3") (pintype "passive"))
      (node (ref "SV177") (pin "4") (pinfunction "4_4") (pintype "passive"))
      (node (ref "SV177") (pin "5") (pinfunction "5_5") (pintype "passive"))
      (node (ref "SV177") (pin "6") (pinfunction "6_6") (pintype "passive"))
      (node (ref "SV177") (pin "7") (pinfunction "7_7") (pintype "passive"))
      (node (ref "SV177") (pin "8") (pinfunction "8_8") (pintype "passive"))
      (node (ref "SV178") (pin "1") (pinfunction "1_1") (pintype "passive"))
      (node (ref "SV178") (pin "2") (pinfunction "2_2") (pintype "passive"))
      (node (ref "SV178") (pin "3") (pinfunction "3_3") (pintype "passive"))
      (node (ref "SV178") (pin "4") (pinfunction "4_4") (pintype "passive"))
      (node (ref "SV178") (pin "5") (pinfunction "5_5") (pintype "passive"))
      (node (ref "SV178") (pin "6") (pinfunction "6_6") (pintype "passive"))
      (node (ref "SV178") (pin "7") (pinfunction "7_7") (pintype "passive"))
      (node (ref "SV178") (pin "8") (pinfunction "8_8") (pintype "passive"))
      (node (ref "SV179") (pin "1") (pinfunction "1_1") (pintype "passive"))
      (node (ref "SV179") (pin "10") (pinfunction "10_10") (pintype "passive"))
      (node (ref "SV179") (pin "2") (pinfunction "2_2") (pintype "passive"))
      (node (ref "SV179") (pin "3") (pinfunction "3_3") (pintype "passive"))
      (node (ref "SV179") (pin "4") (pinfunction "4_4") (pintype "passive"))
      (node (ref "SV179") (pin "5") (pinfunction "5_5") (pintype "passive"))
      (node (ref "SV179") (pin "6") (pinfunction "6_6") (pintype "passive"))
      (node (ref "SV179") (pin "7") (pinfunction "7_7") (pintype "passive"))
      (node (ref "SV179") (pin "8") (pinfunction "8_8") (pintype "passive"))
      (node (ref "SV179") (pin "9") (pinfunction "9_9") (pintype "passive"))
      (node (ref "SV3") (pin "1") (pinfunction "1_1") (pintype "passive"))
      (node (ref "SV3") (pin "10") (pinfunction "10_10") (pintype "passive"))
      (node (ref "SV3") (pin "11") (pinfunction "11_11") (pintype "passive"))
      (node (ref "SV3") (pin "12") (pinfunction "12_12") (pintype "passive"))
      (node (ref "SV3") (pin "13") (pinfunction "13_13") (pintype "passive"))
      (node (ref "SV3") (pin "14") (pinfunction "14_14") (pintype "passive"))
      (node (ref "SV3") (pin "15") (pinfunction "15_15") (pintype "passive"))
      (node (ref "SV3") (pin "16") (pinfunction "16_16") (pintype "passive"))
      (node (ref "SV3") (pin "17") (pinfunction "17_17") (pintype "passive"))
      (node (ref "SV3") (pin "18") (pinfunction "18_18") (pintype "passive"))
      (node (ref "SV3") (pin "19") (pinfunction "19_19") (pintype "passive"))
      (node (ref "SV3") (pin "2") (pinfunction "2_2") (pintype "passive"))
      (node (ref "SV3") (pin "20") (pinfunction "20_20") (pintype "passive"))
      (node (ref "SV3") (pin "3") (pinfunction "3_3") (pintype "passive"))
      (node (ref "SV3") (pin "4") (pinfunction "4_4") (pintype "passive"))
      (node (ref "SV3") (pin "5") (pinfunction "5_5") (pintype "passive"))
      (node (ref "SV3") (pin "6") (pinfunction "6_6") (pintype "passive"))
      (node (ref "SV3") (pin "7") (pinfunction "7_7") (pintype "passive"))
      (node (ref "SV3") (pin "8") (pinfunction "8_8") (pintype "passive"))
      (node (ref "SV3") (pin "9") (pinfunction "9_9") (pintype "passive"))
      (node (ref "SV5") (pin "1") (pinfunction "1_1") (pintype "passive"))
      (node (ref "SV5") (pin "10") (pinfunction "10_10") (pintype "passive"))
      (node (ref "SV5") (pin "11") (pinfunction "11_11") (pintype "passive"))
      (node (ref "SV5") (pin "12") (pinfunction "12_12") (pintype "passive"))
      (node (ref "SV5") (pin "13") (pinfunction "13_13") (pintype "passive"))
      (node (ref "SV5") (pin "14") (pinfunction "14_14") (pintype "passive"))
      (node (ref "SV5") (pin "15") (pinfunction "15_15") (pintype "passive"))
      (node (ref "SV5") (pin "16") (pinfunction "16_16") (pintype "passive"))
      (node (ref "SV5") (pin "17") (pinfunction "17_17") (pintype "passive"))
      (node (ref "SV5") (pin "18") (pinfunction "18_18") (pintype "passive"))
      (node (ref "SV5") (pin "19") (pinfunction "19_19") (pintype "passive"))
      (node (ref "SV5") (pin "2") (pinfunction "2_2") (pintype "passive"))
      (node (ref "SV5") (pin "20") (pinfunction "20_20") (pintype "passive"))
      (node (ref "SV5") (pin "3") (pinfunction "3_3") (pintype "passive"))
      (node (ref "SV5") (pin "4") (pinfunction "4_4") (pintype "passive"))
      (node (ref "SV5") (pin "5") (pinfunction "5_5") (pintype "passive"))
      (node (ref "SV5") (pin "6") (pinfunction "6_6") (pintype "passive"))
      (node (ref "SV5") (pin "7") (pinfunction "7_7") (pintype "passive"))
      (node (ref "SV5") (pin "8") (pinfunction "8_8") (pintype "passive"))
      (node (ref "SV5") (pin "9") (pinfunction "9_9") (pintype "passive"))
      (node (ref "SV9") (pin "1") (pinfunction "1_1") (pintype "passive"))
      (node (ref "SV9") (pin "2") (pinfunction "2_2") (pintype "passive"))
      (node (ref "SV9") (pin "3") (pinfunction "3_3") (pintype "passive"))
      (node (ref "SV9") (pin "4") (pinfunction "4_4") (pintype "passive"))
      (node (ref "SV9") (pin "5") (pinfunction "5_5") (pintype "passive"))
      (node (ref "SV9") (pin "6") (pinfunction "6_6") (pintype "passive"))
      (node (ref "SV9") (pin "7") (pinfunction "7_7") (pintype "passive"))
      (node (ref "SV9") (pin "8") (pinfunction "8_8") (pintype "passive"))
      (node (ref "U$2") (pin "AA2") (pinfunction "1_AA2") (pintype "passive"))
      (node (ref "U$2") (pin "BA2") (pinfunction "1_BA2") (pintype "passive"))
      (node (ref "U$2") (pin "CA2") (pinfunction "1_CA2") (pintype "passive"))
      (node (ref "VCC1") (pin "1") (pinfunction "1_1") (pintype "passive"))
      (node (ref "VCC1") (pin "2") (pinfunction "2_2") (pintype "passive"))
      (node (ref "VCC10") (pin "1") (pinfunction "1_1") (pintype "passive"))
      (node (ref "VCC10") (pin "2") (pinfunction "2_2") (pintype "passive"))
      (node (ref "VCC11") (pin "1") (pinfunction "1_1") (pintype "passive"))
      (node (ref "VCC11") (pin "2") (pinfunction "2_2") (pintype "passive"))
      (node (ref "VCC12") (pin "1") (pinfunction "1_1") (pintype "passive"))
      (node (ref "VCC12") (pin "2") (pinfunction "2_2") (pintype "passive"))
      (node (ref "VCC13") (pin "1") (pinfunction "1_1") (pintype "passive"))
      (node (ref "VCC13") (pin "2") (pinfunction "2_2") (pintype "passive"))
      (node (ref "VCC14") (pin "1") (pinfunction "1_1") (pintype "passive"))
      (node (ref "VCC14") (pin "2") (pinfunction "2_2") (pintype "passive"))
      (node (ref "VCC15") (pin "1") (pinfunction "1_1") (pintype "passive"))
      (node (ref "VCC15") (pin "2") (pinfunction "2_2") (pintype "passive"))
      (node (ref "VCC16") (pin "1") (pinfunction "1_1") (pintype "passive"))
      (node (ref "VCC16") (pin "2") (pinfunction "2_2") (pintype "passive"))
      (node (ref "VCC17") (pin "1") (pinfunction "1_1") (pintype "passive"))
      (node (ref "VCC17") (pin "2") (pinfunction "2_2") (pintype "passive"))
      (node (ref "VCC18") (pin "1") (pinfunction "1_1") (pintype "passive"))
      (node (ref "VCC18") (pin "2") (pinfunction "2_2") (pintype "passive"))
      (node (ref "VCC19") (pin "1") (pinfunction "1_1") (pintype "passive"))
      (node (ref "VCC19") (pin "2") (pinfunction "2_2") (pintype "passive"))
      (node (ref "VCC2") (pin "1") (pinfunction "1_1") (pintype "passive"))
      (node (ref "VCC2") (pin "2") (pinfunction "2_2") (pintype "passive"))
      (node (ref "VCC20") (pin "1") (pinfunction "1_1") (pintype "passive"))
      (node (ref "VCC20") (pin "2") (pinfunction "2_2") (pintype "passive"))
      (node (ref "VCC21") (pin "1") (pinfunction "1_1") (pintype "passive"))
      (node (ref "VCC21") (pin "2") (pinfunction "2_2") (pintype "passive"))
      (node (ref "VCC22") (pin "1") (pinfunction "1_1") (pintype "passive"))
      (node (ref "VCC22") (pin "2") (pinfunction "2_2") (pintype "passive"))
      (node (ref "VCC23") (pin "1") (pinfunction "1_1") (pintype "passive"))
      (node (ref "VCC23") (pin "2") (pinfunction "2_2") (pintype "passive"))
      (node (ref "VCC24") (pin "1") (pinfunction "1_1") (pintype "passive"))
      (node (ref "VCC24") (pin "2") (pinfunction "2_2") (pintype "passive"))
      (node (ref "VCC25") (pin "1") (pinfunction "1_1") (pintype "passive"))
      (node (ref "VCC25") (pin "2") (pinfunction "2_2") (pintype "passive"))
      (node (ref "VCC26") (pin "1") (pinfunction "1_1") (pintype "passive"))
      (node (ref "VCC26") (pin "2") (pinfunction "2_2") (pintype "passive"))
      (node (ref "VCC27") (pin "1") (pinfunction "1_1") (pintype "passive"))
      (node (ref "VCC27") (pin "2") (pinfunction "2_2") (pintype "passive"))
      (node (ref "VCC28") (pin "1") (pinfunction "1_1") (pintype "passive"))
      (node (ref "VCC28") (pin "2") (pinfunction "2_2") (pintype "passive"))
      (node (ref "VCC29") (pin "1") (pinfunction "1_1") (pintype "passive"))
      (node (ref "VCC29") (pin "2") (pinfunction "2_2") (pintype "passive"))
      (node (ref "VCC3") (pin "1") (pinfunction "1_1") (pintype "passive"))
      (node (ref "VCC3") (pin "2") (pinfunction "2_2") (pintype "passive"))
      (node (ref "VCC30") (pin "1") (pinfunction "1_1") (pintype "passive"))
      (node (ref "VCC30") (pin "2") (pinfunction "2_2") (pintype "passive"))
      (node (ref "VCC31") (pin "1") (pinfunction "1_1") (pintype "passive"))
      (node (ref "VCC31") (pin "2") (pinfunction "2_2") (pintype "passive"))
      (node (ref "VCC32") (pin "1") (pinfunction "1_1") (pintype "passive"))
      (node (ref "VCC32") (pin "2") (pinfunction "2_2") (pintype "passive"))
      (node (ref "VCC33") (pin "1") (pinfunction "1_1") (pintype "passive"))
      (node (ref "VCC33") (pin "2") (pinfunction "2_2") (pintype "passive"))
      (node (ref "VCC34") (pin "1") (pinfunction "1_1") (pintype "passive"))
      (node (ref "VCC34") (pin "2") (pinfunction "2_2") (pintype "passive"))
      (node (ref "VCC35") (pin "1") (pinfunction "1_1") (pintype "passive"))
      (node (ref "VCC35") (pin "2") (pinfunction "2_2") (pintype "passive"))
      (node (ref "VCC36") (pin "1") (pinfunction "1_1") (pintype "passive"))
      (node (ref "VCC36") (pin "2") (pinfunction "2_2") (pintype "passive"))
      (node (ref "VCC37") (pin "1") (pinfunction "1_1") (pintype "passive"))
      (node (ref "VCC37") (pin "2") (pinfunction "2_2") (pintype "passive"))
      (node (ref "VCC38") (pin "1") (pinfunction "1_1") (pintype "passive"))
      (node (ref "VCC38") (pin "2") (pinfunction "2_2") (pintype "passive"))
      (node (ref "VCC39") (pin "1") (pinfunction "1_1") (pintype "passive"))
      (node (ref "VCC39") (pin "2") (pinfunction "2_2") (pintype "passive"))
      (node (ref "VCC4") (pin "1") (pinfunction "1_1") (pintype "passive"))
      (node (ref "VCC4") (pin "2") (pinfunction "2_2") (pintype "passive"))
      (node (ref "VCC40") (pin "1") (pinfunction "1_1") (pintype "passive"))
      (node (ref "VCC40") (pin "2") (pinfunction "2_2") (pintype "passive"))
      (node (ref "VCC41") (pin "1") (pinfunction "1_1") (pintype "passive"))
      (node (ref "VCC41") (pin "2") (pinfunction "2_2") (pintype "passive"))
      (node (ref "VCC42") (pin "1") (pinfunction "1_1") (pintype "passive"))
      (node (ref "VCC42") (pin "2") (pinfunction "2_2") (pintype "passive"))
      (node (ref "VCC43") (pin "1") (pinfunction "1_1") (pintype "passive"))
      (node (ref "VCC43") (pin "2") (pinfunction "2_2") (pintype "passive"))
      (node (ref "VCC44") (pin "1") (pinfunction "1_1") (pintype "passive"))
      (node (ref "VCC44") (pin "2") (pinfunction "2_2") (pintype "passive"))
      (node (ref "VCC5") (pin "1") (pinfunction "1_1") (pintype "passive"))
      (node (ref "VCC5") (pin "2") (pinfunction "2_2") (pintype "passive"))
      (node (ref "VCC6") (pin "1") (pinfunction "1_1") (pintype "passive"))
      (node (ref "VCC6") (pin "2") (pinfunction "2_2") (pintype "passive"))
      (node (ref "VCC7") (pin "1") (pinfunction "1_1") (pintype "passive"))
      (node (ref "VCC7") (pin "2") (pinfunction "2_2") (pintype "passive"))
      (node (ref "VCC8") (pin "1") (pinfunction "1_1") (pintype "passive"))
      (node (ref "VCC8") (pin "2") (pinfunction "2_2") (pintype "passive"))
      (node (ref "VCC9") (pin "1") (pinfunction "1_1") (pintype "passive"))
      (node (ref "VCC9") (pin "2") (pinfunction "2_2") (pintype "passive"))
    )
    (net (code "847") (name "WRITE") (class "Default")
      (node (ref "D10") (pin "15") (pinfunction "15_15") (pintype "passive"))
      (node (ref "IC8") (pin "4") (pinfunction "A3_4") (pintype "input"))
      (node (ref "U$2") (pin "AS2") (pinfunction "1_AS2") (pintype "passive"))
    )
    (net (code "848") (name "unconnected-(IC8A-Y8-Pad11)") (class "Default")
      (node (ref "IC8") (pin "11") (pinfunction "Y8_11") (pintype "tri_state"))
    )
    (net (code "849") (name "~{BREAK_CYCLE}") (class "Default")
      (node (ref "D8") (pin "10") (pinfunction "10_10") (pintype "passive"))
      (node (ref "U$2") (pin "BL2") (pinfunction "1_BL2") (pintype "passive"))
    )
    (net (code "850") (name "~{BRK_DATA_CONT}") (class "Default")
      (node (ref "D8") (pin "9") (pinfunction "9_9") (pintype "passive"))
      (node (ref "U$2") (pin "BK2") (pinfunction "1_BK2") (pintype "passive"))
    )
    (net (code "851") (name "~{BRK_IN_PROG}") (class "Default")
      (node (ref "D8") (pin "5") (pinfunction "5_5") (pintype "passive"))
      (node (ref "U$2") (pin "BE2") (pinfunction "1_BE2") (pintype "passive"))
    )
    (net (code "852") (name "~{BUS_STROBE}") (class "Default")
      (node (ref "D11") (pin "9") (pinfunction "9_9") (pintype "passive"))
      (node (ref "U$2") (pin "CK1") (pinfunction "1_CK1") (pintype "passive"))
    )
    (net (code "853") (name "~{C0}") (class "Default")
      (node (ref "D11") (pin "5") (pinfunction "5_5") (pintype "passive"))
      (node (ref "U$2") (pin "CE1") (pinfunction "1_CE1") (pintype "passive"))
    )
    (net (code "854") (name "~{C1}") (class "Default")
      (node (ref "D11") (pin "7") (pinfunction "7_7") (pintype "passive"))
      (node (ref "U$2") (pin "CH1") (pinfunction "1_CH1") (pintype "passive"))
    )
    (net (code "855") (name "~{C2}") (class "Default")
      (node (ref "D11") (pin "8") (pinfunction "8_8") (pintype "passive"))
      (node (ref "U$2") (pin "CJ1") (pinfunction "1_CJ1") (pintype "passive"))
    )
    (net (code "856") (name "~{CE}") (class "Default")
      (node (ref "C2") (pin "1") (pinfunction "1_1") (pintype "passive"))
      (node (ref "IC3") (pin "20") (pinfunction "~{CE}_20") (pintype "input"))
      (node (ref "IC4") (pin "20") (pinfunction "~{CE}_20") (pintype "input"))
      (node (ref "Q1") (pin "1") (pinfunction "C_1") (pintype "passive"))
      (node (ref "R7") (pin "1") (pinfunction "1_1") (pintype "passive"))
    )
    (net (code "857") (name "~{CPMA_DISABLE}") (class "Default")
      (node (ref "D11") (pin "17") (pinfunction "17_17") (pintype "passive"))
      (node (ref "U$2") (pin "CU1") (pinfunction "1_CU1") (pintype "passive"))
    )
    (net (code "858") (name "~{DATA0}") (class "Default")
      (node (ref "D9") (pin "14") (pinfunction "14_14") (pintype "passive"))
      (node (ref "U$2") (pin "AR1") (pinfunction "1_AR1") (pintype "passive"))
    )
    (net (code "859") (name "~{DATA1}") (class "Default")
      (node (ref "D9") (pin "15") (pinfunction "15_15") (pintype "passive"))
      (node (ref "U$2") (pin "AS1") (pinfunction "1_AS1") (pintype "passive"))
    )
    (net (code "860") (name "~{DATA2}") (class "Default")
      (node (ref "D9") (pin "17") (pinfunction "17_17") (pintype "passive"))
      (node (ref "U$2") (pin "AU1") (pinfunction "1_AU1") (pintype "passive"))
    )
    (net (code "861") (name "~{DATA3}") (class "Default")
      (node (ref "D9") (pin "18") (pinfunction "18_18") (pintype "passive"))
      (node (ref "U$2") (pin "AV1") (pinfunction "1_AV1") (pintype "passive"))
    )
    (net (code "862") (name "~{DATA4}") (class "Default")
      (node (ref "D7") (pin "14") (pinfunction "14_14") (pintype "passive"))
      (node (ref "U$2") (pin "BR1") (pinfunction "1_BR1") (pintype "passive"))
    )
    (net (code "863") (name "~{DATA5}") (class "Default")
      (node (ref "D7") (pin "15") (pinfunction "15_15") (pintype "passive"))
      (node (ref "U$2") (pin "BS1") (pinfunction "1_BS1") (pintype "passive"))
    )
    (net (code "864") (name "~{DATA6}") (class "Default")
      (node (ref "D7") (pin "17") (pinfunction "17_17") (pintype "passive"))
      (node (ref "U$2") (pin "BU1") (pinfunction "1_BU1") (pintype "passive"))
    )
    (net (code "865") (name "~{DATA7}") (class "Default")
      (node (ref "D7") (pin "18") (pinfunction "18_18") (pintype "passive"))
      (node (ref "U$2") (pin "BV1") (pinfunction "1_BV1") (pintype "passive"))
    )
    (net (code "866") (name "~{DATA8}") (class "Default")
      (node (ref "D13") (pin "14") (pinfunction "14_14") (pintype "passive"))
      (node (ref "U$2") (pin "DR1") (pinfunction "1_DR1") (pintype "passive"))
    )
    (net (code "867") (name "~{DATA9}") (class "Default")
      (node (ref "D13") (pin "15") (pinfunction "15_15") (pintype "passive"))
      (node (ref "U$2") (pin "DS1") (pinfunction "1_DS1") (pintype "passive"))
    )
    (net (code "868") (name "~{DATA10}") (class "Default")
      (node (ref "D13") (pin "17") (pinfunction "17_17") (pintype "passive"))
      (node (ref "U$2") (pin "DU1") (pinfunction "1_DU1") (pintype "passive"))
    )
    (net (code "869") (name "~{DATA11}") (class "Default")
      (node (ref "D13") (pin "18") (pinfunction "18_18") (pintype "passive"))
      (node (ref "U$2") (pin "DV1") (pinfunction "1_DV1") (pintype "passive"))
    )
    (net (code "870") (name "~{D}") (class "Default")
      (node (ref "D14") (pin "9") (pinfunction "9_9") (pintype "passive"))
      (node (ref "U$2") (pin "DK2") (pinfunction "1_DK2") (pintype "passive"))
    )
    (net (code "871") (name "~{EMA0}") (class "Default")
      (node (ref "D10") (pin "4") (pinfunction "4_4") (pintype "passive"))
      (node (ref "IC3") (pin "8") (pinfunction "A2_8") (pintype "input"))
      (node (ref "IC4") (pin "8") (pinfunction "A2_8") (pintype "input"))
      (node (ref "IC5") (pin "1") (pinfunction "A_1") (pintype "input"))
      (node (ref "U$2") (pin "AD2") (pinfunction "1_AD2") (pintype "passive"))
    )
    (net (code "872") (name "~{EMA1}") (class "Default")
      (node (ref "D10") (pin "5") (pinfunction "5_5") (pintype "passive"))
      (node (ref "IC3") (pin "9") (pinfunction "A1_9") (pintype "input"))
      (node (ref "IC4") (pin "9") (pinfunction "A1_9") (pintype "input"))
      (node (ref "IC5") (pin "2") (pinfunction "B_2") (pintype "input"))
      (node (ref "U$2") (pin "AE2") (pinfunction "1_AE2") (pintype "passive"))
    )
    (net (code "873") (name "~{EMA2}") (class "Default")
      (node (ref "D10") (pin "7") (pinfunction "7_7") (pintype "passive"))
      (node (ref "IC3") (pin "10") (pinfunction "A0_10") (pintype "input"))
      (node (ref "IC4") (pin "10") (pinfunction "A0_10") (pintype "input"))
      (node (ref "IC5") (pin "3") (pinfunction "C_3") (pintype "input"))
      (node (ref "U$2") (pin "AH2") (pinfunction "1_AH2") (pintype "passive"))
    )
    (net (code "874") (name "~{E}") (class "Default")
      (node (ref "D14") (pin "10") (pinfunction "10_10") (pintype "passive"))
      (node (ref "U$2") (pin "DL2") (pinfunction "1_DL2") (pintype "passive"))
    )
    (net (code "875") (name "~{FSET}") (class "Default")
      (node (ref "D14") (pin "13") (pinfunction "13_13") (pintype "passive"))
      (node (ref "U$2") (pin "DP2") (pinfunction "1_DP2") (pintype "passive"))
    )
    (net (code "876") (name "~{F}") (class "Default")
      (node (ref "D14") (pin "8") (pinfunction "8_8") (pintype "passive"))
      (node (ref "U$2") (pin "DJ2") (pinfunction "1_DJ2") (pintype "passive"))
    )
    (net (code "877") (name "~{IND1}") (class "Default")
      (node (ref "D12") (pin "17") (pinfunction "17_17") (pintype "passive"))
      (node (ref "U$2") (pin "CU2") (pinfunction "1_CU2") (pintype "passive"))
    )
    (net (code "878") (name "~{IND2}") (class "Default")
      (node (ref "D12") (pin "18") (pinfunction "18_18") (pintype "passive"))
      (node (ref "U$2") (pin "CV2") (pinfunction "1_CV2") (pintype "passive"))
    )
    (net (code "879") (name "~{INTERNAL_IO}") (class "Default")
      (node (ref "D11") (pin "10") (pinfunction "10_10") (pintype "passive"))
      (node (ref "U$2") (pin "CL1") (pinfunction "1_CL1") (pintype "passive"))
    )
    (net (code "880") (name "~{INT_RQST}") (class "Default")
      (node (ref "D11") (pin "13") (pinfunction "13_13") (pintype "passive"))
      (node (ref "U$2") (pin "CP1") (pinfunction "1_CP1") (pintype "passive"))
    )
    (net (code "881") (name "~{IO_PAUSE}") (class "Default")
      (node (ref "D11") (pin "4") (pinfunction "4_4") (pintype "passive"))
      (node (ref "U$2") (pin "CD1") (pinfunction "1_CD1") (pintype "passive"))
    )
    (net (code "882") (name "~{IR0}") (class "Default")
      (node (ref "D14") (pin "4") (pinfunction "4_4") (pintype "passive"))
      (node (ref "U$2") (pin "DD2") (pinfunction "1_DD2") (pintype "passive"))
    )
    (net (code "883") (name "~{IR1}") (class "Default")
      (node (ref "D14") (pin "5") (pinfunction "5_5") (pintype "passive"))
      (node (ref "U$2") (pin "DE2") (pinfunction "1_DE2") (pintype "passive"))
    )
    (net (code "884") (name "~{IR2}") (class "Default")
      (node (ref "D14") (pin "7") (pinfunction "7_7") (pintype "passive"))
      (node (ref "U$2") (pin "DH2") (pinfunction "1_DH2") (pintype "passive"))
    )
    (net (code "885") (name "~{KEY_CONT}") (class "Default")
      (node (ref "D14") (pin "17") (pinfunction "17_17") (pintype "passive"))
      (node (ref "U$2") (pin "DU2") (pinfunction "1_DU2") (pintype "passive"))
    )
    (net (code "886") (name "~{LA_ENABLE}") (class "Default")
      (node (ref "D8") (pin "11") (pinfunction "11_11") (pintype "passive"))
      (node (ref "U$2") (pin "BM2") (pinfunction "1_BM2") (pintype "passive"))
    )
    (net (code "887") (name "~{LINK_DATA}") (class "Default")
      (node (ref "D12") (pin "14") (pinfunction "14_14") (pintype "passive"))
      (node (ref "U$2") (pin "CR2") (pinfunction "1_CR2") (pintype "passive"))
    )
    (net (code "888") (name "~{LINK_LOAD}") (class "Default")
      (node (ref "D12") (pin "15") (pinfunction "15_15") (pintype "passive"))
      (node (ref "U$2") (pin "CS2") (pinfunction "1_CS2") (pintype "passive"))
    )
    (net (code "889") (name "~{LINK}") (class "Default")
      (node (ref "D10") (pin "18") (pinfunction "18_18") (pintype "passive"))
      (node (ref "U$2") (pin "AV2") (pinfunction "1_AV2") (pintype "passive"))
    )
    (net (code "890") (name "~{LOAD_CONT}") (class "Default")
      (node (ref "D8") (pin "7") (pinfunction "7_7") (pintype "passive"))
      (node (ref "U$2") (pin "BH2") (pinfunction "1_BH2") (pintype "passive"))
    )
    (net (code "891") (name "~{MA00}") (class "Default")
      (node (ref "D9") (pin "4") (pinfunction "4_4") (pintype "passive"))
      (node (ref "IC3") (pin "21") (pinfunction "A10_21") (pintype "input"))
      (node (ref "IC4") (pin "21") (pinfunction "A10_21") (pintype "input"))
      (node (ref "U$2") (pin "AD1") (pinfunction "1_AD1") (pintype "passive"))
    )
    (net (code "892") (name "~{MA01}") (class "Default")
      (node (ref "D9") (pin "5") (pinfunction "5_5") (pintype "passive"))
      (node (ref "IC3") (pin "23") (pinfunction "A11_23") (pintype "input"))
      (node (ref "IC4") (pin "23") (pinfunction "A11_23") (pintype "input"))
      (node (ref "U$2") (pin "AE1") (pinfunction "1_AE1") (pintype "passive"))
    )
    (net (code "893") (name "~{MA02}") (class "Default")
      (node (ref "D9") (pin "7") (pinfunction "7_7") (pintype "passive"))
      (node (ref "IC3") (pin "24") (pinfunction "A9_24") (pintype "input"))
      (node (ref "IC4") (pin "24") (pinfunction "A9_24") (pintype "input"))
      (node (ref "U$2") (pin "AH1") (pinfunction "1_AH1") (pintype "passive"))
    )
    (net (code "894") (name "~{MA03}") (class "Default")
      (node (ref "D9") (pin "8") (pinfunction "8_8") (pintype "passive"))
      (node (ref "IC3") (pin "25") (pinfunction "A8_25") (pintype "input"))
      (node (ref "IC4") (pin "25") (pinfunction "A8_25") (pintype "input"))
      (node (ref "U$2") (pin "AJ1") (pinfunction "1_AJ1") (pintype "passive"))
    )
    (net (code "895") (name "~{MA04}") (class "Default")
      (node (ref "D7") (pin "4") (pinfunction "4_4") (pintype "passive"))
      (node (ref "IC3") (pin "26") (pinfunction "A13_26") (pintype "input"))
      (node (ref "IC4") (pin "26") (pinfunction "A13_26") (pintype "input"))
      (node (ref "U$2") (pin "BD1") (pinfunction "1_BD1") (pintype "passive"))
    )
    (net (code "896") (name "~{MA05}") (class "Default")
      (node (ref "D7") (pin "5") (pinfunction "5_5") (pintype "passive"))
      (node (ref "IC3") (pin "1") (pinfunction "A14_1") (pintype "input"))
      (node (ref "IC4") (pin "1") (pinfunction "A14_1") (pintype "input"))
      (node (ref "U$2") (pin "BE1") (pinfunction "1_BE1") (pintype "passive"))
    )
    (net (code "897") (name "~{MA06}") (class "Default")
      (node (ref "D7") (pin "7") (pinfunction "7_7") (pintype "passive"))
      (node (ref "IC3") (pin "2") (pinfunction "A12_2") (pintype "input"))
      (node (ref "IC4") (pin "2") (pinfunction "A12_2") (pintype "input"))
      (node (ref "U$2") (pin "BH1") (pinfunction "1_BH1") (pintype "passive"))
    )
    (net (code "898") (name "~{MA07}") (class "Default")
      (node (ref "D7") (pin "8") (pinfunction "8_8") (pintype "passive"))
      (node (ref "IC3") (pin "3") (pinfunction "A7_3") (pintype "input"))
      (node (ref "IC4") (pin "3") (pinfunction "A7_3") (pintype "input"))
      (node (ref "U$2") (pin "BJ1") (pinfunction "1_BJ1") (pintype "passive"))
    )
    (net (code "899") (name "~{MA08}") (class "Default")
      (node (ref "D13") (pin "4") (pinfunction "4_4") (pintype "passive"))
      (node (ref "IC3") (pin "4") (pinfunction "A6_4") (pintype "input"))
      (node (ref "IC4") (pin "4") (pinfunction "A6_4") (pintype "input"))
      (node (ref "U$2") (pin "DD1") (pinfunction "1_DD1") (pintype "passive"))
    )
    (net (code "900") (name "~{MA09}") (class "Default")
      (node (ref "D13") (pin "5") (pinfunction "5_5") (pintype "passive"))
      (node (ref "IC3") (pin "5") (pinfunction "A5_5") (pintype "input"))
      (node (ref "IC4") (pin "5") (pinfunction "A5_5") (pintype "input"))
      (node (ref "U$2") (pin "DE1") (pinfunction "1_DE1") (pintype "passive"))
    )
    (net (code "901") (name "~{MA10}") (class "Default")
      (node (ref "D13") (pin "7") (pinfunction "7_7") (pintype "passive"))
      (node (ref "IC3") (pin "6") (pinfunction "A4_6") (pintype "input"))
      (node (ref "IC4") (pin "6") (pinfunction "A4_6") (pintype "input"))
      (node (ref "U$2") (pin "DH1") (pinfunction "1_DH1") (pintype "passive"))
    )
    (net (code "902") (name "~{MA11}") (class "Default")
      (node (ref "D13") (pin "8") (pinfunction "8_8") (pintype "passive"))
      (node (ref "IC3") (pin "7") (pinfunction "A3_7") (pintype "input"))
      (node (ref "IC4") (pin "7") (pinfunction "A3_7") (pintype "input"))
      (node (ref "U$2") (pin "DJ1") (pinfunction "1_DJ1") (pintype "passive"))
    )
    (net (code "903") (name "~{MD00}") (class "Default")
      (node (ref "D9") (pin "9") (pinfunction "9_9") (pintype "passive"))
      (node (ref "IC1") (pin "2") (pinfunction "A1_2") (pintype "bidirectional"))
      (node (ref "U$2") (pin "AK1") (pinfunction "1_AK1") (pintype "passive"))
    )
    (net (code "904") (name "~{MD01}") (class "Default")
      (node (ref "D9") (pin "10") (pinfunction "10_10") (pintype "passive"))
      (node (ref "IC1") (pin "3") (pinfunction "A2_3") (pintype "bidirectional"))
      (node (ref "U$2") (pin "AL1") (pinfunction "1_AL1") (pintype "passive"))
    )
    (net (code "905") (name "~{MD02}") (class "Default")
      (node (ref "D9") (pin "11") (pinfunction "11_11") (pintype "passive"))
      (node (ref "IC1") (pin "4") (pinfunction "A3_4") (pintype "bidirectional"))
      (node (ref "U$2") (pin "AM1") (pinfunction "1_AM1") (pintype "passive"))
    )
    (net (code "906") (name "~{MD03}") (class "Default")
      (node (ref "D9") (pin "13") (pinfunction "13_13") (pintype "passive"))
      (node (ref "IC1") (pin "5") (pinfunction "A4_5") (pintype "bidirectional"))
      (node (ref "U$2") (pin "AP1") (pinfunction "1_AP1") (pintype "passive"))
    )
    (net (code "907") (name "~{MD04}") (class "Default")
      (node (ref "D7") (pin "9") (pinfunction "9_9") (pintype "passive"))
      (node (ref "IC1") (pin "6") (pinfunction "A5_6") (pintype "bidirectional"))
      (node (ref "U$2") (pin "BK1") (pinfunction "1_BK1") (pintype "passive"))
    )
    (net (code "908") (name "~{MD05}") (class "Default")
      (node (ref "D7") (pin "10") (pinfunction "10_10") (pintype "passive"))
      (node (ref "IC1") (pin "7") (pinfunction "A6_7") (pintype "bidirectional"))
      (node (ref "U$2") (pin "BL1") (pinfunction "1_BL1") (pintype "passive"))
    )
    (net (code "909") (name "~{MD06}") (class "Default")
      (node (ref "D7") (pin "11") (pinfunction "11_11") (pintype "passive"))
      (node (ref "IC1") (pin "8") (pinfunction "A7_8") (pintype "bidirectional"))
      (node (ref "U$2") (pin "BM1") (pinfunction "1_BM1") (pintype "passive"))
    )
    (net (code "910") (name "~{MD07}") (class "Default")
      (node (ref "D7") (pin "13") (pinfunction "13_13") (pintype "passive"))
      (node (ref "IC1") (pin "9") (pinfunction "A8_9") (pintype "bidirectional"))
      (node (ref "U$2") (pin "BP1") (pinfunction "1_BP1") (pintype "passive"))
    )
    (net (code "911") (name "~{MD08}") (class "Default")
      (node (ref "D13") (pin "9") (pinfunction "9_9") (pintype "passive"))
      (node (ref "IC2") (pin "2") (pinfunction "A1_2") (pintype "bidirectional"))
      (node (ref "U$2") (pin "DK1") (pinfunction "1_DK1") (pintype "passive"))
    )
    (net (code "912") (name "~{MD09}") (class "Default")
      (node (ref "D13") (pin "10") (pinfunction "10_10") (pintype "passive"))
      (node (ref "IC2") (pin "3") (pinfunction "A2_3") (pintype "bidirectional"))
      (node (ref "U$2") (pin "DL1") (pinfunction "1_DL1") (pintype "passive"))
    )
    (net (code "913") (name "~{MD10}") (class "Default")
      (node (ref "D13") (pin "11") (pinfunction "11_11") (pintype "passive"))
      (node (ref "IC2") (pin "4") (pinfunction "A3_4") (pintype "bidirectional"))
      (node (ref "U$2") (pin "DM1") (pinfunction "1_DM1") (pintype "passive"))
    )
    (net (code "914") (name "~{MD11}") (class "Default")
      (node (ref "D13") (pin "13") (pinfunction "13_13") (pintype "passive"))
      (node (ref "IC2") (pin "5") (pinfunction "A4_5") (pintype "bidirectional"))
      (node (ref "U$2") (pin "DP1") (pinfunction "1_DP1") (pintype "passive"))
    )
    (net (code "915") (name "~{MD_DIR}") (class "Default")
      (node (ref "D10") (pin "9") (pinfunction "9_9") (pintype "passive"))
      (node (ref "IC8") (pin "2") (pinfunction "A1_2") (pintype "input"))
      (node (ref "U$2") (pin "AK2") (pinfunction "1_AK2") (pintype "passive"))
    )
    (net (code "916") (name "~{MEM_START}") (class "Default")
      (node (ref "D10") (pin "8") (pinfunction "8_8") (pintype "passive"))
      (node (ref "U$2") (pin "AJ2") (pinfunction "1_AJ2") (pintype "passive"))
    )
    (net (code "917") (name "~{MS_DISABLE}") (class "Default")
      (node (ref "D11") (pin "18") (pinfunction "18_18") (pintype "passive"))
      (node (ref "U$2") (pin "CV1") (pinfunction "1_CV1") (pintype "passive"))
    )
    (net (code "918") (name "~{NOT_LAST_TR}") (class "Default")
      (node (ref "D11") (pin "11") (pinfunction "11_11") (pintype "passive"))
      (node (ref "U$2") (pin "CM1") (pinfunction "1_CM1") (pintype "passive"))
    )
    (net (code "919") (name "~{NTS_STALL}") (class "Default")
      (node (ref "D8") (pin "14") (pinfunction "14_14") (pintype "passive"))
      (node (ref "U$2") (pin "BR2") (pinfunction "1_BR2") (pintype "passive"))
    )
    (net (code "920") (name "~{OVERFLOW}") (class "Default")
      (node (ref "D8") (pin "8") (pinfunction "8_8") (pintype "passive"))
      (node (ref "U$2") (pin "BJ2") (pinfunction "1_BJ2") (pintype "passive"))
    )
    (net (code "921") (name "~{READ_EN}") (class "Default")
      (node (ref "IC1") (pin "1") (pinfunction "DIR_1") (pintype "input"))
      (node (ref "IC2") (pin "1") (pinfunction "DIR_1") (pintype "input"))
      (node (ref "IC3") (pin "22") (pinfunction "~{OE}_22") (pintype "input"))
      (node (ref "IC4") (pin "22") (pinfunction "~{OE}_22") (pintype "input"))
      (node (ref "IC7") (pin "8") (pinfunction "O_8") (pintype "output"))
    )
    (net (code "922") (name "~{ROM_ADDR}") (class "Default")
      (node (ref "D10") (pin "17") (pinfunction "17_17") (pintype "passive"))
      (node (ref "IC5") (pin "6") (pinfunction "G1_6") (pintype "input"))
      (node (ref "U$2") (pin "AU2") (pinfunction "1_AU2") (pintype "passive"))
    )
    (net (code "923") (name "~{RUN}") (class "Default")
      (node (ref "D8") (pin "17") (pinfunction "17_17") (pintype "passive"))
      (node (ref "U$2") (pin "BU2") (pinfunction "1_BU2") (pintype "passive"))
    )
    (net (code "924") (name "~{SKIP}") (class "Default")
      (node (ref "D11") (pin "15") (pinfunction "15_15") (pintype "passive"))
      (node (ref "U$2") (pin "CS1") (pinfunction "1_CS1") (pintype "passive"))
    )
    (net (code "925") (name "~{STOP}") (class "Default")
      (node (ref "D14") (pin "15") (pinfunction "15_15") (pintype "passive"))
      (node (ref "U$2") (pin "DS2") (pinfunction "1_DS2") (pintype "passive"))
    )
    (net (code "926") (name "~{TS1}") (class "Default")
      (node (ref "D12") (pin "9") (pinfunction "9_9") (pintype "passive"))
      (node (ref "U$2") (pin "CK2") (pinfunction "1_CK2") (pintype "passive"))
    )
    (net (code "927") (name "~{TS2}") (class "Default")
      (node (ref "D12") (pin "10") (pinfunction "10_10") (pintype "passive"))
      (node (ref "U$2") (pin "CL2") (pinfunction "1_CL2") (pintype "passive"))
    )
    (net (code "928") (name "~{TS3}") (class "Default")
      (node (ref "D12") (pin "11") (pinfunction "11_11") (pintype "passive"))
      (node (ref "U$2") (pin "CM2") (pinfunction "1_CM2") (pintype "passive"))
    )
    (net (code "929") (name "~{TS4}") (class "Default")
      (node (ref "D12") (pin "13") (pinfunction "13_13") (pintype "passive"))
      (node (ref "U$2") (pin "CP2") (pinfunction "1_CP2") (pintype "passive"))
    )
    (net (code "930") (name "~{USER_MODE}") (class "Default")
      (node (ref "D14") (pin "11") (pinfunction "11_11") (pintype "passive"))
      (node (ref "U$2") (pin "DM2") (pinfunction "1_DM2") (pintype "passive"))
    )
    (net (code "931") (name "~{WRITE_EN}") (class "Default")
      (node (ref "IC3") (pin "27") (pinfunction "~{WE}_27") (pintype "input"))
      (node (ref "IC4") (pin "27") (pinfunction "~{WE}_27") (pintype "input"))
      (node (ref "IC7") (pin "6") (pinfunction "O_6") (pintype "output"))
    )
  )
)
